# oresat-backplane.net
KiCad netlist of a schematic drawn in EAGLE
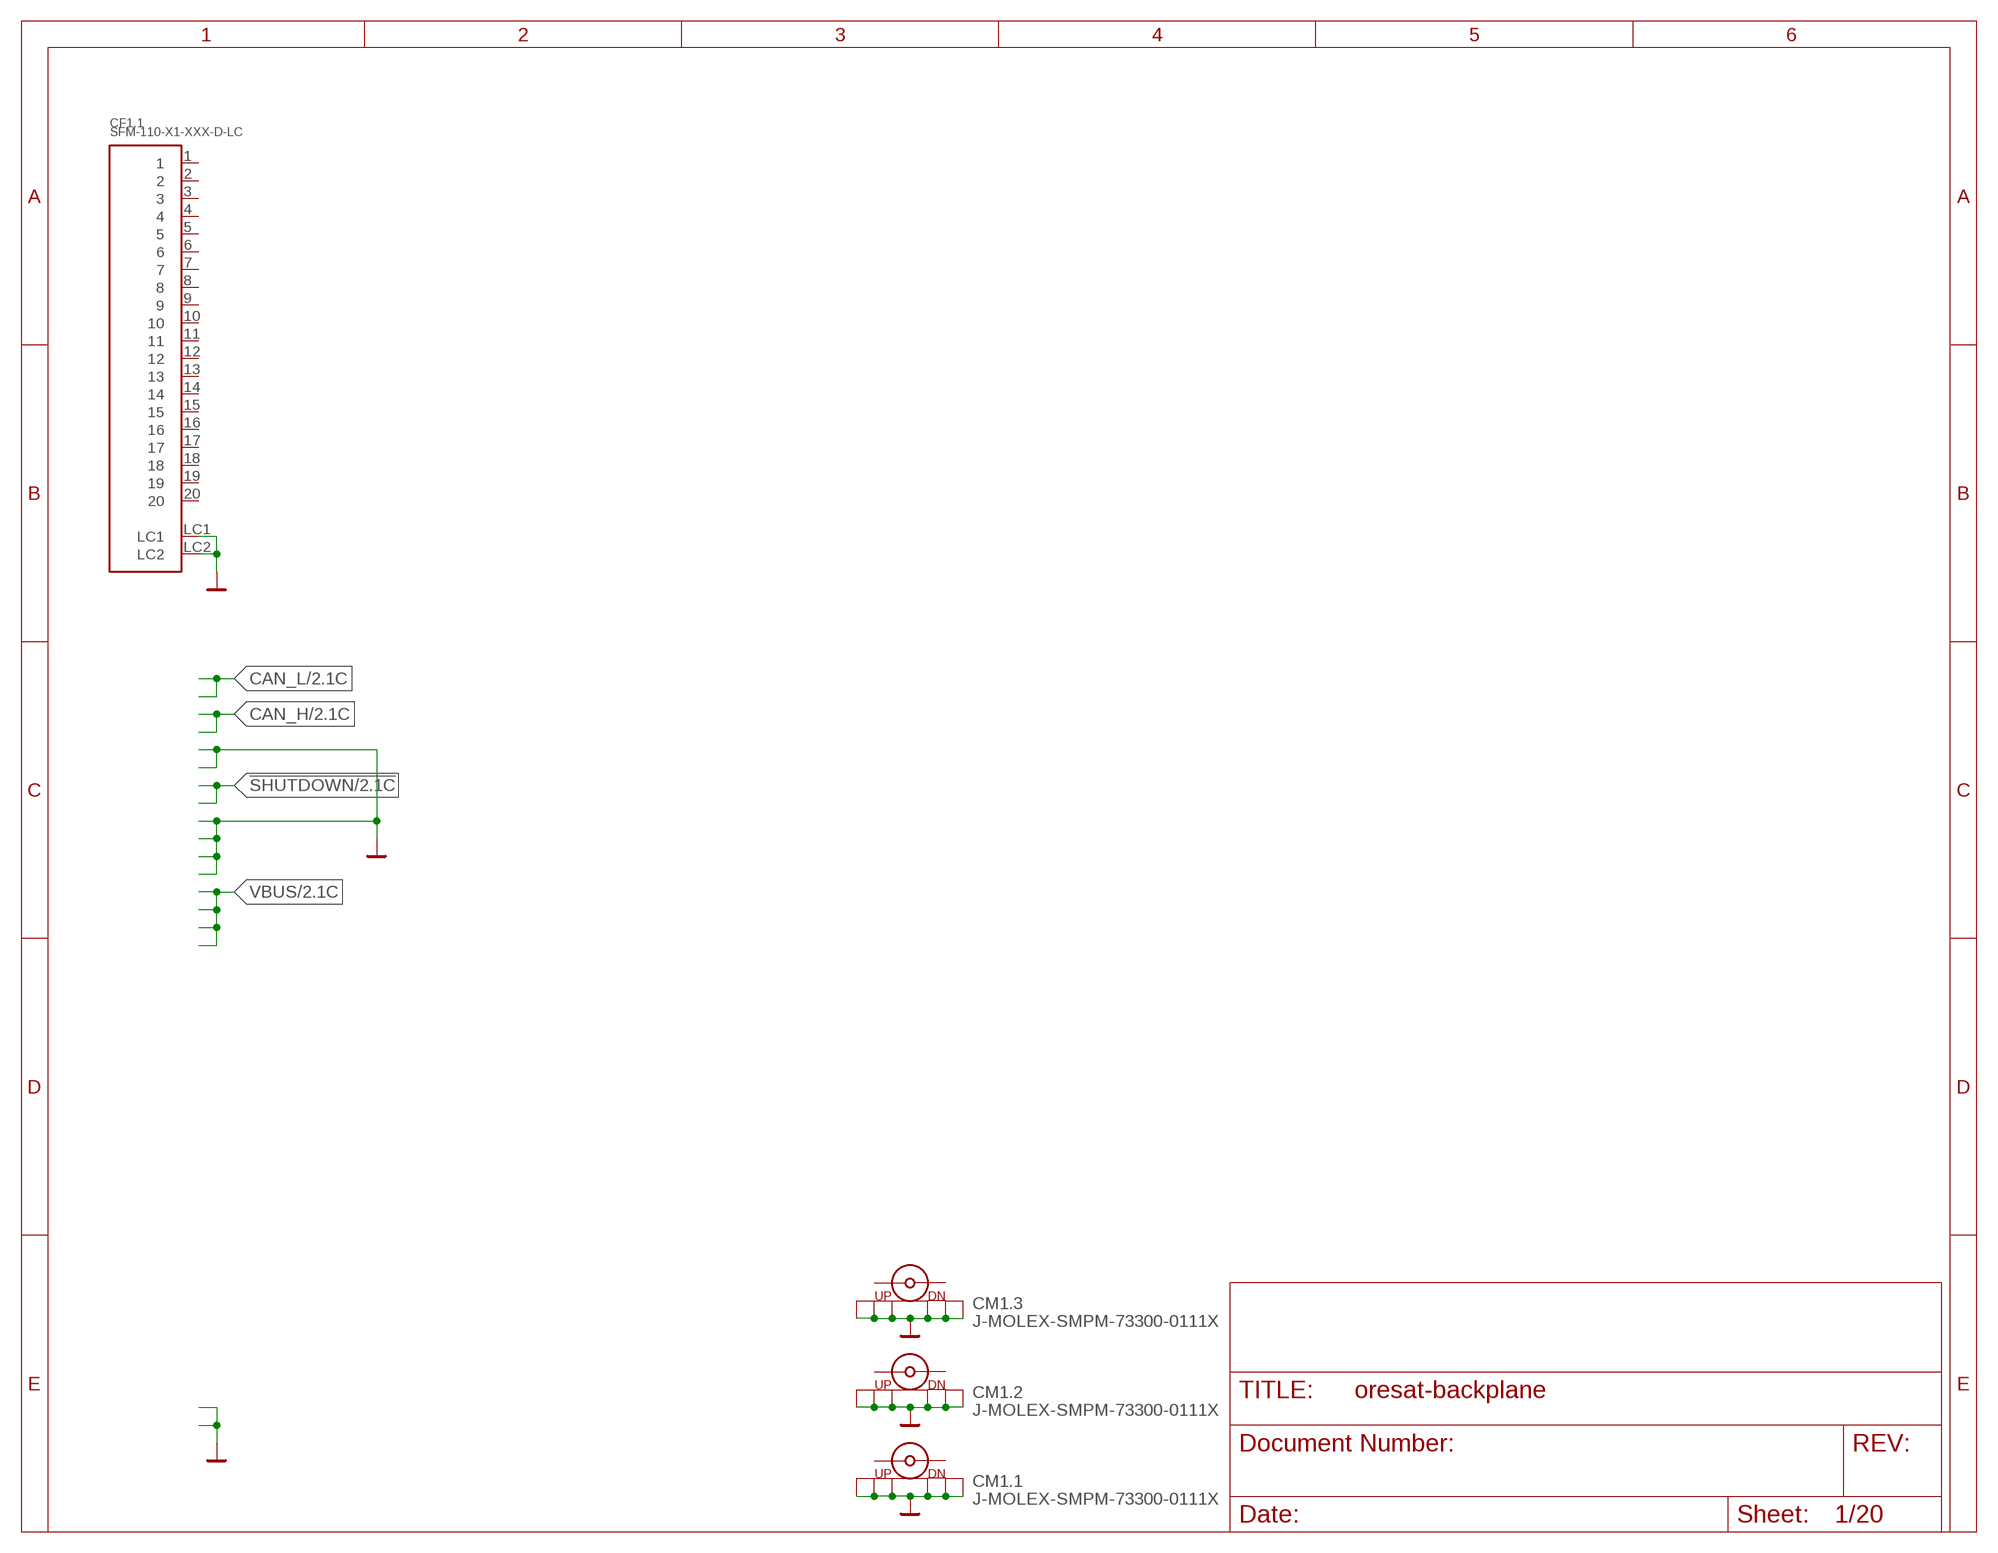
[diagram p0: schematic, sheet 1]
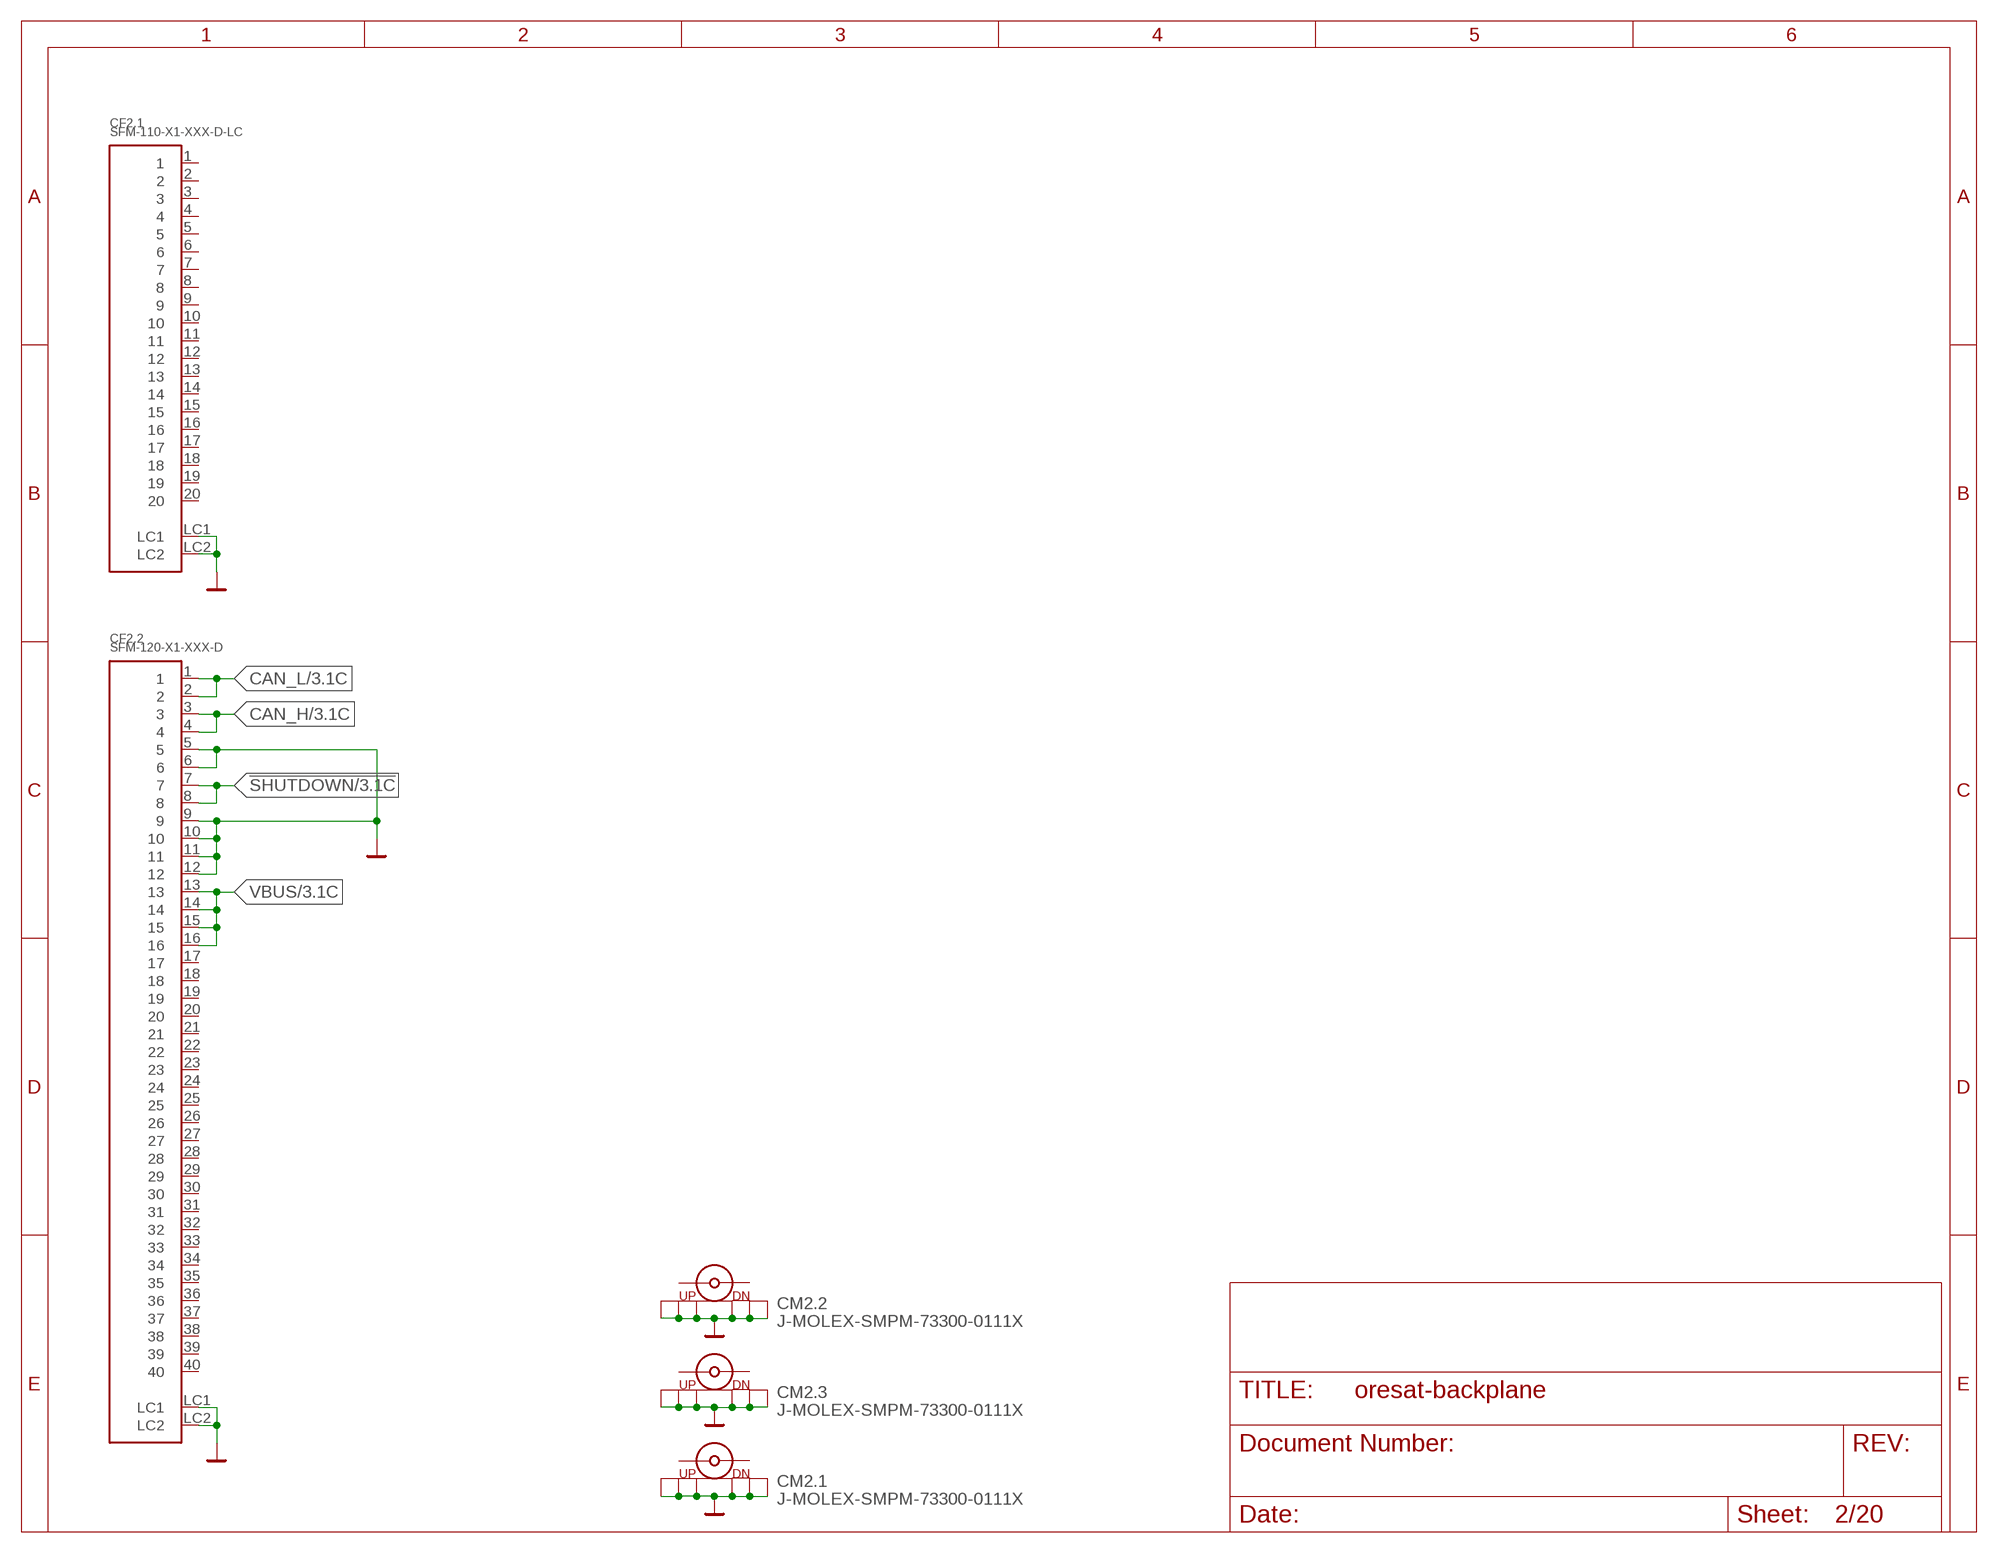
[diagram p1: schematic, sheet 2]
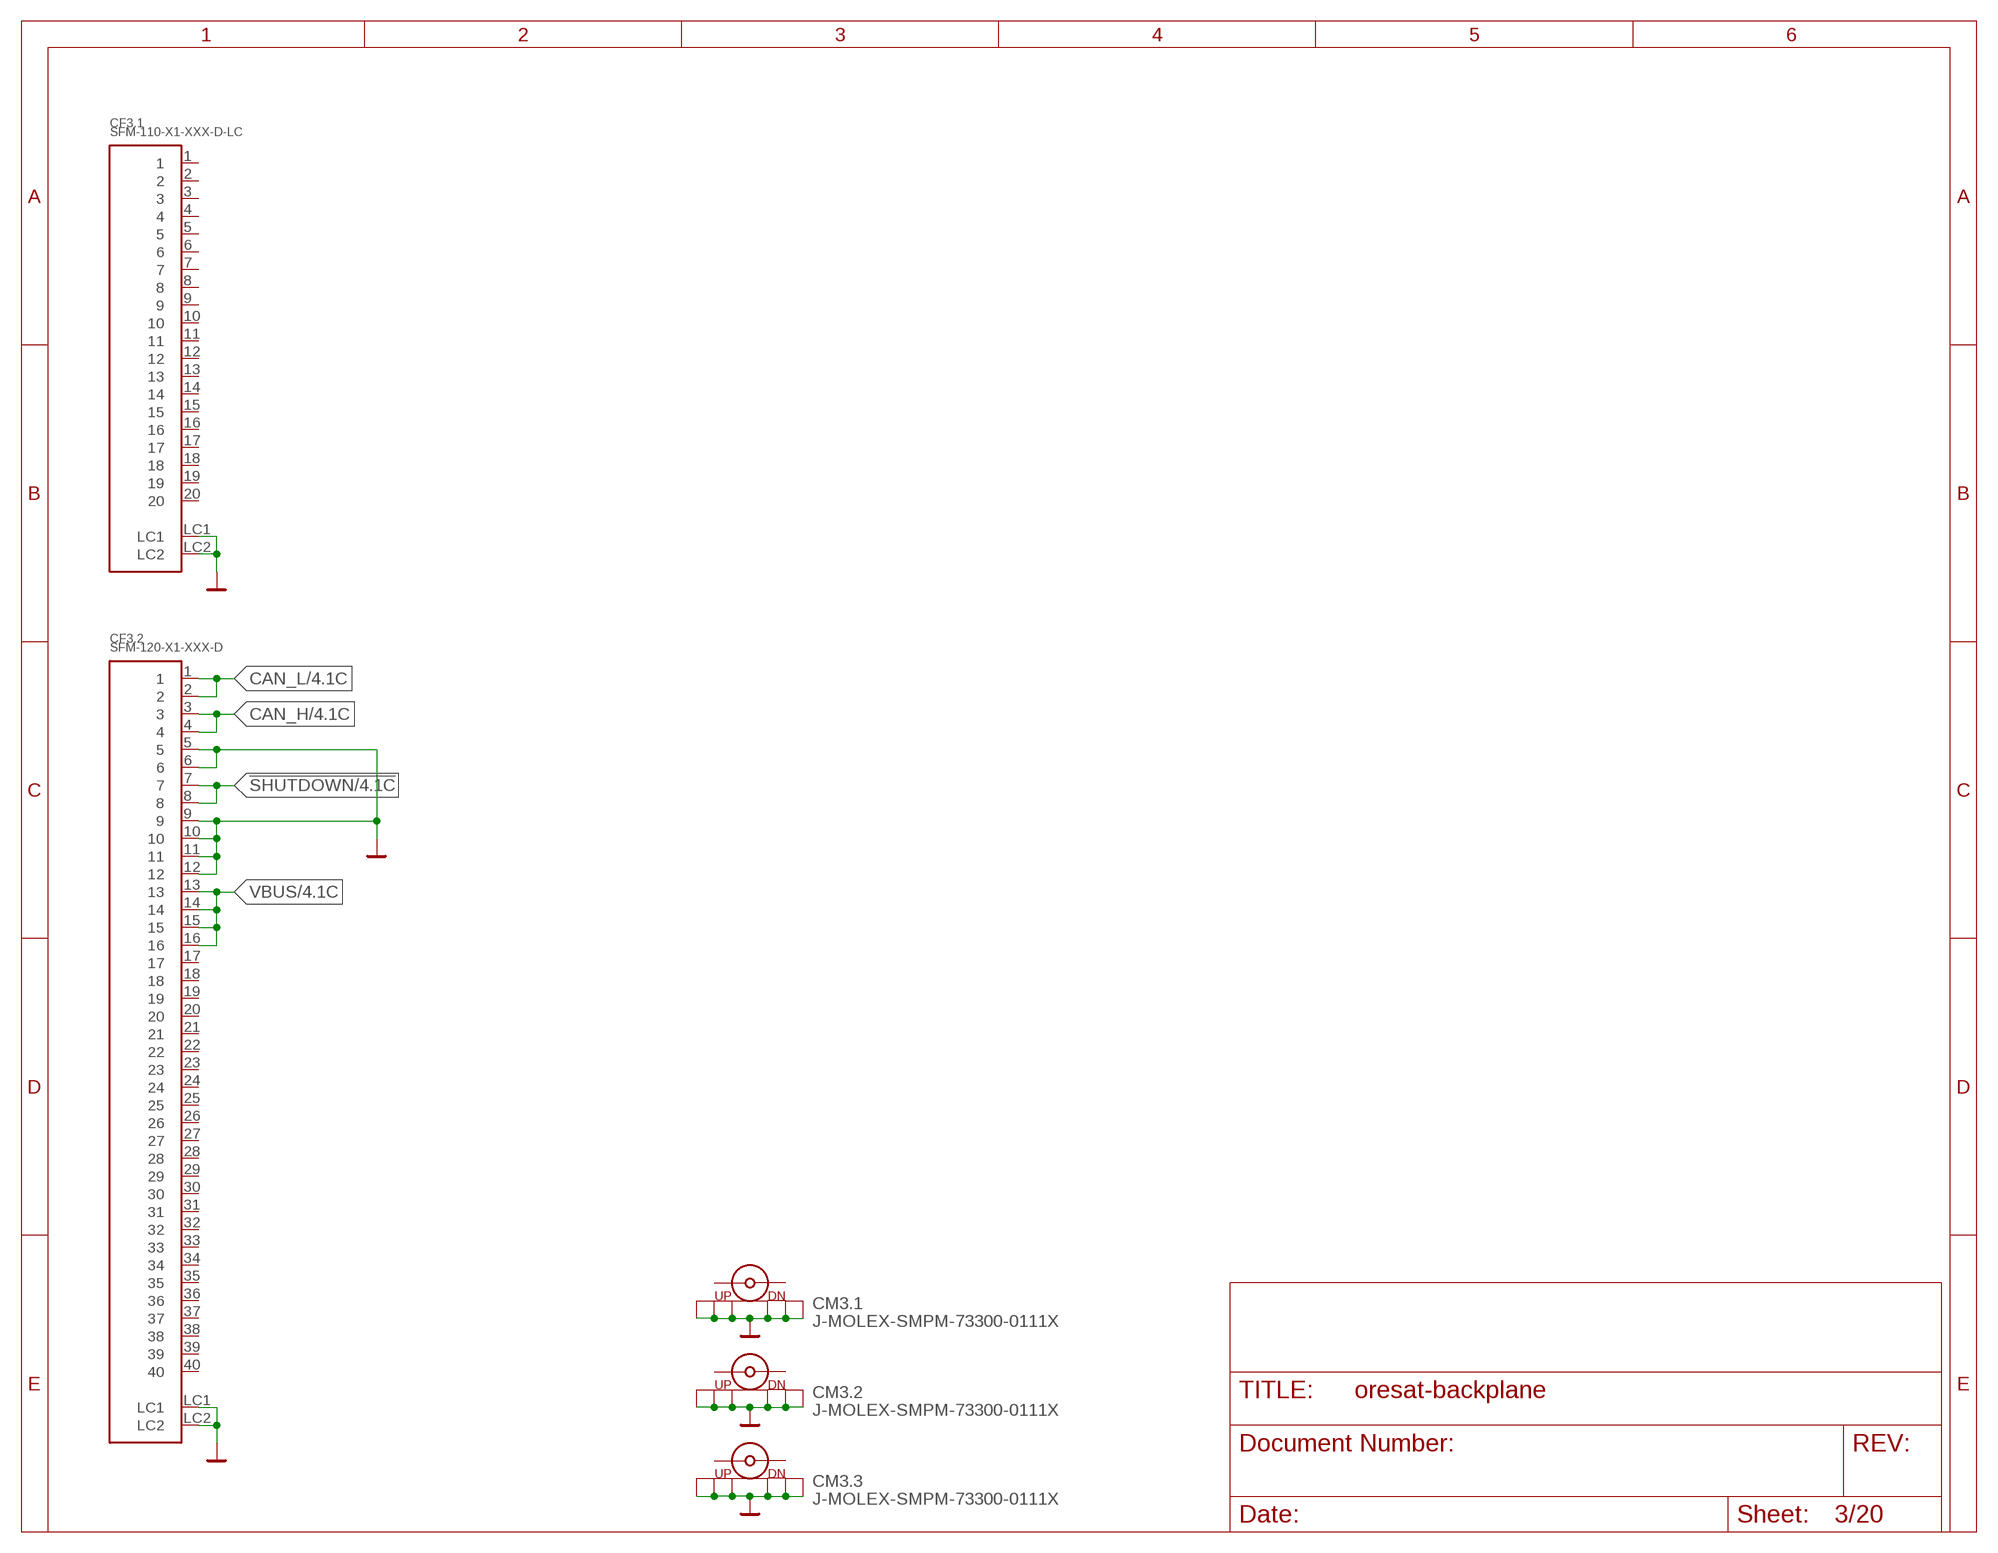
[diagram p2: schematic, sheet 3]
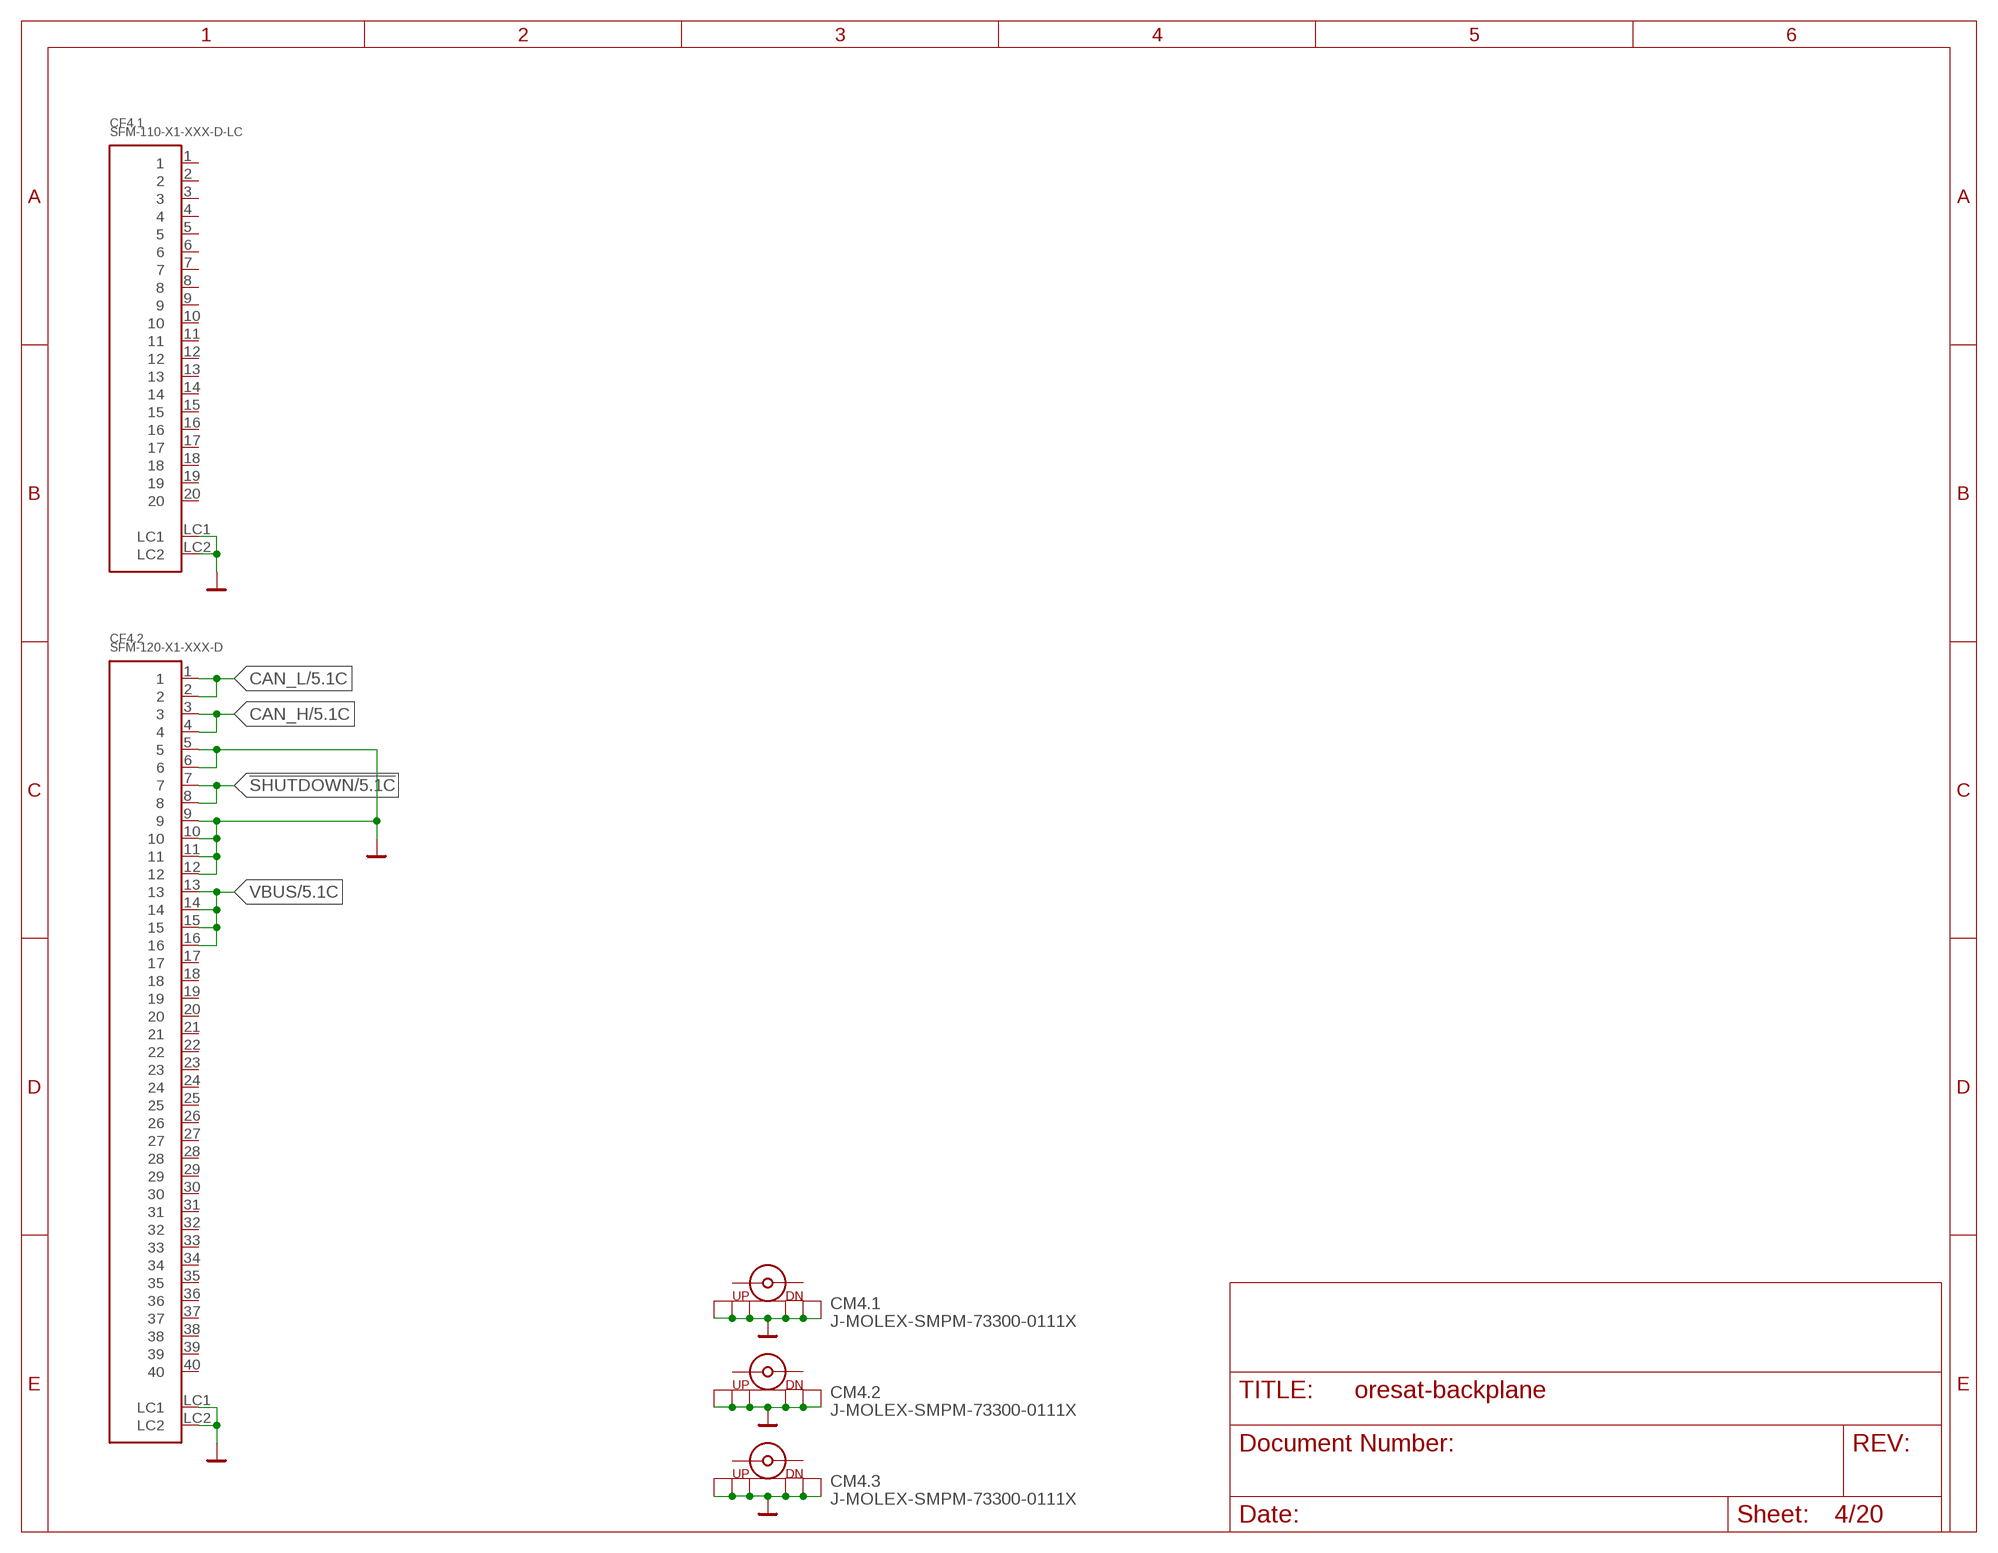
[diagram p3: schematic, sheet 4]
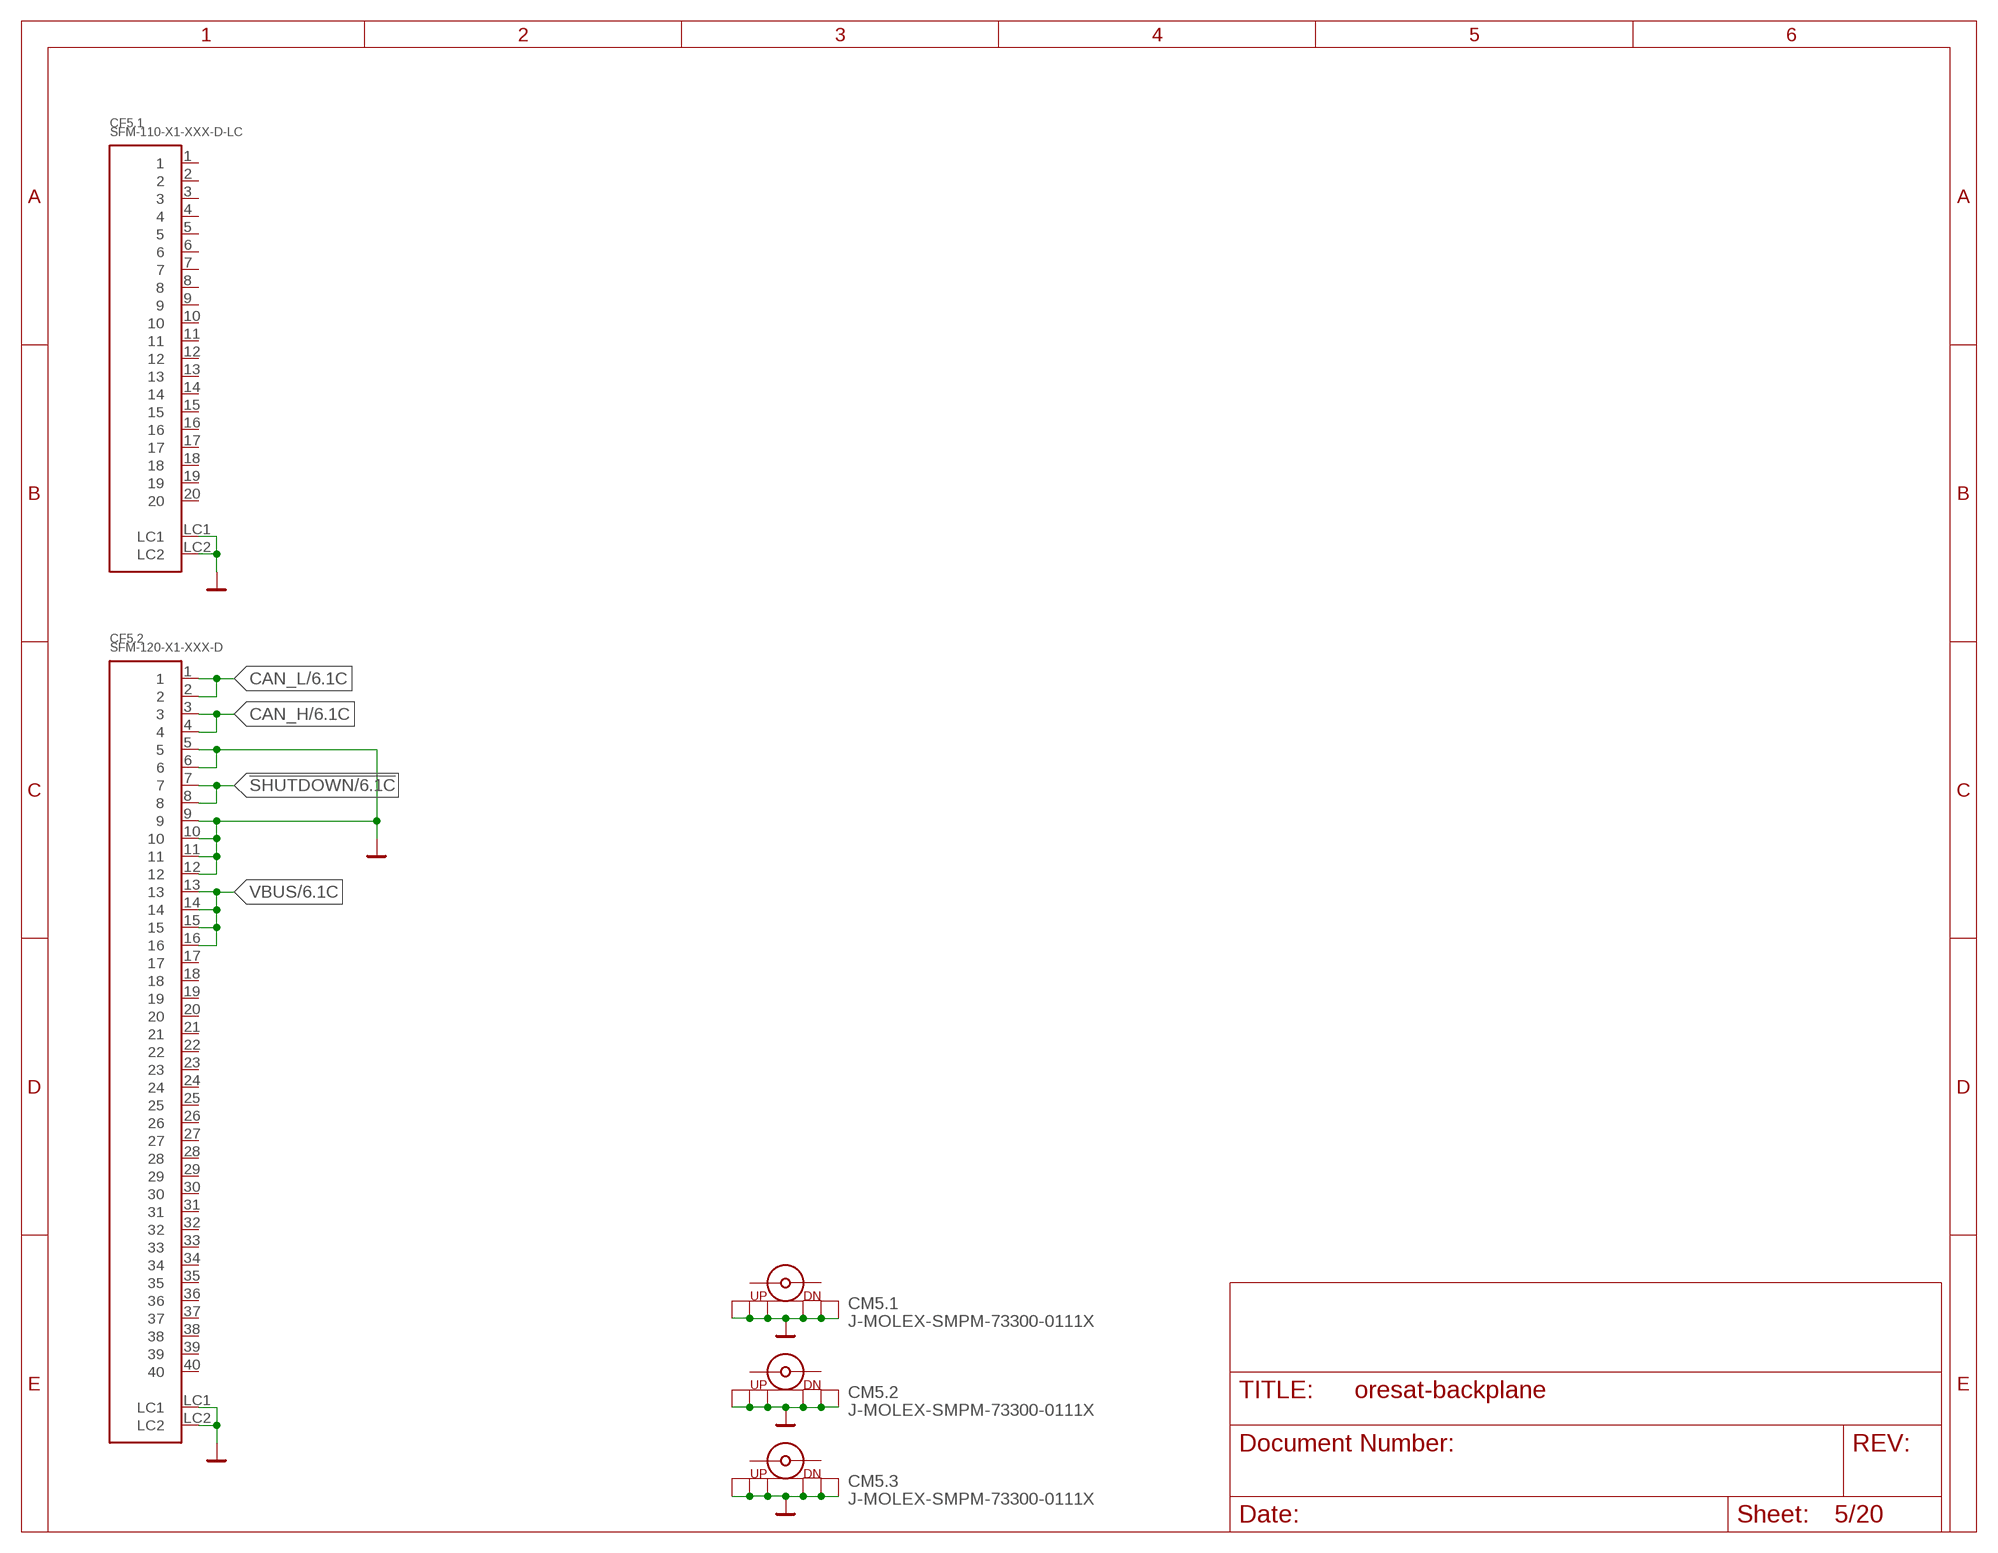
[diagram p4: schematic, sheet 5]
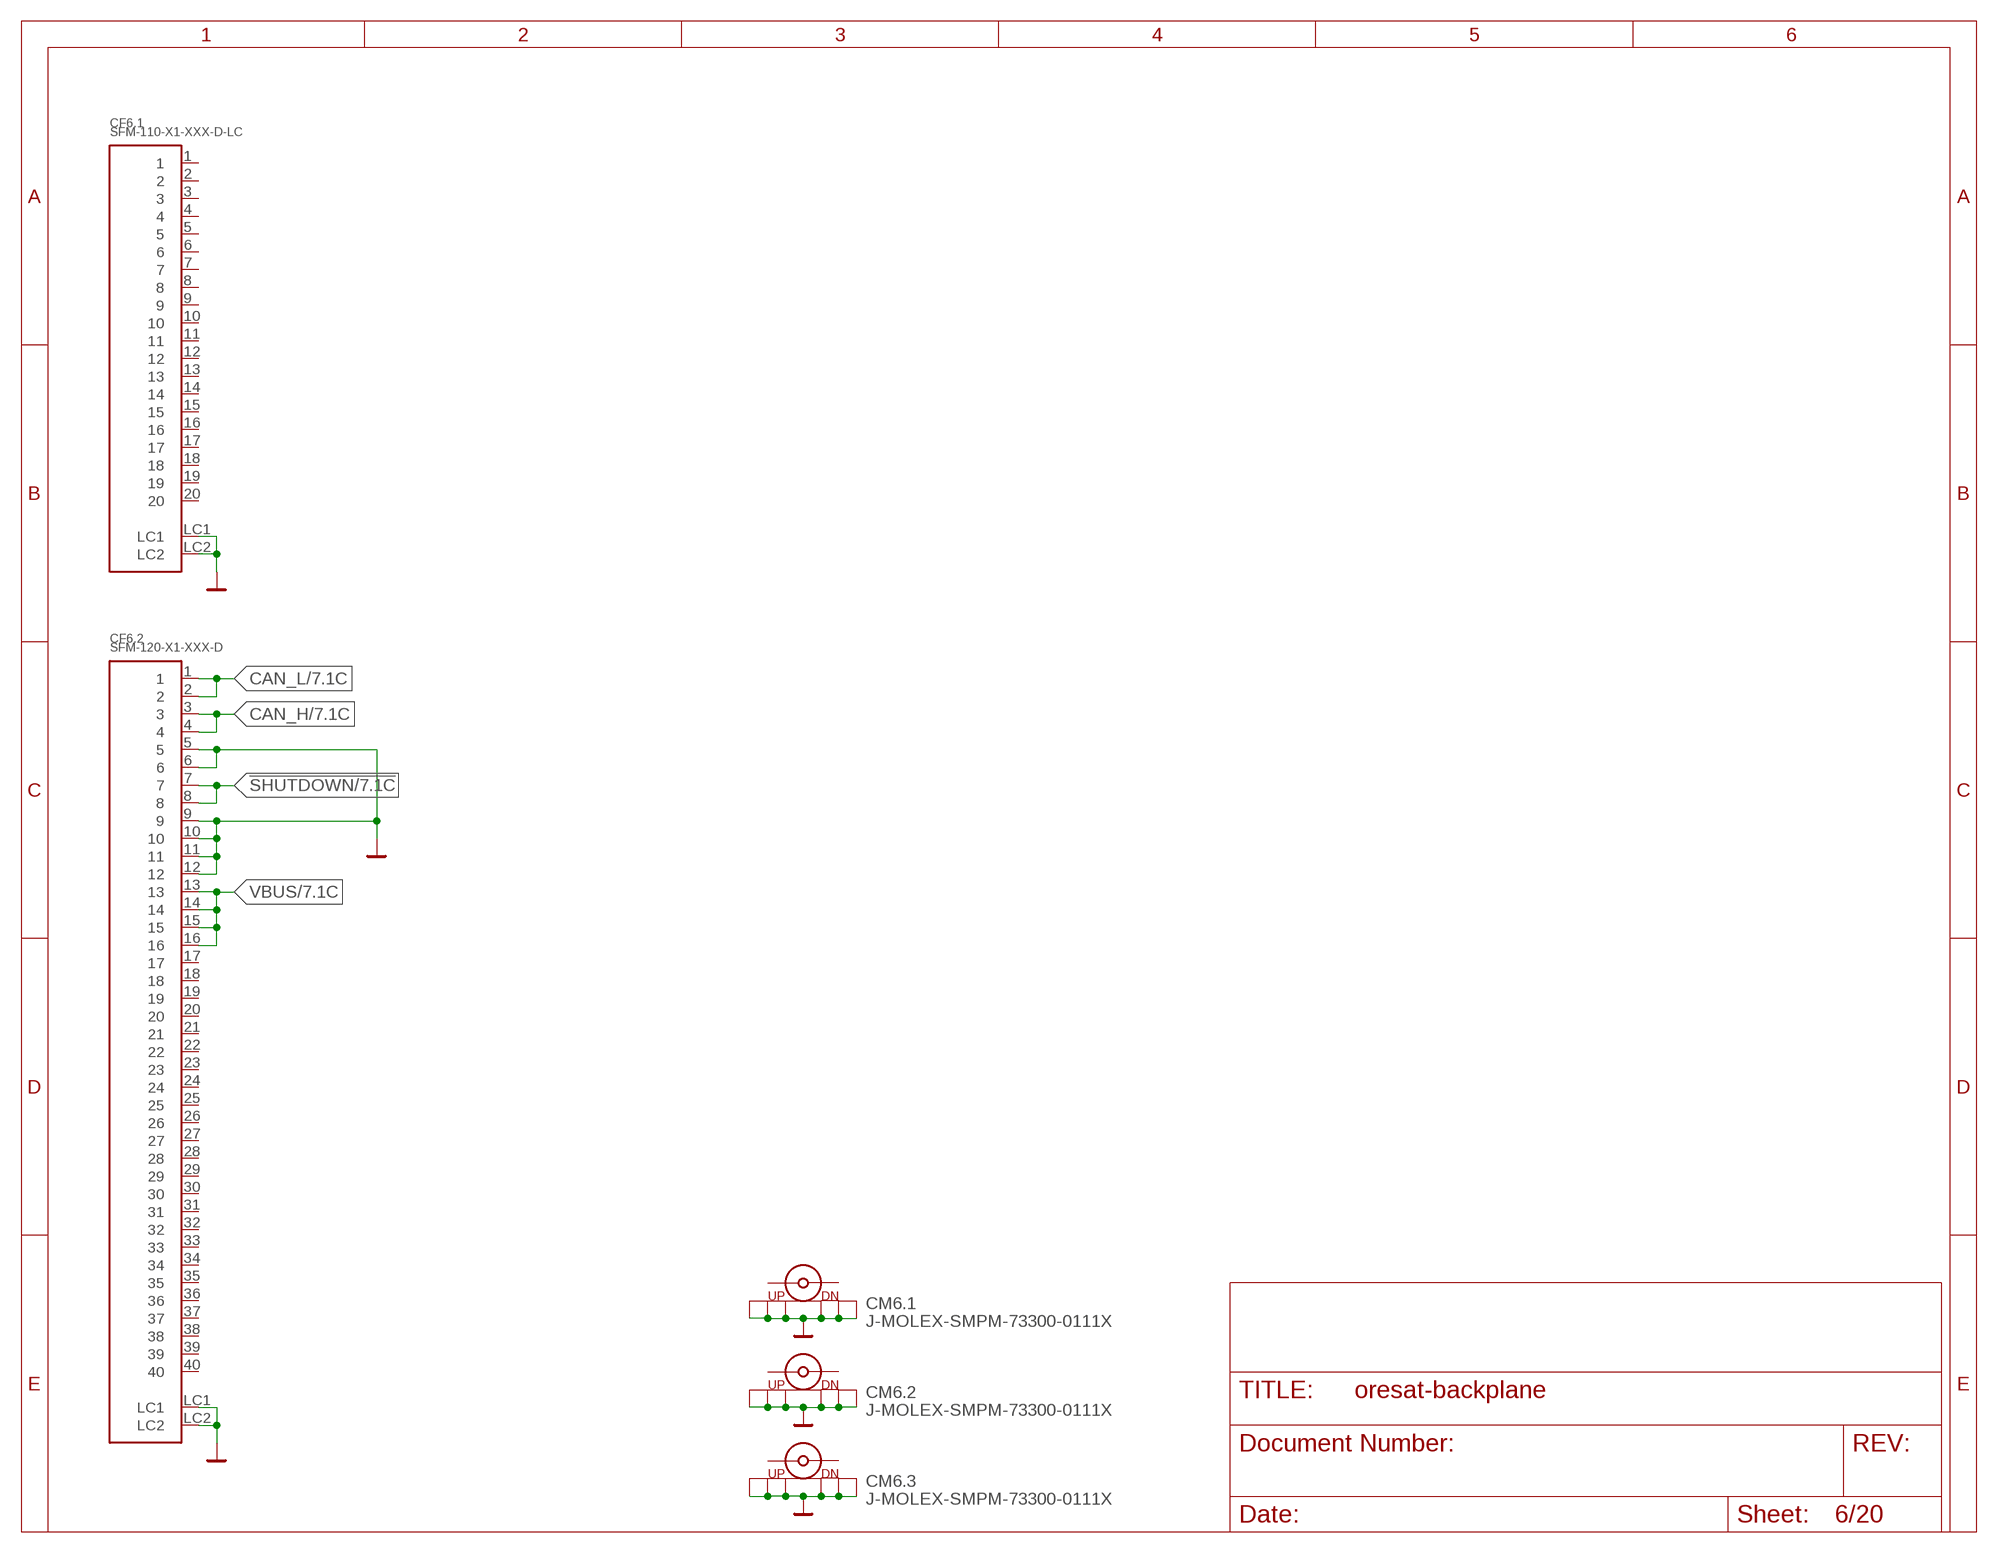
[diagram p5: schematic, sheet 6]
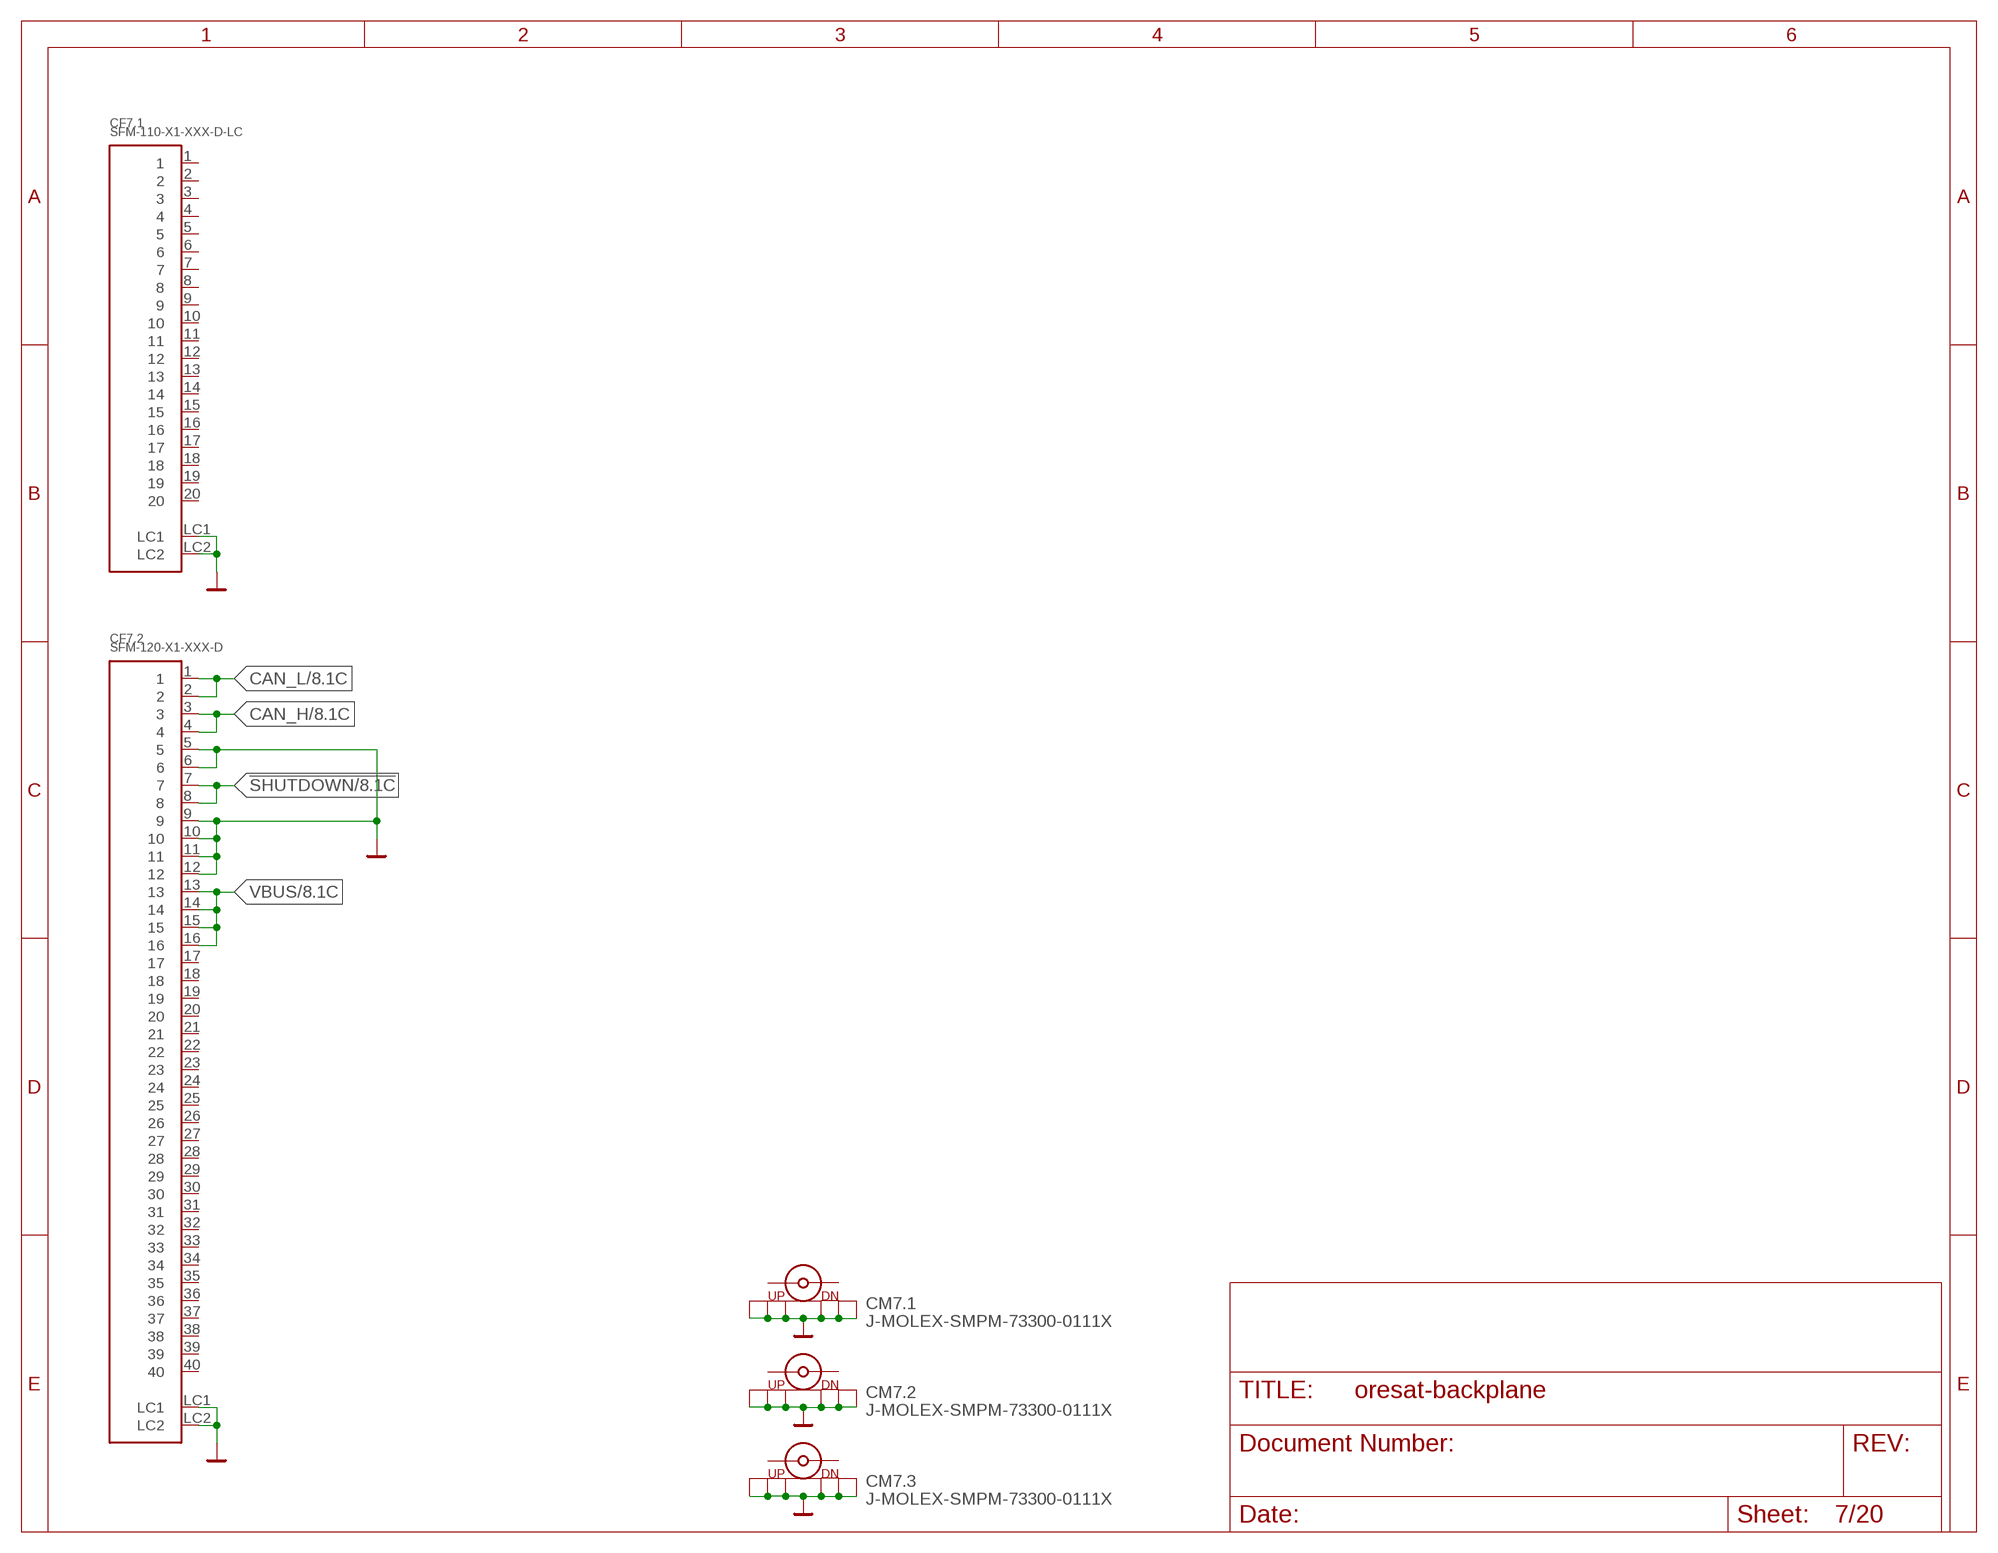
[diagram p6: schematic, sheet 7]
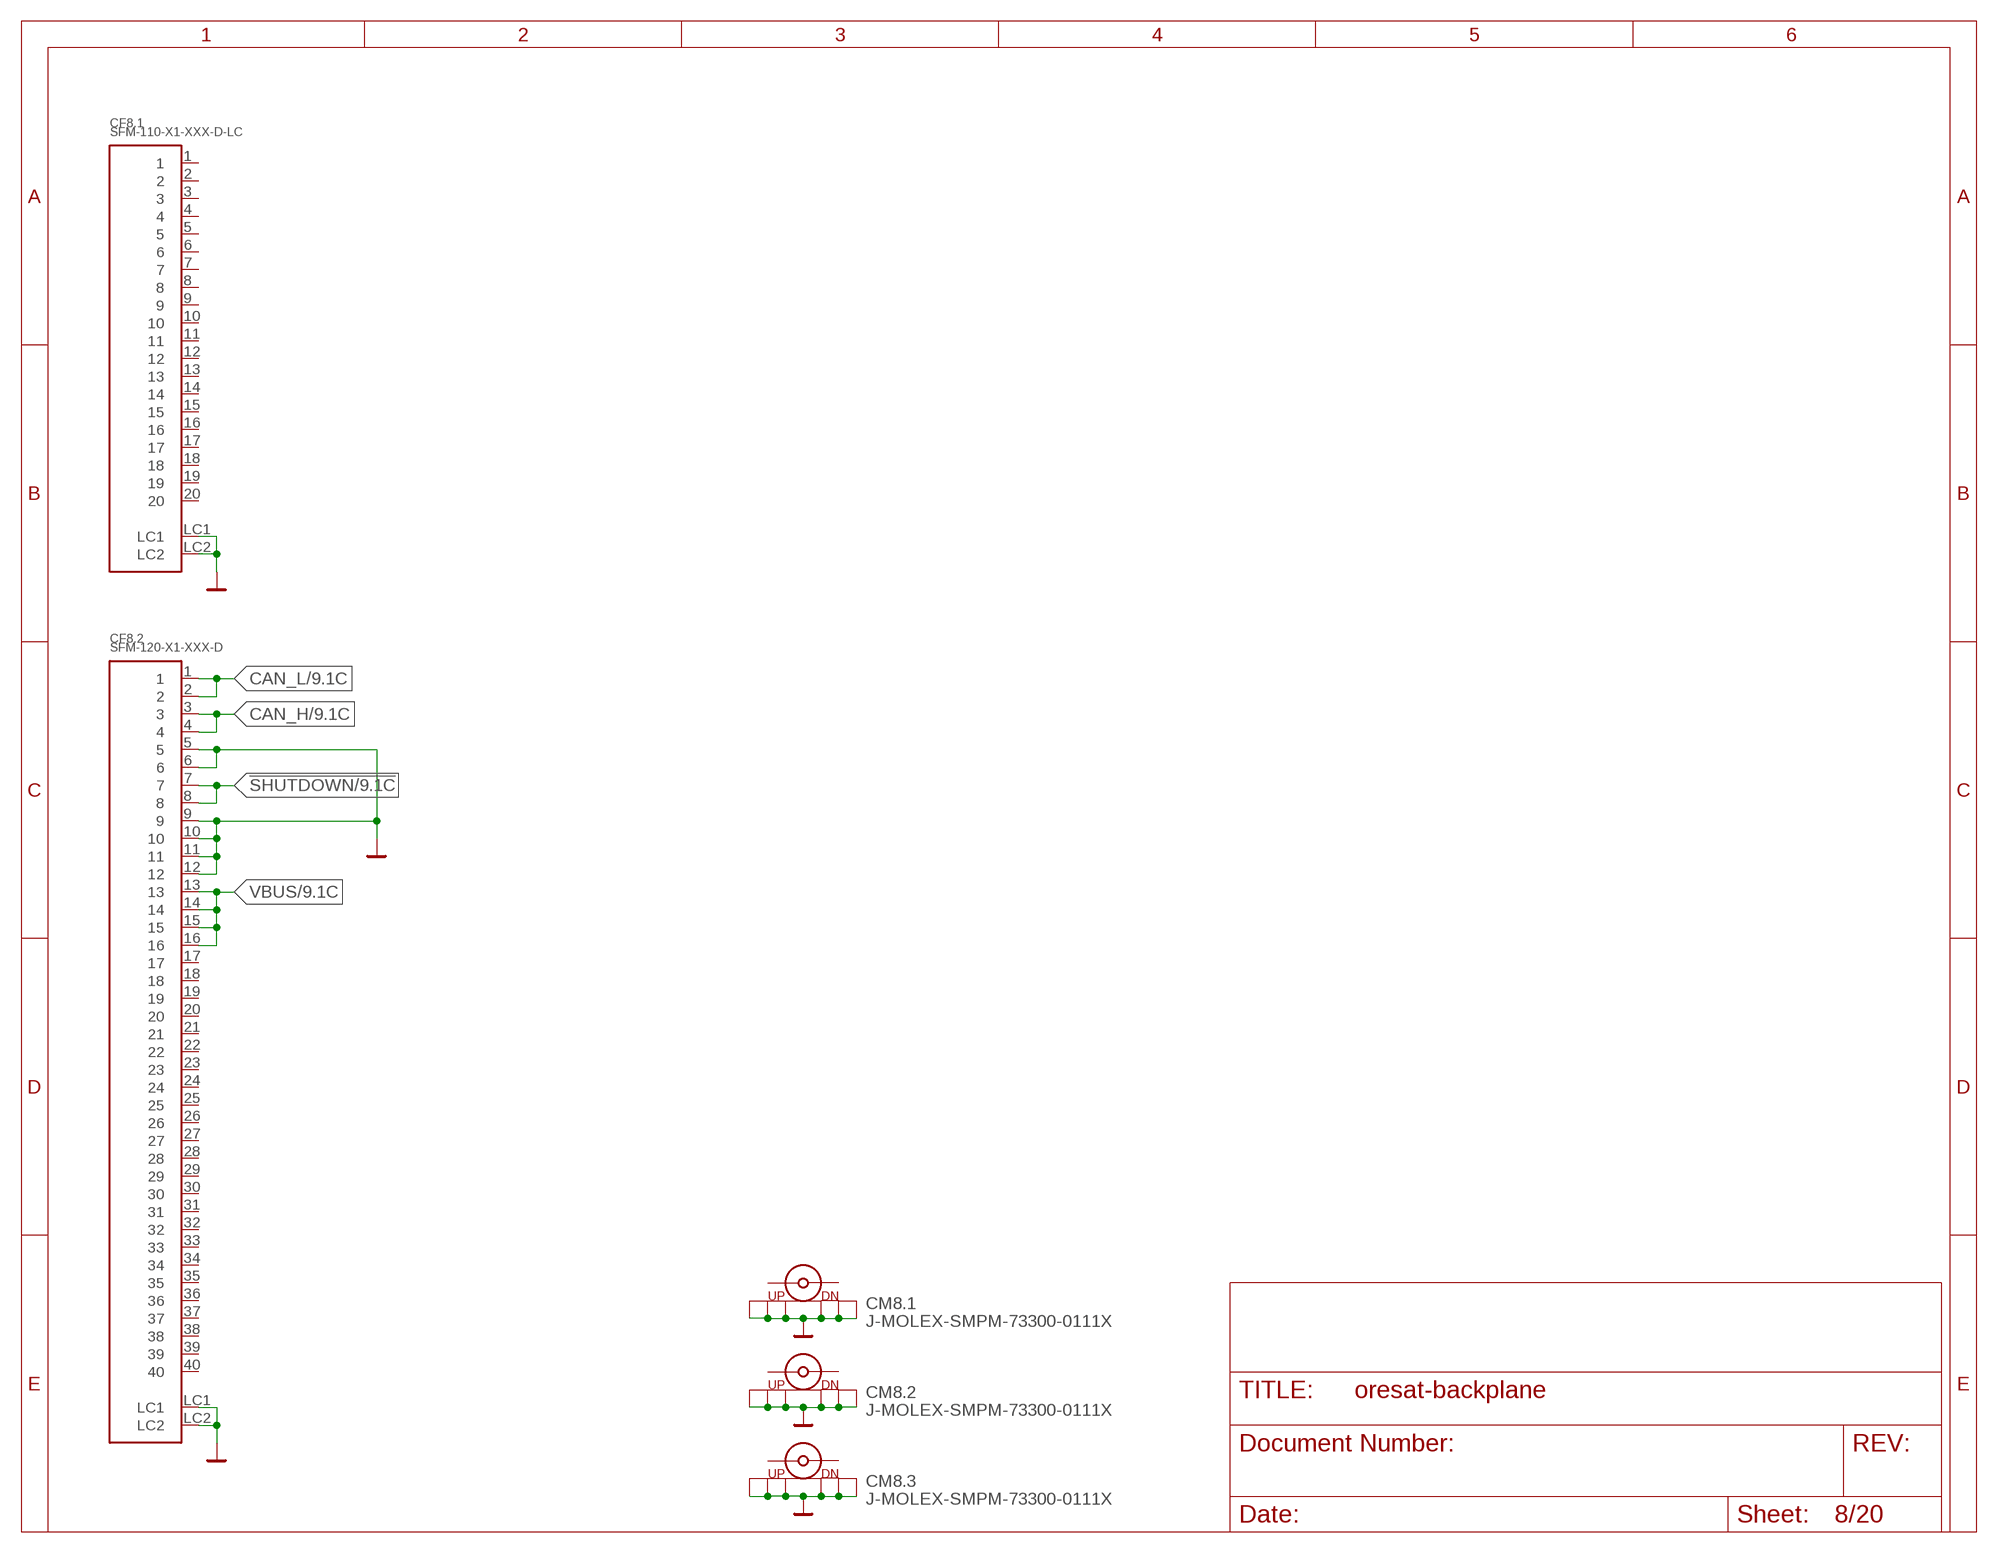
[diagram p7: schematic, sheet 8]
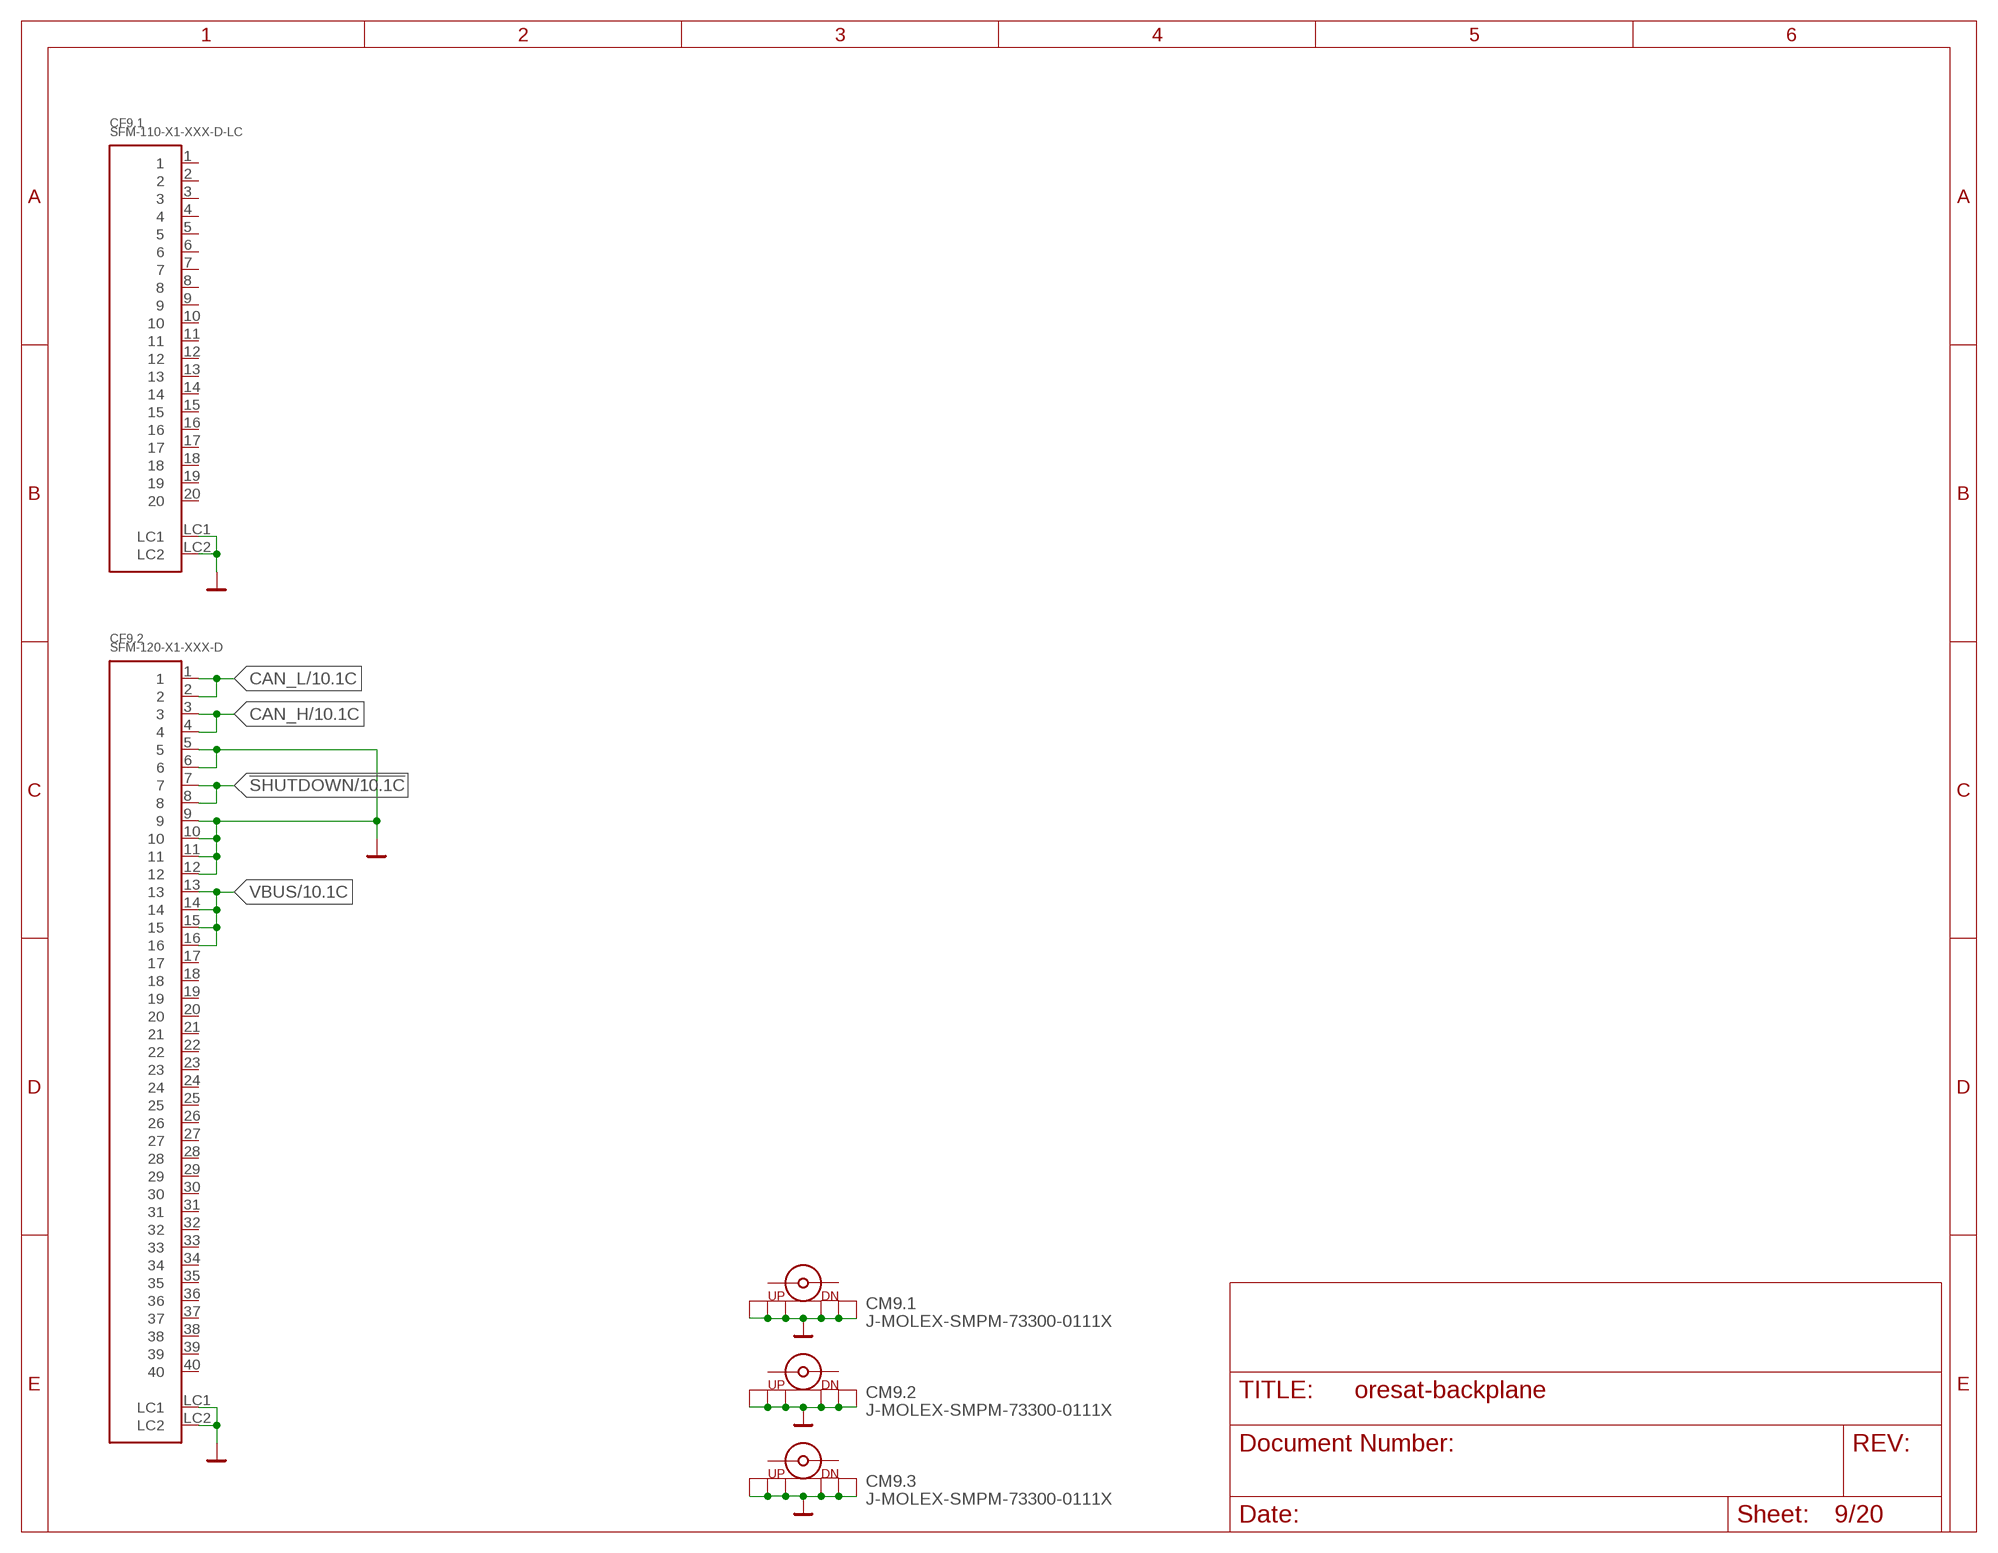
[diagram p8: schematic, sheet 9]
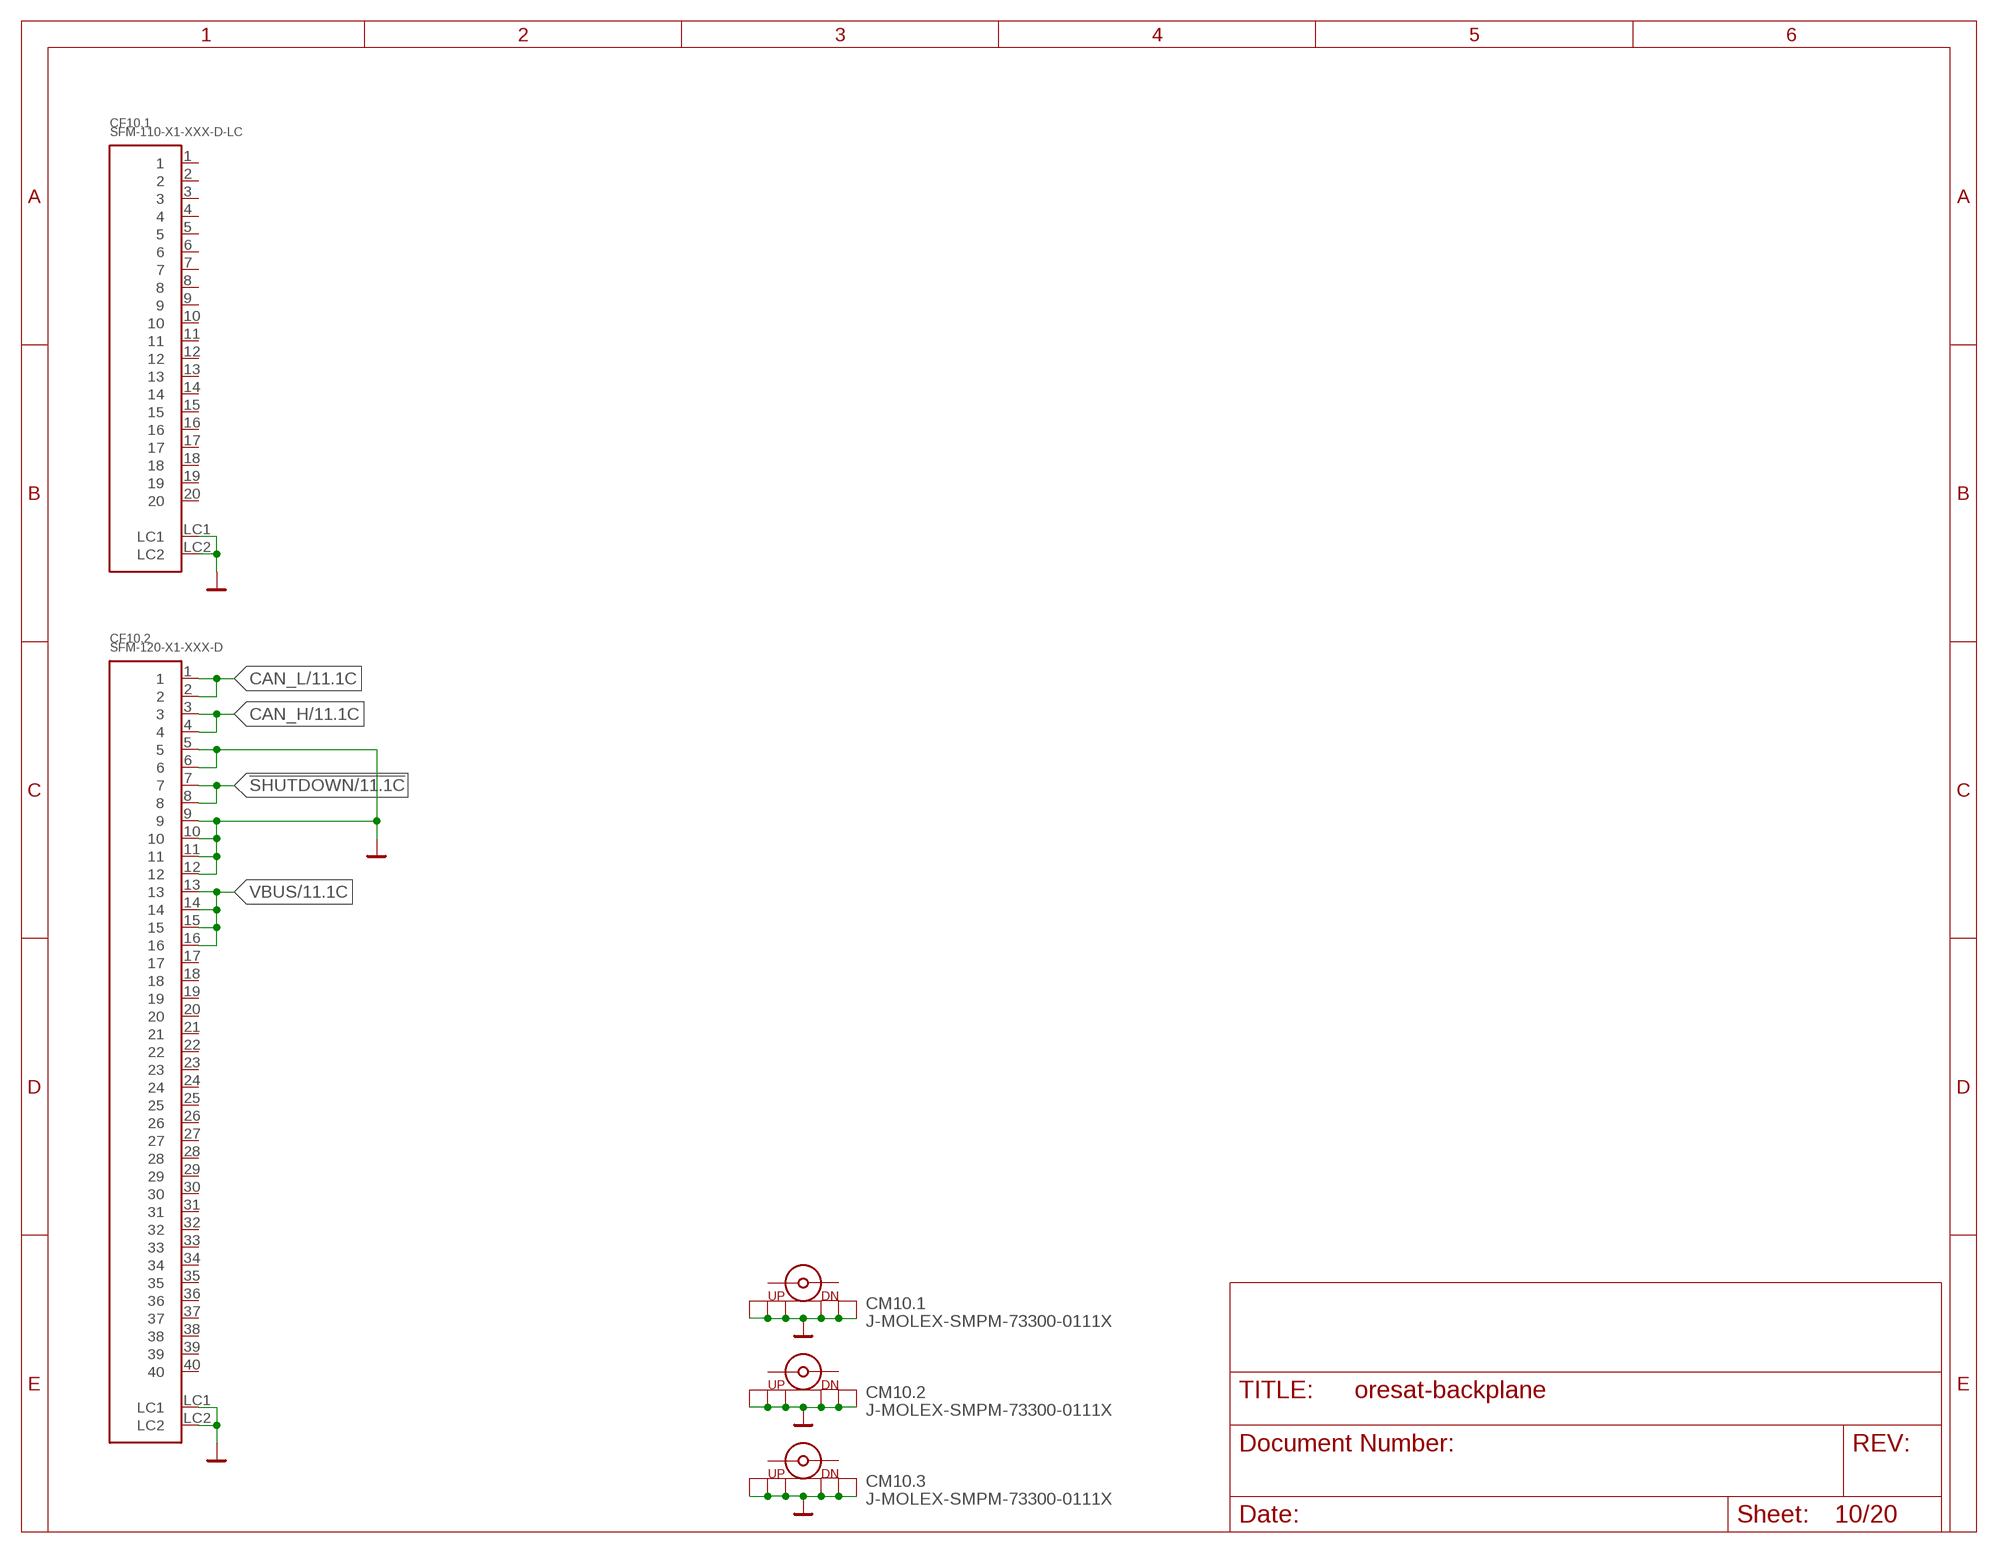
[diagram p9: schematic, sheet 10]
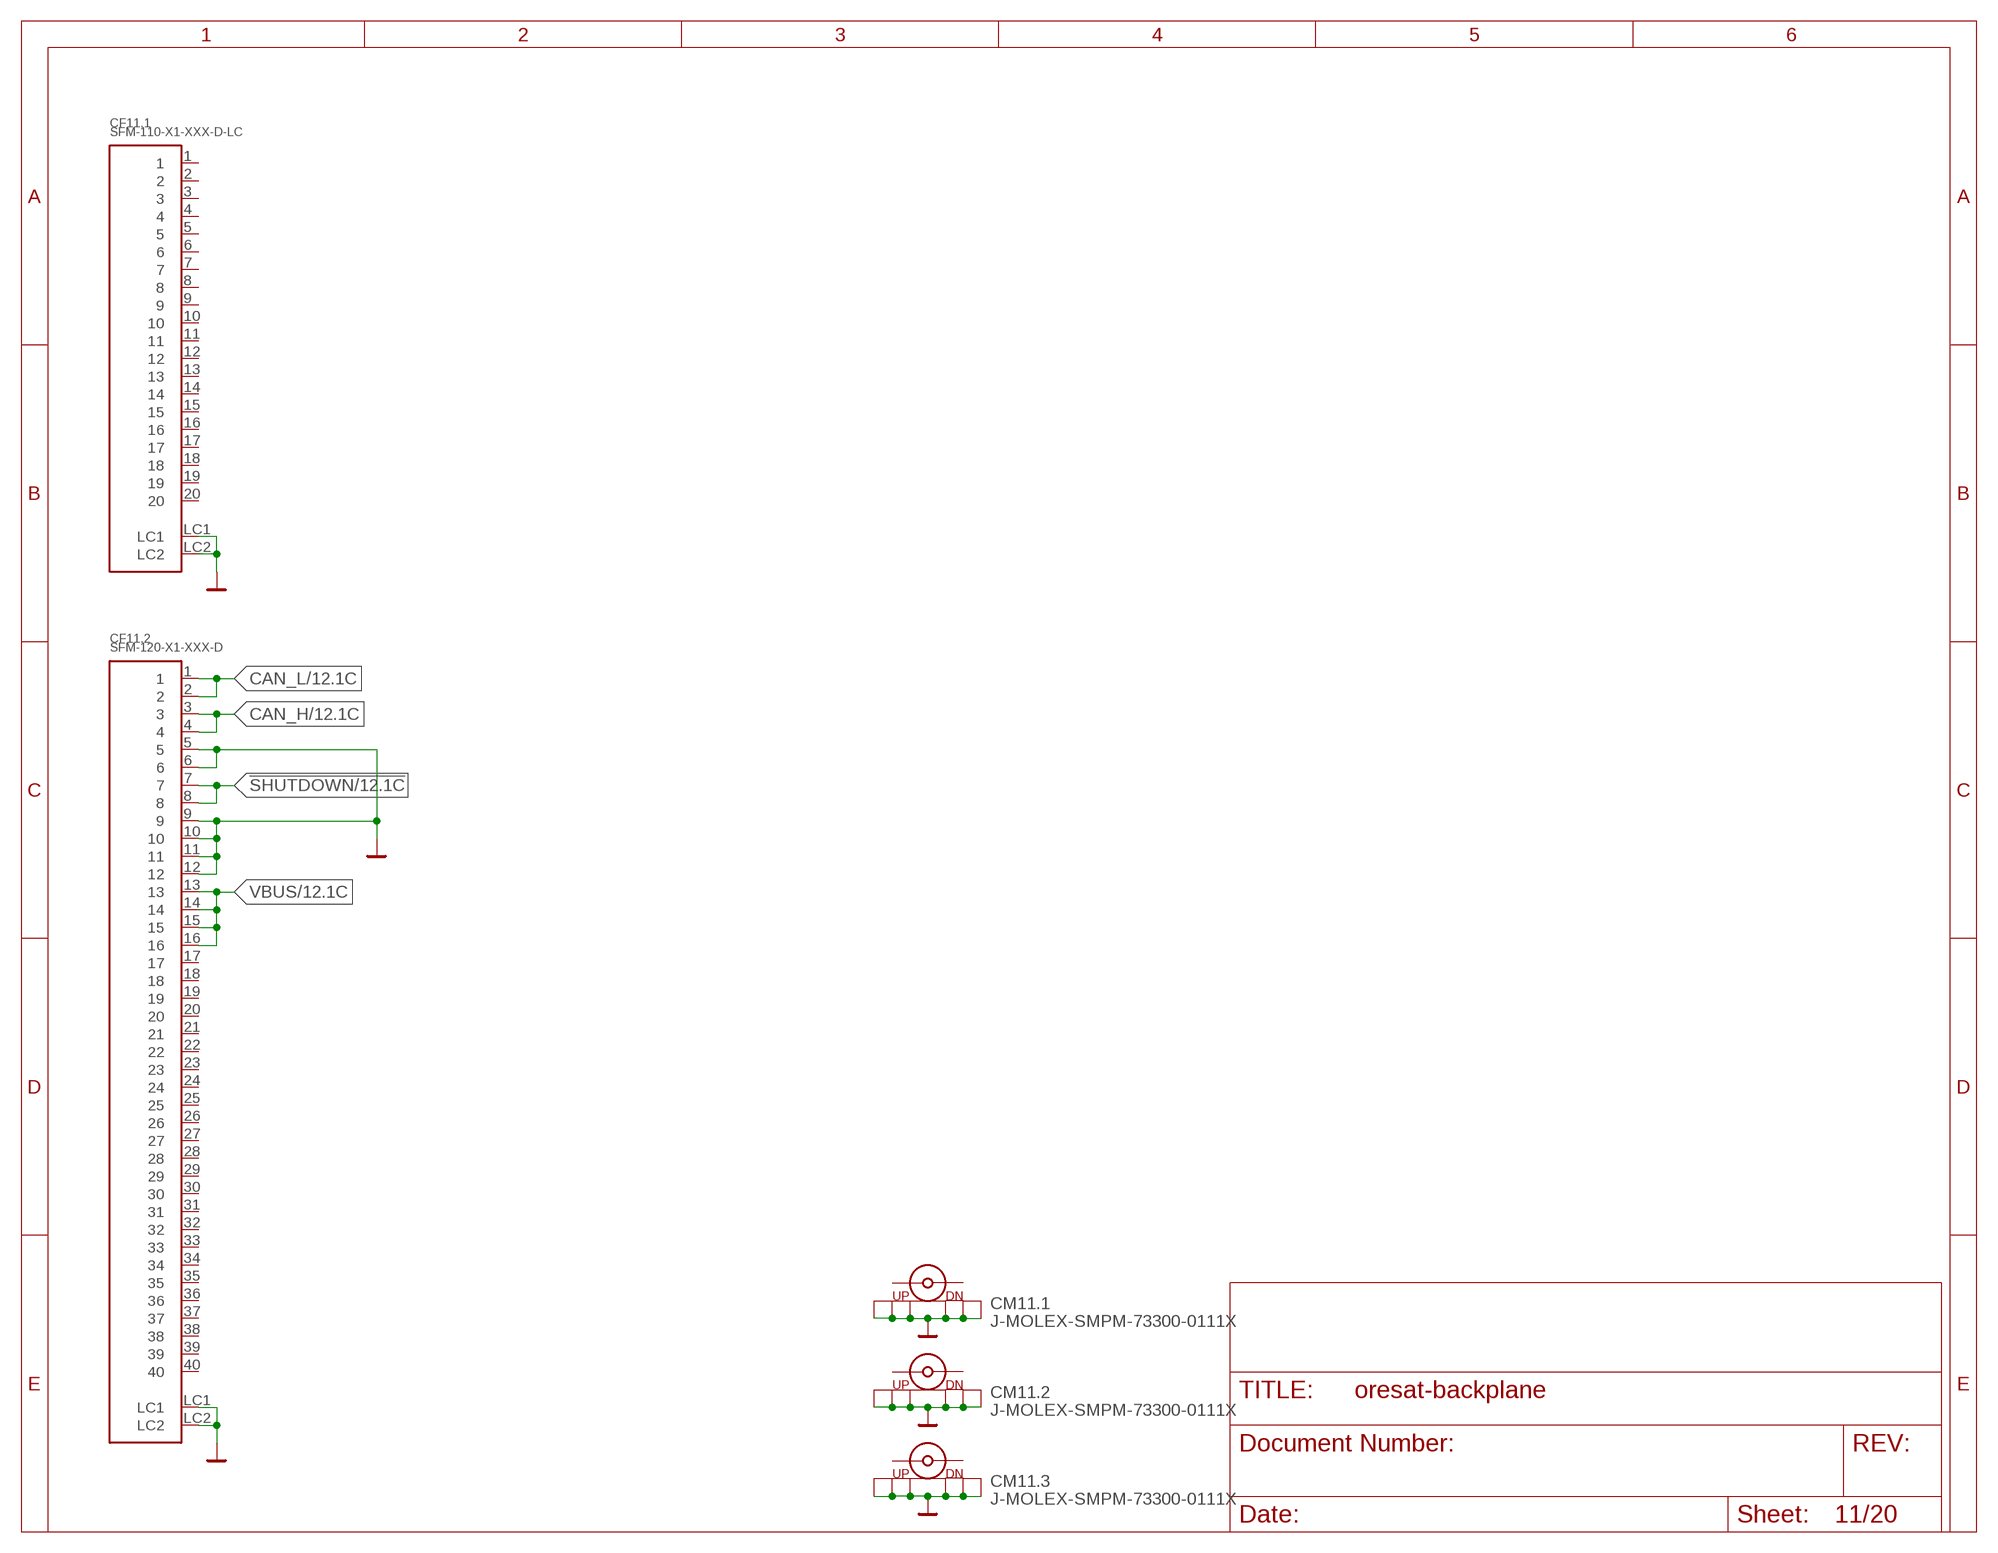
[diagram p10: schematic, sheet 11]
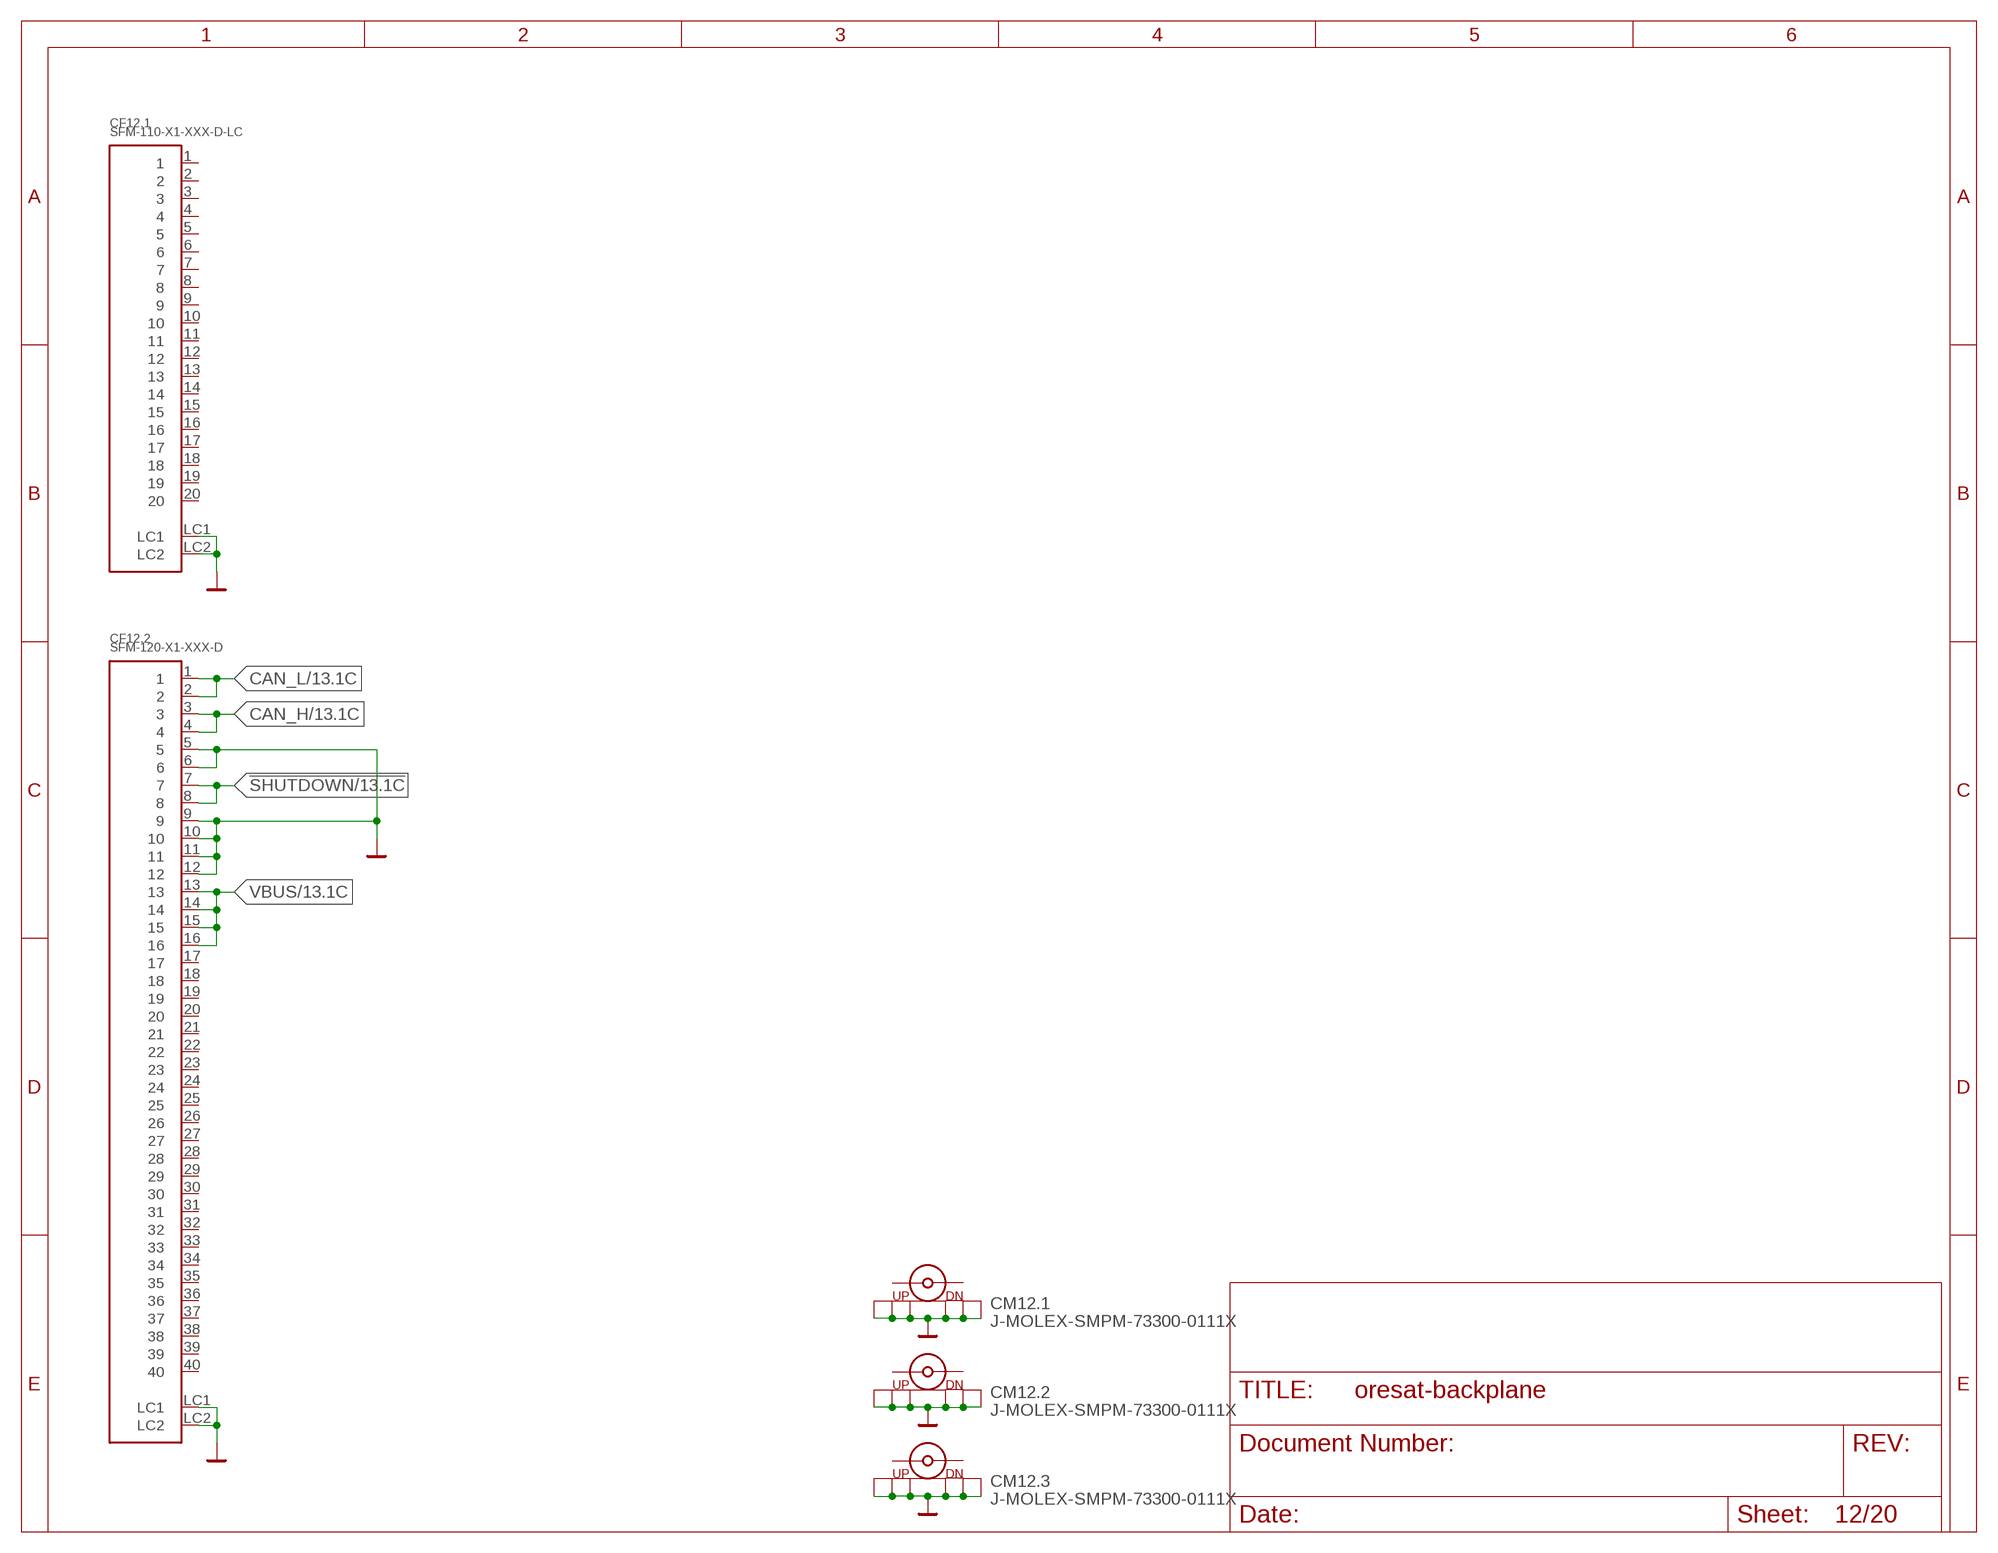
[diagram p11: schematic, sheet 12]
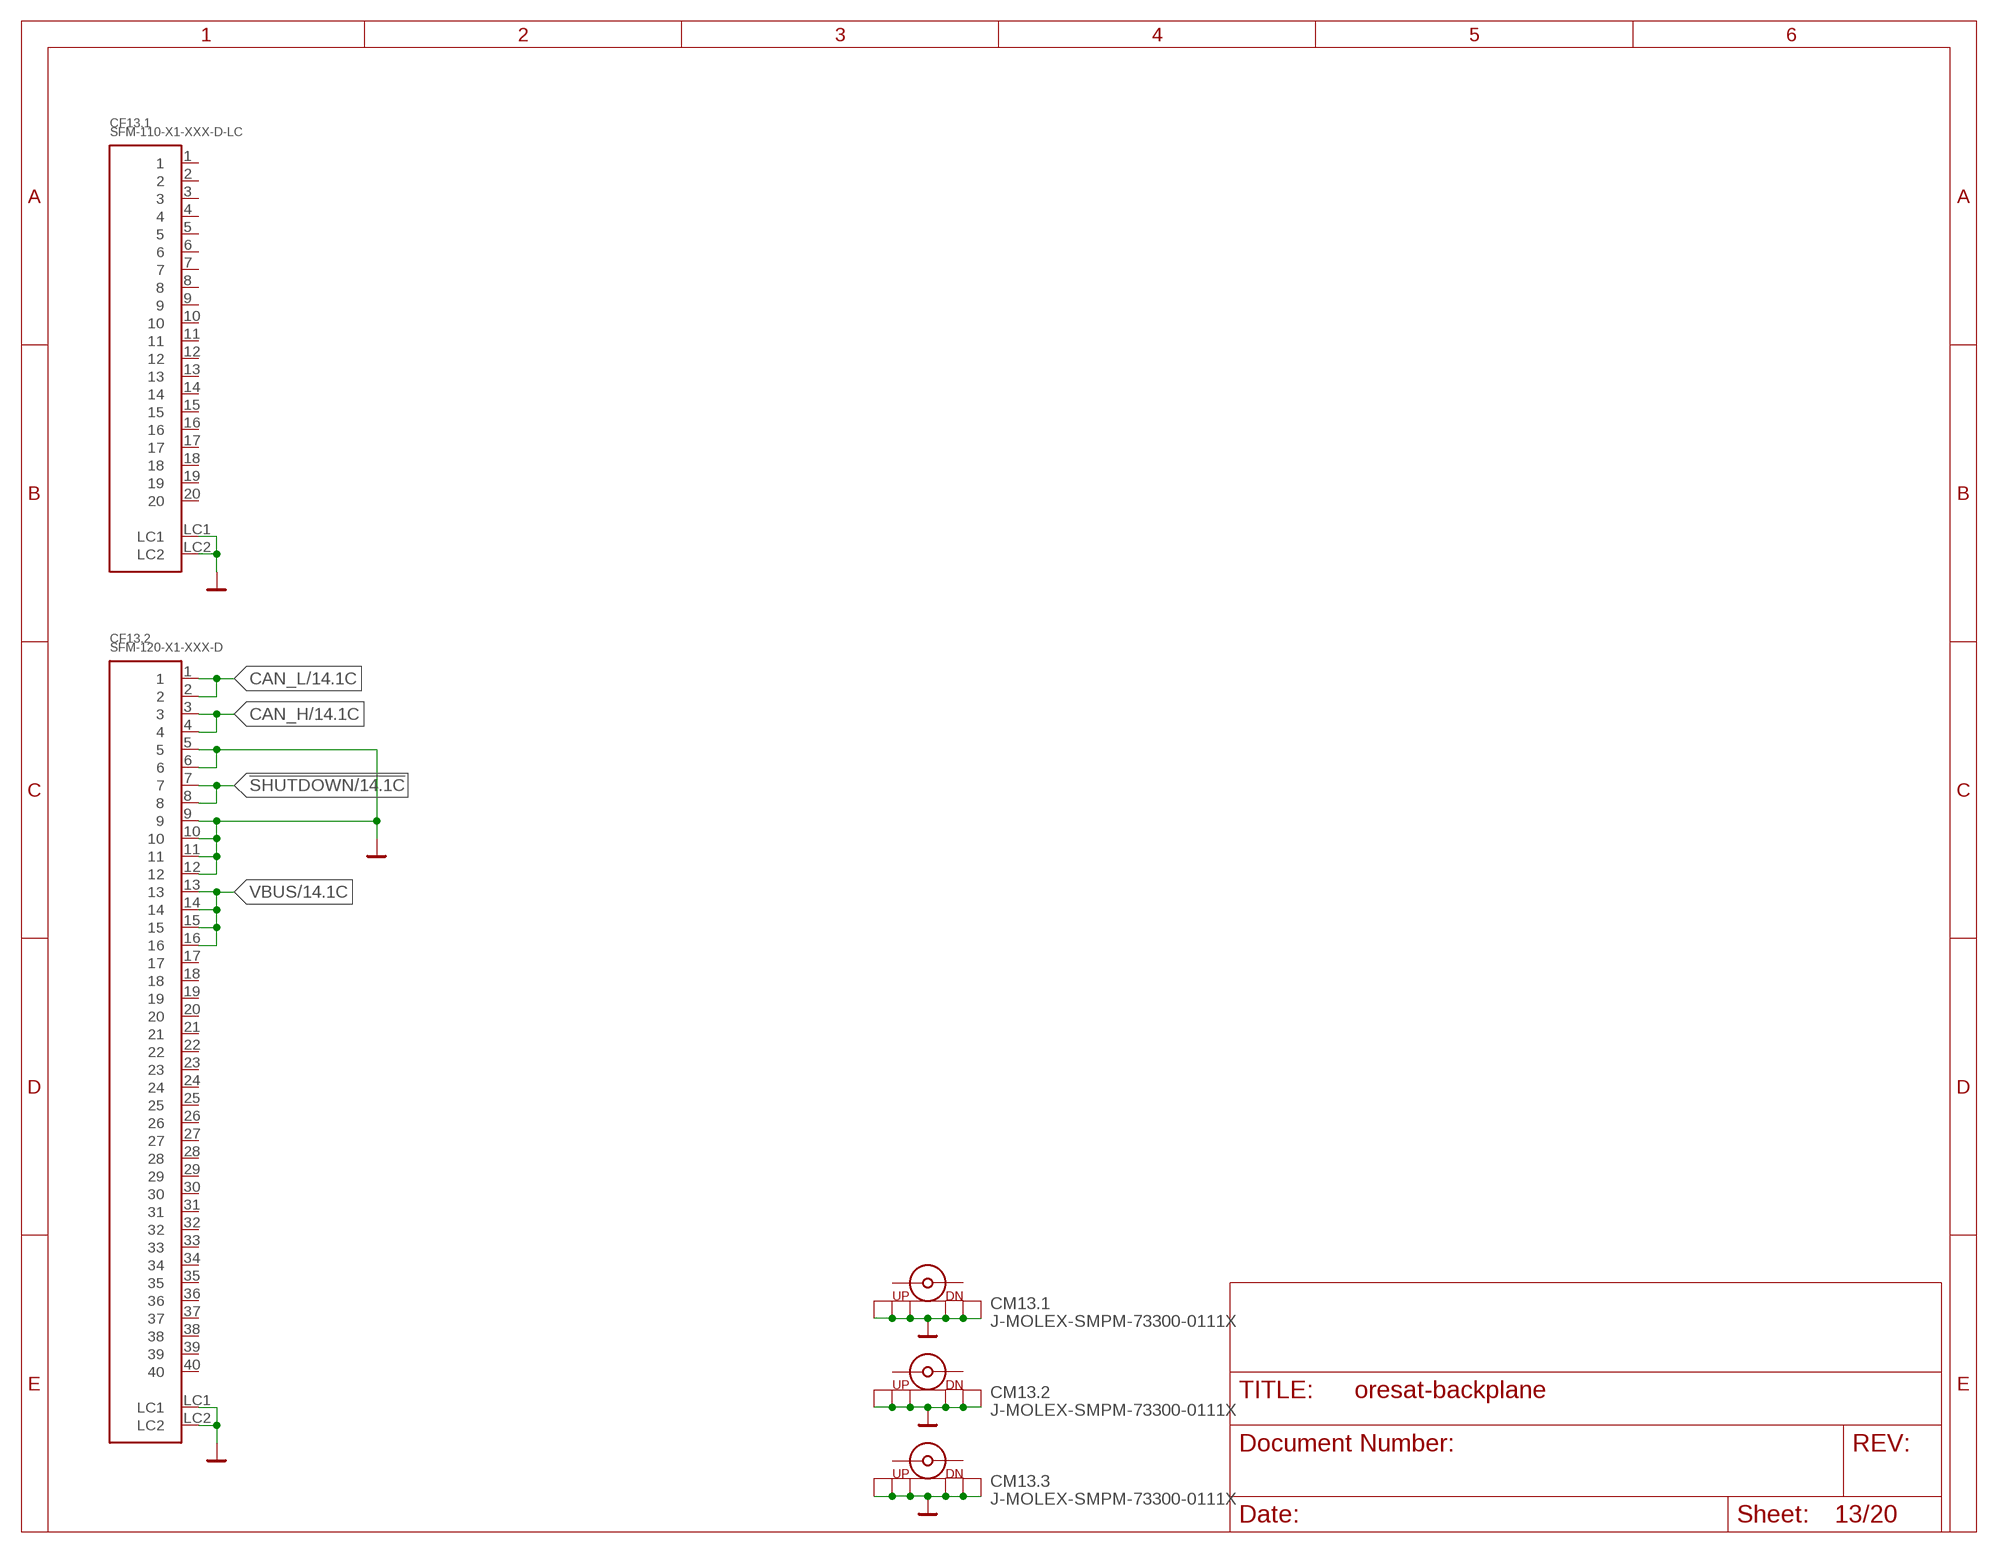
[diagram p12: schematic, sheet 13]
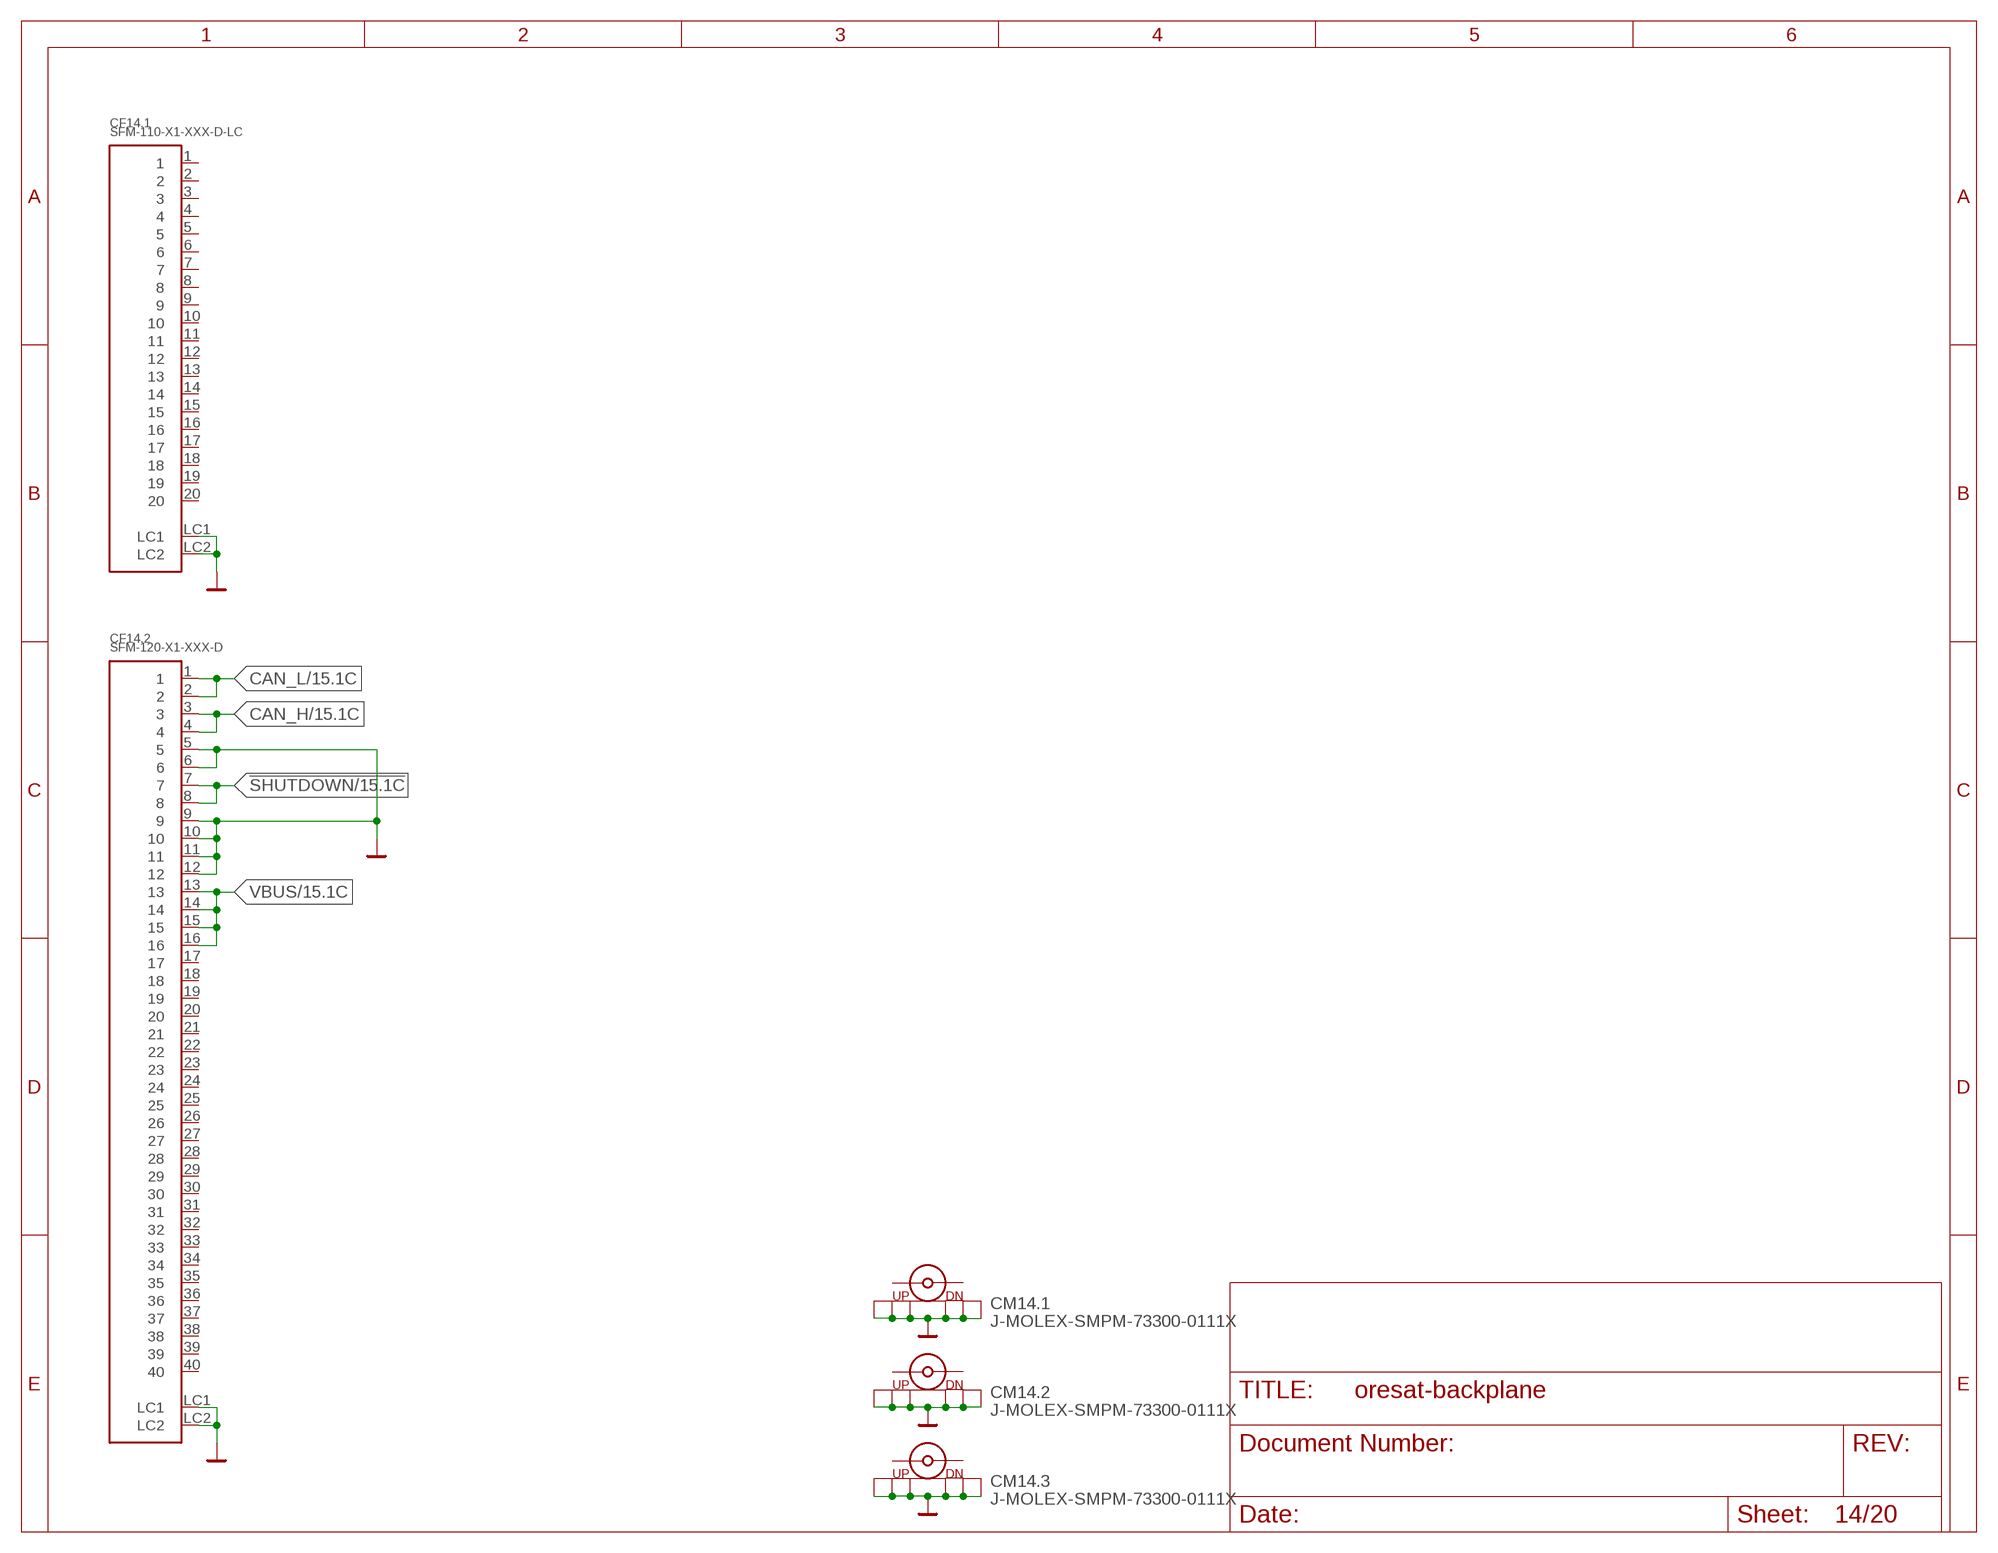
[diagram p13: schematic, sheet 14]
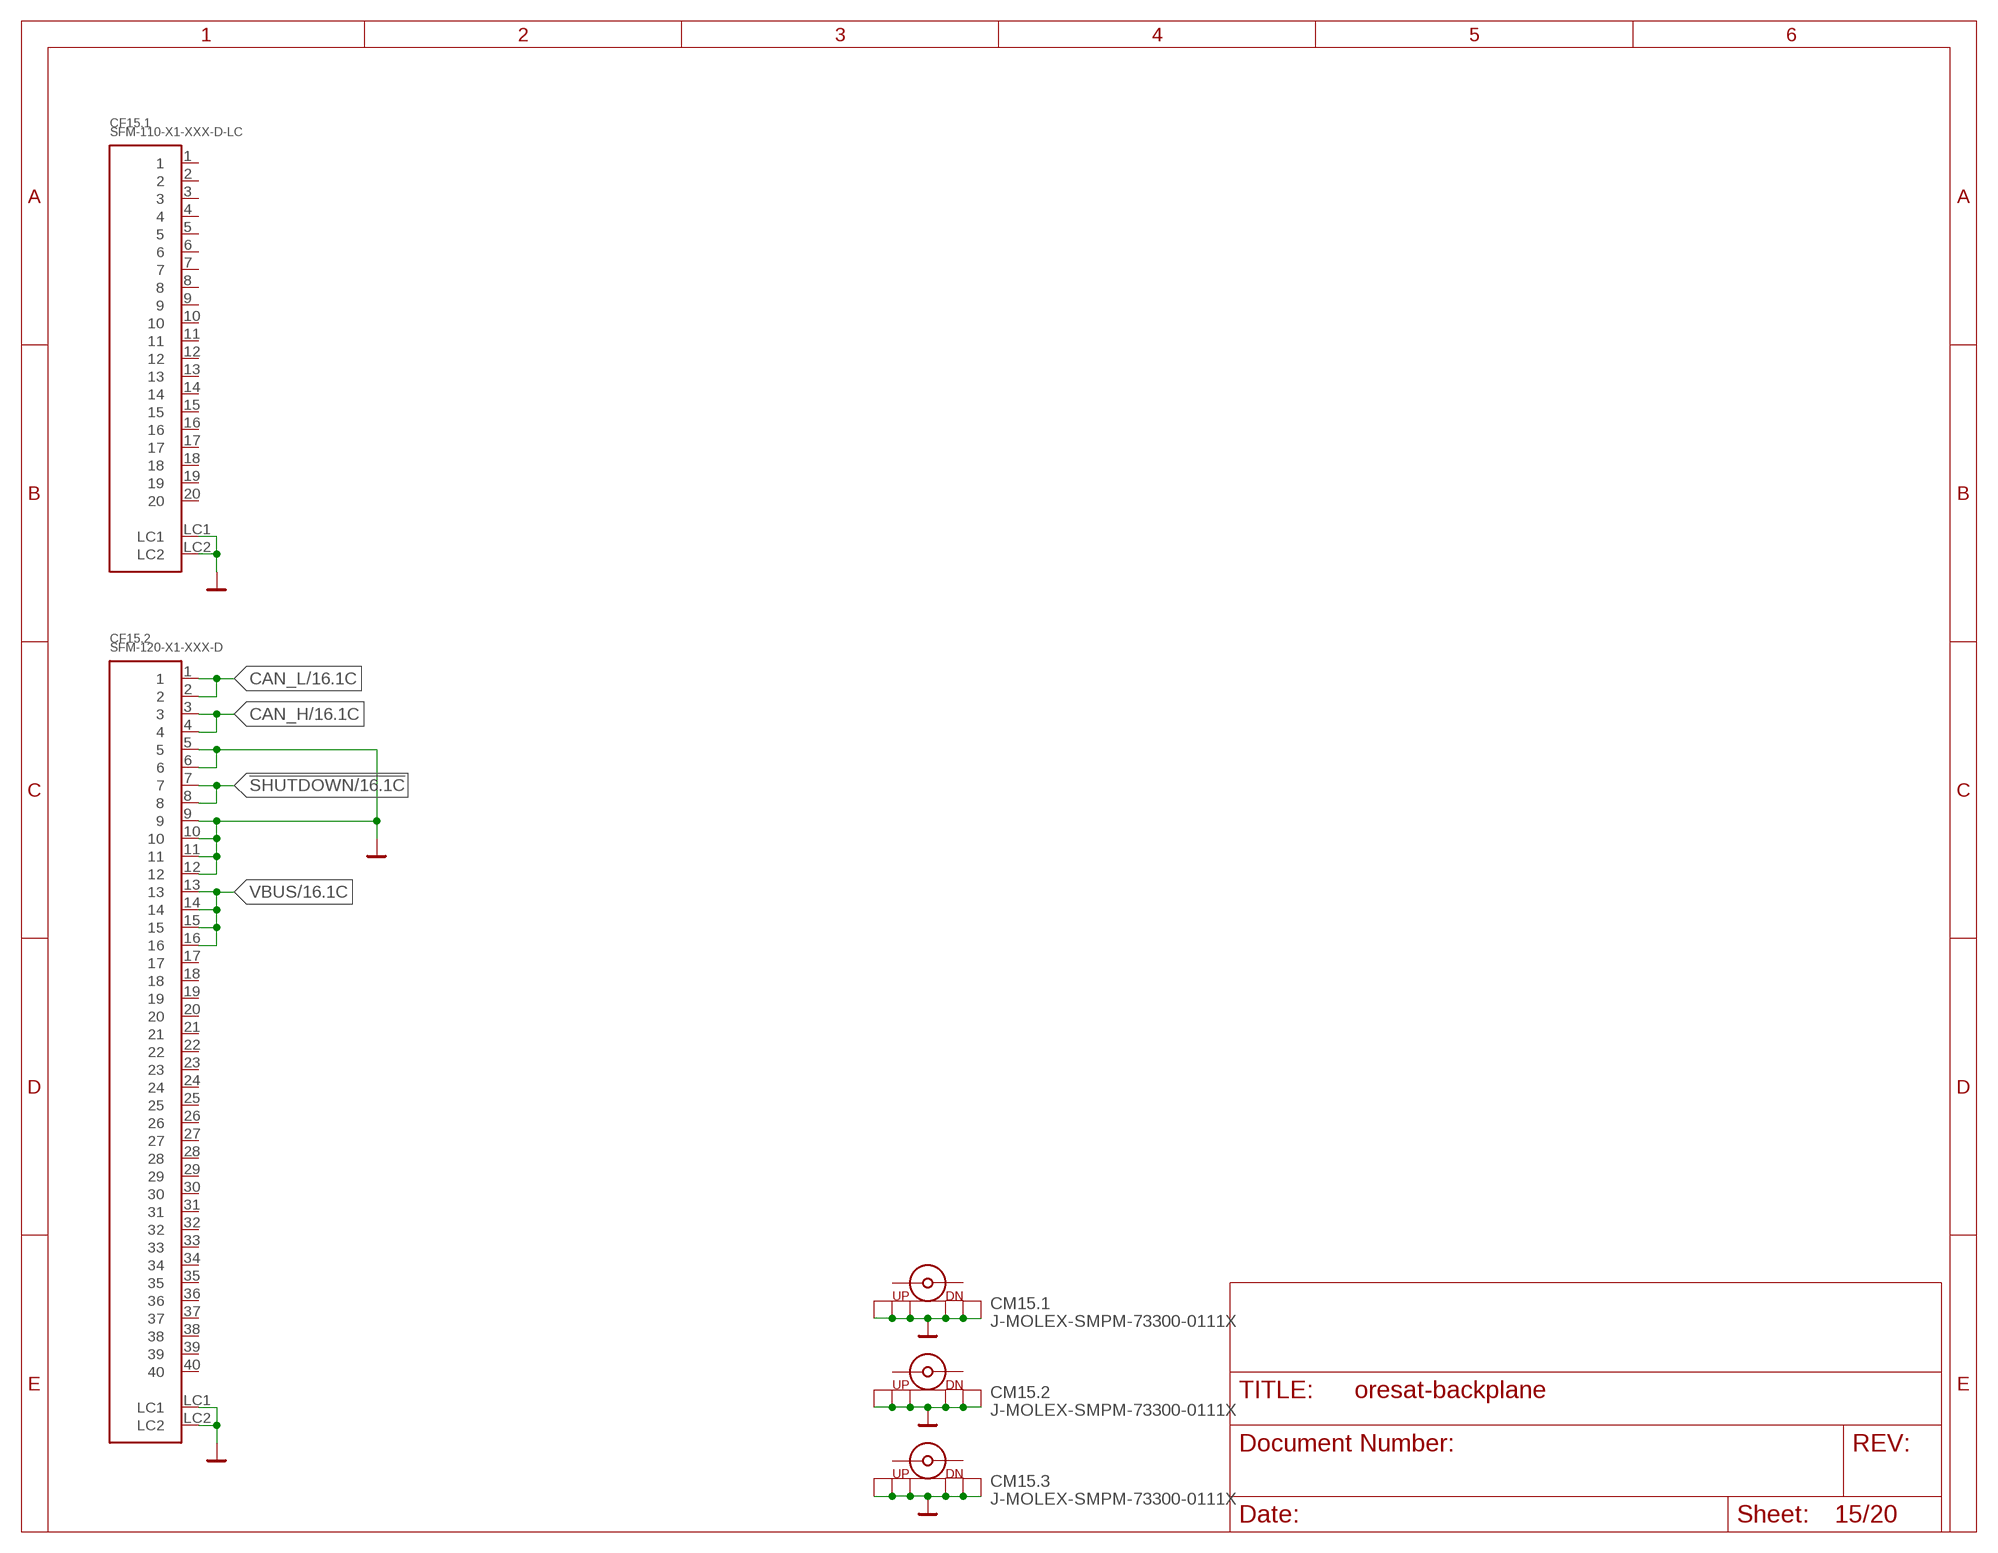
[diagram p14: schematic, sheet 15]
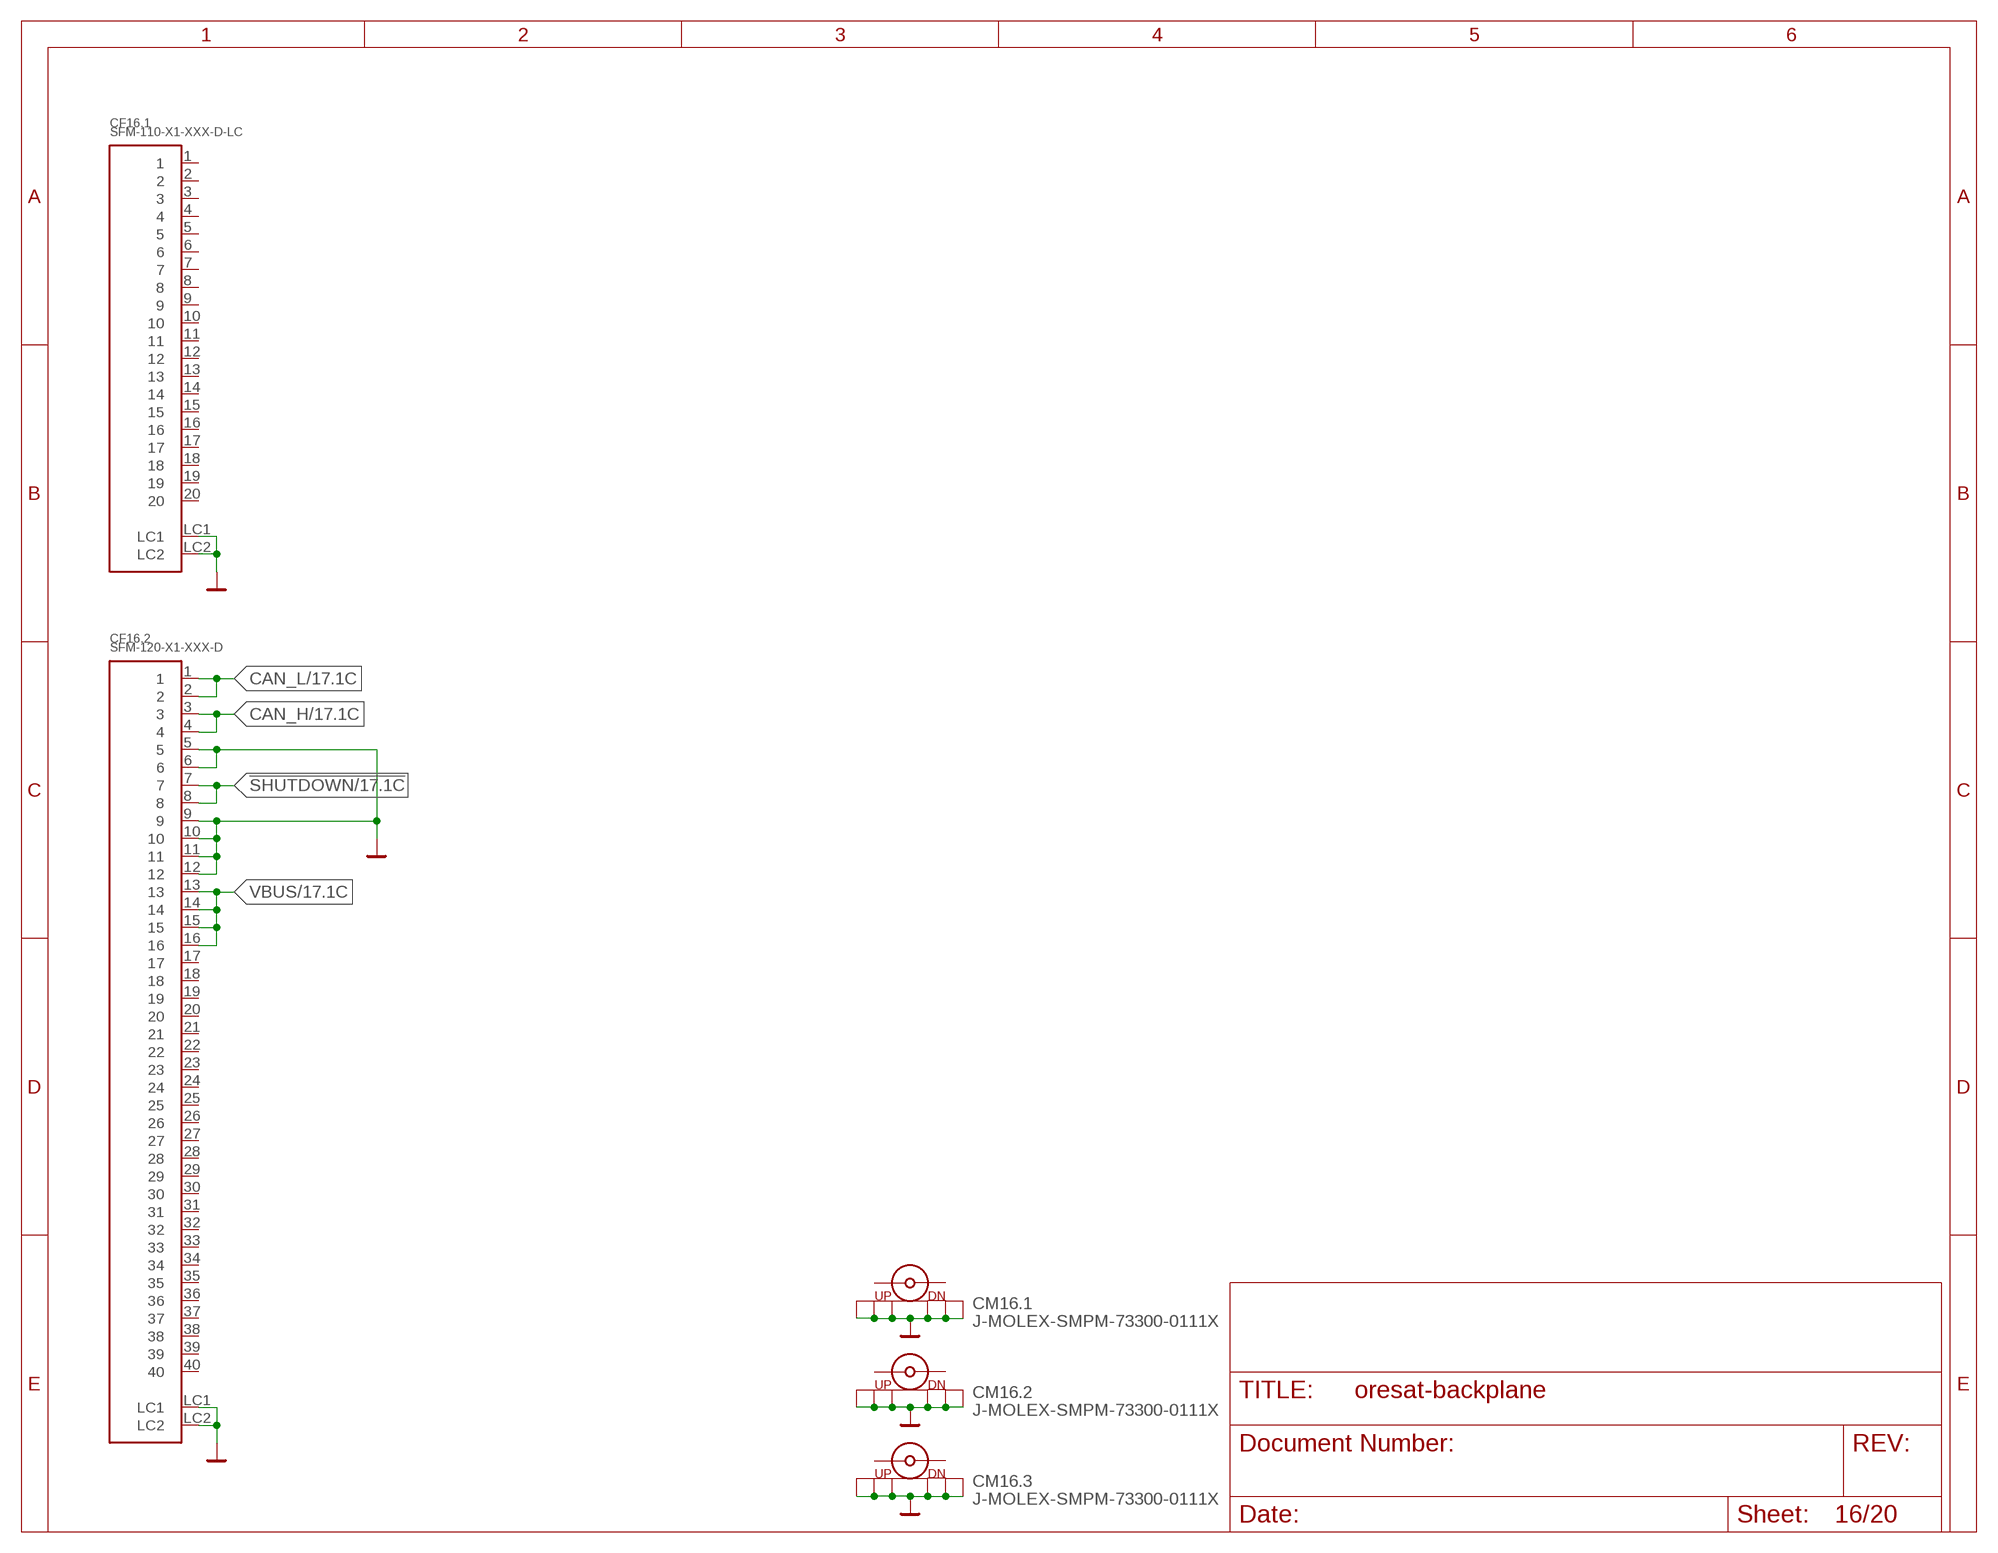
[diagram p15: schematic, sheet 16]
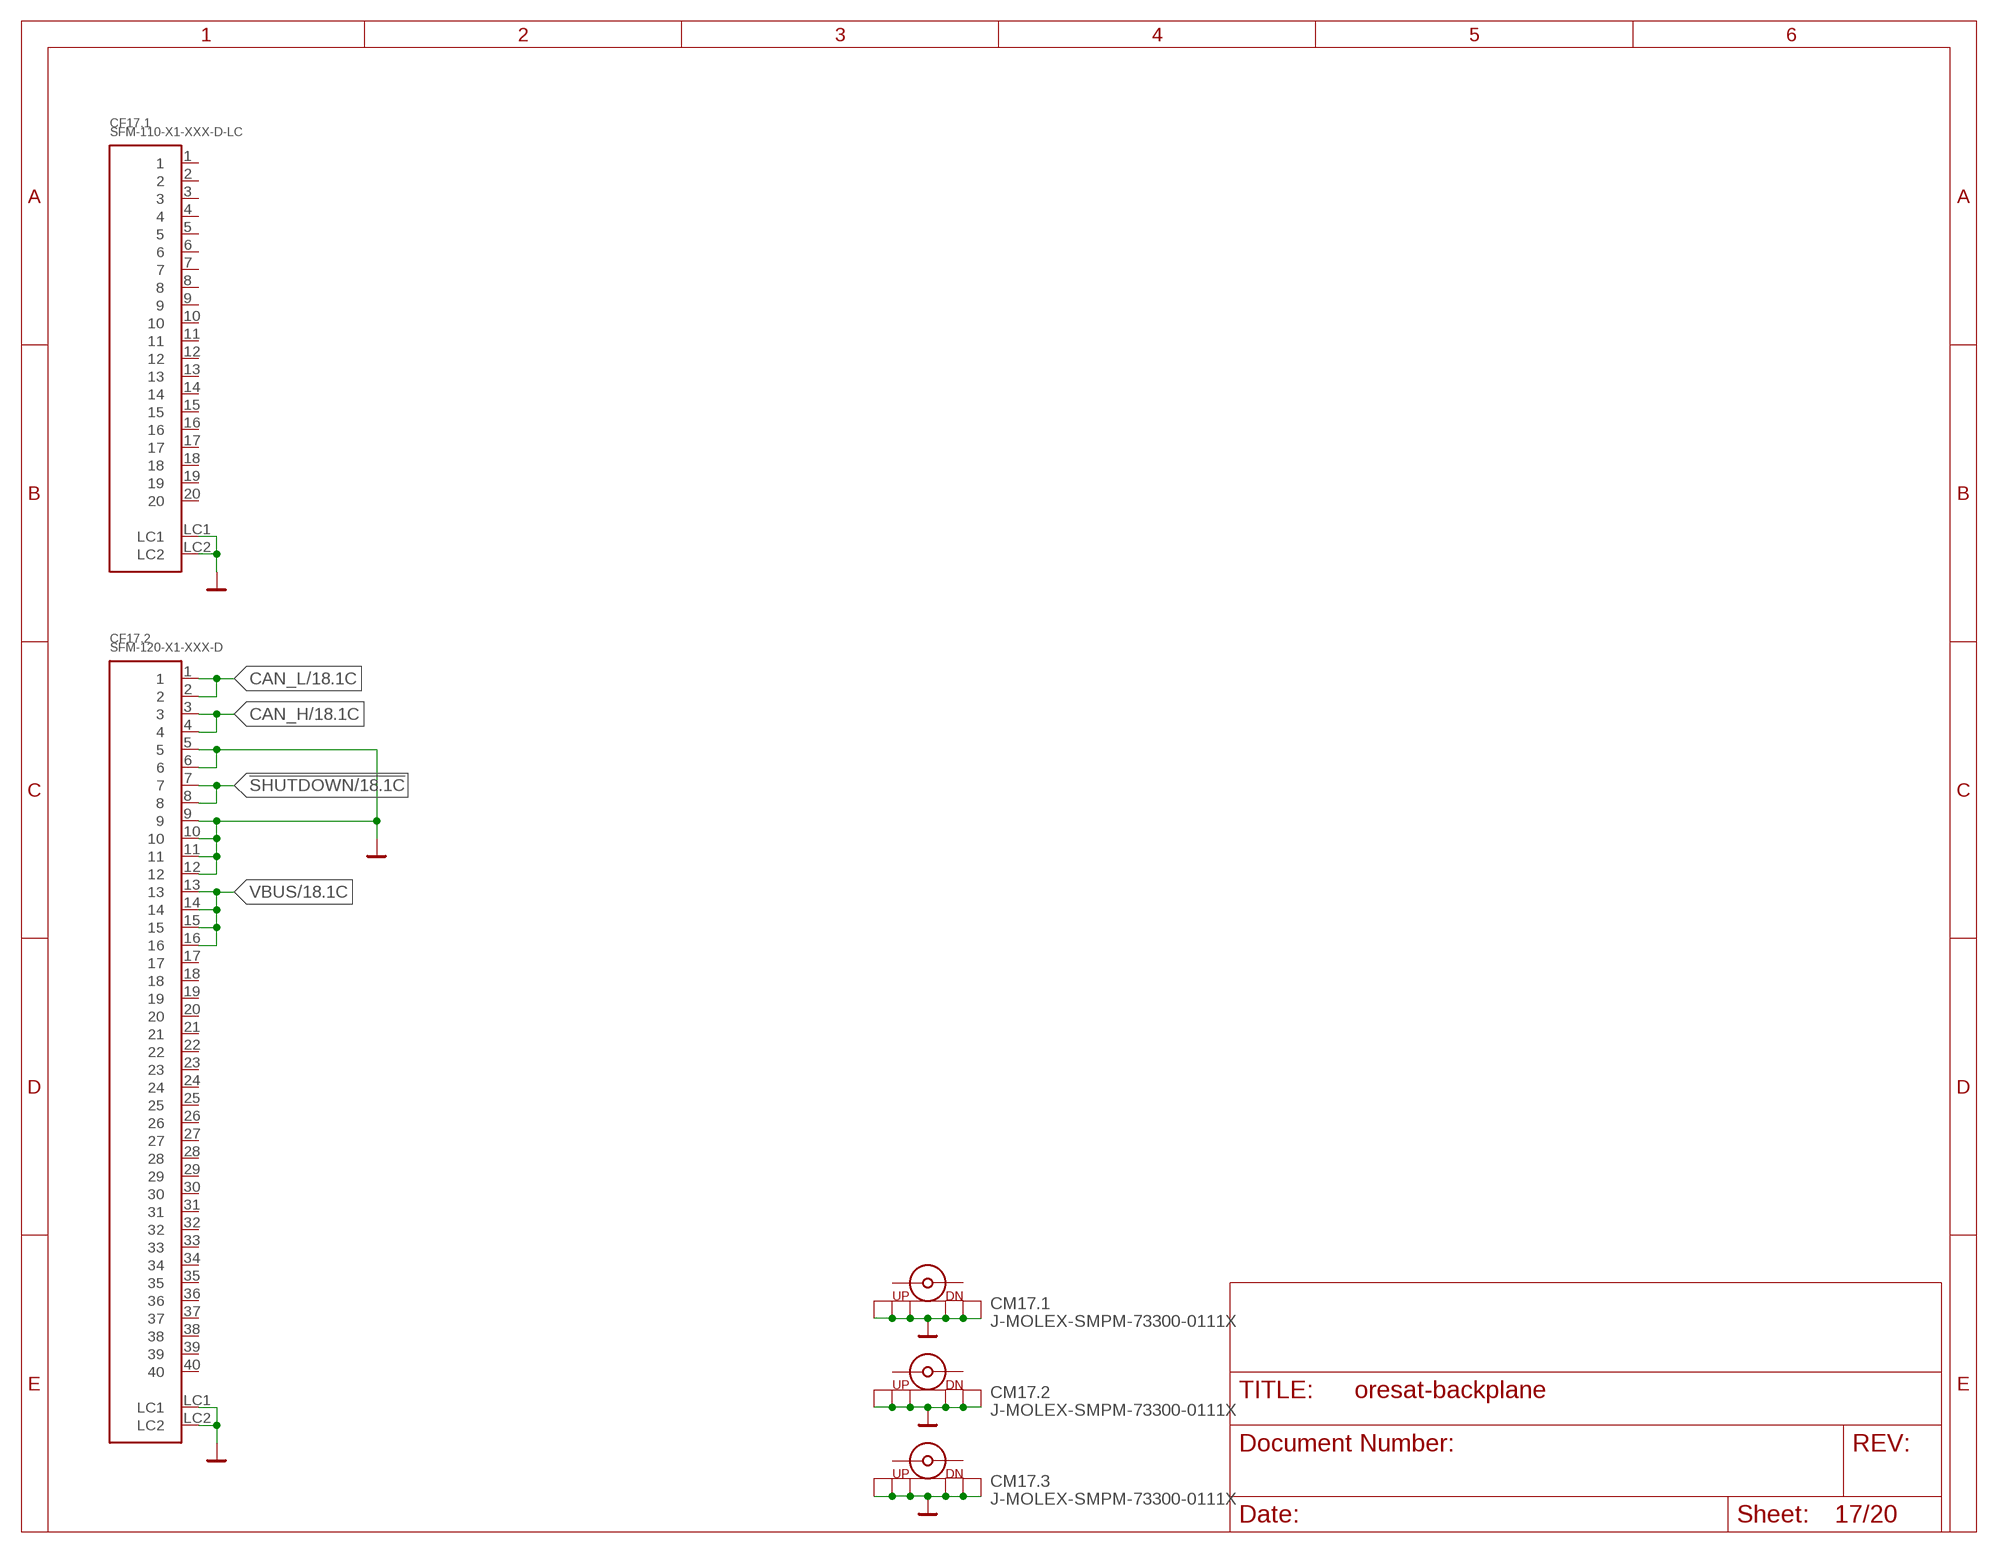
[diagram p16: schematic, sheet 17]
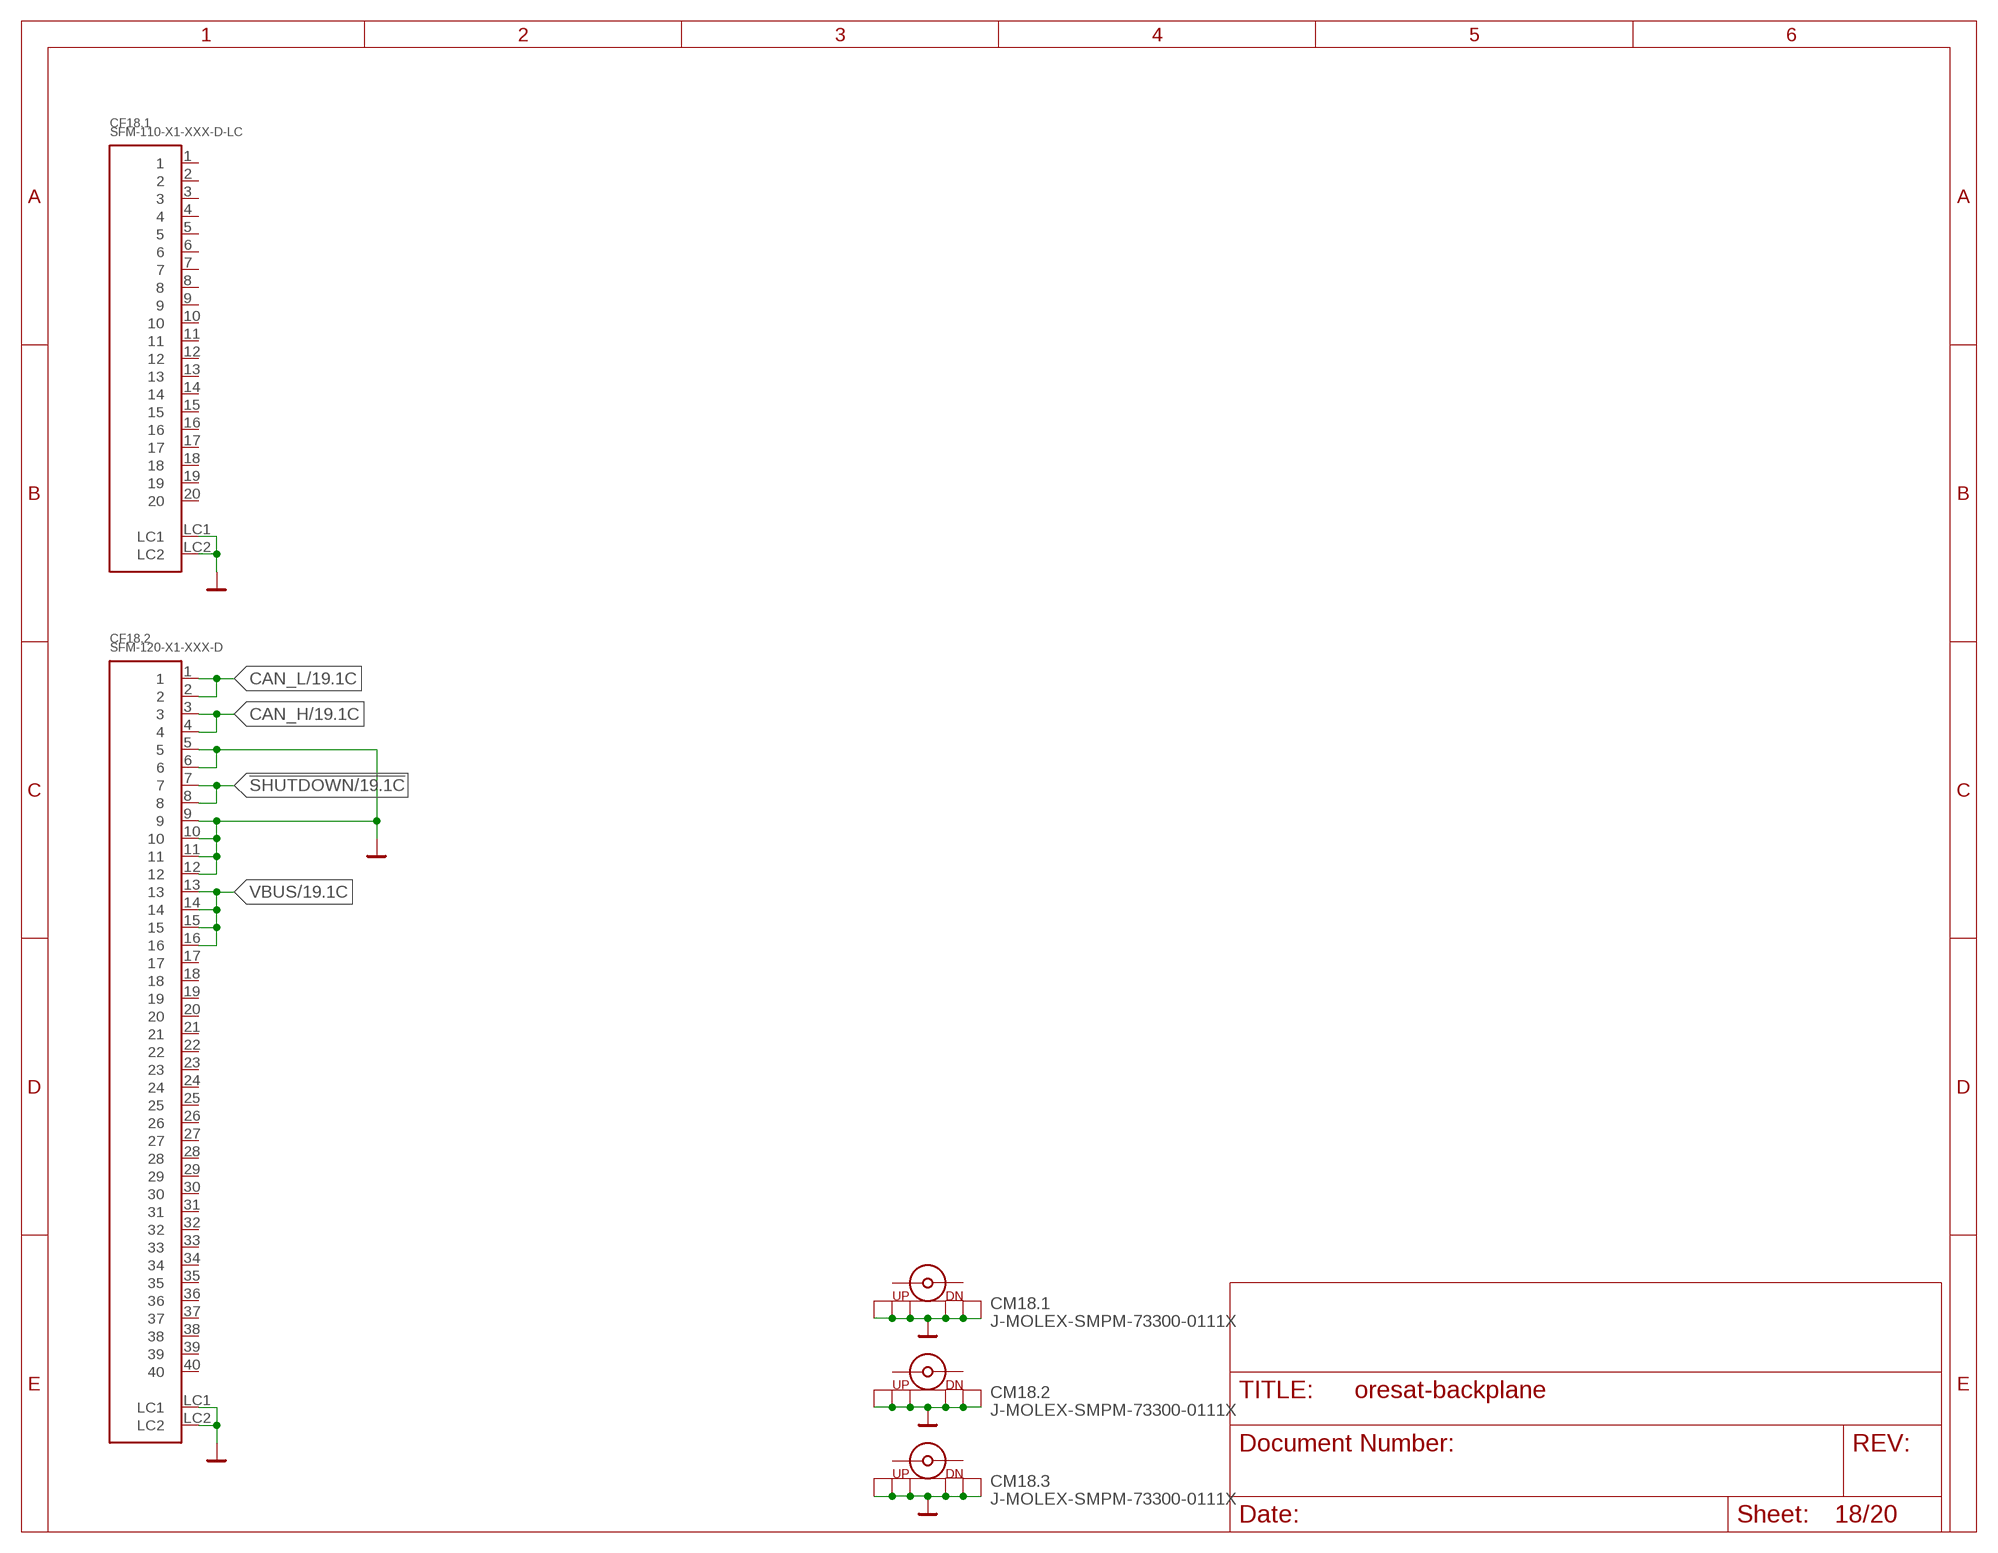
[diagram p17: schematic, sheet 18]
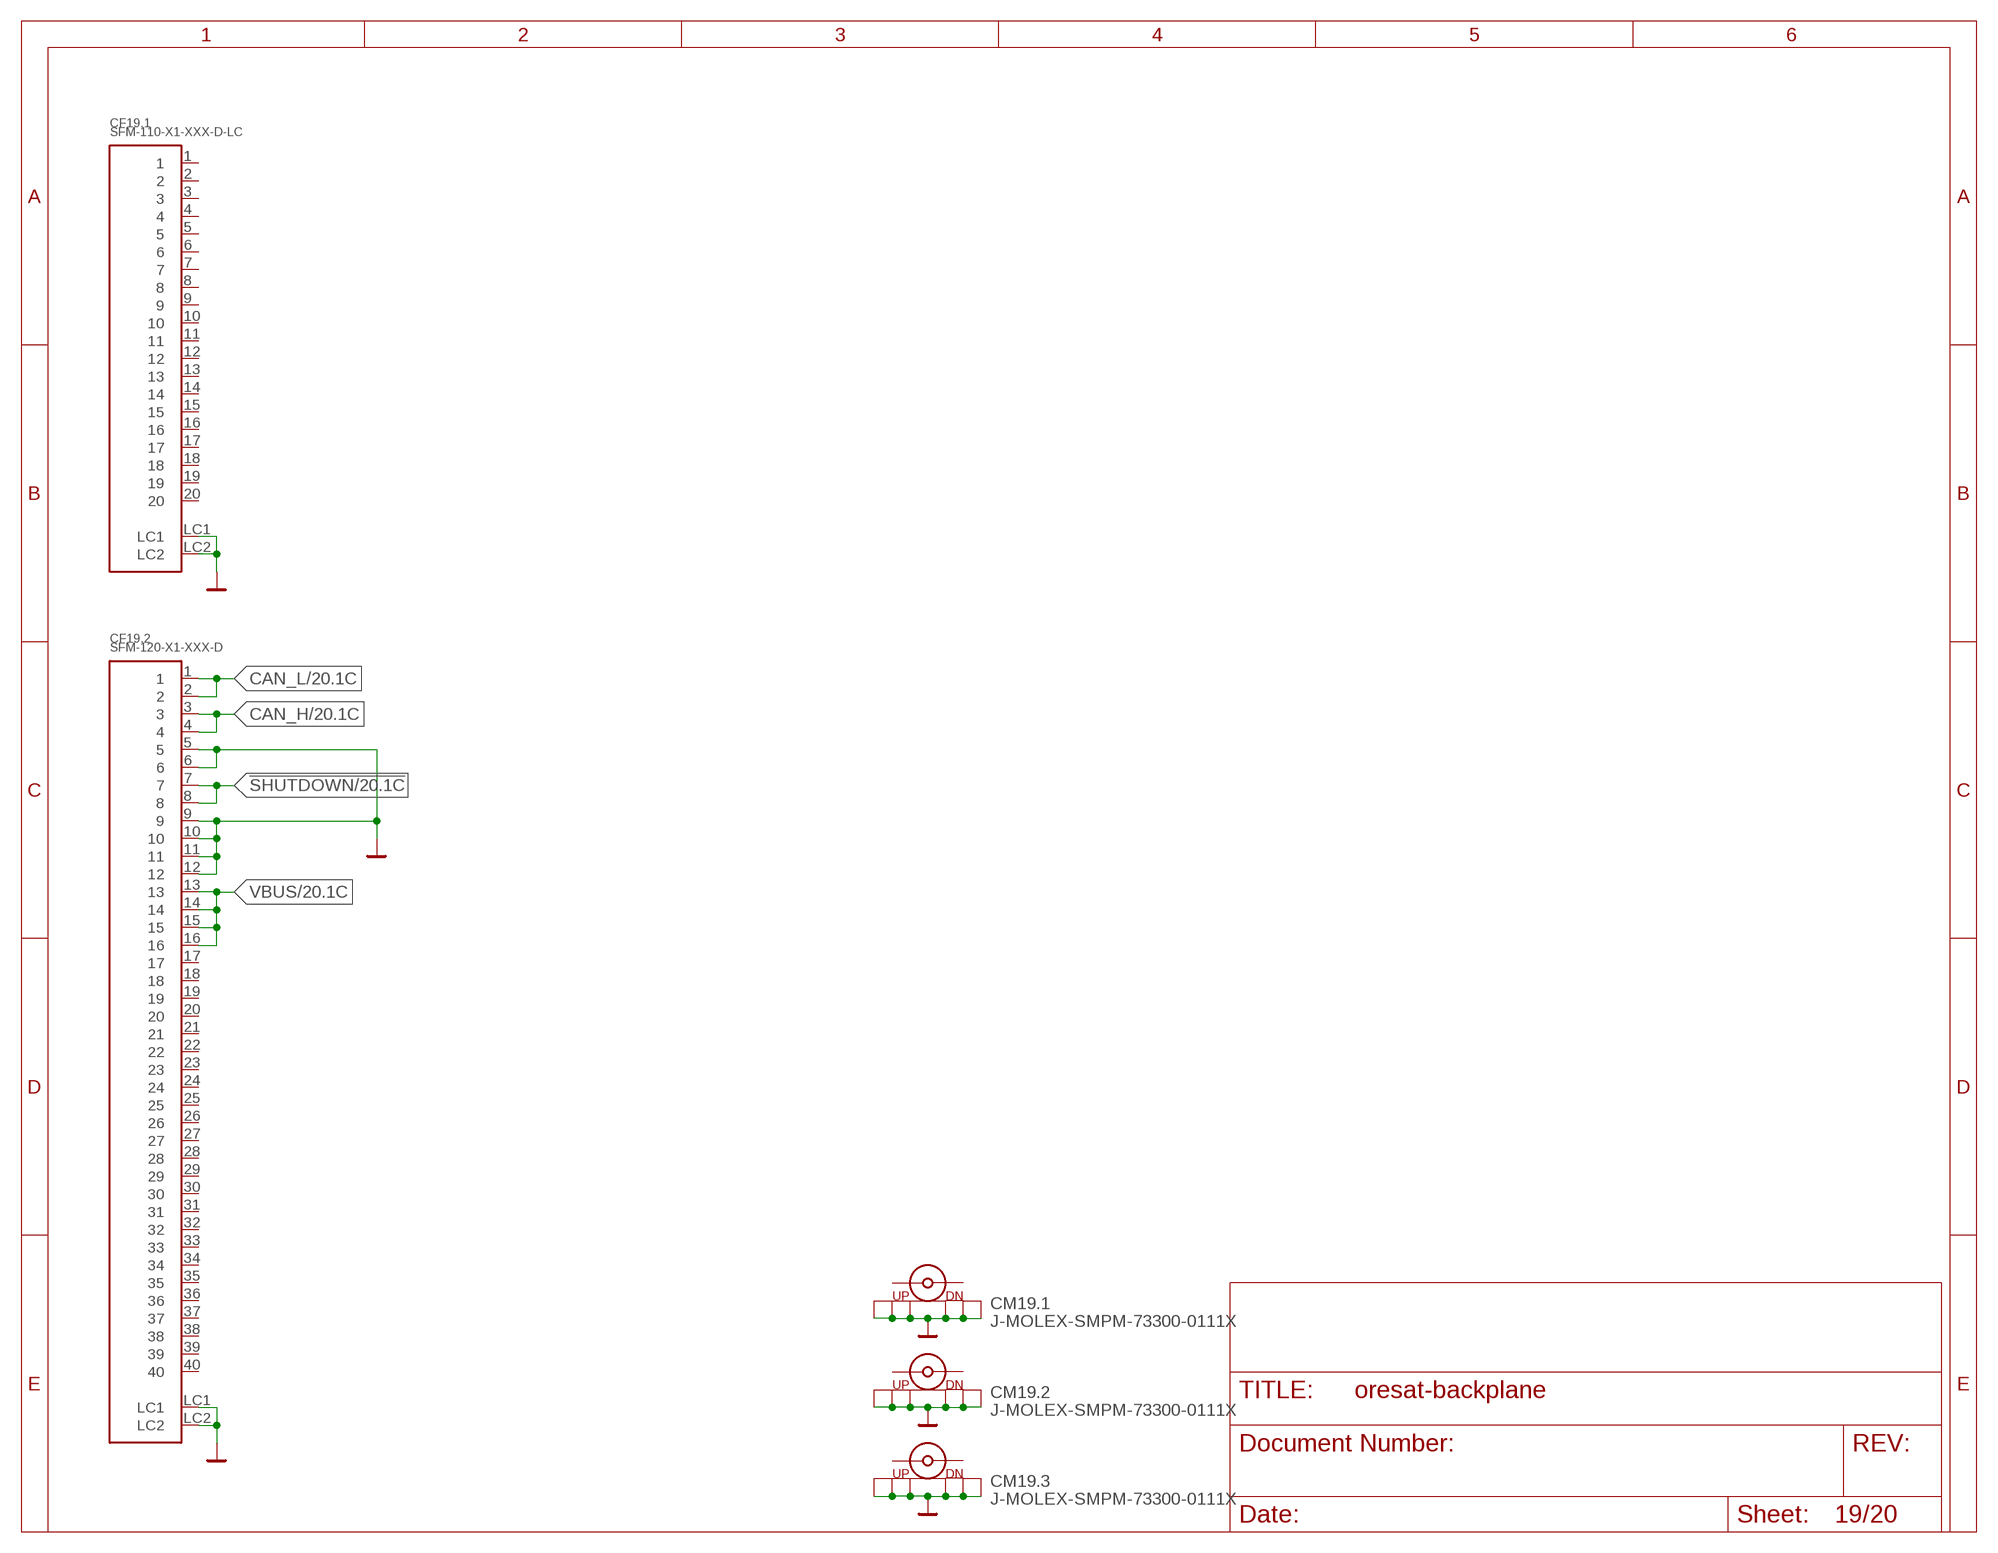
[diagram p18: schematic, sheet 19]
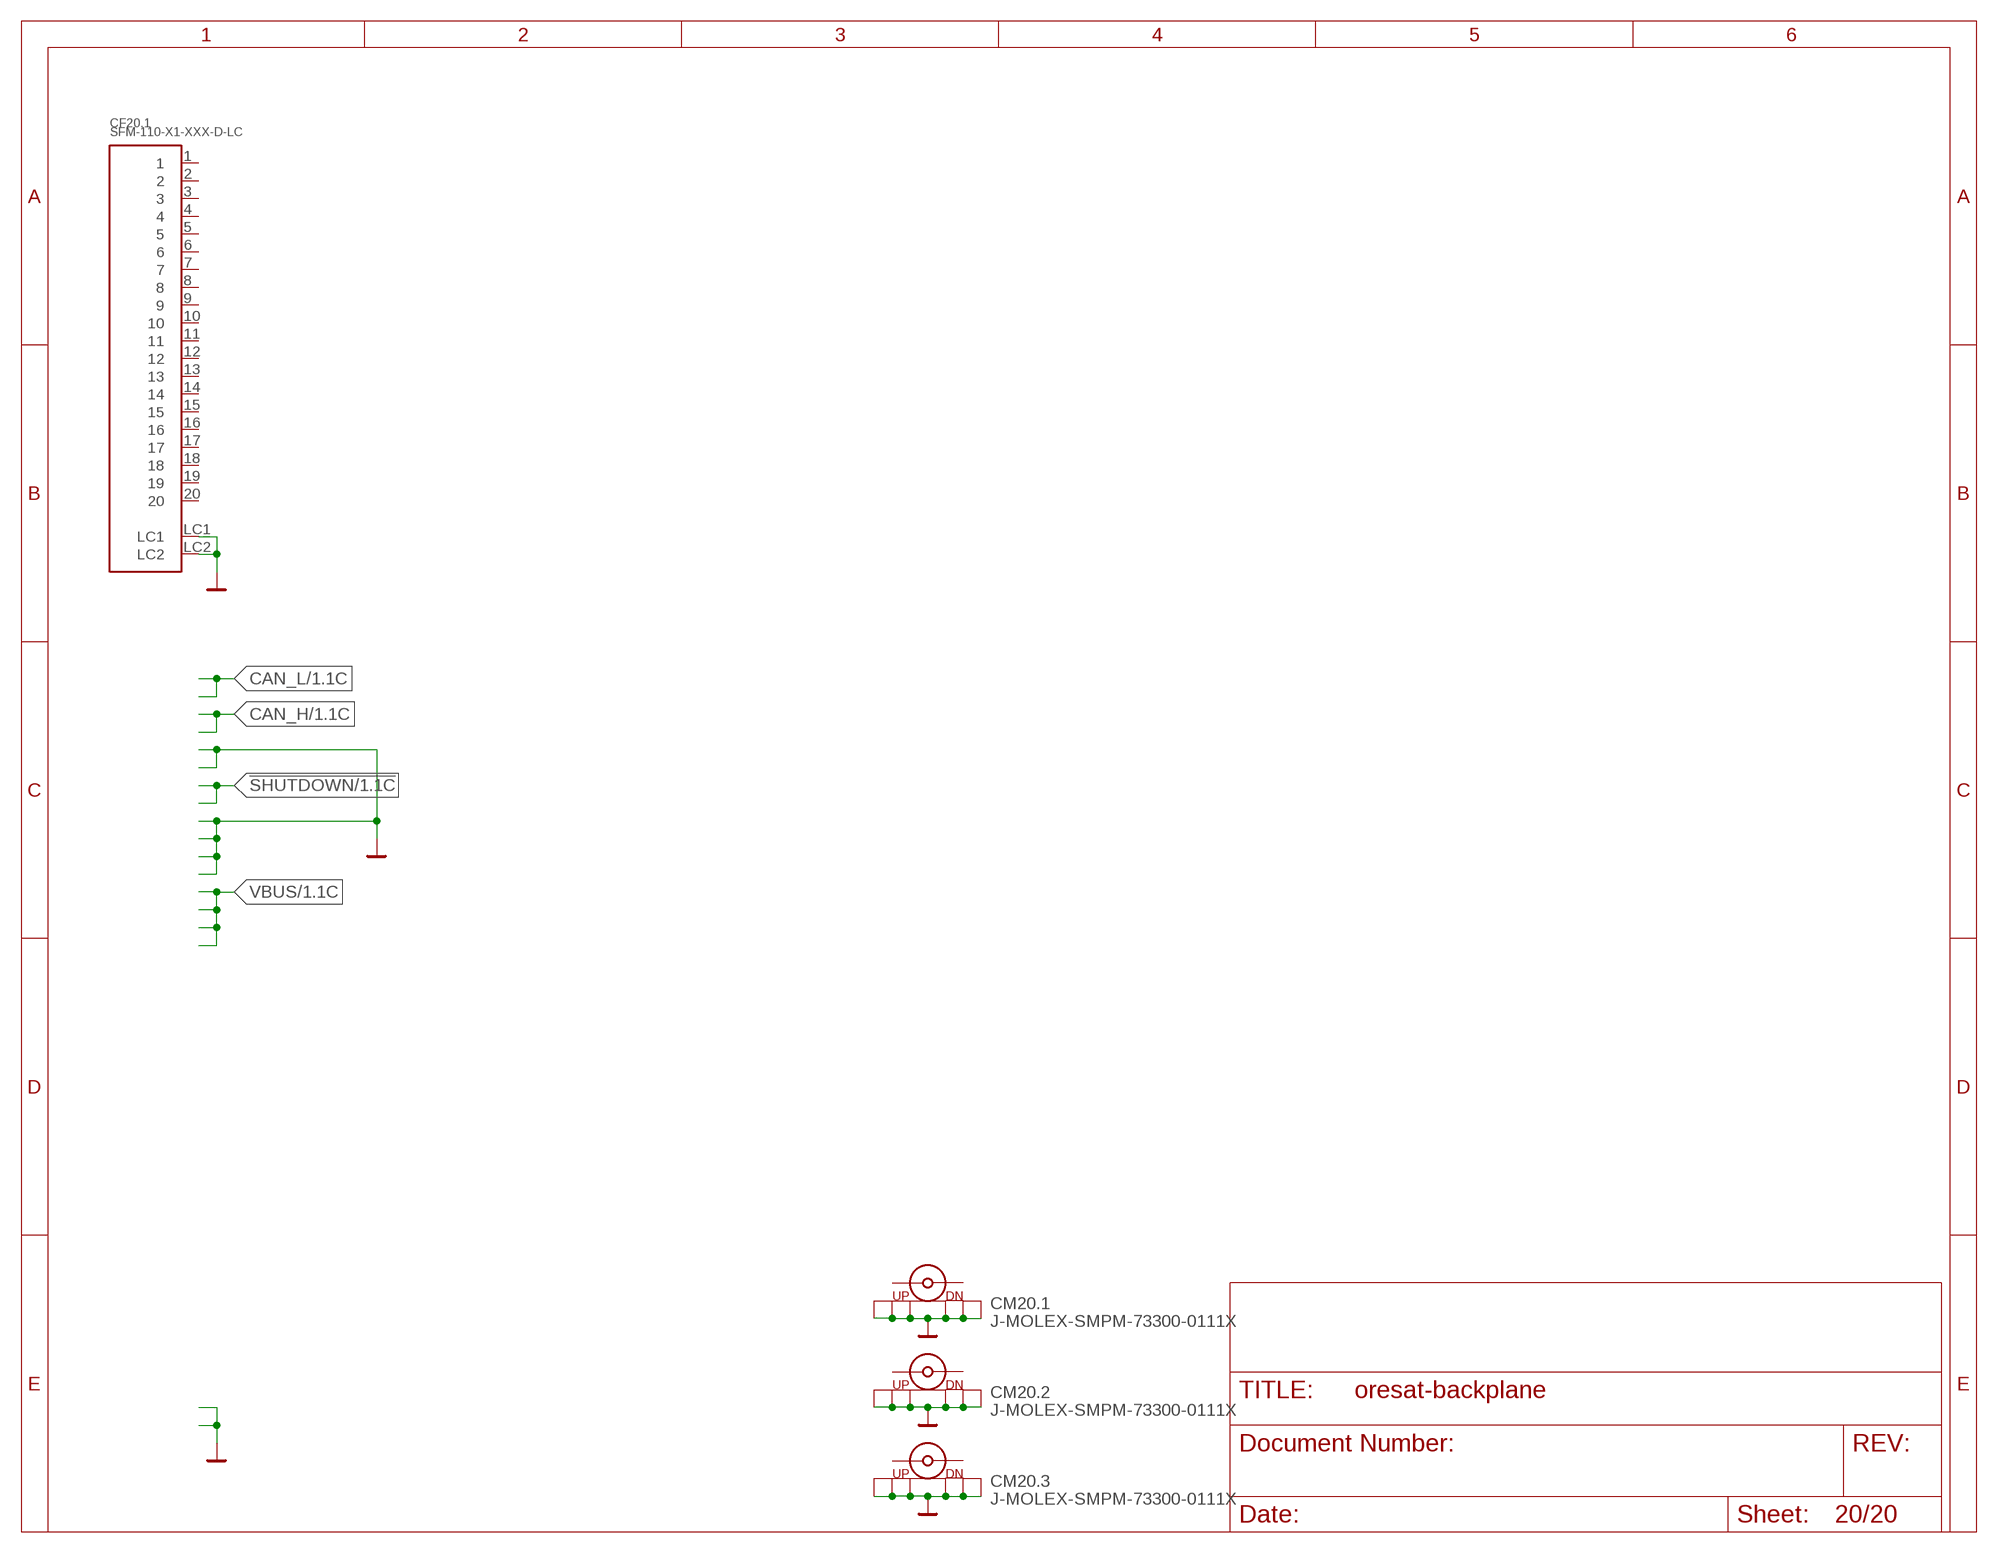
[diagram p19: schematic, sheet 20]

(export (version "E")
  (design (tool "Eeschema 10.0.6"))
  (components
    (comp (ref "CF14.1")
      (value "SFM-110-X1-XXX-D-LC")
      (footprint "eagle-import:SFM-110-X1-XXX-D-LC")
      (libsource (lib "eagle-import") (part "SFM-110-X1-XXX-D-LC"))
    )
    (comp (ref "CF14.2")
      (value "SFM-120-X1-XXX-D")
      (footprint "eagle-import:SFM-120-X1-XXX-D")
      (libsource (lib "eagle-import") (part "SFM-120-X1-XXX-D"))
    )
    (comp (ref "CM14.1")
      (value "J-MOLEX-SMPM-73300-0111X")
      (footprint "eagle-import:J-MOLEX-SMPM-73300-0111X")
      (libsource (lib "eagle-import") (part "J-MOLEX-SMPM-73300-0111X"))
    )
    (comp (ref "CM14.2")
      (value "J-MOLEX-SMPM-73300-0111X")
      (footprint "eagle-import:J-MOLEX-SMPM-73300-0111X")
      (libsource (lib "eagle-import") (part "J-MOLEX-SMPM-73300-0111X"))
    )
    (comp (ref "CM14.3")
      (value "J-MOLEX-SMPM-73300-0111X")
      (footprint "eagle-import:J-MOLEX-SMPM-73300-0111X")
      (libsource (lib "eagle-import") (part "J-MOLEX-SMPM-73300-0111X"))
    )
    (comp (ref "CF10.1")
      (value "SFM-110-X1-XXX-D-LC")
      (footprint "eagle-import:SFM-110-X1-XXX-D-LC")
      (libsource (lib "eagle-import") (part "SFM-110-X1-XXX-D-LC"))
    )
    (comp (ref "CF10.2")
      (value "SFM-120-X1-XXX-D")
      (footprint "eagle-import:SFM-120-X1-XXX-D")
      (libsource (lib "eagle-import") (part "SFM-120-X1-XXX-D"))
    )
    (comp (ref "CM10.1")
      (value "J-MOLEX-SMPM-73300-0111X")
      (footprint "eagle-import:J-MOLEX-SMPM-73300-0111X")
      (libsource (lib "eagle-import") (part "J-MOLEX-SMPM-73300-0111X"))
    )
    (comp (ref "CM10.2")
      (value "J-MOLEX-SMPM-73300-0111X")
      (footprint "eagle-import:J-MOLEX-SMPM-73300-0111X")
      (libsource (lib "eagle-import") (part "J-MOLEX-SMPM-73300-0111X"))
    )
    (comp (ref "CM10.3")
      (value "J-MOLEX-SMPM-73300-0111X")
      (footprint "eagle-import:J-MOLEX-SMPM-73300-0111X")
      (libsource (lib "eagle-import") (part "J-MOLEX-SMPM-73300-0111X"))
    )
    (comp (ref "CF16.1")
      (value "SFM-110-X1-XXX-D-LC")
      (footprint "eagle-import:SFM-110-X1-XXX-D-LC")
      (libsource (lib "eagle-import") (part "SFM-110-X1-XXX-D-LC"))
    )
    (comp (ref "CF16.2")
      (value "SFM-120-X1-XXX-D")
      (footprint "eagle-import:SFM-120-X1-XXX-D")
      (libsource (lib "eagle-import") (part "SFM-120-X1-XXX-D"))
    )
    (comp (ref "CM16.1")
      (value "J-MOLEX-SMPM-73300-0111X")
      (footprint "eagle-import:J-MOLEX-SMPM-73300-0111X")
      (libsource (lib "eagle-import") (part "J-MOLEX-SMPM-73300-0111X"))
    )
    (comp (ref "CM16.2")
      (value "J-MOLEX-SMPM-73300-0111X")
      (footprint "eagle-import:J-MOLEX-SMPM-73300-0111X")
      (libsource (lib "eagle-import") (part "J-MOLEX-SMPM-73300-0111X"))
    )
    (comp (ref "CM16.3")
      (value "J-MOLEX-SMPM-73300-0111X")
      (footprint "eagle-import:J-MOLEX-SMPM-73300-0111X")
      (libsource (lib "eagle-import") (part "J-MOLEX-SMPM-73300-0111X"))
    )
    (comp (ref "CF17.1")
      (value "SFM-110-X1-XXX-D-LC")
      (footprint "eagle-import:SFM-110-X1-XXX-D-LC")
      (libsource (lib "eagle-import") (part "SFM-110-X1-XXX-D-LC"))
    )
    (comp (ref "CF17.2")
      (value "SFM-120-X1-XXX-D")
      (footprint "eagle-import:SFM-120-X1-XXX-D")
      (libsource (lib "eagle-import") (part "SFM-120-X1-XXX-D"))
    )
    (comp (ref "CM17.1")
      (value "J-MOLEX-SMPM-73300-0111X")
      (footprint "eagle-import:J-MOLEX-SMPM-73300-0111X")
      (libsource (lib "eagle-import") (part "J-MOLEX-SMPM-73300-0111X"))
    )
    (comp (ref "CM17.2")
      (value "J-MOLEX-SMPM-73300-0111X")
      (footprint "eagle-import:J-MOLEX-SMPM-73300-0111X")
      (libsource (lib "eagle-import") (part "J-MOLEX-SMPM-73300-0111X"))
    )
    (comp (ref "CM17.3")
      (value "J-MOLEX-SMPM-73300-0111X")
      (footprint "eagle-import:J-MOLEX-SMPM-73300-0111X")
      (libsource (lib "eagle-import") (part "J-MOLEX-SMPM-73300-0111X"))
    )
    (comp (ref "CF15.1")
      (value "SFM-110-X1-XXX-D-LC")
      (footprint "eagle-import:SFM-110-X1-XXX-D-LC")
      (libsource (lib "eagle-import") (part "SFM-110-X1-XXX-D-LC"))
    )
    (comp (ref "CF15.2")
      (value "SFM-120-X1-XXX-D")
      (footprint "eagle-import:SFM-120-X1-XXX-D")
      (libsource (lib "eagle-import") (part "SFM-120-X1-XXX-D"))
    )
    (comp (ref "CM15.1")
      (value "J-MOLEX-SMPM-73300-0111X")
      (footprint "eagle-import:J-MOLEX-SMPM-73300-0111X")
      (libsource (lib "eagle-import") (part "J-MOLEX-SMPM-73300-0111X"))
    )
    (comp (ref "CM15.2")
      (value "J-MOLEX-SMPM-73300-0111X")
      (footprint "eagle-import:J-MOLEX-SMPM-73300-0111X")
      (libsource (lib "eagle-import") (part "J-MOLEX-SMPM-73300-0111X"))
    )
    (comp (ref "CM15.3")
      (value "J-MOLEX-SMPM-73300-0111X")
      (footprint "eagle-import:J-MOLEX-SMPM-73300-0111X")
      (libsource (lib "eagle-import") (part "J-MOLEX-SMPM-73300-0111X"))
    )
    (comp (ref "CF4.1")
      (value "SFM-110-X1-XXX-D-LC")
      (footprint "eagle-import:SFM-110-X1-XXX-D-LC")
      (libsource (lib "eagle-import") (part "SFM-110-X1-XXX-D-LC"))
    )
    (comp (ref "CF4.2")
      (value "SFM-120-X1-XXX-D")
      (footprint "eagle-import:SFM-120-X1-XXX-D")
      (libsource (lib "eagle-import") (part "SFM-120-X1-XXX-D"))
    )
    (comp (ref "CM4.1")
      (value "J-MOLEX-SMPM-73300-0111X")
      (footprint "eagle-import:J-MOLEX-SMPM-73300-0111X")
      (libsource (lib "eagle-import") (part "J-MOLEX-SMPM-73300-0111X"))
    )
    (comp (ref "CM4.2")
      (value "J-MOLEX-SMPM-73300-0111X")
      (footprint "eagle-import:J-MOLEX-SMPM-73300-0111X")
      (libsource (lib "eagle-import") (part "J-MOLEX-SMPM-73300-0111X"))
    )
    (comp (ref "CM4.3")
      (value "J-MOLEX-SMPM-73300-0111X")
      (footprint "eagle-import:J-MOLEX-SMPM-73300-0111X")
      (libsource (lib "eagle-import") (part "J-MOLEX-SMPM-73300-0111X"))
    )
    (comp (ref "CF6.1")
      (value "SFM-110-X1-XXX-D-LC")
      (footprint "eagle-import:SFM-110-X1-XXX-D-LC")
      (libsource (lib "eagle-import") (part "SFM-110-X1-XXX-D-LC"))
    )
    (comp (ref "CF6.2")
      (value "SFM-120-X1-XXX-D")
      (footprint "eagle-import:SFM-120-X1-XXX-D")
      (libsource (lib "eagle-import") (part "SFM-120-X1-XXX-D"))
    )
    (comp (ref "CM6.1")
      (value "J-MOLEX-SMPM-73300-0111X")
      (footprint "eagle-import:J-MOLEX-SMPM-73300-0111X")
      (libsource (lib "eagle-import") (part "J-MOLEX-SMPM-73300-0111X"))
    )
    (comp (ref "CM6.2")
      (value "J-MOLEX-SMPM-73300-0111X")
      (footprint "eagle-import:J-MOLEX-SMPM-73300-0111X")
      (libsource (lib "eagle-import") (part "J-MOLEX-SMPM-73300-0111X"))
    )
    (comp (ref "CM6.3")
      (value "J-MOLEX-SMPM-73300-0111X")
      (footprint "eagle-import:J-MOLEX-SMPM-73300-0111X")
      (libsource (lib "eagle-import") (part "J-MOLEX-SMPM-73300-0111X"))
    )
    (comp (ref "CF12.1")
      (value "SFM-110-X1-XXX-D-LC")
      (footprint "eagle-import:SFM-110-X1-XXX-D-LC")
      (libsource (lib "eagle-import") (part "SFM-110-X1-XXX-D-LC"))
    )
    (comp (ref "CF12.2")
      (value "SFM-120-X1-XXX-D")
      (footprint "eagle-import:SFM-120-X1-XXX-D")
      (libsource (lib "eagle-import") (part "SFM-120-X1-XXX-D"))
    )
    (comp (ref "CM12.1")
      (value "J-MOLEX-SMPM-73300-0111X")
      (footprint "eagle-import:J-MOLEX-SMPM-73300-0111X")
      (libsource (lib "eagle-import") (part "J-MOLEX-SMPM-73300-0111X"))
    )
    (comp (ref "CM12.2")
      (value "J-MOLEX-SMPM-73300-0111X")
      (footprint "eagle-import:J-MOLEX-SMPM-73300-0111X")
      (libsource (lib "eagle-import") (part "J-MOLEX-SMPM-73300-0111X"))
    )
    (comp (ref "CM12.3")
      (value "J-MOLEX-SMPM-73300-0111X")
      (footprint "eagle-import:J-MOLEX-SMPM-73300-0111X")
      (libsource (lib "eagle-import") (part "J-MOLEX-SMPM-73300-0111X"))
    )
    (comp (ref "CF2.1")
      (value "SFM-110-X1-XXX-D-LC")
      (footprint "eagle-import:SFM-110-X1-XXX-D-LC")
      (libsource (lib "eagle-import") (part "SFM-110-X1-XXX-D-LC"))
    )
    (comp (ref "CF2.2")
      (value "SFM-120-X1-XXX-D")
      (footprint "eagle-import:SFM-120-X1-XXX-D")
      (libsource (lib "eagle-import") (part "SFM-120-X1-XXX-D"))
    )
    (comp (ref "CM2.1")
      (value "J-MOLEX-SMPM-73300-0111X")
      (footprint "eagle-import:J-MOLEX-SMPM-73300-0111X")
      (libsource (lib "eagle-import") (part "J-MOLEX-SMPM-73300-0111X"))
    )
    (comp (ref "CM2.2")
      (value "J-MOLEX-SMPM-73300-0111X")
      (footprint "eagle-import:J-MOLEX-SMPM-73300-0111X")
      (libsource (lib "eagle-import") (part "J-MOLEX-SMPM-73300-0111X"))
    )
    (comp (ref "CM2.3")
      (value "J-MOLEX-SMPM-73300-0111X")
      (footprint "eagle-import:J-MOLEX-SMPM-73300-0111X")
      (libsource (lib "eagle-import") (part "J-MOLEX-SMPM-73300-0111X"))
    )
    (comp (ref "CF20.1")
      (value "SFM-110-X1-XXX-D-LC")
      (footprint "eagle-import:SFM-110-X1-XXX-D-LC")
      (libsource (lib "eagle-import") (part "SFM-110-X1-XXX-D-LC"))
    )
    (comp (ref "CM20.1")
      (value "J-MOLEX-SMPM-73300-0111X")
      (footprint "eagle-import:J-MOLEX-SMPM-73300-0111X")
      (libsource (lib "eagle-import") (part "J-MOLEX-SMPM-73300-0111X"))
    )
    (comp (ref "CM20.2")
      (value "J-MOLEX-SMPM-73300-0111X")
      (footprint "eagle-import:J-MOLEX-SMPM-73300-0111X")
      (libsource (lib "eagle-import") (part "J-MOLEX-SMPM-73300-0111X"))
    )
    (comp (ref "CM20.3")
      (value "J-MOLEX-SMPM-73300-0111X")
      (footprint "eagle-import:J-MOLEX-SMPM-73300-0111X")
      (libsource (lib "eagle-import") (part "J-MOLEX-SMPM-73300-0111X"))
    )
    (comp (ref "CF13.1")
      (value "SFM-110-X1-XXX-D-LC")
      (footprint "eagle-import:SFM-110-X1-XXX-D-LC")
      (libsource (lib "eagle-import") (part "SFM-110-X1-XXX-D-LC"))
    )
    (comp (ref "CF13.2")
      (value "SFM-120-X1-XXX-D")
      (footprint "eagle-import:SFM-120-X1-XXX-D")
      (libsource (lib "eagle-import") (part "SFM-120-X1-XXX-D"))
    )
    (comp (ref "CM13.1")
      (value "J-MOLEX-SMPM-73300-0111X")
      (footprint "eagle-import:J-MOLEX-SMPM-73300-0111X")
      (libsource (lib "eagle-import") (part "J-MOLEX-SMPM-73300-0111X"))
    )
    (comp (ref "CM13.2")
      (value "J-MOLEX-SMPM-73300-0111X")
      (footprint "eagle-import:J-MOLEX-SMPM-73300-0111X")
      (libsource (lib "eagle-import") (part "J-MOLEX-SMPM-73300-0111X"))
    )
    (comp (ref "CM13.3")
      (value "J-MOLEX-SMPM-73300-0111X")
      (footprint "eagle-import:J-MOLEX-SMPM-73300-0111X")
      (libsource (lib "eagle-import") (part "J-MOLEX-SMPM-73300-0111X"))
    )
    (comp (ref "CF11.1")
      (value "SFM-110-X1-XXX-D-LC")
      (footprint "eagle-import:SFM-110-X1-XXX-D-LC")
      (libsource (lib "eagle-import") (part "SFM-110-X1-XXX-D-LC"))
    )
    (comp (ref "CF11.2")
      (value "SFM-120-X1-XXX-D")
      (footprint "eagle-import:SFM-120-X1-XXX-D")
      (libsource (lib "eagle-import") (part "SFM-120-X1-XXX-D"))
    )
    (comp (ref "CM11.1")
      (value "J-MOLEX-SMPM-73300-0111X")
      (footprint "eagle-import:J-MOLEX-SMPM-73300-0111X")
      (libsource (lib "eagle-import") (part "J-MOLEX-SMPM-73300-0111X"))
    )
    (comp (ref "CM11.2")
      (value "J-MOLEX-SMPM-73300-0111X")
      (footprint "eagle-import:J-MOLEX-SMPM-73300-0111X")
      (libsource (lib "eagle-import") (part "J-MOLEX-SMPM-73300-0111X"))
    )
    (comp (ref "CM11.3")
      (value "J-MOLEX-SMPM-73300-0111X")
      (footprint "eagle-import:J-MOLEX-SMPM-73300-0111X")
      (libsource (lib "eagle-import") (part "J-MOLEX-SMPM-73300-0111X"))
    )
    (comp (ref "CF19.1")
      (value "SFM-110-X1-XXX-D-LC")
      (footprint "eagle-import:SFM-110-X1-XXX-D-LC")
      (libsource (lib "eagle-import") (part "SFM-110-X1-XXX-D-LC"))
    )
    (comp (ref "CF19.2")
      (value "SFM-120-X1-XXX-D")
      (footprint "eagle-import:SFM-120-X1-XXX-D")
      (libsource (lib "eagle-import") (part "SFM-120-X1-XXX-D"))
    )
    (comp (ref "CM19.1")
      (value "J-MOLEX-SMPM-73300-0111X")
      (footprint "eagle-import:J-MOLEX-SMPM-73300-0111X")
      (libsource (lib "eagle-import") (part "J-MOLEX-SMPM-73300-0111X"))
    )
    (comp (ref "CM19.2")
      (value "J-MOLEX-SMPM-73300-0111X")
      (footprint "eagle-import:J-MOLEX-SMPM-73300-0111X")
      (libsource (lib "eagle-import") (part "J-MOLEX-SMPM-73300-0111X"))
    )
    (comp (ref "CM19.3")
      (value "J-MOLEX-SMPM-73300-0111X")
      (footprint "eagle-import:J-MOLEX-SMPM-73300-0111X")
      (libsource (lib "eagle-import") (part "J-MOLEX-SMPM-73300-0111X"))
    )
    (comp (ref "CF5.1")
      (value "SFM-110-X1-XXX-D-LC")
      (footprint "eagle-import:SFM-110-X1-XXX-D-LC")
      (libsource (lib "eagle-import") (part "SFM-110-X1-XXX-D-LC"))
    )
    (comp (ref "CF5.2")
      (value "SFM-120-X1-XXX-D")
      (footprint "eagle-import:SFM-120-X1-XXX-D")
      (libsource (lib "eagle-import") (part "SFM-120-X1-XXX-D"))
    )
    (comp (ref "CM5.1")
      (value "J-MOLEX-SMPM-73300-0111X")
      (footprint "eagle-import:J-MOLEX-SMPM-73300-0111X")
      (libsource (lib "eagle-import") (part "J-MOLEX-SMPM-73300-0111X"))
    )
    (comp (ref "CM5.2")
      (value "J-MOLEX-SMPM-73300-0111X")
      (footprint "eagle-import:J-MOLEX-SMPM-73300-0111X")
      (libsource (lib "eagle-import") (part "J-MOLEX-SMPM-73300-0111X"))
    )
    (comp (ref "CM5.3")
      (value "J-MOLEX-SMPM-73300-0111X")
      (footprint "eagle-import:J-MOLEX-SMPM-73300-0111X")
      (libsource (lib "eagle-import") (part "J-MOLEX-SMPM-73300-0111X"))
    )
    (comp (ref "CF1.1")
      (value "SFM-110-X1-XXX-D-LC")
      (footprint "eagle-import:SFM-110-X1-XXX-D-LC")
      (libsource (lib "eagle-import") (part "SFM-110-X1-XXX-D-LC"))
    )
    (comp (ref "CM1.1")
      (value "J-MOLEX-SMPM-73300-0111X")
      (footprint "eagle-import:J-MOLEX-SMPM-73300-0111X")
      (libsource (lib "eagle-import") (part "J-MOLEX-SMPM-73300-0111X"))
    )
    (comp (ref "CM1.2")
      (value "J-MOLEX-SMPM-73300-0111X")
      (footprint "eagle-import:J-MOLEX-SMPM-73300-0111X")
      (libsource (lib "eagle-import") (part "J-MOLEX-SMPM-73300-0111X"))
    )
    (comp (ref "CM1.3")
      (value "J-MOLEX-SMPM-73300-0111X")
      (footprint "eagle-import:J-MOLEX-SMPM-73300-0111X")
      (libsource (lib "eagle-import") (part "J-MOLEX-SMPM-73300-0111X"))
    )
    (comp (ref "CF18.1")
      (value "SFM-110-X1-XXX-D-LC")
      (footprint "eagle-import:SFM-110-X1-XXX-D-LC")
      (libsource (lib "eagle-import") (part "SFM-110-X1-XXX-D-LC"))
    )
    (comp (ref "CF18.2")
      (value "SFM-120-X1-XXX-D")
      (footprint "eagle-import:SFM-120-X1-XXX-D")
      (libsource (lib "eagle-import") (part "SFM-120-X1-XXX-D"))
    )
    (comp (ref "CM18.1")
      (value "J-MOLEX-SMPM-73300-0111X")
      (footprint "eagle-import:J-MOLEX-SMPM-73300-0111X")
      (libsource (lib "eagle-import") (part "J-MOLEX-SMPM-73300-0111X"))
    )
    (comp (ref "CM18.2")
      (value "J-MOLEX-SMPM-73300-0111X")
      (footprint "eagle-import:J-MOLEX-SMPM-73300-0111X")
      (libsource (lib "eagle-import") (part "J-MOLEX-SMPM-73300-0111X"))
    )
    (comp (ref "CM18.3")
      (value "J-MOLEX-SMPM-73300-0111X")
      (footprint "eagle-import:J-MOLEX-SMPM-73300-0111X")
      (libsource (lib "eagle-import") (part "J-MOLEX-SMPM-73300-0111X"))
    )
    (comp (ref "CF9.1")
      (value "SFM-110-X1-XXX-D-LC")
      (footprint "eagle-import:SFM-110-X1-XXX-D-LC")
      (libsource (lib "eagle-import") (part "SFM-110-X1-XXX-D-LC"))
    )
    (comp (ref "CF9.2")
      (value "SFM-120-X1-XXX-D")
      (footprint "eagle-import:SFM-120-X1-XXX-D")
      (libsource (lib "eagle-import") (part "SFM-120-X1-XXX-D"))
    )
    (comp (ref "CM9.1")
      (value "J-MOLEX-SMPM-73300-0111X")
      (footprint "eagle-import:J-MOLEX-SMPM-73300-0111X")
      (libsource (lib "eagle-import") (part "J-MOLEX-SMPM-73300-0111X"))
    )
    (comp (ref "CM9.2")
      (value "J-MOLEX-SMPM-73300-0111X")
      (footprint "eagle-import:J-MOLEX-SMPM-73300-0111X")
      (libsource (lib "eagle-import") (part "J-MOLEX-SMPM-73300-0111X"))
    )
    (comp (ref "CM9.3")
      (value "J-MOLEX-SMPM-73300-0111X")
      (footprint "eagle-import:J-MOLEX-SMPM-73300-0111X")
      (libsource (lib "eagle-import") (part "J-MOLEX-SMPM-73300-0111X"))
    )
    (comp (ref "CF3.1")
      (value "SFM-110-X1-XXX-D-LC")
      (footprint "eagle-import:SFM-110-X1-XXX-D-LC")
      (libsource (lib "eagle-import") (part "SFM-110-X1-XXX-D-LC"))
    )
    (comp (ref "CF3.2")
      (value "SFM-120-X1-XXX-D")
      (footprint "eagle-import:SFM-120-X1-XXX-D")
      (libsource (lib "eagle-import") (part "SFM-120-X1-XXX-D"))
    )
    (comp (ref "CM3.1")
      (value "J-MOLEX-SMPM-73300-0111X")
      (footprint "eagle-import:J-MOLEX-SMPM-73300-0111X")
      (libsource (lib "eagle-import") (part "J-MOLEX-SMPM-73300-0111X"))
    )
    (comp (ref "CM3.2")
      (value "J-MOLEX-SMPM-73300-0111X")
      (footprint "eagle-import:J-MOLEX-SMPM-73300-0111X")
      (libsource (lib "eagle-import") (part "J-MOLEX-SMPM-73300-0111X"))
    )
    (comp (ref "CM3.3")
      (value "J-MOLEX-SMPM-73300-0111X")
      (footprint "eagle-import:J-MOLEX-SMPM-73300-0111X")
      (libsource (lib "eagle-import") (part "J-MOLEX-SMPM-73300-0111X"))
    )
    (comp (ref "CF7.1")
      (value "SFM-110-X1-XXX-D-LC")
      (footprint "eagle-import:SFM-110-X1-XXX-D-LC")
      (libsource (lib "eagle-import") (part "SFM-110-X1-XXX-D-LC"))
    )
    (comp (ref "CF7.2")
      (value "SFM-120-X1-XXX-D")
      (footprint "eagle-import:SFM-120-X1-XXX-D")
      (libsource (lib "eagle-import") (part "SFM-120-X1-XXX-D"))
    )
    (comp (ref "CM7.1")
      (value "J-MOLEX-SMPM-73300-0111X")
      (footprint "eagle-import:J-MOLEX-SMPM-73300-0111X")
      (libsource (lib "eagle-import") (part "J-MOLEX-SMPM-73300-0111X"))
    )
    (comp (ref "CM7.2")
      (value "J-MOLEX-SMPM-73300-0111X")
      (footprint "eagle-import:J-MOLEX-SMPM-73300-0111X")
      (libsource (lib "eagle-import") (part "J-MOLEX-SMPM-73300-0111X"))
    )
    (comp (ref "CM7.3")
      (value "J-MOLEX-SMPM-73300-0111X")
      (footprint "eagle-import:J-MOLEX-SMPM-73300-0111X")
      (libsource (lib "eagle-import") (part "J-MOLEX-SMPM-73300-0111X"))
    )
    (comp (ref "CF8.1")
      (value "SFM-110-X1-XXX-D-LC")
      (footprint "eagle-import:SFM-110-X1-XXX-D-LC")
      (libsource (lib "eagle-import") (part "SFM-110-X1-XXX-D-LC"))
    )
    (comp (ref "CF8.2")
      (value "SFM-120-X1-XXX-D")
      (footprint "eagle-import:SFM-120-X1-XXX-D")
      (libsource (lib "eagle-import") (part "SFM-120-X1-XXX-D"))
    )
    (comp (ref "CM8.1")
      (value "J-MOLEX-SMPM-73300-0111X")
      (footprint "eagle-import:J-MOLEX-SMPM-73300-0111X")
      (libsource (lib "eagle-import") (part "J-MOLEX-SMPM-73300-0111X"))
    )
    (comp (ref "CM8.2")
      (value "J-MOLEX-SMPM-73300-0111X")
      (footprint "eagle-import:J-MOLEX-SMPM-73300-0111X")
      (libsource (lib "eagle-import") (part "J-MOLEX-SMPM-73300-0111X"))
    )
    (comp (ref "CM8.3")
      (value "J-MOLEX-SMPM-73300-0111X")
      (footprint "eagle-import:J-MOLEX-SMPM-73300-0111X")
      (libsource (lib "eagle-import") (part "J-MOLEX-SMPM-73300-0111X"))
    )
  )
  (nets
    (net (code "1") (name "CAN_H") (class "Default")
      (node (ref "CF10.2") (pin "3") (pinfunction "3_3") (pintype "passive"))
      (node (ref "CF10.2") (pin "4") (pinfunction "4_4") (pintype "passive"))
      (node (ref "CF11.2") (pin "3") (pinfunction "3_3") (pintype "passive"))
      (node (ref "CF11.2") (pin "4") (pinfunction "4_4") (pintype "passive"))
      (node (ref "CF12.2") (pin "3") (pinfunction "3_3") (pintype "passive"))
      (node (ref "CF12.2") (pin "4") (pinfunction "4_4") (pintype "passive"))
      (node (ref "CF13.2") (pin "3") (pinfunction "3_3") (pintype "passive"))
      (node (ref "CF13.2") (pin "4") (pinfunction "4_4") (pintype "passive"))
      (node (ref "CF14.2") (pin "3") (pinfunction "3_3") (pintype "passive"))
      (node (ref "CF14.2") (pin "4") (pinfunction "4_4") (pintype "passive"))
      (node (ref "CF15.2") (pin "3") (pinfunction "3_3") (pintype "passive"))
      (node (ref "CF15.2") (pin "4") (pinfunction "4_4") (pintype "passive"))
      (node (ref "CF16.2") (pin "3") (pinfunction "3_3") (pintype "passive"))
      (node (ref "CF16.2") (pin "4") (pinfunction "4_4") (pintype "passive"))
      (node (ref "CF17.2") (pin "3") (pinfunction "3_3") (pintype "passive"))
      (node (ref "CF17.2") (pin "4") (pinfunction "4_4") (pintype "passive"))
      (node (ref "CF18.2") (pin "3") (pinfunction "3_3") (pintype "passive"))
      (node (ref "CF18.2") (pin "4") (pinfunction "4_4") (pintype "passive"))
      (node (ref "CF19.2") (pin "3") (pinfunction "3_3") (pintype "passive"))
      (node (ref "CF19.2") (pin "4") (pinfunction "4_4") (pintype "passive"))
      (node (ref "CF2.2") (pin "3") (pinfunction "3_3") (pintype "passive"))
      (node (ref "CF2.2") (pin "4") (pinfunction "4_4") (pintype "passive"))
      (node (ref "CF3.2") (pin "3") (pinfunction "3_3") (pintype "passive"))
      (node (ref "CF3.2") (pin "4") (pinfunction "4_4") (pintype "passive"))
      (node (ref "CF4.2") (pin "3") (pinfunction "3_3") (pintype "passive"))
      (node (ref "CF4.2") (pin "4") (pinfunction "4_4") (pintype "passive"))
      (node (ref "CF5.2") (pin "3") (pinfunction "3_3") (pintype "passive"))
      (node (ref "CF5.2") (pin "4") (pinfunction "4_4") (pintype "passive"))
      (node (ref "CF6.2") (pin "3") (pinfunction "3_3") (pintype "passive"))
      (node (ref "CF6.2") (pin "4") (pinfunction "4_4") (pintype "passive"))
      (node (ref "CF7.2") (pin "3") (pinfunction "3_3") (pintype "passive"))
      (node (ref "CF7.2") (pin "4") (pinfunction "4_4") (pintype "passive"))
      (node (ref "CF8.2") (pin "3") (pinfunction "3_3") (pintype "passive"))
      (node (ref "CF8.2") (pin "4") (pinfunction "4_4") (pintype "passive"))
      (node (ref "CF9.2") (pin "3") (pinfunction "3_3") (pintype "passive"))
      (node (ref "CF9.2") (pin "4") (pinfunction "4_4") (pintype "passive"))
    )
    (net (code "2") (name "CAN_L") (class "Default")
      (node (ref "CF10.2") (pin "1") (pinfunction "1_1") (pintype "passive"))
      (node (ref "CF10.2") (pin "2") (pinfunction "2_2") (pintype "passive"))
      (node (ref "CF11.2") (pin "1") (pinfunction "1_1") (pintype "passive"))
      (node (ref "CF11.2") (pin "2") (pinfunction "2_2") (pintype "passive"))
      (node (ref "CF12.2") (pin "1") (pinfunction "1_1") (pintype "passive"))
      (node (ref "CF12.2") (pin "2") (pinfunction "2_2") (pintype "passive"))
      (node (ref "CF13.2") (pin "1") (pinfunction "1_1") (pintype "passive"))
      (node (ref "CF13.2") (pin "2") (pinfunction "2_2") (pintype "passive"))
      (node (ref "CF14.2") (pin "1") (pinfunction "1_1") (pintype "passive"))
      (node (ref "CF14.2") (pin "2") (pinfunction "2_2") (pintype "passive"))
      (node (ref "CF15.2") (pin "1") (pinfunction "1_1") (pintype "passive"))
      (node (ref "CF15.2") (pin "2") (pinfunction "2_2") (pintype "passive"))
      (node (ref "CF16.2") (pin "1") (pinfunction "1_1") (pintype "passive"))
      (node (ref "CF16.2") (pin "2") (pinfunction "2_2") (pintype "passive"))
      (node (ref "CF17.2") (pin "1") (pinfunction "1_1") (pintype "passive"))
      (node (ref "CF17.2") (pin "2") (pinfunction "2_2") (pintype "passive"))
      (node (ref "CF18.2") (pin "1") (pinfunction "1_1") (pintype "passive"))
      (node (ref "CF18.2") (pin "2") (pinfunction "2_2") (pintype "passive"))
      (node (ref "CF19.2") (pin "1") (pinfunction "1_1") (pintype "passive"))
      (node (ref "CF19.2") (pin "2") (pinfunction "2_2") (pintype "passive"))
      (node (ref "CF2.2") (pin "1") (pinfunction "1_1") (pintype "passive"))
      (node (ref "CF2.2") (pin "2") (pinfunction "2_2") (pintype "passive"))
      (node (ref "CF3.2") (pin "1") (pinfunction "1_1") (pintype "passive"))
      (node (ref "CF3.2") (pin "2") (pinfunction "2_2") (pintype "passive"))
      (node (ref "CF4.2") (pin "1") (pinfunction "1_1") (pintype "passive"))
      (node (ref "CF4.2") (pin "2") (pinfunction "2_2") (pintype "passive"))
      (node (ref "CF5.2") (pin "1") (pinfunction "1_1") (pintype "passive"))
      (node (ref "CF5.2") (pin "2") (pinfunction "2_2") (pintype "passive"))
      (node (ref "CF6.2") (pin "1") (pinfunction "1_1") (pintype "passive"))
      (node (ref "CF6.2") (pin "2") (pinfunction "2_2") (pintype "passive"))
      (node (ref "CF7.2") (pin "1") (pinfunction "1_1") (pintype "passive"))
      (node (ref "CF7.2") (pin "2") (pinfunction "2_2") (pintype "passive"))
      (node (ref "CF8.2") (pin "1") (pinfunction "1_1") (pintype "passive"))
      (node (ref "CF8.2") (pin "2") (pinfunction "2_2") (pintype "passive"))
      (node (ref "CF9.2") (pin "1") (pinfunction "1_1") (pintype "passive"))
      (node (ref "CF9.2") (pin "2") (pinfunction "2_2") (pintype "passive"))
    )
    (net (code "3") (name "GND") (class "Default")
      (node (ref "CF1.1") (pin "LC1") (pinfunction "LC1_LC1") (pintype "passive"))
      (node (ref "CF1.1") (pin "LC2") (pinfunction "LC2_LC2") (pintype "passive"))
      (node (ref "CF10.1") (pin "LC1") (pinfunction "LC1_LC1") (pintype "passive"))
      (node (ref "CF10.1") (pin "LC2") (pinfunction "LC2_LC2") (pintype "passive"))
      (node (ref "CF10.2") (pin "10") (pinfunction "10_10") (pintype "passive"))
      (node (ref "CF10.2") (pin "11") (pinfunction "11_11") (pintype "passive"))
      (node (ref "CF10.2") (pin "12") (pinfunction "12_12") (pintype "passive"))
      (node (ref "CF10.2") (pin "5") (pinfunction "5_5") (pintype "passive"))
      (node (ref "CF10.2") (pin "6") (pinfunction "6_6") (pintype "passive"))
      (node (ref "CF10.2") (pin "9") (pinfunction "9_9") (pintype "passive"))
      (node (ref "CF10.2") (pin "LC1") (pinfunction "LC1_LC1") (pintype "passive"))
      (node (ref "CF10.2") (pin "LC2") (pinfunction "LC2_LC2") (pintype "passive"))
      (node (ref "CF11.1") (pin "LC1") (pinfunction "LC1_LC1") (pintype "passive"))
      (node (ref "CF11.1") (pin "LC2") (pinfunction "LC2_LC2") (pintype "passive"))
      (node (ref "CF11.2") (pin "10") (pinfunction "10_10") (pintype "passive"))
      (node (ref "CF11.2") (pin "11") (pinfunction "11_11") (pintype "passive"))
      (node (ref "CF11.2") (pin "12") (pinfunction "12_12") (pintype "passive"))
      (node (ref "CF11.2") (pin "5") (pinfunction "5_5") (pintype "passive"))
      (node (ref "CF11.2") (pin "6") (pinfunction "6_6") (pintype "passive"))
      (node (ref "CF11.2") (pin "9") (pinfunction "9_9") (pintype "passive"))
      (node (ref "CF11.2") (pin "LC1") (pinfunction "LC1_LC1") (pintype "passive"))
      (node (ref "CF11.2") (pin "LC2") (pinfunction "LC2_LC2") (pintype "passive"))
      (node (ref "CF12.1") (pin "LC1") (pinfunction "LC1_LC1") (pintype "passive"))
      (node (ref "CF12.1") (pin "LC2") (pinfunction "LC2_LC2") (pintype "passive"))
      (node (ref "CF12.2") (pin "10") (pinfunction "10_10") (pintype "passive"))
      (node (ref "CF12.2") (pin "11") (pinfunction "11_11") (pintype "passive"))
      (node (ref "CF12.2") (pin "12") (pinfunction "12_12") (pintype "passive"))
      (node (ref "CF12.2") (pin "5") (pinfunction "5_5") (pintype "passive"))
      (node (ref "CF12.2") (pin "6") (pinfunction "6_6") (pintype "passive"))
      (node (ref "CF12.2") (pin "9") (pinfunction "9_9") (pintype "passive"))
      (node (ref "CF12.2") (pin "LC1") (pinfunction "LC1_LC1") (pintype "passive"))
      (node (ref "CF12.2") (pin "LC2") (pinfunction "LC2_LC2") (pintype "passive"))
      (node (ref "CF13.1") (pin "LC1") (pinfunction "LC1_LC1") (pintype "passive"))
      (node (ref "CF13.1") (pin "LC2") (pinfunction "LC2_LC2") (pintype "passive"))
      (node (ref "CF13.2") (pin "10") (pinfunction "10_10") (pintype "passive"))
      (node (ref "CF13.2") (pin "11") (pinfunction "11_11") (pintype "passive"))
      (node (ref "CF13.2") (pin "12") (pinfunction "12_12") (pintype "passive"))
      (node (ref "CF13.2") (pin "5") (pinfunction "5_5") (pintype "passive"))
      (node (ref "CF13.2") (pin "6") (pinfunction "6_6") (pintype "passive"))
      (node (ref "CF13.2") (pin "9") (pinfunction "9_9") (pintype "passive"))
      (node (ref "CF13.2") (pin "LC1") (pinfunction "LC1_LC1") (pintype "passive"))
      (node (ref "CF13.2") (pin "LC2") (pinfunction "LC2_LC2") (pintype "passive"))
      (node (ref "CF14.1") (pin "LC1") (pinfunction "LC1_LC1") (pintype "passive"))
      (node (ref "CF14.1") (pin "LC2") (pinfunction "LC2_LC2") (pintype "passive"))
      (node (ref "CF14.2") (pin "10") (pinfunction "10_10") (pintype "passive"))
      (node (ref "CF14.2") (pin "11") (pinfunction "11_11") (pintype "passive"))
      (node (ref "CF14.2") (pin "12") (pinfunction "12_12") (pintype "passive"))
      (node (ref "CF14.2") (pin "5") (pinfunction "5_5") (pintype "passive"))
      (node (ref "CF14.2") (pin "6") (pinfunction "6_6") (pintype "passive"))
      (node (ref "CF14.2") (pin "9") (pinfunction "9_9") (pintype "passive"))
      (node (ref "CF14.2") (pin "LC1") (pinfunction "LC1_LC1") (pintype "passive"))
      (node (ref "CF14.2") (pin "LC2") (pinfunction "LC2_LC2") (pintype "passive"))
      (node (ref "CF15.1") (pin "LC1") (pinfunction "LC1_LC1") (pintype "passive"))
      (node (ref "CF15.1") (pin "LC2") (pinfunction "LC2_LC2") (pintype "passive"))
      (node (ref "CF15.2") (pin "10") (pinfunction "10_10") (pintype "passive"))
      (node (ref "CF15.2") (pin "11") (pinfunction "11_11") (pintype "passive"))
      (node (ref "CF15.2") (pin "12") (pinfunction "12_12") (pintype "passive"))
      (node (ref "CF15.2") (pin "5") (pinfunction "5_5") (pintype "passive"))
      (node (ref "CF15.2") (pin "6") (pinfunction "6_6") (pintype "passive"))
      (node (ref "CF15.2") (pin "9") (pinfunction "9_9") (pintype "passive"))
      (node (ref "CF15.2") (pin "LC1") (pinfunction "LC1_LC1") (pintype "passive"))
      (node (ref "CF15.2") (pin "LC2") (pinfunction "LC2_LC2") (pintype "passive"))
      (node (ref "CF16.1") (pin "LC1") (pinfunction "LC1_LC1") (pintype "passive"))
      (node (ref "CF16.1") (pin "LC2") (pinfunction "LC2_LC2") (pintype "passive"))
      (node (ref "CF16.2") (pin "10") (pinfunction "10_10") (pintype "passive"))
      (node (ref "CF16.2") (pin "11") (pinfunction "11_11") (pintype "passive"))
      (node (ref "CF16.2") (pin "12") (pinfunction "12_12") (pintype "passive"))
      (node (ref "CF16.2") (pin "5") (pinfunction "5_5") (pintype "passive"))
      (node (ref "CF16.2") (pin "6") (pinfunction "6_6") (pintype "passive"))
      (node (ref "CF16.2") (pin "9") (pinfunction "9_9") (pintype "passive"))
      (node (ref "CF16.2") (pin "LC1") (pinfunction "LC1_LC1") (pintype "passive"))
      (node (ref "CF16.2") (pin "LC2") (pinfunction "LC2_LC2") (pintype "passive"))
      (node (ref "CF17.1") (pin "LC1") (pinfunction "LC1_LC1") (pintype "passive"))
      (node (ref "CF17.1") (pin "LC2") (pinfunction "LC2_LC2") (pintype "passive"))
      (node (ref "CF17.2") (pin "10") (pinfunction "10_10") (pintype "passive"))
      (node (ref "CF17.2") (pin "11") (pinfunction "11_11") (pintype "passive"))
      (node (ref "CF17.2") (pin "12") (pinfunction "12_12") (pintype "passive"))
      (node (ref "CF17.2") (pin "5") (pinfunction "5_5") (pintype "passive"))
      (node (ref "CF17.2") (pin "6") (pinfunction "6_6") (pintype "passive"))
      (node (ref "CF17.2") (pin "9") (pinfunction "9_9") (pintype "passive"))
      (node (ref "CF17.2") (pin "LC1") (pinfunction "LC1_LC1") (pintype "passive"))
      (node (ref "CF17.2") (pin "LC2") (pinfunction "LC2_LC2") (pintype "passive"))
      (node (ref "CF18.1") (pin "LC1") (pinfunction "LC1_LC1") (pintype "passive"))
      (node (ref "CF18.1") (pin "LC2") (pinfunction "LC2_LC2") (pintype "passive"))
      (node (ref "CF18.2") (pin "10") (pinfunction "10_10") (pintype "passive"))
      (node (ref "CF18.2") (pin "11") (pinfunction "11_11") (pintype "passive"))
      (node (ref "CF18.2") (pin "12") (pinfunction "12_12") (pintype "passive"))
      (node (ref "CF18.2") (pin "5") (pinfunction "5_5") (pintype "passive"))
      (node (ref "CF18.2") (pin "6") (pinfunction "6_6") (pintype "passive"))
      (node (ref "CF18.2") (pin "9") (pinfunction "9_9") (pintype "passive"))
      (node (ref "CF18.2") (pin "LC1") (pinfunction "LC1_LC1") (pintype "passive"))
      (node (ref "CF18.2") (pin "LC2") (pinfunction "LC2_LC2") (pintype "passive"))
      (node (ref "CF19.1") (pin "LC1") (pinfunction "LC1_LC1") (pintype "passive"))
      (node (ref "CF19.1") (pin "LC2") (pinfunction "LC2_LC2") (pintype "passive"))
      (node (ref "CF19.2") (pin "10") (pinfunction "10_10") (pintype "passive"))
      (node (ref "CF19.2") (pin "11") (pinfunction "11_11") (pintype "passive"))
      (node (ref "CF19.2") (pin "12") (pinfunction "12_12") (pintype "passive"))
      (node (ref "CF19.2") (pin "5") (pinfunction "5_5") (pintype "passive"))
      (node (ref "CF19.2") (pin "6") (pinfunction "6_6") (pintype "passive"))
      (node (ref "CF19.2") (pin "9") (pinfunction "9_9") (pintype "passive"))
      (node (ref "CF19.2") (pin "LC1") (pinfunction "LC1_LC1") (pintype "passive"))
      (node (ref "CF19.2") (pin "LC2") (pinfunction "LC2_LC2") (pintype "passive"))
      (node (ref "CF2.1") (pin "LC1") (pinfunction "LC1_LC1") (pintype "passive"))
      (node (ref "CF2.1") (pin "LC2") (pinfunction "LC2_LC2") (pintype "passive"))
      (node (ref "CF2.2") (pin "10") (pinfunction "10_10") (pintype "passive"))
      (node (ref "CF2.2") (pin "11") (pinfunction "11_11") (pintype "passive"))
      (node (ref "CF2.2") (pin "12") (pinfunction "12_12") (pintype "passive"))
      (node (ref "CF2.2") (pin "5") (pinfunction "5_5") (pintype "passive"))
      (node (ref "CF2.2") (pin "6") (pinfunction "6_6") (pintype "passive"))
      (node (ref "CF2.2") (pin "9") (pinfunction "9_9") (pintype "passive"))
      (node (ref "CF2.2") (pin "LC1") (pinfunction "LC1_LC1") (pintype "passive"))
      (node (ref "CF2.2") (pin "LC2") (pinfunction "LC2_LC2") (pintype "passive"))
      (node (ref "CF20.1") (pin "LC1") (pinfunction "LC1_LC1") (pintype "passive"))
      (node (ref "CF20.1") (pin "LC2") (pinfunction "LC2_LC2") (pintype "passive"))
      (node (ref "CF3.1") (pin "LC1") (pinfunction "LC1_LC1") (pintype "passive"))
      (node (ref "CF3.1") (pin "LC2") (pinfunction "LC2_LC2") (pintype "passive"))
      (node (ref "CF3.2") (pin "10") (pinfunction "10_10") (pintype "passive"))
      (node (ref "CF3.2") (pin "11") (pinfunction "11_11") (pintype "passive"))
      (node (ref "CF3.2") (pin "12") (pinfunction "12_12") (pintype "passive"))
      (node (ref "CF3.2") (pin "5") (pinfunction "5_5") (pintype "passive"))
      (node (ref "CF3.2") (pin "6") (pinfunction "6_6") (pintype "passive"))
      (node (ref "CF3.2") (pin "9") (pinfunction "9_9") (pintype "passive"))
      (node (ref "CF3.2") (pin "LC1") (pinfunction "LC1_LC1") (pintype "passive"))
      (node (ref "CF3.2") (pin "LC2") (pinfunction "LC2_LC2") (pintype "passive"))
      (node (ref "CF4.1") (pin "LC1") (pinfunction "LC1_LC1") (pintype "passive"))
      (node (ref "CF4.1") (pin "LC2") (pinfunction "LC2_LC2") (pintype "passive"))
      (node (ref "CF4.2") (pin "10") (pinfunction "10_10") (pintype "passive"))
      (node (ref "CF4.2") (pin "11") (pinfunction "11_11") (pintype "passive"))
      (node (ref "CF4.2") (pin "12") (pinfunction "12_12") (pintype "passive"))
      (node (ref "CF4.2") (pin "5") (pinfunction "5_5") (pintype "passive"))
      (node (ref "CF4.2") (pin "6") (pinfunction "6_6") (pintype "passive"))
      (node (ref "CF4.2") (pin "9") (pinfunction "9_9") (pintype "passive"))
      (node (ref "CF4.2") (pin "LC1") (pinfunction "LC1_LC1") (pintype "passive"))
      (node (ref "CF4.2") (pin "LC2") (pinfunction "LC2_LC2") (pintype "passive"))
      (node (ref "CF5.1") (pin "LC1") (pinfunction "LC1_LC1") (pintype "passive"))
      (node (ref "CF5.1") (pin "LC2") (pinfunction "LC2_LC2") (pintype "passive"))
      (node (ref "CF5.2") (pin "10") (pinfunction "10_10") (pintype "passive"))
      (node (ref "CF5.2") (pin "11") (pinfunction "11_11") (pintype "passive"))
      (node (ref "CF5.2") (pin "12") (pinfunction "12_12") (pintype "passive"))
      (node (ref "CF5.2") (pin "5") (pinfunction "5_5") (pintype "passive"))
      (node (ref "CF5.2") (pin "6") (pinfunction "6_6") (pintype "passive"))
      (node (ref "CF5.2") (pin "9") (pinfunction "9_9") (pintype "passive"))
      (node (ref "CF5.2") (pin "LC1") (pinfunction "LC1_LC1") (pintype "passive"))
      (node (ref "CF5.2") (pin "LC2") (pinfunction "LC2_LC2") (pintype "passive"))
      (node (ref "CF6.1") (pin "LC1") (pinfunction "LC1_LC1") (pintype "passive"))
      (node (ref "CF6.1") (pin "LC2") (pinfunction "LC2_LC2") (pintype "passive"))
      (node (ref "CF6.2") (pin "10") (pinfunction "10_10") (pintype "passive"))
      (node (ref "CF6.2") (pin "11") (pinfunction "11_11") (pintype "passive"))
      (node (ref "CF6.2") (pin "12") (pinfunction "12_12") (pintype "passive"))
      (node (ref "CF6.2") (pin "5") (pinfunction "5_5") (pintype "passive"))
      (node (ref "CF6.2") (pin "6") (pinfunction "6_6") (pintype "passive"))
      (node (ref "CF6.2") (pin "9") (pinfunction "9_9") (pintype "passive"))
      (node (ref "CF6.2") (pin "LC1") (pinfunction "LC1_LC1") (pintype "passive"))
      (node (ref "CF6.2") (pin "LC2") (pinfunction "LC2_LC2") (pintype "passive"))
      (node (ref "CF7.1") (pin "LC1") (pinfunction "LC1_LC1") (pintype "passive"))
      (node (ref "CF7.1") (pin "LC2") (pinfunction "LC2_LC2") (pintype "passive"))
      (node (ref "CF7.2") (pin "10") (pinfunction "10_10") (pintype "passive"))
      (node (ref "CF7.2") (pin "11") (pinfunction "11_11") (pintype "passive"))
      (node (ref "CF7.2") (pin "12") (pinfunction "12_12") (pintype "passive"))
      (node (ref "CF7.2") (pin "5") (pinfunction "5_5") (pintype "passive"))
      (node (ref "CF7.2") (pin "6") (pinfunction "6_6") (pintype "passive"))
      (node (ref "CF7.2") (pin "9") (pinfunction "9_9") (pintype "passive"))
      (node (ref "CF7.2") (pin "LC1") (pinfunction "LC1_LC1") (pintype "passive"))
      (node (ref "CF7.2") (pin "LC2") (pinfunction "LC2_LC2") (pintype "passive"))
      (node (ref "CF8.1") (pin "LC1") (pinfunction "LC1_LC1") (pintype "passive"))
      (node (ref "CF8.1") (pin "LC2") (pinfunction "LC2_LC2") (pintype "passive"))
      (node (ref "CF8.2") (pin "10") (pinfunction "10_10") (pintype "passive"))
      (node (ref "CF8.2") (pin "11") (pinfunction "11_11") (pintype "passive"))
      (node (ref "CF8.2") (pin "12") (pinfunction "12_12") (pintype "passive"))
      (node (ref "CF8.2") (pin "5") (pinfunction "5_5") (pintype "passive"))
      (node (ref "CF8.2") (pin "6") (pinfunction "6_6") (pintype "passive"))
      (node (ref "CF8.2") (pin "9") (pinfunction "9_9") (pintype "passive"))
      (node (ref "CF8.2") (pin "LC1") (pinfunction "LC1_LC1") (pintype "passive"))
      (node (ref "CF8.2") (pin "LC2") (pinfunction "LC2_LC2") (pintype "passive"))
      (node (ref "CF9.1") (pin "LC1") (pinfunction "LC1_LC1") (pintype "passive"))
      (node (ref "CF9.1") (pin "LC2") (pinfunction "LC2_LC2") (pintype "passive"))
      (node (ref "CF9.2") (pin "10") (pinfunction "10_10") (pintype "passive"))
      (node (ref "CF9.2") (pin "11") (pinfunction "11_11") (pintype "passive"))
      (node (ref "CF9.2") (pin "12") (pinfunction "12_12") (pintype "passive"))
      (node (ref "CF9.2") (pin "5") (pinfunction "5_5") (pintype "passive"))
      (node (ref "CF9.2") (pin "6") (pinfunction "6_6") (pintype "passive"))
      (node (ref "CF9.2") (pin "9") (pinfunction "9_9") (pintype "passive"))
      (node (ref "CF9.2") (pin "LC1") (pinfunction "LC1_LC1") (pintype "passive"))
      (node (ref "CF9.2") (pin "LC2") (pinfunction "LC2_LC2") (pintype "passive"))
      (node (ref "CM1.1") (pin "P$1") (pinfunction "SHIELD_P$1") (pintype "passive"))
      (node (ref "CM1.1") (pin "P$2") (pinfunction "SHIELD1_P$2") (pintype "passive"))
      (node (ref "CM1.1") (pin "P$3") (pinfunction "SHIELD2_P$3") (pintype "passive"))
      (node (ref "CM1.1") (pin "P$4") (pinfunction "SHIELD3_P$4") (pintype "passive"))
      (node (ref "CM1.1") (pin "P$5") (pinfunction "SHIELD5_P$5") (pintype "passive"))
      (node (ref "CM1.1") (pin "P$6") (pinfunction "SHIELD4_P$6") (pintype "passive"))
      (node (ref "CM1.2") (pin "P$1") (pinfunction "SHIELD_P$1") (pintype "passive"))
      (node (ref "CM1.2") (pin "P$2") (pinfunction "SHIELD1_P$2") (pintype "passive"))
      (node (ref "CM1.2") (pin "P$3") (pinfunction "SHIELD2_P$3") (pintype "passive"))
      (node (ref "CM1.2") (pin "P$4") (pinfunction "SHIELD3_P$4") (pintype "passive"))
      (node (ref "CM1.2") (pin "P$5") (pinfunction "SHIELD5_P$5") (pintype "passive"))
      (node (ref "CM1.2") (pin "P$6") (pinfunction "SHIELD4_P$6") (pintype "passive"))
      (node (ref "CM1.3") (pin "P$1") (pinfunction "SHIELD_P$1") (pintype "passive"))
      (node (ref "CM1.3") (pin "P$2") (pinfunction "SHIELD1_P$2") (pintype "passive"))
      (node (ref "CM1.3") (pin "P$3") (pinfunction "SHIELD2_P$3") (pintype "passive"))
      (node (ref "CM1.3") (pin "P$4") (pinfunction "SHIELD3_P$4") (pintype "passive"))
      (node (ref "CM1.3") (pin "P$5") (pinfunction "SHIELD5_P$5") (pintype "passive"))
      (node (ref "CM1.3") (pin "P$6") (pinfunction "SHIELD4_P$6") (pintype "passive"))
      (node (ref "CM10.1") (pin "P$1") (pinfunction "SHIELD_P$1") (pintype "passive"))
      (node (ref "CM10.1") (pin "P$2") (pinfunction "SHIELD1_P$2") (pintype "passive"))
      (node (ref "CM10.1") (pin "P$3") (pinfunction "SHIELD2_P$3") (pintype "passive"))
      (node (ref "CM10.1") (pin "P$4") (pinfunction "SHIELD3_P$4") (pintype "passive"))
      (node (ref "CM10.1") (pin "P$5") (pinfunction "SHIELD5_P$5") (pintype "passive"))
      (node (ref "CM10.1") (pin "P$6") (pinfunction "SHIELD4_P$6") (pintype "passive"))
      (node (ref "CM10.2") (pin "P$1") (pinfunction "SHIELD_P$1") (pintype "passive"))
      (node (ref "CM10.2") (pin "P$2") (pinfunction "SHIELD1_P$2") (pintype "passive"))
      (node (ref "CM10.2") (pin "P$3") (pinfunction "SHIELD2_P$3") (pintype "passive"))
      (node (ref "CM10.2") (pin "P$4") (pinfunction "SHIELD3_P$4") (pintype "passive"))
      (node (ref "CM10.2") (pin "P$5") (pinfunction "SHIELD5_P$5") (pintype "passive"))
      (node (ref "CM10.2") (pin "P$6") (pinfunction "SHIELD4_P$6") (pintype "passive"))
      (node (ref "CM10.3") (pin "P$1") (pinfunction "SHIELD_P$1") (pintype "passive"))
      (node (ref "CM10.3") (pin "P$2") (pinfunction "SHIELD1_P$2") (pintype "passive"))
      (node (ref "CM10.3") (pin "P$3") (pinfunction "SHIELD2_P$3") (pintype "passive"))
      (node (ref "CM10.3") (pin "P$4") (pinfunction "SHIELD3_P$4") (pintype "passive"))
      (node (ref "CM10.3") (pin "P$5") (pinfunction "SHIELD5_P$5") (pintype "passive"))
      (node (ref "CM10.3") (pin "P$6") (pinfunction "SHIELD4_P$6") (pintype "passive"))
      (node (ref "CM11.1") (pin "P$1") (pinfunction "SHIELD_P$1") (pintype "passive"))
      (node (ref "CM11.1") (pin "P$2") (pinfunction "SHIELD1_P$2") (pintype "passive"))
      (node (ref "CM11.1") (pin "P$3") (pinfunction "SHIELD2_P$3") (pintype "passive"))
      (node (ref "CM11.1") (pin "P$4") (pinfunction "SHIELD3_P$4") (pintype "passive"))
      (node (ref "CM11.1") (pin "P$5") (pinfunction "SHIELD5_P$5") (pintype "passive"))
      (node (ref "CM11.1") (pin "P$6") (pinfunction "SHIELD4_P$6") (pintype "passive"))
      (node (ref "CM11.2") (pin "P$1") (pinfunction "SHIELD_P$1") (pintype "passive"))
      (node (ref "CM11.2") (pin "P$2") (pinfunction "SHIELD1_P$2") (pintype "passive"))
      (node (ref "CM11.2") (pin "P$3") (pinfunction "SHIELD2_P$3") (pintype "passive"))
      (node (ref "CM11.2") (pin "P$4") (pinfunction "SHIELD3_P$4") (pintype "passive"))
      (node (ref "CM11.2") (pin "P$5") (pinfunction "SHIELD5_P$5") (pintype "passive"))
      (node (ref "CM11.2") (pin "P$6") (pinfunction "SHIELD4_P$6") (pintype "passive"))
      (node (ref "CM11.3") (pin "P$1") (pinfunction "SHIELD_P$1") (pintype "passive"))
      (node (ref "CM11.3") (pin "P$2") (pinfunction "SHIELD1_P$2") (pintype "passive"))
      (node (ref "CM11.3") (pin "P$3") (pinfunction "SHIELD2_P$3") (pintype "passive"))
      (node (ref "CM11.3") (pin "P$4") (pinfunction "SHIELD3_P$4") (pintype "passive"))
      (node (ref "CM11.3") (pin "P$5") (pinfunction "SHIELD5_P$5") (pintype "passive"))
      (node (ref "CM11.3") (pin "P$6") (pinfunction "SHIELD4_P$6") (pintype "passive"))
      (node (ref "CM12.1") (pin "P$1") (pinfunction "SHIELD_P$1") (pintype "passive"))
      (node (ref "CM12.1") (pin "P$2") (pinfunction "SHIELD1_P$2") (pintype "passive"))
      (node (ref "CM12.1") (pin "P$3") (pinfunction "SHIELD2_P$3") (pintype "passive"))
      (node (ref "CM12.1") (pin "P$4") (pinfunction "SHIELD3_P$4") (pintype "passive"))
      (node (ref "CM12.1") (pin "P$5") (pinfunction "SHIELD5_P$5") (pintype "passive"))
      (node (ref "CM12.1") (pin "P$6") (pinfunction "SHIELD4_P$6") (pintype "passive"))
      (node (ref "CM12.2") (pin "P$1") (pinfunction "SHIELD_P$1") (pintype "passive"))
      (node (ref "CM12.2") (pin "P$2") (pinfunction "SHIELD1_P$2") (pintype "passive"))
      (node (ref "CM12.2") (pin "P$3") (pinfunction "SHIELD2_P$3") (pintype "passive"))
      (node (ref "CM12.2") (pin "P$4") (pinfunction "SHIELD3_P$4") (pintype "passive"))
      (node (ref "CM12.2") (pin "P$5") (pinfunction "SHIELD5_P$5") (pintype "passive"))
      (node (ref "CM12.2") (pin "P$6") (pinfunction "SHIELD4_P$6") (pintype "passive"))
      (node (ref "CM12.3") (pin "P$1") (pinfunction "SHIELD_P$1") (pintype "passive"))
      (node (ref "CM12.3") (pin "P$2") (pinfunction "SHIELD1_P$2") (pintype "passive"))
      (node (ref "CM12.3") (pin "P$3") (pinfunction "SHIELD2_P$3") (pintype "passive"))
      (node (ref "CM12.3") (pin "P$4") (pinfunction "SHIELD3_P$4") (pintype "passive"))
      (node (ref "CM12.3") (pin "P$5") (pinfunction "SHIELD5_P$5") (pintype "passive"))
      (node (ref "CM12.3") (pin "P$6") (pinfunction "SHIELD4_P$6") (pintype "passive"))
      (node (ref "CM13.1") (pin "P$1") (pinfunction "SHIELD_P$1") (pintype "passive"))
      (node (ref "CM13.1") (pin "P$2") (pinfunction "SHIELD1_P$2") (pintype "passive"))
      (node (ref "CM13.1") (pin "P$3") (pinfunction "SHIELD2_P$3") (pintype "passive"))
      (node (ref "CM13.1") (pin "P$4") (pinfunction "SHIELD3_P$4") (pintype "passive"))
      (node (ref "CM13.1") (pin "P$5") (pinfunction "SHIELD5_P$5") (pintype "passive"))
      (node (ref "CM13.1") (pin "P$6") (pinfunction "SHIELD4_P$6") (pintype "passive"))
      (node (ref "CM13.2") (pin "P$1") (pinfunction "SHIELD_P$1") (pintype "passive"))
      (node (ref "CM13.2") (pin "P$2") (pinfunction "SHIELD1_P$2") (pintype "passive"))
      (node (ref "CM13.2") (pin "P$3") (pinfunction "SHIELD2_P$3") (pintype "passive"))
      (node (ref "CM13.2") (pin "P$4") (pinfunction "SHIELD3_P$4") (pintype "passive"))
      (node (ref "CM13.2") (pin "P$5") (pinfunction "SHIELD5_P$5") (pintype "passive"))
      (node (ref "CM13.2") (pin "P$6") (pinfunction "SHIELD4_P$6") (pintype "passive"))
      (node (ref "CM13.3") (pin "P$1") (pinfunction "SHIELD_P$1") (pintype "passive"))
      (node (ref "CM13.3") (pin "P$2") (pinfunction "SHIELD1_P$2") (pintype "passive"))
      (node (ref "CM13.3") (pin "P$3") (pinfunction "SHIELD2_P$3") (pintype "passive"))
      (node (ref "CM13.3") (pin "P$4") (pinfunction "SHIELD3_P$4") (pintype "passive"))
      (node (ref "CM13.3") (pin "P$5") (pinfunction "SHIELD5_P$5") (pintype "passive"))
      (node (ref "CM13.3") (pin "P$6") (pinfunction "SHIELD4_P$6") (pintype "passive"))
      (node (ref "CM14.1") (pin "P$1") (pinfunction "SHIELD_P$1") (pintype "passive"))
      (node (ref "CM14.1") (pin "P$2") (pinfunction "SHIELD1_P$2") (pintype "passive"))
      (node (ref "CM14.1") (pin "P$3") (pinfunction "SHIELD2_P$3") (pintype "passive"))
      (node (ref "CM14.1") (pin "P$4") (pinfunction "SHIELD3_P$4") (pintype "passive"))
      (node (ref "CM14.1") (pin "P$5") (pinfunction "SHIELD5_P$5") (pintype "passive"))
      (node (ref "CM14.1") (pin "P$6") (pinfunction "SHIELD4_P$6") (pintype "passive"))
      (node (ref "CM14.2") (pin "P$1") (pinfunction "SHIELD_P$1") (pintype "passive"))
      (node (ref "CM14.2") (pin "P$2") (pinfunction "SHIELD1_P$2") (pintype "passive"))
      (node (ref "CM14.2") (pin "P$3") (pinfunction "SHIELD2_P$3") (pintype "passive"))
      (node (ref "CM14.2") (pin "P$4") (pinfunction "SHIELD3_P$4") (pintype "passive"))
      (node (ref "CM14.2") (pin "P$5") (pinfunction "SHIELD5_P$5") (pintype "passive"))
      (node (ref "CM14.2") (pin "P$6") (pinfunction "SHIELD4_P$6") (pintype "passive"))
      (node (ref "CM14.3") (pin "P$1") (pinfunction "SHIELD_P$1") (pintype "passive"))
      (node (ref "CM14.3") (pin "P$2") (pinfunction "SHIELD1_P$2") (pintype "passive"))
      (node (ref "CM14.3") (pin "P$3") (pinfunction "SHIELD2_P$3") (pintype "passive"))
      (node (ref "CM14.3") (pin "P$4") (pinfunction "SHIELD3_P$4") (pintype "passive"))
      (node (ref "CM14.3") (pin "P$5") (pinfunction "SHIELD5_P$5") (pintype "passive"))
      (node (ref "CM14.3") (pin "P$6") (pinfunction "SHIELD4_P$6") (pintype "passive"))
      (node (ref "CM15.1") (pin "P$1") (pinfunction "SHIELD_P$1") (pintype "passive"))
      (node (ref "CM15.1") (pin "P$2") (pinfunction "SHIELD1_P$2") (pintype "passive"))
      (node (ref "CM15.1") (pin "P$3") (pinfunction "SHIELD2_P$3") (pintype "passive"))
      (node (ref "CM15.1") (pin "P$4") (pinfunction "SHIELD3_P$4") (pintype "passive"))
      (node (ref "CM15.1") (pin "P$5") (pinfunction "SHIELD5_P$5") (pintype "passive"))
      (node (ref "CM15.1") (pin "P$6") (pinfunction "SHIELD4_P$6") (pintype "passive"))
      (node (ref "CM15.2") (pin "P$1") (pinfunction "SHIELD_P$1") (pintype "passive"))
      (node (ref "CM15.2") (pin "P$2") (pinfunction "SHIELD1_P$2") (pintype "passive"))
      (node (ref "CM15.2") (pin "P$3") (pinfunction "SHIELD2_P$3") (pintype "passive"))
      (node (ref "CM15.2") (pin "P$4") (pinfunction "SHIELD3_P$4") (pintype "passive"))
      (node (ref "CM15.2") (pin "P$5") (pinfunction "SHIELD5_P$5") (pintype "passive"))
      (node (ref "CM15.2") (pin "P$6") (pinfunction "SHIELD4_P$6") (pintype "passive"))
      (node (ref "CM15.3") (pin "P$1") (pinfunction "SHIELD_P$1") (pintype "passive"))
      (node (ref "CM15.3") (pin "P$2") (pinfunction "SHIELD1_P$2") (pintype "passive"))
      (node (ref "CM15.3") (pin "P$3") (pinfunction "SHIELD2_P$3") (pintype "passive"))
      (node (ref "CM15.3") (pin "P$4") (pinfunction "SHIELD3_P$4") (pintype "passive"))
      (node (ref "CM15.3") (pin "P$5") (pinfunction "SHIELD5_P$5") (pintype "passive"))
      (node (ref "CM15.3") (pin "P$6") (pinfunction "SHIELD4_P$6") (pintype "passive"))
      (node (ref "CM16.1") (pin "P$1") (pinfunction "SHIELD_P$1") (pintype "passive"))
      (node (ref "CM16.1") (pin "P$2") (pinfunction "SHIELD1_P$2") (pintype "passive"))
      (node (ref "CM16.1") (pin "P$3") (pinfunction "SHIELD2_P$3") (pintype "passive"))
      (node (ref "CM16.1") (pin "P$4") (pinfunction "SHIELD3_P$4") (pintype "passive"))
      (node (ref "CM16.1") (pin "P$5") (pinfunction "SHIELD5_P$5") (pintype "passive"))
      (node (ref "CM16.1") (pin "P$6") (pinfunction "SHIELD4_P$6") (pintype "passive"))
      (node (ref "CM16.2") (pin "P$1") (pinfunction "SHIELD_P$1") (pintype "passive"))
      (node (ref "CM16.2") (pin "P$2") (pinfunction "SHIELD1_P$2") (pintype "passive"))
      (node (ref "CM16.2") (pin "P$3") (pinfunction "SHIELD2_P$3") (pintype "passive"))
      (node (ref "CM16.2") (pin "P$4") (pinfunction "SHIELD3_P$4") (pintype "passive"))
      (node (ref "CM16.2") (pin "P$5") (pinfunction "SHIELD5_P$5") (pintype "passive"))
      (node (ref "CM16.2") (pin "P$6") (pinfunction "SHIELD4_P$6") (pintype "passive"))
      (node (ref "CM16.3") (pin "P$1") (pinfunction "SHIELD_P$1") (pintype "passive"))
      (node (ref "CM16.3") (pin "P$2") (pinfunction "SHIELD1_P$2") (pintype "passive"))
      (node (ref "CM16.3") (pin "P$3") (pinfunction "SHIELD2_P$3") (pintype "passive"))
      (node (ref "CM16.3") (pin "P$4") (pinfunction "SHIELD3_P$4") (pintype "passive"))
      (node (ref "CM16.3") (pin "P$5") (pinfunction "SHIELD5_P$5") (pintype "passive"))
      (node (ref "CM16.3") (pin "P$6") (pinfunction "SHIELD4_P$6") (pintype "passive"))
      (node (ref "CM17.1") (pin "P$1") (pinfunction "SHIELD_P$1") (pintype "passive"))
      (node (ref "CM17.1") (pin "P$2") (pinfunction "SHIELD1_P$2") (pintype "passive"))
      (node (ref "CM17.1") (pin "P$3") (pinfunction "SHIELD2_P$3") (pintype "passive"))
      (node (ref "CM17.1") (pin "P$4") (pinfunction "SHIELD3_P$4") (pintype "passive"))
      (node (ref "CM17.1") (pin "P$5") (pinfunction "SHIELD5_P$5") (pintype "passive"))
      (node (ref "CM17.1") (pin "P$6") (pinfunction "SHIELD4_P$6") (pintype "passive"))
      (node (ref "CM17.2") (pin "P$1") (pinfunction "SHIELD_P$1") (pintype "passive"))
      (node (ref "CM17.2") (pin "P$2") (pinfunction "SHIELD1_P$2") (pintype "passive"))
      (node (ref "CM17.2") (pin "P$3") (pinfunction "SHIELD2_P$3") (pintype "passive"))
      (node (ref "CM17.2") (pin "P$4") (pinfunction "SHIELD3_P$4") (pintype "passive"))
      (node (ref "CM17.2") (pin "P$5") (pinfunction "SHIELD5_P$5") (pintype "passive"))
      (node (ref "CM17.2") (pin "P$6") (pinfunction "SHIELD4_P$6") (pintype "passive"))
      (node (ref "CM17.3") (pin "P$1") (pinfunction "SHIELD_P$1") (pintype "passive"))
      (node (ref "CM17.3") (pin "P$2") (pinfunction "SHIELD1_P$2") (pintype "passive"))
      (node (ref "CM17.3") (pin "P$3") (pinfunction "SHIELD2_P$3") (pintype "passive"))
      (node (ref "CM17.3") (pin "P$4") (pinfunction "SHIELD3_P$4") (pintype "passive"))
      (node (ref "CM17.3") (pin "P$5") (pinfunction "SHIELD5_P$5") (pintype "passive"))
      (node (ref "CM17.3") (pin "P$6") (pinfunction "SHIELD4_P$6") (pintype "passive"))
      (node (ref "CM18.1") (pin "P$1") (pinfunction "SHIELD_P$1") (pintype "passive"))
      (node (ref "CM18.1") (pin "P$2") (pinfunction "SHIELD1_P$2") (pintype "passive"))
      (node (ref "CM18.1") (pin "P$3") (pinfunction "SHIELD2_P$3") (pintype "passive"))
      (node (ref "CM18.1") (pin "P$4") (pinfunction "SHIELD3_P$4") (pintype "passive"))
      (node (ref "CM18.1") (pin "P$5") (pinfunction "SHIELD5_P$5") (pintype "passive"))
      (node (ref "CM18.1") (pin "P$6") (pinfunction "SHIELD4_P$6") (pintype "passive"))
      (node (ref "CM18.2") (pin "P$1") (pinfunction "SHIELD_P$1") (pintype "passive"))
      (node (ref "CM18.2") (pin "P$2") (pinfunction "SHIELD1_P$2") (pintype "passive"))
      (node (ref "CM18.2") (pin "P$3") (pinfunction "SHIELD2_P$3") (pintype "passive"))
      (node (ref "CM18.2") (pin "P$4") (pinfunction "SHIELD3_P$4") (pintype "passive"))
      (node (ref "CM18.2") (pin "P$5") (pinfunction "SHIELD5_P$5") (pintype "passive"))
      (node (ref "CM18.2") (pin "P$6") (pinfunction "SHIELD4_P$6") (pintype "passive"))
      (node (ref "CM18.3") (pin "P$1") (pinfunction "SHIELD_P$1") (pintype "passive"))
      (node (ref "CM18.3") (pin "P$2") (pinfunction "SHIELD1_P$2") (pintype "passive"))
      (node (ref "CM18.3") (pin "P$3") (pinfunction "SHIELD2_P$3") (pintype "passive"))
      (node (ref "CM18.3") (pin "P$4") (pinfunction "SHIELD3_P$4") (pintype "passive"))
      (node (ref "CM18.3") (pin "P$5") (pinfunction "SHIELD5_P$5") (pintype "passive"))
      (node (ref "CM18.3") (pin "P$6") (pinfunction "SHIELD4_P$6") (pintype "passive"))
      (node (ref "CM19.1") (pin "P$1") (pinfunction "SHIELD_P$1") (pintype "passive"))
      (node (ref "CM19.1") (pin "P$2") (pinfunction "SHIELD1_P$2") (pintype "passive"))
      (node (ref "CM19.1") (pin "P$3") (pinfunction "SHIELD2_P$3") (pintype "passive"))
      (node (ref "CM19.1") (pin "P$4") (pinfunction "SHIELD3_P$4") (pintype "passive"))
      (node (ref "CM19.1") (pin "P$5") (pinfunction "SHIELD5_P$5") (pintype "passive"))
      (node (ref "CM19.1") (pin "P$6") (pinfunction "SHIELD4_P$6") (pintype "passive"))
      (node (ref "CM19.2") (pin "P$1") (pinfunction "SHIELD_P$1") (pintype "passive"))
      (node (ref "CM19.2") (pin "P$2") (pinfunction "SHIELD1_P$2") (pintype "passive"))
      (node (ref "CM19.2") (pin "P$3") (pinfunction "SHIELD2_P$3") (pintype "passive"))
      (node (ref "CM19.2") (pin "P$4") (pinfunction "SHIELD3_P$4") (pintype "passive"))
      (node (ref "CM19.2") (pin "P$5") (pinfunction "SHIELD5_P$5") (pintype "passive"))
      (node (ref "CM19.2") (pin "P$6") (pinfunction "SHIELD4_P$6") (pintype "passive"))
      (node (ref "CM19.3") (pin "P$1") (pinfunction "SHIELD_P$1") (pintype "passive"))
      (node (ref "CM19.3") (pin "P$2") (pinfunction "SHIELD1_P$2") (pintype "passive"))
      (node (ref "CM19.3") (pin "P$3") (pinfunction "SHIELD2_P$3") (pintype "passive"))
      (node (ref "CM19.3") (pin "P$4") (pinfunction "SHIELD3_P$4") (pintype "passive"))
      (node (ref "CM19.3") (pin "P$5") (pinfunction "SHIELD5_P$5") (pintype "passive"))
      (node (ref "CM19.3") (pin "P$6") (pinfunction "SHIELD4_P$6") (pintype "passive"))
      (node (ref "CM2.1") (pin "P$1") (pinfunction "SHIELD_P$1") (pintype "passive"))
      (node (ref "CM2.1") (pin "P$2") (pinfunction "SHIELD1_P$2") (pintype "passive"))
      (node (ref "CM2.1") (pin "P$3") (pinfunction "SHIELD2_P$3") (pintype "passive"))
      (node (ref "CM2.1") (pin "P$4") (pinfunction "SHIELD3_P$4") (pintype "passive"))
      (node (ref "CM2.1") (pin "P$5") (pinfunction "SHIELD5_P$5") (pintype "passive"))
      (node (ref "CM2.1") (pin "P$6") (pinfunction "SHIELD4_P$6") (pintype "passive"))
      (node (ref "CM2.2") (pin "P$1") (pinfunction "SHIELD_P$1") (pintype "passive"))
      (node (ref "CM2.2") (pin "P$2") (pinfunction "SHIELD1_P$2") (pintype "passive"))
      (node (ref "CM2.2") (pin "P$3") (pinfunction "SHIELD2_P$3") (pintype "passive"))
      (node (ref "CM2.2") (pin "P$4") (pinfunction "SHIELD3_P$4") (pintype "passive"))
      (node (ref "CM2.2") (pin "P$5") (pinfunction "SHIELD5_P$5") (pintype "passive"))
      (node (ref "CM2.2") (pin "P$6") (pinfunction "SHIELD4_P$6") (pintype "passive"))
      (node (ref "CM2.3") (pin "P$1") (pinfunction "SHIELD_P$1") (pintype "passive"))
      (node (ref "CM2.3") (pin "P$2") (pinfunction "SHIELD1_P$2") (pintype "passive"))
      (node (ref "CM2.3") (pin "P$3") (pinfunction "SHIELD2_P$3") (pintype "passive"))
      (node (ref "CM2.3") (pin "P$4") (pinfunction "SHIELD3_P$4") (pintype "passive"))
      (node (ref "CM2.3") (pin "P$5") (pinfunction "SHIELD5_P$5") (pintype "passive"))
      (node (ref "CM2.3") (pin "P$6") (pinfunction "SHIELD4_P$6") (pintype "passive"))
      (node (ref "CM20.1") (pin "P$1") (pinfunction "SHIELD_P$1") (pintype "passive"))
      (node (ref "CM20.1") (pin "P$2") (pinfunction "SHIELD1_P$2") (pintype "passive"))
      (node (ref "CM20.1") (pin "P$3") (pinfunction "SHIELD2_P$3") (pintype "passive"))
      (node (ref "CM20.1") (pin "P$4") (pinfunction "SHIELD3_P$4") (pintype "passive"))
      (node (ref "CM20.1") (pin "P$5") (pinfunction "SHIELD5_P$5") (pintype "passive"))
      (node (ref "CM20.1") (pin "P$6") (pinfunction "SHIELD4_P$6") (pintype "passive"))
      (node (ref "CM20.2") (pin "P$1") (pinfunction "SHIELD_P$1") (pintype "passive"))
      (node (ref "CM20.2") (pin "P$2") (pinfunction "SHIELD1_P$2") (pintype "passive"))
      (node (ref "CM20.2") (pin "P$3") (pinfunction "SHIELD2_P$3") (pintype "passive"))
      (node (ref "CM20.2") (pin "P$4") (pinfunction "SHIELD3_P$4") (pintype "passive"))
      (node (ref "CM20.2") (pin "P$5") (pinfunction "SHIELD5_P$5") (pintype "passive"))
      (node (ref "CM20.2") (pin "P$6") (pinfunction "SHIELD4_P$6") (pintype "passive"))
      (node (ref "CM20.3") (pin "P$1") (pinfunction "SHIELD_P$1") (pintype "passive"))
      (node (ref "CM20.3") (pin "P$2") (pinfunction "SHIELD1_P$2") (pintype "passive"))
      (node (ref "CM20.3") (pin "P$3") (pinfunction "SHIELD2_P$3") (pintype "passive"))
      (node (ref "CM20.3") (pin "P$4") (pinfunction "SHIELD3_P$4") (pintype "passive"))
      (node (ref "CM20.3") (pin "P$5") (pinfunction "SHIELD5_P$5") (pintype "passive"))
      (node (ref "CM20.3") (pin "P$6") (pinfunction "SHIELD4_P$6") (pintype "passive"))
      (node (ref "CM3.1") (pin "P$1") (pinfunction "SHIELD_P$1") (pintype "passive"))
      (node (ref "CM3.1") (pin "P$2") (pinfunction "SHIELD1_P$2") (pintype "passive"))
      (node (ref "CM3.1") (pin "P$3") (pinfunction "SHIELD2_P$3") (pintype "passive"))
      (node (ref "CM3.1") (pin "P$4") (pinfunction "SHIELD3_P$4") (pintype "passive"))
      (node (ref "CM3.1") (pin "P$5") (pinfunction "SHIELD5_P$5") (pintype "passive"))
      (node (ref "CM3.1") (pin "P$6") (pinfunction "SHIELD4_P$6") (pintype "passive"))
      (node (ref "CM3.2") (pin "P$1") (pinfunction "SHIELD_P$1") (pintype "passive"))
      (node (ref "CM3.2") (pin "P$2") (pinfunction "SHIELD1_P$2") (pintype "passive"))
      (node (ref "CM3.2") (pin "P$3") (pinfunction "SHIELD2_P$3") (pintype "passive"))
      (node (ref "CM3.2") (pin "P$4") (pinfunction "SHIELD3_P$4") (pintype "passive"))
      (node (ref "CM3.2") (pin "P$5") (pinfunction "SHIELD5_P$5") (pintype "passive"))
      (node (ref "CM3.2") (pin "P$6") (pinfunction "SHIELD4_P$6") (pintype "passive"))
      (node (ref "CM3.3") (pin "P$1") (pinfunction "SHIELD_P$1") (pintype "passive"))
      (node (ref "CM3.3") (pin "P$2") (pinfunction "SHIELD1_P$2") (pintype "passive"))
      (node (ref "CM3.3") (pin "P$3") (pinfunction "SHIELD2_P$3") (pintype "passive"))
      (node (ref "CM3.3") (pin "P$4") (pinfunction "SHIELD3_P$4") (pintype "passive"))
      (node (ref "CM3.3") (pin "P$5") (pinfunction "SHIELD5_P$5") (pintype "passive"))
      (node (ref "CM3.3") (pin "P$6") (pinfunction "SHIELD4_P$6") (pintype "passive"))
      (node (ref "CM4.1") (pin "P$1") (pinfunction "SHIELD_P$1") (pintype "passive"))
      (node (ref "CM4.1") (pin "P$2") (pinfunction "SHIELD1_P$2") (pintype "passive"))
      (node (ref "CM4.1") (pin "P$3") (pinfunction "SHIELD2_P$3") (pintype "passive"))
      (node (ref "CM4.1") (pin "P$4") (pinfunction "SHIELD3_P$4") (pintype "passive"))
      (node (ref "CM4.1") (pin "P$5") (pinfunction "SHIELD5_P$5") (pintype "passive"))
      (node (ref "CM4.1") (pin "P$6") (pinfunction "SHIELD4_P$6") (pintype "passive"))
      (node (ref "CM4.2") (pin "P$1") (pinfunction "SHIELD_P$1") (pintype "passive"))
      (node (ref "CM4.2") (pin "P$2") (pinfunction "SHIELD1_P$2") (pintype "passive"))
      (node (ref "CM4.2") (pin "P$3") (pinfunction "SHIELD2_P$3") (pintype "passive"))
      (node (ref "CM4.2") (pin "P$4") (pinfunction "SHIELD3_P$4") (pintype "passive"))
      (node (ref "CM4.2") (pin "P$5") (pinfunction "SHIELD5_P$5") (pintype "passive"))
      (node (ref "CM4.2") (pin "P$6") (pinfunction "SHIELD4_P$6") (pintype "passive"))
      (node (ref "CM4.3") (pin "P$1") (pinfunction "SHIELD_P$1") (pintype "passive"))
      (node (ref "CM4.3") (pin "P$2") (pinfunction "SHIELD1_P$2") (pintype "passive"))
      (node (ref "CM4.3") (pin "P$3") (pinfunction "SHIELD2_P$3") (pintype "passive"))
      (node (ref "CM4.3") (pin "P$4") (pinfunction "SHIELD3_P$4") (pintype "passive"))
      (node (ref "CM4.3") (pin "P$5") (pinfunction "SHIELD5_P$5") (pintype "passive"))
      (node (ref "CM4.3") (pin "P$6") (pinfunction "SHIELD4_P$6") (pintype "passive"))
      (node (ref "CM5.1") (pin "P$1") (pinfunction "SHIELD_P$1") (pintype "passive"))
      (node (ref "CM5.1") (pin "P$2") (pinfunction "SHIELD1_P$2") (pintype "passive"))
      (node (ref "CM5.1") (pin "P$3") (pinfunction "SHIELD2_P$3") (pintype "passive"))
      (node (ref "CM5.1") (pin "P$4") (pinfunction "SHIELD3_P$4") (pintype "passive"))
      (node (ref "CM5.1") (pin "P$5") (pinfunction "SHIELD5_P$5") (pintype "passive"))
      (node (ref "CM5.1") (pin "P$6") (pinfunction "SHIELD4_P$6") (pintype "passive"))
      (node (ref "CM5.2") (pin "P$1") (pinfunction "SHIELD_P$1") (pintype "passive"))
      (node (ref "CM5.2") (pin "P$2") (pinfunction "SHIELD1_P$2") (pintype "passive"))
      (node (ref "CM5.2") (pin "P$3") (pinfunction "SHIELD2_P$3") (pintype "passive"))
      (node (ref "CM5.2") (pin "P$4") (pinfunction "SHIELD3_P$4") (pintype "passive"))
      (node (ref "CM5.2") (pin "P$5") (pinfunction "SHIELD5_P$5") (pintype "passive"))
      (node (ref "CM5.2") (pin "P$6") (pinfunction "SHIELD4_P$6") (pintype "passive"))
      (node (ref "CM5.3") (pin "P$1") (pinfunction "SHIELD_P$1") (pintype "passive"))
      (node (ref "CM5.3") (pin "P$2") (pinfunction "SHIELD1_P$2") (pintype "passive"))
      (node (ref "CM5.3") (pin "P$3") (pinfunction "SHIELD2_P$3") (pintype "passive"))
      (node (ref "CM5.3") (pin "P$4") (pinfunction "SHIELD3_P$4") (pintype "passive"))
      (node (ref "CM5.3") (pin "P$5") (pinfunction "SHIELD5_P$5") (pintype "passive"))
      (node (ref "CM5.3") (pin "P$6") (pinfunction "SHIELD4_P$6") (pintype "passive"))
      (node (ref "CM6.1") (pin "P$1") (pinfunction "SHIELD_P$1") (pintype "passive"))
      (node (ref "CM6.1") (pin "P$2") (pinfunction "SHIELD1_P$2") (pintype "passive"))
      (node (ref "CM6.1") (pin "P$3") (pinfunction "SHIELD2_P$3") (pintype "passive"))
      (node (ref "CM6.1") (pin "P$4") (pinfunction "SHIELD3_P$4") (pintype "passive"))
      (node (ref "CM6.1") (pin "P$5") (pinfunction "SHIELD5_P$5") (pintype "passive"))
      (node (ref "CM6.1") (pin "P$6") (pinfunction "SHIELD4_P$6") (pintype "passive"))
      (node (ref "CM6.2") (pin "P$1") (pinfunction "SHIELD_P$1") (pintype "passive"))
      (node (ref "CM6.2") (pin "P$2") (pinfunction "SHIELD1_P$2") (pintype "passive"))
      (node (ref "CM6.2") (pin "P$3") (pinfunction "SHIELD2_P$3") (pintype "passive"))
      (node (ref "CM6.2") (pin "P$4") (pinfunction "SHIELD3_P$4") (pintype "passive"))
      (node (ref "CM6.2") (pin "P$5") (pinfunction "SHIELD5_P$5") (pintype "passive"))
      (node (ref "CM6.2") (pin "P$6") (pinfunction "SHIELD4_P$6") (pintype "passive"))
      (node (ref "CM6.3") (pin "P$1") (pinfunction "SHIELD_P$1") (pintype "passive"))
      (node (ref "CM6.3") (pin "P$2") (pinfunction "SHIELD1_P$2") (pintype "passive"))
      (node (ref "CM6.3") (pin "P$3") (pinfunction "SHIELD2_P$3") (pintype "passive"))
      (node (ref "CM6.3") (pin "P$4") (pinfunction "SHIELD3_P$4") (pintype "passive"))
      (node (ref "CM6.3") (pin "P$5") (pinfunction "SHIELD5_P$5") (pintype "passive"))
      (node (ref "CM6.3") (pin "P$6") (pinfunction "SHIELD4_P$6") (pintype "passive"))
      (node (ref "CM7.1") (pin "P$1") (pinfunction "SHIELD_P$1") (pintype "passive"))
      (node (ref "CM7.1") (pin "P$2") (pinfunction "SHIELD1_P$2") (pintype "passive"))
      (node (ref "CM7.1") (pin "P$3") (pinfunction "SHIELD2_P$3") (pintype "passive"))
      (node (ref "CM7.1") (pin "P$4") (pinfunction "SHIELD3_P$4") (pintype "passive"))
      (node (ref "CM7.1") (pin "P$5") (pinfunction "SHIELD5_P$5") (pintype "passive"))
      (node (ref "CM7.1") (pin "P$6") (pinfunction "SHIELD4_P$6") (pintype "passive"))
      (node (ref "CM7.2") (pin "P$1") (pinfunction "SHIELD_P$1") (pintype "passive"))
      (node (ref "CM7.2") (pin "P$2") (pinfunction "SHIELD1_P$2") (pintype "passive"))
      (node (ref "CM7.2") (pin "P$3") (pinfunction "SHIELD2_P$3") (pintype "passive"))
      (node (ref "CM7.2") (pin "P$4") (pinfunction "SHIELD3_P$4") (pintype "passive"))
      (node (ref "CM7.2") (pin "P$5") (pinfunction "SHIELD5_P$5") (pintype "passive"))
      (node (ref "CM7.2") (pin "P$6") (pinfunction "SHIELD4_P$6") (pintype "passive"))
      (node (ref "CM7.3") (pin "P$1") (pinfunction "SHIELD_P$1") (pintype "passive"))
      (node (ref "CM7.3") (pin "P$2") (pinfunction "SHIELD1_P$2") (pintype "passive"))
      (node (ref "CM7.3") (pin "P$3") (pinfunction "SHIELD2_P$3") (pintype "passive"))
      (node (ref "CM7.3") (pin "P$4") (pinfunction "SHIELD3_P$4") (pintype "passive"))
      (node (ref "CM7.3") (pin "P$5") (pinfunction "SHIELD5_P$5") (pintype "passive"))
      (node (ref "CM7.3") (pin "P$6") (pinfunction "SHIELD4_P$6") (pintype "passive"))
      (node (ref "CM8.1") (pin "P$1") (pinfunction "SHIELD_P$1") (pintype "passive"))
      (node (ref "CM8.1") (pin "P$2") (pinfunction "SHIELD1_P$2") (pintype "passive"))
      (node (ref "CM8.1") (pin "P$3") (pinfunction "SHIELD2_P$3") (pintype "passive"))
      (node (ref "CM8.1") (pin "P$4") (pinfunction "SHIELD3_P$4") (pintype "passive"))
      (node (ref "CM8.1") (pin "P$5") (pinfunction "SHIELD5_P$5") (pintype "passive"))
      (node (ref "CM8.1") (pin "P$6") (pinfunction "SHIELD4_P$6") (pintype "passive"))
      (node (ref "CM8.2") (pin "P$1") (pinfunction "SHIELD_P$1") (pintype "passive"))
      (node (ref "CM8.2") (pin "P$2") (pinfunction "SHIELD1_P$2") (pintype "passive"))
      (node (ref "CM8.2") (pin "P$3") (pinfunction "SHIELD2_P$3") (pintype "passive"))
      (node (ref "CM8.2") (pin "P$4") (pinfunction "SHIELD3_P$4") (pintype "passive"))
      (node (ref "CM8.2") (pin "P$5") (pinfunction "SHIELD5_P$5") (pintype "passive"))
      (node (ref "CM8.2") (pin "P$6") (pinfunction "SHIELD4_P$6") (pintype "passive"))
      (node (ref "CM8.3") (pin "P$1") (pinfunction "SHIELD_P$1") (pintype "passive"))
      (node (ref "CM8.3") (pin "P$2") (pinfunction "SHIELD1_P$2") (pintype "passive"))
      (node (ref "CM8.3") (pin "P$3") (pinfunction "SHIELD2_P$3") (pintype "passive"))
      (node (ref "CM8.3") (pin "P$4") (pinfunction "SHIELD3_P$4") (pintype "passive"))
      (node (ref "CM8.3") (pin "P$5") (pinfunction "SHIELD5_P$5") (pintype "passive"))
      (node (ref "CM8.3") (pin "P$6") (pinfunction "SHIELD4_P$6") (pintype "passive"))
      (node (ref "CM9.1") (pin "P$1") (pinfunction "SHIELD_P$1") (pintype "passive"))
      (node (ref "CM9.1") (pin "P$2") (pinfunction "SHIELD1_P$2") (pintype "passive"))
      (node (ref "CM9.1") (pin "P$3") (pinfunction "SHIELD2_P$3") (pintype "passive"))
      (node (ref "CM9.1") (pin "P$4") (pinfunction "SHIELD3_P$4") (pintype "passive"))
      (node (ref "CM9.1") (pin "P$5") (pinfunction "SHIELD5_P$5") (pintype "passive"))
      (node (ref "CM9.1") (pin "P$6") (pinfunction "SHIELD4_P$6") (pintype "passive"))
      (node (ref "CM9.2") (pin "P$1") (pinfunction "SHIELD_P$1") (pintype "passive"))
      (node (ref "CM9.2") (pin "P$2") (pinfunction "SHIELD1_P$2") (pintype "passive"))
      (node (ref "CM9.2") (pin "P$3") (pinfunction "SHIELD2_P$3") (pintype "passive"))
      (node (ref "CM9.2") (pin "P$4") (pinfunction "SHIELD3_P$4") (pintype "passive"))
      (node (ref "CM9.2") (pin "P$5") (pinfunction "SHIELD5_P$5") (pintype "passive"))
      (node (ref "CM9.2") (pin "P$6") (pinfunction "SHIELD4_P$6") (pintype "passive"))
      (node (ref "CM9.3") (pin "P$1") (pinfunction "SHIELD_P$1") (pintype "passive"))
      (node (ref "CM9.3") (pin "P$2") (pinfunction "SHIELD1_P$2") (pintype "passive"))
      (node (ref "CM9.3") (pin "P$3") (pinfunction "SHIELD2_P$3") (pintype "passive"))
      (node (ref "CM9.3") (pin "P$4") (pinfunction "SHIELD3_P$4") (pintype "passive"))
      (node (ref "CM9.3") (pin "P$5") (pinfunction "SHIELD5_P$5") (pintype "passive"))
      (node (ref "CM9.3") (pin "P$6") (pinfunction "SHIELD4_P$6") (pintype "passive"))
    )
    (net (code "4") (name "VBUS") (class "Default")
      (node (ref "CF10.2") (pin "13") (pinfunction "13_13") (pintype "passive"))
      (node (ref "CF10.2") (pin "14") (pinfunction "14_14") (pintype "passive"))
      (node (ref "CF10.2") (pin "15") (pinfunction "15_15") (pintype "passive"))
      (node (ref "CF10.2") (pin "16") (pinfunction "16_16") (pintype "passive"))
      (node (ref "CF11.2") (pin "13") (pinfunction "13_13") (pintype "passive"))
      (node (ref "CF11.2") (pin "14") (pinfunction "14_14") (pintype "passive"))
      (node (ref "CF11.2") (pin "15") (pinfunction "15_15") (pintype "passive"))
      (node (ref "CF11.2") (pin "16") (pinfunction "16_16") (pintype "passive"))
      (node (ref "CF12.2") (pin "13") (pinfunction "13_13") (pintype "passive"))
      (node (ref "CF12.2") (pin "14") (pinfunction "14_14") (pintype "passive"))
      (node (ref "CF12.2") (pin "15") (pinfunction "15_15") (pintype "passive"))
      (node (ref "CF12.2") (pin "16") (pinfunction "16_16") (pintype "passive"))
      (node (ref "CF13.2") (pin "13") (pinfunction "13_13") (pintype "passive"))
      (node (ref "CF13.2") (pin "14") (pinfunction "14_14") (pintype "passive"))
      (node (ref "CF13.2") (pin "15") (pinfunction "15_15") (pintype "passive"))
      (node (ref "CF13.2") (pin "16") (pinfunction "16_16") (pintype "passive"))
      (node (ref "CF14.2") (pin "13") (pinfunction "13_13") (pintype "passive"))
      (node (ref "CF14.2") (pin "14") (pinfunction "14_14") (pintype "passive"))
      (node (ref "CF14.2") (pin "15") (pinfunction "15_15") (pintype "passive"))
      (node (ref "CF14.2") (pin "16") (pinfunction "16_16") (pintype "passive"))
      (node (ref "CF15.2") (pin "13") (pinfunction "13_13") (pintype "passive"))
      (node (ref "CF15.2") (pin "14") (pinfunction "14_14") (pintype "passive"))
      (node (ref "CF15.2") (pin "15") (pinfunction "15_15") (pintype "passive"))
      (node (ref "CF15.2") (pin "16") (pinfunction "16_16") (pintype "passive"))
      (node (ref "CF16.2") (pin "13") (pinfunction "13_13") (pintype "passive"))
      (node (ref "CF16.2") (pin "14") (pinfunction "14_14") (pintype "passive"))
      (node (ref "CF16.2") (pin "15") (pinfunction "15_15") (pintype "passive"))
      (node (ref "CF16.2") (pin "16") (pinfunction "16_16") (pintype "passive"))
      (node (ref "CF17.2") (pin "13") (pinfunction "13_13") (pintype "passive"))
      (node (ref "CF17.2") (pin "14") (pinfunction "14_14") (pintype "passive"))
      (node (ref "CF17.2") (pin "15") (pinfunction "15_15") (pintype "passive"))
      (node (ref "CF17.2") (pin "16") (pinfunction "16_16") (pintype "passive"))
      (node (ref "CF18.2") (pin "13") (pinfunction "13_13") (pintype "passive"))
      (node (ref "CF18.2") (pin "14") (pinfunction "14_14") (pintype "passive"))
      (node (ref "CF18.2") (pin "15") (pinfunction "15_15") (pintype "passive"))
      (node (ref "CF18.2") (pin "16") (pinfunction "16_16") (pintype "passive"))
      (node (ref "CF19.2") (pin "13") (pinfunction "13_13") (pintype "passive"))
      (node (ref "CF19.2") (pin "14") (pinfunction "14_14") (pintype "passive"))
      (node (ref "CF19.2") (pin "15") (pinfunction "15_15") (pintype "passive"))
      (node (ref "CF19.2") (pin "16") (pinfunction "16_16") (pintype "passive"))
      (node (ref "CF2.2") (pin "13") (pinfunction "13_13") (pintype "passive"))
      (node (ref "CF2.2") (pin "14") (pinfunction "14_14") (pintype "passive"))
      (node (ref "CF2.2") (pin "15") (pinfunction "15_15") (pintype "passive"))
      (node (ref "CF2.2") (pin "16") (pinfunction "16_16") (pintype "passive"))
      (node (ref "CF3.2") (pin "13") (pinfunction "13_13") (pintype "passive"))
      (node (ref "CF3.2") (pin "14") (pinfunction "14_14") (pintype "passive"))
      (node (ref "CF3.2") (pin "15") (pinfunction "15_15") (pintype "passive"))
      (node (ref "CF3.2") (pin "16") (pinfunction "16_16") (pintype "passive"))
      (node (ref "CF4.2") (pin "13") (pinfunction "13_13") (pintype "passive"))
      (node (ref "CF4.2") (pin "14") (pinfunction "14_14") (pintype "passive"))
      (node (ref "CF4.2") (pin "15") (pinfunction "15_15") (pintype "passive"))
      (node (ref "CF4.2") (pin "16") (pinfunction "16_16") (pintype "passive"))
      (node (ref "CF5.2") (pin "13") (pinfunction "13_13") (pintype "passive"))
      (node (ref "CF5.2") (pin "14") (pinfunction "14_14") (pintype "passive"))
      (node (ref "CF5.2") (pin "15") (pinfunction "15_15") (pintype "passive"))
      (node (ref "CF5.2") (pin "16") (pinfunction "16_16") (pintype "passive"))
      (node (ref "CF6.2") (pin "13") (pinfunction "13_13") (pintype "passive"))
      (node (ref "CF6.2") (pin "14") (pinfunction "14_14") (pintype "passive"))
      (node (ref "CF6.2") (pin "15") (pinfunction "15_15") (pintype "passive"))
      (node (ref "CF6.2") (pin "16") (pinfunction "16_16") (pintype "passive"))
      (node (ref "CF7.2") (pin "13") (pinfunction "13_13") (pintype "passive"))
      (node (ref "CF7.2") (pin "14") (pinfunction "14_14") (pintype "passive"))
      (node (ref "CF7.2") (pin "15") (pinfunction "15_15") (pintype "passive"))
      (node (ref "CF7.2") (pin "16") (pinfunction "16_16") (pintype "passive"))
      (node (ref "CF8.2") (pin "13") (pinfunction "13_13") (pintype "passive"))
      (node (ref "CF8.2") (pin "14") (pinfunction "14_14") (pintype "passive"))
      (node (ref "CF8.2") (pin "15") (pinfunction "15_15") (pintype "passive"))
      (node (ref "CF8.2") (pin "16") (pinfunction "16_16") (pintype "passive"))
      (node (ref "CF9.2") (pin "13") (pinfunction "13_13") (pintype "passive"))
      (node (ref "CF9.2") (pin "14") (pinfunction "14_14") (pintype "passive"))
      (node (ref "CF9.2") (pin "15") (pinfunction "15_15") (pintype "passive"))
      (node (ref "CF9.2") (pin "16") (pinfunction "16_16") (pintype "passive"))
    )
    (net (code "5") (name "unconnected-(CF1.1-Pad1)") (class "Default")
      (node (ref "CF1.1") (pin "1") (pinfunction "1_1") (pintype "passive"))
    )
    (net (code "6") (name "unconnected-(CF1.1-Pad2)") (class "Default")
      (node (ref "CF1.1") (pin "2") (pinfunction "2_2") (pintype "passive"))
    )
    (net (code "7") (name "unconnected-(CF1.1-Pad3)") (class "Default")
      (node (ref "CF1.1") (pin "3") (pinfunction "3_3") (pintype "passive"))
    )
    (net (code "8") (name "unconnected-(CF1.1-Pad4)") (class "Default")
      (node (ref "CF1.1") (pin "4") (pinfunction "4_4") (pintype "passive"))
    )
    (net (code "9") (name "unconnected-(CF1.1-Pad5)") (class "Default")
      (node (ref "CF1.1") (pin "5") (pinfunction "5_5") (pintype "passive"))
    )
    (net (code "10") (name "unconnected-(CF1.1-Pad6)") (class "Default")
      (node (ref "CF1.1") (pin "6") (pinfunction "6_6") (pintype "passive"))
    )
    (net (code "11") (name "unconnected-(CF1.1-Pad7)") (class "Default")
      (node (ref "CF1.1") (pin "7") (pinfunction "7_7") (pintype "passive"))
    )
    (net (code "12") (name "unconnected-(CF1.1-Pad8)") (class "Default")
      (node (ref "CF1.1") (pin "8") (pinfunction "8_8") (pintype "passive"))
    )
    (net (code "13") (name "unconnected-(CF1.1-Pad9)") (class "Default")
      (node (ref "CF1.1") (pin "9") (pinfunction "9_9") (pintype "passive"))
    )
    (net (code "14") (name "unconnected-(CF1.1-Pad10)") (class "Default")
      (node (ref "CF1.1") (pin "10") (pinfunction "10_10") (pintype "passive"))
    )
    (net (code "15") (name "unconnected-(CF1.1-Pad11)") (class "Default")
      (node (ref "CF1.1") (pin "11") (pinfunction "11_11") (pintype "passive"))
    )
    (net (code "16") (name "unconnected-(CF1.1-Pad12)") (class "Default")
      (node (ref "CF1.1") (pin "12") (pinfunction "12_12") (pintype "passive"))
    )
    (net (code "17") (name "unconnected-(CF1.1-Pad13)") (class "Default")
      (node (ref "CF1.1") (pin "13") (pinfunction "13_13") (pintype "passive"))
    )
    (net (code "18") (name "unconnected-(CF1.1-Pad14)") (class "Default")
      (node (ref "CF1.1") (pin "14") (pinfunction "14_14") (pintype "passive"))
    )
    (net (code "19") (name "unconnected-(CF1.1-Pad15)") (class "Default")
      (node (ref "CF1.1") (pin "15") (pinfunction "15_15") (pintype "passive"))
    )
    (net (code "20") (name "unconnected-(CF1.1-Pad16)") (class "Default")
      (node (ref "CF1.1") (pin "16") (pinfunction "16_16") (pintype "passive"))
    )
    (net (code "21") (name "unconnected-(CF1.1-Pad17)") (class "Default")
      (node (ref "CF1.1") (pin "17") (pinfunction "17_17") (pintype "passive"))
    )
    (net (code "22") (name "unconnected-(CF1.1-Pad18)") (class "Default")
      (node (ref "CF1.1") (pin "18") (pinfunction "18_18") (pintype "passive"))
    )
    (net (code "23") (name "unconnected-(CF1.1-Pad19)") (class "Default")
      (node (ref "CF1.1") (pin "19") (pinfunction "19_19") (pintype "passive"))
    )
    (net (code "24") (name "unconnected-(CF1.1-Pad20)") (class "Default")
      (node (ref "CF1.1") (pin "20") (pinfunction "20_20") (pintype "passive"))
    )
    (net (code "25") (name "unconnected-(CF2.1-Pad1)") (class "Default")
      (node (ref "CF2.1") (pin "1") (pinfunction "1_1") (pintype "passive"))
    )
    (net (code "26") (name "unconnected-(CF2.1-Pad2)") (class "Default")
      (node (ref "CF2.1") (pin "2") (pinfunction "2_2") (pintype "passive"))
    )
    (net (code "27") (name "unconnected-(CF2.1-Pad3)") (class "Default")
      (node (ref "CF2.1") (pin "3") (pinfunction "3_3") (pintype "passive"))
    )
    (net (code "28") (name "unconnected-(CF2.1-Pad4)") (class "Default")
      (node (ref "CF2.1") (pin "4") (pinfunction "4_4") (pintype "passive"))
    )
    (net (code "29") (name "unconnected-(CF2.1-Pad5)") (class "Default")
      (node (ref "CF2.1") (pin "5") (pinfunction "5_5") (pintype "passive"))
    )
    (net (code "30") (name "unconnected-(CF2.1-Pad6)") (class "Default")
      (node (ref "CF2.1") (pin "6") (pinfunction "6_6") (pintype "passive"))
    )
    (net (code "31") (name "unconnected-(CF2.1-Pad7)") (class "Default")
      (node (ref "CF2.1") (pin "7") (pinfunction "7_7") (pintype "passive"))
    )
    (net (code "32") (name "unconnected-(CF2.1-Pad8)") (class "Default")
      (node (ref "CF2.1") (pin "8") (pinfunction "8_8") (pintype "passive"))
    )
    (net (code "33") (name "unconnected-(CF2.1-Pad9)") (class "Default")
      (node (ref "CF2.1") (pin "9") (pinfunction "9_9") (pintype "passive"))
    )
    (net (code "34") (name "unconnected-(CF2.1-Pad10)") (class "Default")
      (node (ref "CF2.1") (pin "10") (pinfunction "10_10") (pintype "passive"))
    )
    (net (code "35") (name "unconnected-(CF2.1-Pad11)") (class "Default")
      (node (ref "CF2.1") (pin "11") (pinfunction "11_11") (pintype "passive"))
    )
    (net (code "36") (name "unconnected-(CF2.1-Pad12)") (class "Default")
      (node (ref "CF2.1") (pin "12") (pinfunction "12_12") (pintype "passive"))
    )
    (net (code "37") (name "unconnected-(CF2.1-Pad13)") (class "Default")
      (node (ref "CF2.1") (pin "13") (pinfunction "13_13") (pintype "passive"))
    )
    (net (code "38") (name "unconnected-(CF2.1-Pad14)") (class "Default")
      (node (ref "CF2.1") (pin "14") (pinfunction "14_14") (pintype "passive"))
    )
    (net (code "39") (name "unconnected-(CF2.1-Pad15)") (class "Default")
      (node (ref "CF2.1") (pin "15") (pinfunction "15_15") (pintype "passive"))
    )
    (net (code "40") (name "unconnected-(CF2.1-Pad16)") (class "Default")
      (node (ref "CF2.1") (pin "16") (pinfunction "16_16") (pintype "passive"))
    )
    (net (code "41") (name "unconnected-(CF2.1-Pad17)") (class "Default")
      (node (ref "CF2.1") (pin "17") (pinfunction "17_17") (pintype "passive"))
    )
    (net (code "42") (name "unconnected-(CF2.1-Pad18)") (class "Default")
      (node (ref "CF2.1") (pin "18") (pinfunction "18_18") (pintype "passive"))
    )
    (net (code "43") (name "unconnected-(CF2.1-Pad19)") (class "Default")
      (node (ref "CF2.1") (pin "19") (pinfunction "19_19") (pintype "passive"))
    )
    (net (code "44") (name "unconnected-(CF2.1-Pad20)") (class "Default")
      (node (ref "CF2.1") (pin "20") (pinfunction "20_20") (pintype "passive"))
    )
    (net (code "45") (name "unconnected-(CF2.2-Pad17)") (class "Default")
      (node (ref "CF2.2") (pin "17") (pinfunction "17_17") (pintype "passive"))
    )
    (net (code "46") (name "unconnected-(CF2.2-Pad18)") (class "Default")
      (node (ref "CF2.2") (pin "18") (pinfunction "18_18") (pintype "passive"))
    )
    (net (code "47") (name "unconnected-(CF2.2-Pad19)") (class "Default")
      (node (ref "CF2.2") (pin "19") (pinfunction "19_19") (pintype "passive"))
    )
    (net (code "48") (name "unconnected-(CF2.2-Pad20)") (class "Default")
      (node (ref "CF2.2") (pin "20") (pinfunction "20_20") (pintype "passive"))
    )
    (net (code "49") (name "unconnected-(CF2.2-Pad21)") (class "Default")
      (node (ref "CF2.2") (pin "21") (pinfunction "21_21") (pintype "passive"))
    )
    (net (code "50") (name "unconnected-(CF2.2-Pad22)") (class "Default")
      (node (ref "CF2.2") (pin "22") (pinfunction "22_22") (pintype "passive"))
    )
    (net (code "51") (name "unconnected-(CF2.2-Pad23)") (class "Default")
      (node (ref "CF2.2") (pin "23") (pinfunction "23_23") (pintype "passive"))
    )
    (net (code "52") (name "unconnected-(CF2.2-Pad24)") (class "Default")
      (node (ref "CF2.2") (pin "24") (pinfunction "24_24") (pintype "passive"))
    )
    (net (code "53") (name "unconnected-(CF2.2-Pad25)") (class "Default")
      (node (ref "CF2.2") (pin "25") (pinfunction "25_25") (pintype "passive"))
    )
    (net (code "54") (name "unconnected-(CF2.2-Pad26)") (class "Default")
      (node (ref "CF2.2") (pin "26") (pinfunction "26_26") (pintype "passive"))
    )
    (net (code "55") (name "unconnected-(CF2.2-Pad27)") (class "Default")
      (node (ref "CF2.2") (pin "27") (pinfunction "27_27") (pintype "passive"))
    )
    (net (code "56") (name "unconnected-(CF2.2-Pad28)") (class "Default")
      (node (ref "CF2.2") (pin "28") (pinfunction "28_28") (pintype "passive"))
    )
    (net (code "57") (name "unconnected-(CF2.2-Pad29)") (class "Default")
      (node (ref "CF2.2") (pin "29") (pinfunction "29_29") (pintype "passive"))
    )
    (net (code "58") (name "unconnected-(CF2.2-Pad30)") (class "Default")
      (node (ref "CF2.2") (pin "30") (pinfunction "30_30") (pintype "passive"))
    )
    (net (code "59") (name "unconnected-(CF2.2-Pad31)") (class "Default")
      (node (ref "CF2.2") (pin "31") (pinfunction "31_31") (pintype "passive"))
    )
    (net (code "60") (name "unconnected-(CF2.2-Pad32)") (class "Default")
      (node (ref "CF2.2") (pin "32") (pinfunction "32_32") (pintype "passive"))
    )
    (net (code "61") (name "unconnected-(CF2.2-Pad33)") (class "Default")
      (node (ref "CF2.2") (pin "33") (pinfunction "33_33") (pintype "passive"))
    )
    (net (code "62") (name "unconnected-(CF2.2-Pad34)") (class "Default")
      (node (ref "CF2.2") (pin "34") (pinfunction "34_34") (pintype "passive"))
    )
    (net (code "63") (name "unconnected-(CF2.2-Pad35)") (class "Default")
      (node (ref "CF2.2") (pin "35") (pinfunction "35_35") (pintype "passive"))
    )
    (net (code "64") (name "unconnected-(CF2.2-Pad36)") (class "Default")
      (node (ref "CF2.2") (pin "36") (pinfunction "36_36") (pintype "passive"))
    )
    (net (code "65") (name "unconnected-(CF2.2-Pad37)") (class "Default")
      (node (ref "CF2.2") (pin "37") (pinfunction "37_37") (pintype "passive"))
    )
    (net (code "66") (name "unconnected-(CF2.2-Pad38)") (class "Default")
      (node (ref "CF2.2") (pin "38") (pinfunction "38_38") (pintype "passive"))
    )
    (net (code "67") (name "unconnected-(CF2.2-Pad39)") (class "Default")
      (node (ref "CF2.2") (pin "39") (pinfunction "39_39") (pintype "passive"))
    )
    (net (code "68") (name "unconnected-(CF2.2-Pad40)") (class "Default")
      (node (ref "CF2.2") (pin "40") (pinfunction "40_40") (pintype "passive"))
    )
    (net (code "69") (name "unconnected-(CF3.1-Pad1)") (class "Default")
      (node (ref "CF3.1") (pin "1") (pinfunction "1_1") (pintype "passive"))
    )
    (net (code "70") (name "unconnected-(CF3.1-Pad2)") (class "Default")
      (node (ref "CF3.1") (pin "2") (pinfunction "2_2") (pintype "passive"))
    )
    (net (code "71") (name "unconnected-(CF3.1-Pad3)") (class "Default")
      (node (ref "CF3.1") (pin "3") (pinfunction "3_3") (pintype "passive"))
    )
    (net (code "72") (name "unconnected-(CF3.1-Pad4)") (class "Default")
      (node (ref "CF3.1") (pin "4") (pinfunction "4_4") (pintype "passive"))
    )
    (net (code "73") (name "unconnected-(CF3.1-Pad5)") (class "Default")
      (node (ref "CF3.1") (pin "5") (pinfunction "5_5") (pintype "passive"))
    )
    (net (code "74") (name "unconnected-(CF3.1-Pad6)") (class "Default")
      (node (ref "CF3.1") (pin "6") (pinfunction "6_6") (pintype "passive"))
    )
    (net (code "75") (name "unconnected-(CF3.1-Pad7)") (class "Default")
      (node (ref "CF3.1") (pin "7") (pinfunction "7_7") (pintype "passive"))
    )
    (net (code "76") (name "unconnected-(CF3.1-Pad8)") (class "Default")
      (node (ref "CF3.1") (pin "8") (pinfunction "8_8") (pintype "passive"))
    )
    (net (code "77") (name "unconnected-(CF3.1-Pad9)") (class "Default")
      (node (ref "CF3.1") (pin "9") (pinfunction "9_9") (pintype "passive"))
    )
    (net (code "78") (name "unconnected-(CF3.1-Pad10)") (class "Default")
      (node (ref "CF3.1") (pin "10") (pinfunction "10_10") (pintype "passive"))
    )
    (net (code "79") (name "unconnected-(CF3.1-Pad11)") (class "Default")
      (node (ref "CF3.1") (pin "11") (pinfunction "11_11") (pintype "passive"))
    )
    (net (code "80") (name "unconnected-(CF3.1-Pad12)") (class "Default")
      (node (ref "CF3.1") (pin "12") (pinfunction "12_12") (pintype "passive"))
    )
    (net (code "81") (name "unconnected-(CF3.1-Pad13)") (class "Default")
      (node (ref "CF3.1") (pin "13") (pinfunction "13_13") (pintype "passive"))
    )
    (net (code "82") (name "unconnected-(CF3.1-Pad14)") (class "Default")
      (node (ref "CF3.1") (pin "14") (pinfunction "14_14") (pintype "passive"))
    )
    (net (code "83") (name "unconnected-(CF3.1-Pad15)") (class "Default")
      (node (ref "CF3.1") (pin "15") (pinfunction "15_15") (pintype "passive"))
    )
    (net (code "84") (name "unconnected-(CF3.1-Pad16)") (class "Default")
      (node (ref "CF3.1") (pin "16") (pinfunction "16_16") (pintype "passive"))
    )
    (net (code "85") (name "unconnected-(CF3.1-Pad17)") (class "Default")
      (node (ref "CF3.1") (pin "17") (pinfunction "17_17") (pintype "passive"))
    )
    (net (code "86") (name "unconnected-(CF3.1-Pad18)") (class "Default")
      (node (ref "CF3.1") (pin "18") (pinfunction "18_18") (pintype "passive"))
    )
    (net (code "87") (name "unconnected-(CF3.1-Pad19)") (class "Default")
      (node (ref "CF3.1") (pin "19") (pinfunction "19_19") (pintype "passive"))
    )
    (net (code "88") (name "unconnected-(CF3.1-Pad20)") (class "Default")
      (node (ref "CF3.1") (pin "20") (pinfunction "20_20") (pintype "passive"))
    )
    (net (code "89") (name "unconnected-(CF3.2-Pad17)") (class "Default")
      (node (ref "CF3.2") (pin "17") (pinfunction "17_17") (pintype "passive"))
    )
    (net (code "90") (name "unconnected-(CF3.2-Pad18)") (class "Default")
      (node (ref "CF3.2") (pin "18") (pinfunction "18_18") (pintype "passive"))
    )
    (net (code "91") (name "unconnected-(CF3.2-Pad19)") (class "Default")
      (node (ref "CF3.2") (pin "19") (pinfunction "19_19") (pintype "passive"))
    )
    (net (code "92") (name "unconnected-(CF3.2-Pad20)") (class "Default")
      (node (ref "CF3.2") (pin "20") (pinfunction "20_20") (pintype "passive"))
    )
    (net (code "93") (name "unconnected-(CF3.2-Pad21)") (class "Default")
      (node (ref "CF3.2") (pin "21") (pinfunction "21_21") (pintype "passive"))
    )
    (net (code "94") (name "unconnected-(CF3.2-Pad22)") (class "Default")
      (node (ref "CF3.2") (pin "22") (pinfunction "22_22") (pintype "passive"))
    )
    (net (code "95") (name "unconnected-(CF3.2-Pad23)") (class "Default")
      (node (ref "CF3.2") (pin "23") (pinfunction "23_23") (pintype "passive"))
    )
    (net (code "96") (name "unconnected-(CF3.2-Pad24)") (class "Default")
      (node (ref "CF3.2") (pin "24") (pinfunction "24_24") (pintype "passive"))
    )
    (net (code "97") (name "unconnected-(CF3.2-Pad25)") (class "Default")
      (node (ref "CF3.2") (pin "25") (pinfunction "25_25") (pintype "passive"))
    )
    (net (code "98") (name "unconnected-(CF3.2-Pad26)") (class "Default")
      (node (ref "CF3.2") (pin "26") (pinfunction "26_26") (pintype "passive"))
    )
    (net (code "99") (name "unconnected-(CF3.2-Pad27)") (class "Default")
      (node (ref "CF3.2") (pin "27") (pinfunction "27_27") (pintype "passive"))
    )
    (net (code "100") (name "unconnected-(CF3.2-Pad28)") (class "Default")
      (node (ref "CF3.2") (pin "28") (pinfunction "28_28") (pintype "passive"))
    )
    (net (code "101") (name "unconnected-(CF3.2-Pad29)") (class "Default")
      (node (ref "CF3.2") (pin "29") (pinfunction "29_29") (pintype "passive"))
    )
    (net (code "102") (name "unconnected-(CF3.2-Pad30)") (class "Default")
      (node (ref "CF3.2") (pin "30") (pinfunction "30_30") (pintype "passive"))
    )
    (net (code "103") (name "unconnected-(CF3.2-Pad31)") (class "Default")
      (node (ref "CF3.2") (pin "31") (pinfunction "31_31") (pintype "passive"))
    )
    (net (code "104") (name "unconnected-(CF3.2-Pad32)") (class "Default")
      (node (ref "CF3.2") (pin "32") (pinfunction "32_32") (pintype "passive"))
    )
    (net (code "105") (name "unconnected-(CF3.2-Pad33)") (class "Default")
      (node (ref "CF3.2") (pin "33") (pinfunction "33_33") (pintype "passive"))
    )
    (net (code "106") (name "unconnected-(CF3.2-Pad34)") (class "Default")
      (node (ref "CF3.2") (pin "34") (pinfunction "34_34") (pintype "passive"))
    )
    (net (code "107") (name "unconnected-(CF3.2-Pad35)") (class "Default")
      (node (ref "CF3.2") (pin "35") (pinfunction "35_35") (pintype "passive"))
    )
    (net (code "108") (name "unconnected-(CF3.2-Pad36)") (class "Default")
      (node (ref "CF3.2") (pin "36") (pinfunction "36_36") (pintype "passive"))
    )
    (net (code "109") (name "unconnected-(CF3.2-Pad37)") (class "Default")
      (node (ref "CF3.2") (pin "37") (pinfunction "37_37") (pintype "passive"))
    )
    (net (code "110") (name "unconnected-(CF3.2-Pad38)") (class "Default")
      (node (ref "CF3.2") (pin "38") (pinfunction "38_38") (pintype "passive"))
    )
    (net (code "111") (name "unconnected-(CF3.2-Pad39)") (class "Default")
      (node (ref "CF3.2") (pin "39") (pinfunction "39_39") (pintype "passive"))
    )
    (net (code "112") (name "unconnected-(CF3.2-Pad40)") (class "Default")
      (node (ref "CF3.2") (pin "40") (pinfunction "40_40") (pintype "passive"))
    )
    (net (code "113") (name "unconnected-(CF4.1-Pad1)") (class "Default")
      (node (ref "CF4.1") (pin "1") (pinfunction "1_1") (pintype "passive"))
    )
    (net (code "114") (name "unconnected-(CF4.1-Pad2)") (class "Default")
      (node (ref "CF4.1") (pin "2") (pinfunction "2_2") (pintype "passive"))
    )
    (net (code "115") (name "unconnected-(CF4.1-Pad3)") (class "Default")
      (node (ref "CF4.1") (pin "3") (pinfunction "3_3") (pintype "passive"))
    )
    (net (code "116") (name "unconnected-(CF4.1-Pad4)") (class "Default")
      (node (ref "CF4.1") (pin "4") (pinfunction "4_4") (pintype "passive"))
    )
    (net (code "117") (name "unconnected-(CF4.1-Pad5)") (class "Default")
      (node (ref "CF4.1") (pin "5") (pinfunction "5_5") (pintype "passive"))
    )
    (net (code "118") (name "unconnected-(CF4.1-Pad6)") (class "Default")
      (node (ref "CF4.1") (pin "6") (pinfunction "6_6") (pintype "passive"))
    )
    (net (code "119") (name "unconnected-(CF4.1-Pad7)") (class "Default")
      (node (ref "CF4.1") (pin "7") (pinfunction "7_7") (pintype "passive"))
    )
    (net (code "120") (name "unconnected-(CF4.1-Pad8)") (class "Default")
      (node (ref "CF4.1") (pin "8") (pinfunction "8_8") (pintype "passive"))
    )
    (net (code "121") (name "unconnected-(CF4.1-Pad9)") (class "Default")
      (node (ref "CF4.1") (pin "9") (pinfunction "9_9") (pintype "passive"))
    )
    (net (code "122") (name "unconnected-(CF4.1-Pad10)") (class "Default")
      (node (ref "CF4.1") (pin "10") (pinfunction "10_10") (pintype "passive"))
    )
    (net (code "123") (name "unconnected-(CF4.1-Pad11)") (class "Default")
      (node (ref "CF4.1") (pin "11") (pinfunction "11_11") (pintype "passive"))
    )
    (net (code "124") (name "unconnected-(CF4.1-Pad12)") (class "Default")
      (node (ref "CF4.1") (pin "12") (pinfunction "12_12") (pintype "passive"))
    )
    (net (code "125") (name "unconnected-(CF4.1-Pad13)") (class "Default")
      (node (ref "CF4.1") (pin "13") (pinfunction "13_13") (pintype "passive"))
    )
    (net (code "126") (name "unconnected-(CF4.1-Pad14)") (class "Default")
      (node (ref "CF4.1") (pin "14") (pinfunction "14_14") (pintype "passive"))
    )
    (net (code "127") (name "unconnected-(CF4.1-Pad15)") (class "Default")
      (node (ref "CF4.1") (pin "15") (pinfunction "15_15") (pintype "passive"))
    )
    (net (code "128") (name "unconnected-(CF4.1-Pad16)") (class "Default")
      (node (ref "CF4.1") (pin "16") (pinfunction "16_16") (pintype "passive"))
    )
    (net (code "129") (name "unconnected-(CF4.1-Pad17)") (class "Default")
      (node (ref "CF4.1") (pin "17") (pinfunction "17_17") (pintype "passive"))
    )
    (net (code "130") (name "unconnected-(CF4.1-Pad18)") (class "Default")
      (node (ref "CF4.1") (pin "18") (pinfunction "18_18") (pintype "passive"))
    )
    (net (code "131") (name "unconnected-(CF4.1-Pad19)") (class "Default")
      (node (ref "CF4.1") (pin "19") (pinfunction "19_19") (pintype "passive"))
    )
    (net (code "132") (name "unconnected-(CF4.1-Pad20)") (class "Default")
      (node (ref "CF4.1") (pin "20") (pinfunction "20_20") (pintype "passive"))
    )
    (net (code "133") (name "unconnected-(CF4.2-Pad17)") (class "Default")
      (node (ref "CF4.2") (pin "17") (pinfunction "17_17") (pintype "passive"))
    )
    (net (code "134") (name "unconnected-(CF4.2-Pad18)") (class "Default")
      (node (ref "CF4.2") (pin "18") (pinfunction "18_18") (pintype "passive"))
    )
    (net (code "135") (name "unconnected-(CF4.2-Pad19)") (class "Default")
      (node (ref "CF4.2") (pin "19") (pinfunction "19_19") (pintype "passive"))
    )
    (net (code "136") (name "unconnected-(CF4.2-Pad20)") (class "Default")
      (node (ref "CF4.2") (pin "20") (pinfunction "20_20") (pintype "passive"))
    )
    (net (code "137") (name "unconnected-(CF4.2-Pad21)") (class "Default")
      (node (ref "CF4.2") (pin "21") (pinfunction "21_21") (pintype "passive"))
    )
    (net (code "138") (name "unconnected-(CF4.2-Pad22)") (class "Default")
      (node (ref "CF4.2") (pin "22") (pinfunction "22_22") (pintype "passive"))
    )
    (net (code "139") (name "unconnected-(CF4.2-Pad23)") (class "Default")
      (node (ref "CF4.2") (pin "23") (pinfunction "23_23") (pintype "passive"))
    )
    (net (code "140") (name "unconnected-(CF4.2-Pad24)") (class "Default")
      (node (ref "CF4.2") (pin "24") (pinfunction "24_24") (pintype "passive"))
    )
    (net (code "141") (name "unconnected-(CF4.2-Pad25)") (class "Default")
      (node (ref "CF4.2") (pin "25") (pinfunction "25_25") (pintype "passive"))
    )
    (net (code "142") (name "unconnected-(CF4.2-Pad26)") (class "Default")
      (node (ref "CF4.2") (pin "26") (pinfunction "26_26") (pintype "passive"))
    )
    (net (code "143") (name "unconnected-(CF4.2-Pad27)") (class "Default")
      (node (ref "CF4.2") (pin "27") (pinfunction "27_27") (pintype "passive"))
    )
    (net (code "144") (name "unconnected-(CF4.2-Pad28)") (class "Default")
      (node (ref "CF4.2") (pin "28") (pinfunction "28_28") (pintype "passive"))
    )
    (net (code "145") (name "unconnected-(CF4.2-Pad29)") (class "Default")
      (node (ref "CF4.2") (pin "29") (pinfunction "29_29") (pintype "passive"))
    )
    (net (code "146") (name "unconnected-(CF4.2-Pad30)") (class "Default")
      (node (ref "CF4.2") (pin "30") (pinfunction "30_30") (pintype "passive"))
    )
    (net (code "147") (name "unconnected-(CF4.2-Pad31)") (class "Default")
      (node (ref "CF4.2") (pin "31") (pinfunction "31_31") (pintype "passive"))
    )
    (net (code "148") (name "unconnected-(CF4.2-Pad32)") (class "Default")
      (node (ref "CF4.2") (pin "32") (pinfunction "32_32") (pintype "passive"))
    )
    (net (code "149") (name "unconnected-(CF4.2-Pad33)") (class "Default")
      (node (ref "CF4.2") (pin "33") (pinfunction "33_33") (pintype "passive"))
    )
    (net (code "150") (name "unconnected-(CF4.2-Pad34)") (class "Default")
      (node (ref "CF4.2") (pin "34") (pinfunction "34_34") (pintype "passive"))
    )
    (net (code "151") (name "unconnected-(CF4.2-Pad35)") (class "Default")
      (node (ref "CF4.2") (pin "35") (pinfunction "35_35") (pintype "passive"))
    )
    (net (code "152") (name "unconnected-(CF4.2-Pad36)") (class "Default")
      (node (ref "CF4.2") (pin "36") (pinfunction "36_36") (pintype "passive"))
    )
    (net (code "153") (name "unconnected-(CF4.2-Pad37)") (class "Default")
      (node (ref "CF4.2") (pin "37") (pinfunction "37_37") (pintype "passive"))
    )
    (net (code "154") (name "unconnected-(CF4.2-Pad38)") (class "Default")
      (node (ref "CF4.2") (pin "38") (pinfunction "38_38") (pintype "passive"))
    )
    (net (code "155") (name "unconnected-(CF4.2-Pad39)") (class "Default")
      (node (ref "CF4.2") (pin "39") (pinfunction "39_39") (pintype "passive"))
    )
    (net (code "156") (name "unconnected-(CF4.2-Pad40)") (class "Default")
      (node (ref "CF4.2") (pin "40") (pinfunction "40_40") (pintype "passive"))
    )
    (net (code "157") (name "unconnected-(CF5.1-Pad1)") (class "Default")
      (node (ref "CF5.1") (pin "1") (pinfunction "1_1") (pintype "passive"))
    )
    (net (code "158") (name "unconnected-(CF5.1-Pad2)") (class "Default")
      (node (ref "CF5.1") (pin "2") (pinfunction "2_2") (pintype "passive"))
    )
    (net (code "159") (name "unconnected-(CF5.1-Pad3)") (class "Default")
      (node (ref "CF5.1") (pin "3") (pinfunction "3_3") (pintype "passive"))
    )
    (net (code "160") (name "unconnected-(CF5.1-Pad4)") (class "Default")
      (node (ref "CF5.1") (pin "4") (pinfunction "4_4") (pintype "passive"))
    )
    (net (code "161") (name "unconnected-(CF5.1-Pad5)") (class "Default")
      (node (ref "CF5.1") (pin "5") (pinfunction "5_5") (pintype "passive"))
    )
    (net (code "162") (name "unconnected-(CF5.1-Pad6)") (class "Default")
      (node (ref "CF5.1") (pin "6") (pinfunction "6_6") (pintype "passive"))
    )
    (net (code "163") (name "unconnected-(CF5.1-Pad7)") (class "Default")
      (node (ref "CF5.1") (pin "7") (pinfunction "7_7") (pintype "passive"))
    )
    (net (code "164") (name "unconnected-(CF5.1-Pad8)") (class "Default")
      (node (ref "CF5.1") (pin "8") (pinfunction "8_8") (pintype "passive"))
    )
    (net (code "165") (name "unconnected-(CF5.1-Pad9)") (class "Default")
      (node (ref "CF5.1") (pin "9") (pinfunction "9_9") (pintype "passive"))
    )
    (net (code "166") (name "unconnected-(CF5.1-Pad10)") (class "Default")
      (node (ref "CF5.1") (pin "10") (pinfunction "10_10") (pintype "passive"))
    )
    (net (code "167") (name "unconnected-(CF5.1-Pad11)") (class "Default")
      (node (ref "CF5.1") (pin "11") (pinfunction "11_11") (pintype "passive"))
    )
    (net (code "168") (name "unconnected-(CF5.1-Pad12)") (class "Default")
      (node (ref "CF5.1") (pin "12") (pinfunction "12_12") (pintype "passive"))
    )
    (net (code "169") (name "unconnected-(CF5.1-Pad13)") (class "Default")
      (node (ref "CF5.1") (pin "13") (pinfunction "13_13") (pintype "passive"))
    )
    (net (code "170") (name "unconnected-(CF5.1-Pad14)") (class "Default")
      (node (ref "CF5.1") (pin "14") (pinfunction "14_14") (pintype "passive"))
    )
    (net (code "171") (name "unconnected-(CF5.1-Pad15)") (class "Default")
      (node (ref "CF5.1") (pin "15") (pinfunction "15_15") (pintype "passive"))
    )
    (net (code "172") (name "unconnected-(CF5.1-Pad16)") (class "Default")
      (node (ref "CF5.1") (pin "16") (pinfunction "16_16") (pintype "passive"))
    )
    (net (code "173") (name "unconnected-(CF5.1-Pad17)") (class "Default")
      (node (ref "CF5.1") (pin "17") (pinfunction "17_17") (pintype "passive"))
    )
    (net (code "174") (name "unconnected-(CF5.1-Pad18)") (class "Default")
      (node (ref "CF5.1") (pin "18") (pinfunction "18_18") (pintype "passive"))
    )
    (net (code "175") (name "unconnected-(CF5.1-Pad19)") (class "Default")
      (node (ref "CF5.1") (pin "19") (pinfunction "19_19") (pintype "passive"))
    )
    (net (code "176") (name "unconnected-(CF5.1-Pad20)") (class "Default")
      (node (ref "CF5.1") (pin "20") (pinfunction "20_20") (pintype "passive"))
    )
    (net (code "177") (name "unconnected-(CF5.2-Pad17)") (class "Default")
      (node (ref "CF5.2") (pin "17") (pinfunction "17_17") (pintype "passive"))
    )
    (net (code "178") (name "unconnected-(CF5.2-Pad18)") (class "Default")
      (node (ref "CF5.2") (pin "18") (pinfunction "18_18") (pintype "passive"))
    )
    (net (code "179") (name "unconnected-(CF5.2-Pad19)") (class "Default")
      (node (ref "CF5.2") (pin "19") (pinfunction "19_19") (pintype "passive"))
    )
    (net (code "180") (name "unconnected-(CF5.2-Pad20)") (class "Default")
      (node (ref "CF5.2") (pin "20") (pinfunction "20_20") (pintype "passive"))
    )
    (net (code "181") (name "unconnected-(CF5.2-Pad21)") (class "Default")
      (node (ref "CF5.2") (pin "21") (pinfunction "21_21") (pintype "passive"))
    )
    (net (code "182") (name "unconnected-(CF5.2-Pad22)") (class "Default")
      (node (ref "CF5.2") (pin "22") (pinfunction "22_22") (pintype "passive"))
    )
    (net (code "183") (name "unconnected-(CF5.2-Pad23)") (class "Default")
      (node (ref "CF5.2") (pin "23") (pinfunction "23_23") (pintype "passive"))
    )
    (net (code "184") (name "unconnected-(CF5.2-Pad24)") (class "Default")
      (node (ref "CF5.2") (pin "24") (pinfunction "24_24") (pintype "passive"))
    )
    (net (code "185") (name "unconnected-(CF5.2-Pad25)") (class "Default")
      (node (ref "CF5.2") (pin "25") (pinfunction "25_25") (pintype "passive"))
    )
    (net (code "186") (name "unconnected-(CF5.2-Pad26)") (class "Default")
      (node (ref "CF5.2") (pin "26") (pinfunction "26_26") (pintype "passive"))
    )
    (net (code "187") (name "unconnected-(CF5.2-Pad27)") (class "Default")
      (node (ref "CF5.2") (pin "27") (pinfunction "27_27") (pintype "passive"))
    )
    (net (code "188") (name "unconnected-(CF5.2-Pad28)") (class "Default")
      (node (ref "CF5.2") (pin "28") (pinfunction "28_28") (pintype "passive"))
    )
    (net (code "189") (name "unconnected-(CF5.2-Pad29)") (class "Default")
      (node (ref "CF5.2") (pin "29") (pinfunction "29_29") (pintype "passive"))
    )
    (net (code "190") (name "unconnected-(CF5.2-Pad30)") (class "Default")
      (node (ref "CF5.2") (pin "30") (pinfunction "30_30") (pintype "passive"))
    )
    (net (code "191") (name "unconnected-(CF5.2-Pad31)") (class "Default")
      (node (ref "CF5.2") (pin "31") (pinfunction "31_31") (pintype "passive"))
    )
    (net (code "192") (name "unconnected-(CF5.2-Pad32)") (class "Default")
      (node (ref "CF5.2") (pin "32") (pinfunction "32_32") (pintype "passive"))
    )
    (net (code "193") (name "unconnected-(CF5.2-Pad33)") (class "Default")
      (node (ref "CF5.2") (pin "33") (pinfunction "33_33") (pintype "passive"))
    )
    (net (code "194") (name "unconnected-(CF5.2-Pad34)") (class "Default")
      (node (ref "CF5.2") (pin "34") (pinfunction "34_34") (pintype "passive"))
    )
    (net (code "195") (name "unconnected-(CF5.2-Pad35)") (class "Default")
      (node (ref "CF5.2") (pin "35") (pinfunction "35_35") (pintype "passive"))
    )
    (net (code "196") (name "unconnected-(CF5.2-Pad36)") (class "Default")
      (node (ref "CF5.2") (pin "36") (pinfunction "36_36") (pintype "passive"))
    )
    (net (code "197") (name "unconnected-(CF5.2-Pad37)") (class "Default")
      (node (ref "CF5.2") (pin "37") (pinfunction "37_37") (pintype "passive"))
    )
    (net (code "198") (name "unconnected-(CF5.2-Pad38)") (class "Default")
      (node (ref "CF5.2") (pin "38") (pinfunction "38_38") (pintype "passive"))
    )
    (net (code "199") (name "unconnected-(CF5.2-Pad39)") (class "Default")
      (node (ref "CF5.2") (pin "39") (pinfunction "39_39") (pintype "passive"))
    )
    (net (code "200") (name "unconnected-(CF5.2-Pad40)") (class "Default")
      (node (ref "CF5.2") (pin "40") (pinfunction "40_40") (pintype "passive"))
    )
    (net (code "201") (name "unconnected-(CF6.1-Pad1)") (class "Default")
      (node (ref "CF6.1") (pin "1") (pinfunction "1_1") (pintype "passive"))
    )
    (net (code "202") (name "unconnected-(CF6.1-Pad2)") (class "Default")
      (node (ref "CF6.1") (pin "2") (pinfunction "2_2") (pintype "passive"))
    )
    (net (code "203") (name "unconnected-(CF6.1-Pad3)") (class "Default")
      (node (ref "CF6.1") (pin "3") (pinfunction "3_3") (pintype "passive"))
    )
    (net (code "204") (name "unconnected-(CF6.1-Pad4)") (class "Default")
      (node (ref "CF6.1") (pin "4") (pinfunction "4_4") (pintype "passive"))
    )
    (net (code "205") (name "unconnected-(CF6.1-Pad5)") (class "Default")
      (node (ref "CF6.1") (pin "5") (pinfunction "5_5") (pintype "passive"))
    )
    (net (code "206") (name "unconnected-(CF6.1-Pad6)") (class "Default")
      (node (ref "CF6.1") (pin "6") (pinfunction "6_6") (pintype "passive"))
    )
    (net (code "207") (name "unconnected-(CF6.1-Pad7)") (class "Default")
      (node (ref "CF6.1") (pin "7") (pinfunction "7_7") (pintype "passive"))
    )
    (net (code "208") (name "unconnected-(CF6.1-Pad8)") (class "Default")
      (node (ref "CF6.1") (pin "8") (pinfunction "8_8") (pintype "passive"))
    )
    (net (code "209") (name "unconnected-(CF6.1-Pad9)") (class "Default")
      (node (ref "CF6.1") (pin "9") (pinfunction "9_9") (pintype "passive"))
    )
    (net (code "210") (name "unconnected-(CF6.1-Pad10)") (class "Default")
      (node (ref "CF6.1") (pin "10") (pinfunction "10_10") (pintype "passive"))
    )
    (net (code "211") (name "unconnected-(CF6.1-Pad11)") (class "Default")
      (node (ref "CF6.1") (pin "11") (pinfunction "11_11") (pintype "passive"))
    )
    (net (code "212") (name "unconnected-(CF6.1-Pad12)") (class "Default")
      (node (ref "CF6.1") (pin "12") (pinfunction "12_12") (pintype "passive"))
    )
    (net (code "213") (name "unconnected-(CF6.1-Pad13)") (class "Default")
      (node (ref "CF6.1") (pin "13") (pinfunction "13_13") (pintype "passive"))
    )
    (net (code "214") (name "unconnected-(CF6.1-Pad14)") (class "Default")
      (node (ref "CF6.1") (pin "14") (pinfunction "14_14") (pintype "passive"))
    )
    (net (code "215") (name "unconnected-(CF6.1-Pad15)") (class "Default")
      (node (ref "CF6.1") (pin "15") (pinfunction "15_15") (pintype "passive"))
    )
    (net (code "216") (name "unconnected-(CF6.1-Pad16)") (class "Default")
      (node (ref "CF6.1") (pin "16") (pinfunction "16_16") (pintype "passive"))
    )
    (net (code "217") (name "unconnected-(CF6.1-Pad17)") (class "Default")
      (node (ref "CF6.1") (pin "17") (pinfunction "17_17") (pintype "passive"))
    )
    (net (code "218") (name "unconnected-(CF6.1-Pad18)") (class "Default")
      (node (ref "CF6.1") (pin "18") (pinfunction "18_18") (pintype "passive"))
    )
    (net (code "219") (name "unconnected-(CF6.1-Pad19)") (class "Default")
      (node (ref "CF6.1") (pin "19") (pinfunction "19_19") (pintype "passive"))
    )
    (net (code "220") (name "unconnected-(CF6.1-Pad20)") (class "Default")
      (node (ref "CF6.1") (pin "20") (pinfunction "20_20") (pintype "passive"))
    )
    (net (code "221") (name "unconnected-(CF6.2-Pad17)") (class "Default")
      (node (ref "CF6.2") (pin "17") (pinfunction "17_17") (pintype "passive"))
    )
    (net (code "222") (name "unconnected-(CF6.2-Pad18)") (class "Default")
      (node (ref "CF6.2") (pin "18") (pinfunction "18_18") (pintype "passive"))
    )
    (net (code "223") (name "unconnected-(CF6.2-Pad19)") (class "Default")
      (node (ref "CF6.2") (pin "19") (pinfunction "19_19") (pintype "passive"))
    )
    (net (code "224") (name "unconnected-(CF6.2-Pad20)") (class "Default")
      (node (ref "CF6.2") (pin "20") (pinfunction "20_20") (pintype "passive"))
    )
    (net (code "225") (name "unconnected-(CF6.2-Pad21)") (class "Default")
      (node (ref "CF6.2") (pin "21") (pinfunction "21_21") (pintype "passive"))
    )
    (net (code "226") (name "unconnected-(CF6.2-Pad22)") (class "Default")
      (node (ref "CF6.2") (pin "22") (pinfunction "22_22") (pintype "passive"))
    )
    (net (code "227") (name "unconnected-(CF6.2-Pad23)") (class "Default")
      (node (ref "CF6.2") (pin "23") (pinfunction "23_23") (pintype "passive"))
    )
    (net (code "228") (name "unconnected-(CF6.2-Pad24)") (class "Default")
      (node (ref "CF6.2") (pin "24") (pinfunction "24_24") (pintype "passive"))
    )
    (net (code "229") (name "unconnected-(CF6.2-Pad25)") (class "Default")
      (node (ref "CF6.2") (pin "25") (pinfunction "25_25") (pintype "passive"))
    )
    (net (code "230") (name "unconnected-(CF6.2-Pad26)") (class "Default")
      (node (ref "CF6.2") (pin "26") (pinfunction "26_26") (pintype "passive"))
    )
    (net (code "231") (name "unconnected-(CF6.2-Pad27)") (class "Default")
      (node (ref "CF6.2") (pin "27") (pinfunction "27_27") (pintype "passive"))
    )
    (net (code "232") (name "unconnected-(CF6.2-Pad28)") (class "Default")
      (node (ref "CF6.2") (pin "28") (pinfunction "28_28") (pintype "passive"))
    )
    (net (code "233") (name "unconnected-(CF6.2-Pad29)") (class "Default")
      (node (ref "CF6.2") (pin "29") (pinfunction "29_29") (pintype "passive"))
    )
    (net (code "234") (name "unconnected-(CF6.2-Pad30)") (class "Default")
      (node (ref "CF6.2") (pin "30") (pinfunction "30_30") (pintype "passive"))
    )
    (net (code "235") (name "unconnected-(CF6.2-Pad31)") (class "Default")
      (node (ref "CF6.2") (pin "31") (pinfunction "31_31") (pintype "passive"))
    )
    (net (code "236") (name "unconnected-(CF6.2-Pad32)") (class "Default")
      (node (ref "CF6.2") (pin "32") (pinfunction "32_32") (pintype "passive"))
    )
    (net (code "237") (name "unconnected-(CF6.2-Pad33)") (class "Default")
      (node (ref "CF6.2") (pin "33") (pinfunction "33_33") (pintype "passive"))
    )
    (net (code "238") (name "unconnected-(CF6.2-Pad34)") (class "Default")
      (node (ref "CF6.2") (pin "34") (pinfunction "34_34") (pintype "passive"))
    )
    (net (code "239") (name "unconnected-(CF6.2-Pad35)") (class "Default")
      (node (ref "CF6.2") (pin "35") (pinfunction "35_35") (pintype "passive"))
    )
    (net (code "240") (name "unconnected-(CF6.2-Pad36)") (class "Default")
      (node (ref "CF6.2") (pin "36") (pinfunction "36_36") (pintype "passive"))
    )
    (net (code "241") (name "unconnected-(CF6.2-Pad37)") (class "Default")
      (node (ref "CF6.2") (pin "37") (pinfunction "37_37") (pintype "passive"))
    )
    (net (code "242") (name "unconnected-(CF6.2-Pad38)") (class "Default")
      (node (ref "CF6.2") (pin "38") (pinfunction "38_38") (pintype "passive"))
    )
    (net (code "243") (name "unconnected-(CF6.2-Pad39)") (class "Default")
      (node (ref "CF6.2") (pin "39") (pinfunction "39_39") (pintype "passive"))
    )
    (net (code "244") (name "unconnected-(CF6.2-Pad40)") (class "Default")
      (node (ref "CF6.2") (pin "40") (pinfunction "40_40") (pintype "passive"))
    )
    (net (code "245") (name "unconnected-(CF7.1-Pad1)") (class "Default")
      (node (ref "CF7.1") (pin "1") (pinfunction "1_1") (pintype "passive"))
    )
    (net (code "246") (name "unconnected-(CF7.1-Pad2)") (class "Default")
      (node (ref "CF7.1") (pin "2") (pinfunction "2_2") (pintype "passive"))
    )
    (net (code "247") (name "unconnected-(CF7.1-Pad3)") (class "Default")
      (node (ref "CF7.1") (pin "3") (pinfunction "3_3") (pintype "passive"))
    )
    (net (code "248") (name "unconnected-(CF7.1-Pad4)") (class "Default")
      (node (ref "CF7.1") (pin "4") (pinfunction "4_4") (pintype "passive"))
    )
    (net (code "249") (name "unconnected-(CF7.1-Pad5)") (class "Default")
      (node (ref "CF7.1") (pin "5") (pinfunction "5_5") (pintype "passive"))
    )
    (net (code "250") (name "unconnected-(CF7.1-Pad6)") (class "Default")
      (node (ref "CF7.1") (pin "6") (pinfunction "6_6") (pintype "passive"))
    )
    (net (code "251") (name "unconnected-(CF7.1-Pad7)") (class "Default")
      (node (ref "CF7.1") (pin "7") (pinfunction "7_7") (pintype "passive"))
    )
    (net (code "252") (name "unconnected-(CF7.1-Pad8)") (class "Default")
      (node (ref "CF7.1") (pin "8") (pinfunction "8_8") (pintype "passive"))
    )
    (net (code "253") (name "unconnected-(CF7.1-Pad9)") (class "Default")
      (node (ref "CF7.1") (pin "9") (pinfunction "9_9") (pintype "passive"))
    )
    (net (code "254") (name "unconnected-(CF7.1-Pad10)") (class "Default")
      (node (ref "CF7.1") (pin "10") (pinfunction "10_10") (pintype "passive"))
    )
    (net (code "255") (name "unconnected-(CF7.1-Pad11)") (class "Default")
      (node (ref "CF7.1") (pin "11") (pinfunction "11_11") (pintype "passive"))
    )
    (net (code "256") (name "unconnected-(CF7.1-Pad12)") (class "Default")
      (node (ref "CF7.1") (pin "12") (pinfunction "12_12") (pintype "passive"))
    )
    (net (code "257") (name "unconnected-(CF7.1-Pad13)") (class "Default")
      (node (ref "CF7.1") (pin "13") (pinfunction "13_13") (pintype "passive"))
    )
    (net (code "258") (name "unconnected-(CF7.1-Pad14)") (class "Default")
      (node (ref "CF7.1") (pin "14") (pinfunction "14_14") (pintype "passive"))
    )
    (net (code "259") (name "unconnected-(CF7.1-Pad15)") (class "Default")
      (node (ref "CF7.1") (pin "15") (pinfunction "15_15") (pintype "passive"))
    )
    (net (code "260") (name "unconnected-(CF7.1-Pad16)") (class "Default")
      (node (ref "CF7.1") (pin "16") (pinfunction "16_16") (pintype "passive"))
    )
    (net (code "261") (name "unconnected-(CF7.1-Pad17)") (class "Default")
      (node (ref "CF7.1") (pin "17") (pinfunction "17_17") (pintype "passive"))
    )
    (net (code "262") (name "unconnected-(CF7.1-Pad18)") (class "Default")
      (node (ref "CF7.1") (pin "18") (pinfunction "18_18") (pintype "passive"))
    )
    (net (code "263") (name "unconnected-(CF7.1-Pad19)") (class "Default")
      (node (ref "CF7.1") (pin "19") (pinfunction "19_19") (pintype "passive"))
    )
    (net (code "264") (name "unconnected-(CF7.1-Pad20)") (class "Default")
      (node (ref "CF7.1") (pin "20") (pinfunction "20_20") (pintype "passive"))
    )
    (net (code "265") (name "unconnected-(CF7.2-Pad17)") (class "Default")
      (node (ref "CF7.2") (pin "17") (pinfunction "17_17") (pintype "passive"))
    )
    (net (code "266") (name "unconnected-(CF7.2-Pad18)") (class "Default")
      (node (ref "CF7.2") (pin "18") (pinfunction "18_18") (pintype "passive"))
    )
    (net (code "267") (name "unconnected-(CF7.2-Pad19)") (class "Default")
      (node (ref "CF7.2") (pin "19") (pinfunction "19_19") (pintype "passive"))
    )
    (net (code "268") (name "unconnected-(CF7.2-Pad20)") (class "Default")
      (node (ref "CF7.2") (pin "20") (pinfunction "20_20") (pintype "passive"))
    )
    (net (code "269") (name "unconnected-(CF7.2-Pad21)") (class "Default")
      (node (ref "CF7.2") (pin "21") (pinfunction "21_21") (pintype "passive"))
    )
    (net (code "270") (name "unconnected-(CF7.2-Pad22)") (class "Default")
      (node (ref "CF7.2") (pin "22") (pinfunction "22_22") (pintype "passive"))
    )
    (net (code "271") (name "unconnected-(CF7.2-Pad23)") (class "Default")
      (node (ref "CF7.2") (pin "23") (pinfunction "23_23") (pintype "passive"))
    )
    (net (code "272") (name "unconnected-(CF7.2-Pad24)") (class "Default")
      (node (ref "CF7.2") (pin "24") (pinfunction "24_24") (pintype "passive"))
    )
    (net (code "273") (name "unconnected-(CF7.2-Pad25)") (class "Default")
      (node (ref "CF7.2") (pin "25") (pinfunction "25_25") (pintype "passive"))
    )
    (net (code "274") (name "unconnected-(CF7.2-Pad26)") (class "Default")
      (node (ref "CF7.2") (pin "26") (pinfunction "26_26") (pintype "passive"))
    )
    (net (code "275") (name "unconnected-(CF7.2-Pad27)") (class "Default")
      (node (ref "CF7.2") (pin "27") (pinfunction "27_27") (pintype "passive"))
    )
    (net (code "276") (name "unconnected-(CF7.2-Pad28)") (class "Default")
      (node (ref "CF7.2") (pin "28") (pinfunction "28_28") (pintype "passive"))
    )
    (net (code "277") (name "unconnected-(CF7.2-Pad29)") (class "Default")
      (node (ref "CF7.2") (pin "29") (pinfunction "29_29") (pintype "passive"))
    )
    (net (code "278") (name "unconnected-(CF7.2-Pad30)") (class "Default")
      (node (ref "CF7.2") (pin "30") (pinfunction "30_30") (pintype "passive"))
    )
    (net (code "279") (name "unconnected-(CF7.2-Pad31)") (class "Default")
      (node (ref "CF7.2") (pin "31") (pinfunction "31_31") (pintype "passive"))
    )
    (net (code "280") (name "unconnected-(CF7.2-Pad32)") (class "Default")
      (node (ref "CF7.2") (pin "32") (pinfunction "32_32") (pintype "passive"))
    )
    (net (code "281") (name "unconnected-(CF7.2-Pad33)") (class "Default")
      (node (ref "CF7.2") (pin "33") (pinfunction "33_33") (pintype "passive"))
    )
    (net (code "282") (name "unconnected-(CF7.2-Pad34)") (class "Default")
      (node (ref "CF7.2") (pin "34") (pinfunction "34_34") (pintype "passive"))
    )
    (net (code "283") (name "unconnected-(CF7.2-Pad35)") (class "Default")
      (node (ref "CF7.2") (pin "35") (pinfunction "35_35") (pintype "passive"))
    )
    (net (code "284") (name "unconnected-(CF7.2-Pad36)") (class "Default")
      (node (ref "CF7.2") (pin "36") (pinfunction "36_36") (pintype "passive"))
    )
    (net (code "285") (name "unconnected-(CF7.2-Pad37)") (class "Default")
      (node (ref "CF7.2") (pin "37") (pinfunction "37_37") (pintype "passive"))
    )
    (net (code "286") (name "unconnected-(CF7.2-Pad38)") (class "Default")
      (node (ref "CF7.2") (pin "38") (pinfunction "38_38") (pintype "passive"))
    )
    (net (code "287") (name "unconnected-(CF7.2-Pad39)") (class "Default")
      (node (ref "CF7.2") (pin "39") (pinfunction "39_39") (pintype "passive"))
    )
    (net (code "288") (name "unconnected-(CF7.2-Pad40)") (class "Default")
      (node (ref "CF7.2") (pin "40") (pinfunction "40_40") (pintype "passive"))
    )
    (net (code "289") (name "unconnected-(CF8.1-Pad1)") (class "Default")
      (node (ref "CF8.1") (pin "1") (pinfunction "1_1") (pintype "passive"))
    )
    (net (code "290") (name "unconnected-(CF8.1-Pad2)") (class "Default")
      (node (ref "CF8.1") (pin "2") (pinfunction "2_2") (pintype "passive"))
    )
    (net (code "291") (name "unconnected-(CF8.1-Pad3)") (class "Default")
      (node (ref "CF8.1") (pin "3") (pinfunction "3_3") (pintype "passive"))
    )
    (net (code "292") (name "unconnected-(CF8.1-Pad4)") (class "Default")
      (node (ref "CF8.1") (pin "4") (pinfunction "4_4") (pintype "passive"))
    )
    (net (code "293") (name "unconnected-(CF8.1-Pad5)") (class "Default")
      (node (ref "CF8.1") (pin "5") (pinfunction "5_5") (pintype "passive"))
    )
    (net (code "294") (name "unconnected-(CF8.1-Pad6)") (class "Default")
      (node (ref "CF8.1") (pin "6") (pinfunction "6_6") (pintype "passive"))
    )
    (net (code "295") (name "unconnected-(CF8.1-Pad7)") (class "Default")
      (node (ref "CF8.1") (pin "7") (pinfunction "7_7") (pintype "passive"))
    )
    (net (code "296") (name "unconnected-(CF8.1-Pad8)") (class "Default")
      (node (ref "CF8.1") (pin "8") (pinfunction "8_8") (pintype "passive"))
    )
    (net (code "297") (name "unconnected-(CF8.1-Pad9)") (class "Default")
      (node (ref "CF8.1") (pin "9") (pinfunction "9_9") (pintype "passive"))
    )
    (net (code "298") (name "unconnected-(CF8.1-Pad10)") (class "Default")
      (node (ref "CF8.1") (pin "10") (pinfunction "10_10") (pintype "passive"))
    )
    (net (code "299") (name "unconnected-(CF8.1-Pad11)") (class "Default")
      (node (ref "CF8.1") (pin "11") (pinfunction "11_11") (pintype "passive"))
    )
    (net (code "300") (name "unconnected-(CF8.1-Pad12)") (class "Default")
      (node (ref "CF8.1") (pin "12") (pinfunction "12_12") (pintype "passive"))
    )
    (net (code "301") (name "unconnected-(CF8.1-Pad13)") (class "Default")
      (node (ref "CF8.1") (pin "13") (pinfunction "13_13") (pintype "passive"))
    )
    (net (code "302") (name "unconnected-(CF8.1-Pad14)") (class "Default")
      (node (ref "CF8.1") (pin "14") (pinfunction "14_14") (pintype "passive"))
    )
    (net (code "303") (name "unconnected-(CF8.1-Pad15)") (class "Default")
      (node (ref "CF8.1") (pin "15") (pinfunction "15_15") (pintype "passive"))
    )
    (net (code "304") (name "unconnected-(CF8.1-Pad16)") (class "Default")
      (node (ref "CF8.1") (pin "16") (pinfunction "16_16") (pintype "passive"))
    )
    (net (code "305") (name "unconnected-(CF8.1-Pad17)") (class "Default")
      (node (ref "CF8.1") (pin "17") (pinfunction "17_17") (pintype "passive"))
    )
    (net (code "306") (name "unconnected-(CF8.1-Pad18)") (class "Default")
      (node (ref "CF8.1") (pin "18") (pinfunction "18_18") (pintype "passive"))
    )
    (net (code "307") (name "unconnected-(CF8.1-Pad19)") (class "Default")
      (node (ref "CF8.1") (pin "19") (pinfunction "19_19") (pintype "passive"))
    )
    (net (code "308") (name "unconnected-(CF8.1-Pad20)") (class "Default")
      (node (ref "CF8.1") (pin "20") (pinfunction "20_20") (pintype "passive"))
    )
    (net (code "309") (name "unconnected-(CF8.2-Pad17)") (class "Default")
      (node (ref "CF8.2") (pin "17") (pinfunction "17_17") (pintype "passive"))
    )
    (net (code "310") (name "unconnected-(CF8.2-Pad18)") (class "Default")
      (node (ref "CF8.2") (pin "18") (pinfunction "18_18") (pintype "passive"))
    )
    (net (code "311") (name "unconnected-(CF8.2-Pad19)") (class "Default")
      (node (ref "CF8.2") (pin "19") (pinfunction "19_19") (pintype "passive"))
    )
    (net (code "312") (name "unconnected-(CF8.2-Pad20)") (class "Default")
      (node (ref "CF8.2") (pin "20") (pinfunction "20_20") (pintype "passive"))
    )
    (net (code "313") (name "unconnected-(CF8.2-Pad21)") (class "Default")
      (node (ref "CF8.2") (pin "21") (pinfunction "21_21") (pintype "passive"))
    )
    (net (code "314") (name "unconnected-(CF8.2-Pad22)") (class "Default")
      (node (ref "CF8.2") (pin "22") (pinfunction "22_22") (pintype "passive"))
    )
    (net (code "315") (name "unconnected-(CF8.2-Pad23)") (class "Default")
      (node (ref "CF8.2") (pin "23") (pinfunction "23_23") (pintype "passive"))
    )
    (net (code "316") (name "unconnected-(CF8.2-Pad24)") (class "Default")
      (node (ref "CF8.2") (pin "24") (pinfunction "24_24") (pintype "passive"))
    )
    (net (code "317") (name "unconnected-(CF8.2-Pad25)") (class "Default")
      (node (ref "CF8.2") (pin "25") (pinfunction "25_25") (pintype "passive"))
    )
    (net (code "318") (name "unconnected-(CF8.2-Pad26)") (class "Default")
      (node (ref "CF8.2") (pin "26") (pinfunction "26_26") (pintype "passive"))
    )
    (net (code "319") (name "unconnected-(CF8.2-Pad27)") (class "Default")
      (node (ref "CF8.2") (pin "27") (pinfunction "27_27") (pintype "passive"))
    )
    (net (code "320") (name "unconnected-(CF8.2-Pad28)") (class "Default")
      (node (ref "CF8.2") (pin "28") (pinfunction "28_28") (pintype "passive"))
    )
    (net (code "321") (name "unconnected-(CF8.2-Pad29)") (class "Default")
      (node (ref "CF8.2") (pin "29") (pinfunction "29_29") (pintype "passive"))
    )
    (net (code "322") (name "unconnected-(CF8.2-Pad30)") (class "Default")
      (node (ref "CF8.2") (pin "30") (pinfunction "30_30") (pintype "passive"))
    )
    (net (code "323") (name "unconnected-(CF8.2-Pad31)") (class "Default")
      (node (ref "CF8.2") (pin "31") (pinfunction "31_31") (pintype "passive"))
    )
    (net (code "324") (name "unconnected-(CF8.2-Pad32)") (class "Default")
      (node (ref "CF8.2") (pin "32") (pinfunction "32_32") (pintype "passive"))
    )
    (net (code "325") (name "unconnected-(CF8.2-Pad33)") (class "Default")
      (node (ref "CF8.2") (pin "33") (pinfunction "33_33") (pintype "passive"))
    )
    (net (code "326") (name "unconnected-(CF8.2-Pad34)") (class "Default")
      (node (ref "CF8.2") (pin "34") (pinfunction "34_34") (pintype "passive"))
    )
    (net (code "327") (name "unconnected-(CF8.2-Pad35)") (class "Default")
      (node (ref "CF8.2") (pin "35") (pinfunction "35_35") (pintype "passive"))
    )
    (net (code "328") (name "unconnected-(CF8.2-Pad36)") (class "Default")
      (node (ref "CF8.2") (pin "36") (pinfunction "36_36") (pintype "passive"))
    )
    (net (code "329") (name "unconnected-(CF8.2-Pad37)") (class "Default")
      (node (ref "CF8.2") (pin "37") (pinfunction "37_37") (pintype "passive"))
    )
    (net (code "330") (name "unconnected-(CF8.2-Pad38)") (class "Default")
      (node (ref "CF8.2") (pin "38") (pinfunction "38_38") (pintype "passive"))
    )
    (net (code "331") (name "unconnected-(CF8.2-Pad39)") (class "Default")
      (node (ref "CF8.2") (pin "39") (pinfunction "39_39") (pintype "passive"))
    )
    (net (code "332") (name "unconnected-(CF8.2-Pad40)") (class "Default")
      (node (ref "CF8.2") (pin "40") (pinfunction "40_40") (pintype "passive"))
    )
    (net (code "333") (name "unconnected-(CF9.1-Pad1)") (class "Default")
      (node (ref "CF9.1") (pin "1") (pinfunction "1_1") (pintype "passive"))
    )
    (net (code "334") (name "unconnected-(CF9.1-Pad2)") (class "Default")
      (node (ref "CF9.1") (pin "2") (pinfunction "2_2") (pintype "passive"))
    )
    (net (code "335") (name "unconnected-(CF9.1-Pad3)") (class "Default")
      (node (ref "CF9.1") (pin "3") (pinfunction "3_3") (pintype "passive"))
    )
    (net (code "336") (name "unconnected-(CF9.1-Pad4)") (class "Default")
      (node (ref "CF9.1") (pin "4") (pinfunction "4_4") (pintype "passive"))
    )
    (net (code "337") (name "unconnected-(CF9.1-Pad5)") (class "Default")
      (node (ref "CF9.1") (pin "5") (pinfunction "5_5") (pintype "passive"))
    )
    (net (code "338") (name "unconnected-(CF9.1-Pad6)") (class "Default")
      (node (ref "CF9.1") (pin "6") (pinfunction "6_6") (pintype "passive"))
    )
    (net (code "339") (name "unconnected-(CF9.1-Pad7)") (class "Default")
      (node (ref "CF9.1") (pin "7") (pinfunction "7_7") (pintype "passive"))
    )
    (net (code "340") (name "unconnected-(CF9.1-Pad8)") (class "Default")
      (node (ref "CF9.1") (pin "8") (pinfunction "8_8") (pintype "passive"))
    )
    (net (code "341") (name "unconnected-(CF9.1-Pad9)") (class "Default")
      (node (ref "CF9.1") (pin "9") (pinfunction "9_9") (pintype "passive"))
    )
    (net (code "342") (name "unconnected-(CF9.1-Pad10)") (class "Default")
      (node (ref "CF9.1") (pin "10") (pinfunction "10_10") (pintype "passive"))
    )
    (net (code "343") (name "unconnected-(CF9.1-Pad11)") (class "Default")
      (node (ref "CF9.1") (pin "11") (pinfunction "11_11") (pintype "passive"))
    )
    (net (code "344") (name "unconnected-(CF9.1-Pad12)") (class "Default")
      (node (ref "CF9.1") (pin "12") (pinfunction "12_12") (pintype "passive"))
    )
    (net (code "345") (name "unconnected-(CF9.1-Pad13)") (class "Default")
      (node (ref "CF9.1") (pin "13") (pinfunction "13_13") (pintype "passive"))
    )
    (net (code "346") (name "unconnected-(CF9.1-Pad14)") (class "Default")
      (node (ref "CF9.1") (pin "14") (pinfunction "14_14") (pintype "passive"))
    )
    (net (code "347") (name "unconnected-(CF9.1-Pad15)") (class "Default")
      (node (ref "CF9.1") (pin "15") (pinfunction "15_15") (pintype "passive"))
    )
    (net (code "348") (name "unconnected-(CF9.1-Pad16)") (class "Default")
      (node (ref "CF9.1") (pin "16") (pinfunction "16_16") (pintype "passive"))
    )
    (net (code "349") (name "unconnected-(CF9.1-Pad17)") (class "Default")
      (node (ref "CF9.1") (pin "17") (pinfunction "17_17") (pintype "passive"))
    )
    (net (code "350") (name "unconnected-(CF9.1-Pad18)") (class "Default")
      (node (ref "CF9.1") (pin "18") (pinfunction "18_18") (pintype "passive"))
    )
    (net (code "351") (name "unconnected-(CF9.1-Pad19)") (class "Default")
      (node (ref "CF9.1") (pin "19") (pinfunction "19_19") (pintype "passive"))
    )
    (net (code "352") (name "unconnected-(CF9.1-Pad20)") (class "Default")
      (node (ref "CF9.1") (pin "20") (pinfunction "20_20") (pintype "passive"))
    )
    (net (code "353") (name "unconnected-(CF9.2-Pad17)") (class "Default")
      (node (ref "CF9.2") (pin "17") (pinfunction "17_17") (pintype "passive"))
    )
    (net (code "354") (name "unconnected-(CF9.2-Pad18)") (class "Default")
      (node (ref "CF9.2") (pin "18") (pinfunction "18_18") (pintype "passive"))
    )
    (net (code "355") (name "unconnected-(CF9.2-Pad19)") (class "Default")
      (node (ref "CF9.2") (pin "19") (pinfunction "19_19") (pintype "passive"))
    )
    (net (code "356") (name "unconnected-(CF9.2-Pad20)") (class "Default")
      (node (ref "CF9.2") (pin "20") (pinfunction "20_20") (pintype "passive"))
    )
    (net (code "357") (name "unconnected-(CF9.2-Pad21)") (class "Default")
      (node (ref "CF9.2") (pin "21") (pinfunction "21_21") (pintype "passive"))
    )
    (net (code "358") (name "unconnected-(CF9.2-Pad22)") (class "Default")
      (node (ref "CF9.2") (pin "22") (pinfunction "22_22") (pintype "passive"))
    )
    (net (code "359") (name "unconnected-(CF9.2-Pad23)") (class "Default")
      (node (ref "CF9.2") (pin "23") (pinfunction "23_23") (pintype "passive"))
    )
    (net (code "360") (name "unconnected-(CF9.2-Pad24)") (class "Default")
      (node (ref "CF9.2") (pin "24") (pinfunction "24_24") (pintype "passive"))
    )
    (net (code "361") (name "unconnected-(CF9.2-Pad25)") (class "Default")
      (node (ref "CF9.2") (pin "25") (pinfunction "25_25") (pintype "passive"))
    )
    (net (code "362") (name "unconnected-(CF9.2-Pad26)") (class "Default")
      (node (ref "CF9.2") (pin "26") (pinfunction "26_26") (pintype "passive"))
    )
    (net (code "363") (name "unconnected-(CF9.2-Pad27)") (class "Default")
      (node (ref "CF9.2") (pin "27") (pinfunction "27_27") (pintype "passive"))
    )
    (net (code "364") (name "unconnected-(CF9.2-Pad28)") (class "Default")
      (node (ref "CF9.2") (pin "28") (pinfunction "28_28") (pintype "passive"))
    )
    (net (code "365") (name "unconnected-(CF9.2-Pad29)") (class "Default")
      (node (ref "CF9.2") (pin "29") (pinfunction "29_29") (pintype "passive"))
    )
    (net (code "366") (name "unconnected-(CF9.2-Pad30)") (class "Default")
      (node (ref "CF9.2") (pin "30") (pinfunction "30_30") (pintype "passive"))
    )
    (net (code "367") (name "unconnected-(CF9.2-Pad31)") (class "Default")
      (node (ref "CF9.2") (pin "31") (pinfunction "31_31") (pintype "passive"))
    )
    (net (code "368") (name "unconnected-(CF9.2-Pad32)") (class "Default")
      (node (ref "CF9.2") (pin "32") (pinfunction "32_32") (pintype "passive"))
    )
    (net (code "369") (name "unconnected-(CF9.2-Pad33)") (class "Default")
      (node (ref "CF9.2") (pin "33") (pinfunction "33_33") (pintype "passive"))
    )
    (net (code "370") (name "unconnected-(CF9.2-Pad34)") (class "Default")
      (node (ref "CF9.2") (pin "34") (pinfunction "34_34") (pintype "passive"))
    )
    (net (code "371") (name "unconnected-(CF9.2-Pad35)") (class "Default")
      (node (ref "CF9.2") (pin "35") (pinfunction "35_35") (pintype "passive"))
    )
    (net (code "372") (name "unconnected-(CF9.2-Pad36)") (class "Default")
      (node (ref "CF9.2") (pin "36") (pinfunction "36_36") (pintype "passive"))
    )
    (net (code "373") (name "unconnected-(CF9.2-Pad37)") (class "Default")
      (node (ref "CF9.2") (pin "37") (pinfunction "37_37") (pintype "passive"))
    )
    (net (code "374") (name "unconnected-(CF9.2-Pad38)") (class "Default")
      (node (ref "CF9.2") (pin "38") (pinfunction "38_38") (pintype "passive"))
    )
    (net (code "375") (name "unconnected-(CF9.2-Pad39)") (class "Default")
      (node (ref "CF9.2") (pin "39") (pinfunction "39_39") (pintype "passive"))
    )
    (net (code "376") (name "unconnected-(CF9.2-Pad40)") (class "Default")
      (node (ref "CF9.2") (pin "40") (pinfunction "40_40") (pintype "passive"))
    )
    (net (code "377") (name "unconnected-(CF10.1-Pad1)") (class "Default")
      (node (ref "CF10.1") (pin "1") (pinfunction "1_1") (pintype "passive"))
    )
    (net (code "378") (name "unconnected-(CF10.1-Pad2)") (class "Default")
      (node (ref "CF10.1") (pin "2") (pinfunction "2_2") (pintype "passive"))
    )
    (net (code "379") (name "unconnected-(CF10.1-Pad3)") (class "Default")
      (node (ref "CF10.1") (pin "3") (pinfunction "3_3") (pintype "passive"))
    )
    (net (code "380") (name "unconnected-(CF10.1-Pad4)") (class "Default")
      (node (ref "CF10.1") (pin "4") (pinfunction "4_4") (pintype "passive"))
    )
    (net (code "381") (name "unconnected-(CF10.1-Pad5)") (class "Default")
      (node (ref "CF10.1") (pin "5") (pinfunction "5_5") (pintype "passive"))
    )
    (net (code "382") (name "unconnected-(CF10.1-Pad6)") (class "Default")
      (node (ref "CF10.1") (pin "6") (pinfunction "6_6") (pintype "passive"))
    )
    (net (code "383") (name "unconnected-(CF10.1-Pad7)") (class "Default")
      (node (ref "CF10.1") (pin "7") (pinfunction "7_7") (pintype "passive"))
    )
    (net (code "384") (name "unconnected-(CF10.1-Pad8)") (class "Default")
      (node (ref "CF10.1") (pin "8") (pinfunction "8_8") (pintype "passive"))
    )
    (net (code "385") (name "unconnected-(CF10.1-Pad9)") (class "Default")
      (node (ref "CF10.1") (pin "9") (pinfunction "9_9") (pintype "passive"))
    )
    (net (code "386") (name "unconnected-(CF10.1-Pad10)") (class "Default")
      (node (ref "CF10.1") (pin "10") (pinfunction "10_10") (pintype "passive"))
    )
    (net (code "387") (name "unconnected-(CF10.1-Pad11)") (class "Default")
      (node (ref "CF10.1") (pin "11") (pinfunction "11_11") (pintype "passive"))
    )
    (net (code "388") (name "unconnected-(CF10.1-Pad12)") (class "Default")
      (node (ref "CF10.1") (pin "12") (pinfunction "12_12") (pintype "passive"))
    )
    (net (code "389") (name "unconnected-(CF10.1-Pad13)") (class "Default")
      (node (ref "CF10.1") (pin "13") (pinfunction "13_13") (pintype "passive"))
    )
    (net (code "390") (name "unconnected-(CF10.1-Pad14)") (class "Default")
      (node (ref "CF10.1") (pin "14") (pinfunction "14_14") (pintype "passive"))
    )
    (net (code "391") (name "unconnected-(CF10.1-Pad15)") (class "Default")
      (node (ref "CF10.1") (pin "15") (pinfunction "15_15") (pintype "passive"))
    )
    (net (code "392") (name "unconnected-(CF10.1-Pad16)") (class "Default")
      (node (ref "CF10.1") (pin "16") (pinfunction "16_16") (pintype "passive"))
    )
    (net (code "393") (name "unconnected-(CF10.1-Pad17)") (class "Default")
      (node (ref "CF10.1") (pin "17") (pinfunction "17_17") (pintype "passive"))
    )
    (net (code "394") (name "unconnected-(CF10.1-Pad18)") (class "Default")
      (node (ref "CF10.1") (pin "18") (pinfunction "18_18") (pintype "passive"))
    )
    (net (code "395") (name "unconnected-(CF10.1-Pad19)") (class "Default")
      (node (ref "CF10.1") (pin "19") (pinfunction "19_19") (pintype "passive"))
    )
    (net (code "396") (name "unconnected-(CF10.1-Pad20)") (class "Default")
      (node (ref "CF10.1") (pin "20") (pinfunction "20_20") (pintype "passive"))
    )
    (net (code "397") (name "unconnected-(CF10.2-Pad17)") (class "Default")
      (node (ref "CF10.2") (pin "17") (pinfunction "17_17") (pintype "passive"))
    )
    (net (code "398") (name "unconnected-(CF10.2-Pad18)") (class "Default")
      (node (ref "CF10.2") (pin "18") (pinfunction "18_18") (pintype "passive"))
    )
    (net (code "399") (name "unconnected-(CF10.2-Pad19)") (class "Default")
      (node (ref "CF10.2") (pin "19") (pinfunction "19_19") (pintype "passive"))
    )
    (net (code "400") (name "unconnected-(CF10.2-Pad20)") (class "Default")
      (node (ref "CF10.2") (pin "20") (pinfunction "20_20") (pintype "passive"))
    )
    (net (code "401") (name "unconnected-(CF10.2-Pad21)") (class "Default")
      (node (ref "CF10.2") (pin "21") (pinfunction "21_21") (pintype "passive"))
    )
    (net (code "402") (name "unconnected-(CF10.2-Pad22)") (class "Default")
      (node (ref "CF10.2") (pin "22") (pinfunction "22_22") (pintype "passive"))
    )
    (net (code "403") (name "unconnected-(CF10.2-Pad23)") (class "Default")
      (node (ref "CF10.2") (pin "23") (pinfunction "23_23") (pintype "passive"))
    )
    (net (code "404") (name "unconnected-(CF10.2-Pad24)") (class "Default")
      (node (ref "CF10.2") (pin "24") (pinfunction "24_24") (pintype "passive"))
    )
    (net (code "405") (name "unconnected-(CF10.2-Pad25)") (class "Default")
      (node (ref "CF10.2") (pin "25") (pinfunction "25_25") (pintype "passive"))
    )
    (net (code "406") (name "unconnected-(CF10.2-Pad26)") (class "Default")
      (node (ref "CF10.2") (pin "26") (pinfunction "26_26") (pintype "passive"))
    )
    (net (code "407") (name "unconnected-(CF10.2-Pad27)") (class "Default")
      (node (ref "CF10.2") (pin "27") (pinfunction "27_27") (pintype "passive"))
    )
    (net (code "408") (name "unconnected-(CF10.2-Pad28)") (class "Default")
      (node (ref "CF10.2") (pin "28") (pinfunction "28_28") (pintype "passive"))
    )
    (net (code "409") (name "unconnected-(CF10.2-Pad29)") (class "Default")
      (node (ref "CF10.2") (pin "29") (pinfunction "29_29") (pintype "passive"))
    )
    (net (code "410") (name "unconnected-(CF10.2-Pad30)") (class "Default")
      (node (ref "CF10.2") (pin "30") (pinfunction "30_30") (pintype "passive"))
    )
    (net (code "411") (name "unconnected-(CF10.2-Pad31)") (class "Default")
      (node (ref "CF10.2") (pin "31") (pinfunction "31_31") (pintype "passive"))
    )
    (net (code "412") (name "unconnected-(CF10.2-Pad32)") (class "Default")
      (node (ref "CF10.2") (pin "32") (pinfunction "32_32") (pintype "passive"))
    )
    (net (code "413") (name "unconnected-(CF10.2-Pad33)") (class "Default")
      (node (ref "CF10.2") (pin "33") (pinfunction "33_33") (pintype "passive"))
    )
    (net (code "414") (name "unconnected-(CF10.2-Pad34)") (class "Default")
      (node (ref "CF10.2") (pin "34") (pinfunction "34_34") (pintype "passive"))
    )
    (net (code "415") (name "unconnected-(CF10.2-Pad35)") (class "Default")
      (node (ref "CF10.2") (pin "35") (pinfunction "35_35") (pintype "passive"))
    )
    (net (code "416") (name "unconnected-(CF10.2-Pad36)") (class "Default")
      (node (ref "CF10.2") (pin "36") (pinfunction "36_36") (pintype "passive"))
    )
    (net (code "417") (name "unconnected-(CF10.2-Pad37)") (class "Default")
      (node (ref "CF10.2") (pin "37") (pinfunction "37_37") (pintype "passive"))
    )
    (net (code "418") (name "unconnected-(CF10.2-Pad38)") (class "Default")
      (node (ref "CF10.2") (pin "38") (pinfunction "38_38") (pintype "passive"))
    )
    (net (code "419") (name "unconnected-(CF10.2-Pad39)") (class "Default")
      (node (ref "CF10.2") (pin "39") (pinfunction "39_39") (pintype "passive"))
    )
    (net (code "420") (name "unconnected-(CF10.2-Pad40)") (class "Default")
      (node (ref "CF10.2") (pin "40") (pinfunction "40_40") (pintype "passive"))
    )
    (net (code "421") (name "unconnected-(CF11.1-Pad1)") (class "Default")
      (node (ref "CF11.1") (pin "1") (pinfunction "1_1") (pintype "passive"))
    )
    (net (code "422") (name "unconnected-(CF11.1-Pad2)") (class "Default")
      (node (ref "CF11.1") (pin "2") (pinfunction "2_2") (pintype "passive"))
    )
    (net (code "423") (name "unconnected-(CF11.1-Pad3)") (class "Default")
      (node (ref "CF11.1") (pin "3") (pinfunction "3_3") (pintype "passive"))
    )
    (net (code "424") (name "unconnected-(CF11.1-Pad4)") (class "Default")
      (node (ref "CF11.1") (pin "4") (pinfunction "4_4") (pintype "passive"))
    )
    (net (code "425") (name "unconnected-(CF11.1-Pad5)") (class "Default")
      (node (ref "CF11.1") (pin "5") (pinfunction "5_5") (pintype "passive"))
    )
    (net (code "426") (name "unconnected-(CF11.1-Pad6)") (class "Default")
      (node (ref "CF11.1") (pin "6") (pinfunction "6_6") (pintype "passive"))
    )
    (net (code "427") (name "unconnected-(CF11.1-Pad7)") (class "Default")
      (node (ref "CF11.1") (pin "7") (pinfunction "7_7") (pintype "passive"))
    )
    (net (code "428") (name "unconnected-(CF11.1-Pad8)") (class "Default")
      (node (ref "CF11.1") (pin "8") (pinfunction "8_8") (pintype "passive"))
    )
    (net (code "429") (name "unconnected-(CF11.1-Pad9)") (class "Default")
      (node (ref "CF11.1") (pin "9") (pinfunction "9_9") (pintype "passive"))
    )
    (net (code "430") (name "unconnected-(CF11.1-Pad10)") (class "Default")
      (node (ref "CF11.1") (pin "10") (pinfunction "10_10") (pintype "passive"))
    )
    (net (code "431") (name "unconnected-(CF11.1-Pad11)") (class "Default")
      (node (ref "CF11.1") (pin "11") (pinfunction "11_11") (pintype "passive"))
    )
    (net (code "432") (name "unconnected-(CF11.1-Pad12)") (class "Default")
      (node (ref "CF11.1") (pin "12") (pinfunction "12_12") (pintype "passive"))
    )
    (net (code "433") (name "unconnected-(CF11.1-Pad13)") (class "Default")
      (node (ref "CF11.1") (pin "13") (pinfunction "13_13") (pintype "passive"))
    )
    (net (code "434") (name "unconnected-(CF11.1-Pad14)") (class "Default")
      (node (ref "CF11.1") (pin "14") (pinfunction "14_14") (pintype "passive"))
    )
    (net (code "435") (name "unconnected-(CF11.1-Pad15)") (class "Default")
      (node (ref "CF11.1") (pin "15") (pinfunction "15_15") (pintype "passive"))
    )
    (net (code "436") (name "unconnected-(CF11.1-Pad16)") (class "Default")
      (node (ref "CF11.1") (pin "16") (pinfunction "16_16") (pintype "passive"))
    )
    (net (code "437") (name "unconnected-(CF11.1-Pad17)") (class "Default")
      (node (ref "CF11.1") (pin "17") (pinfunction "17_17") (pintype "passive"))
    )
    (net (code "438") (name "unconnected-(CF11.1-Pad18)") (class "Default")
      (node (ref "CF11.1") (pin "18") (pinfunction "18_18") (pintype "passive"))
    )
    (net (code "439") (name "unconnected-(CF11.1-Pad19)") (class "Default")
      (node (ref "CF11.1") (pin "19") (pinfunction "19_19") (pintype "passive"))
    )
    (net (code "440") (name "unconnected-(CF11.1-Pad20)") (class "Default")
      (node (ref "CF11.1") (pin "20") (pinfunction "20_20") (pintype "passive"))
    )
    (net (code "441") (name "unconnected-(CF11.2-Pad17)") (class "Default")
      (node (ref "CF11.2") (pin "17") (pinfunction "17_17") (pintype "passive"))
    )
    (net (code "442") (name "unconnected-(CF11.2-Pad18)") (class "Default")
      (node (ref "CF11.2") (pin "18") (pinfunction "18_18") (pintype "passive"))
    )
    (net (code "443") (name "unconnected-(CF11.2-Pad19)") (class "Default")
      (node (ref "CF11.2") (pin "19") (pinfunction "19_19") (pintype "passive"))
    )
    (net (code "444") (name "unconnected-(CF11.2-Pad20)") (class "Default")
      (node (ref "CF11.2") (pin "20") (pinfunction "20_20") (pintype "passive"))
    )
    (net (code "445") (name "unconnected-(CF11.2-Pad21)") (class "Default")
      (node (ref "CF11.2") (pin "21") (pinfunction "21_21") (pintype "passive"))
    )
    (net (code "446") (name "unconnected-(CF11.2-Pad22)") (class "Default")
      (node (ref "CF11.2") (pin "22") (pinfunction "22_22") (pintype "passive"))
    )
    (net (code "447") (name "unconnected-(CF11.2-Pad23)") (class "Default")
      (node (ref "CF11.2") (pin "23") (pinfunction "23_23") (pintype "passive"))
    )
    (net (code "448") (name "unconnected-(CF11.2-Pad24)") (class "Default")
      (node (ref "CF11.2") (pin "24") (pinfunction "24_24") (pintype "passive"))
    )
    (net (code "449") (name "unconnected-(CF11.2-Pad25)") (class "Default")
      (node (ref "CF11.2") (pin "25") (pinfunction "25_25") (pintype "passive"))
    )
    (net (code "450") (name "unconnected-(CF11.2-Pad26)") (class "Default")
      (node (ref "CF11.2") (pin "26") (pinfunction "26_26") (pintype "passive"))
    )
    (net (code "451") (name "unconnected-(CF11.2-Pad27)") (class "Default")
      (node (ref "CF11.2") (pin "27") (pinfunction "27_27") (pintype "passive"))
    )
    (net (code "452") (name "unconnected-(CF11.2-Pad28)") (class "Default")
      (node (ref "CF11.2") (pin "28") (pinfunction "28_28") (pintype "passive"))
    )
    (net (code "453") (name "unconnected-(CF11.2-Pad29)") (class "Default")
      (node (ref "CF11.2") (pin "29") (pinfunction "29_29") (pintype "passive"))
    )
    (net (code "454") (name "unconnected-(CF11.2-Pad30)") (class "Default")
      (node (ref "CF11.2") (pin "30") (pinfunction "30_30") (pintype "passive"))
    )
    (net (code "455") (name "unconnected-(CF11.2-Pad31)") (class "Default")
      (node (ref "CF11.2") (pin "31") (pinfunction "31_31") (pintype "passive"))
    )
    (net (code "456") (name "unconnected-(CF11.2-Pad32)") (class "Default")
      (node (ref "CF11.2") (pin "32") (pinfunction "32_32") (pintype "passive"))
    )
    (net (code "457") (name "unconnected-(CF11.2-Pad33)") (class "Default")
      (node (ref "CF11.2") (pin "33") (pinfunction "33_33") (pintype "passive"))
    )
    (net (code "458") (name "unconnected-(CF11.2-Pad34)") (class "Default")
      (node (ref "CF11.2") (pin "34") (pinfunction "34_34") (pintype "passive"))
    )
    (net (code "459") (name "unconnected-(CF11.2-Pad35)") (class "Default")
      (node (ref "CF11.2") (pin "35") (pinfunction "35_35") (pintype "passive"))
    )
    (net (code "460") (name "unconnected-(CF11.2-Pad36)") (class "Default")
      (node (ref "CF11.2") (pin "36") (pinfunction "36_36") (pintype "passive"))
    )
    (net (code "461") (name "unconnected-(CF11.2-Pad37)") (class "Default")
      (node (ref "CF11.2") (pin "37") (pinfunction "37_37") (pintype "passive"))
    )
    (net (code "462") (name "unconnected-(CF11.2-Pad38)") (class "Default")
      (node (ref "CF11.2") (pin "38") (pinfunction "38_38") (pintype "passive"))
    )
    (net (code "463") (name "unconnected-(CF11.2-Pad39)") (class "Default")
      (node (ref "CF11.2") (pin "39") (pinfunction "39_39") (pintype "passive"))
    )
    (net (code "464") (name "unconnected-(CF11.2-Pad40)") (class "Default")
      (node (ref "CF11.2") (pin "40") (pinfunction "40_40") (pintype "passive"))
    )
    (net (code "465") (name "unconnected-(CF12.1-Pad1)") (class "Default")
      (node (ref "CF12.1") (pin "1") (pinfunction "1_1") (pintype "passive"))
    )
    (net (code "466") (name "unconnected-(CF12.1-Pad2)") (class "Default")
      (node (ref "CF12.1") (pin "2") (pinfunction "2_2") (pintype "passive"))
    )
    (net (code "467") (name "unconnected-(CF12.1-Pad3)") (class "Default")
      (node (ref "CF12.1") (pin "3") (pinfunction "3_3") (pintype "passive"))
    )
    (net (code "468") (name "unconnected-(CF12.1-Pad4)") (class "Default")
      (node (ref "CF12.1") (pin "4") (pinfunction "4_4") (pintype "passive"))
    )
    (net (code "469") (name "unconnected-(CF12.1-Pad5)") (class "Default")
      (node (ref "CF12.1") (pin "5") (pinfunction "5_5") (pintype "passive"))
    )
    (net (code "470") (name "unconnected-(CF12.1-Pad6)") (class "Default")
      (node (ref "CF12.1") (pin "6") (pinfunction "6_6") (pintype "passive"))
    )
    (net (code "471") (name "unconnected-(CF12.1-Pad7)") (class "Default")
      (node (ref "CF12.1") (pin "7") (pinfunction "7_7") (pintype "passive"))
    )
    (net (code "472") (name "unconnected-(CF12.1-Pad8)") (class "Default")
      (node (ref "CF12.1") (pin "8") (pinfunction "8_8") (pintype "passive"))
    )
    (net (code "473") (name "unconnected-(CF12.1-Pad9)") (class "Default")
      (node (ref "CF12.1") (pin "9") (pinfunction "9_9") (pintype "passive"))
    )
    (net (code "474") (name "unconnected-(CF12.1-Pad10)") (class "Default")
      (node (ref "CF12.1") (pin "10") (pinfunction "10_10") (pintype "passive"))
    )
    (net (code "475") (name "unconnected-(CF12.1-Pad11)") (class "Default")
      (node (ref "CF12.1") (pin "11") (pinfunction "11_11") (pintype "passive"))
    )
    (net (code "476") (name "unconnected-(CF12.1-Pad12)") (class "Default")
      (node (ref "CF12.1") (pin "12") (pinfunction "12_12") (pintype "passive"))
    )
    (net (code "477") (name "unconnected-(CF12.1-Pad13)") (class "Default")
      (node (ref "CF12.1") (pin "13") (pinfunction "13_13") (pintype "passive"))
    )
    (net (code "478") (name "unconnected-(CF12.1-Pad14)") (class "Default")
      (node (ref "CF12.1") (pin "14") (pinfunction "14_14") (pintype "passive"))
    )
    (net (code "479") (name "unconnected-(CF12.1-Pad15)") (class "Default")
      (node (ref "CF12.1") (pin "15") (pinfunction "15_15") (pintype "passive"))
    )
    (net (code "480") (name "unconnected-(CF12.1-Pad16)") (class "Default")
      (node (ref "CF12.1") (pin "16") (pinfunction "16_16") (pintype "passive"))
    )
    (net (code "481") (name "unconnected-(CF12.1-Pad17)") (class "Default")
      (node (ref "CF12.1") (pin "17") (pinfunction "17_17") (pintype "passive"))
    )
    (net (code "482") (name "unconnected-(CF12.1-Pad18)") (class "Default")
      (node (ref "CF12.1") (pin "18") (pinfunction "18_18") (pintype "passive"))
    )
    (net (code "483") (name "unconnected-(CF12.1-Pad19)") (class "Default")
      (node (ref "CF12.1") (pin "19") (pinfunction "19_19") (pintype "passive"))
    )
    (net (code "484") (name "unconnected-(CF12.1-Pad20)") (class "Default")
      (node (ref "CF12.1") (pin "20") (pinfunction "20_20") (pintype "passive"))
    )
    (net (code "485") (name "unconnected-(CF12.2-Pad17)") (class "Default")
      (node (ref "CF12.2") (pin "17") (pinfunction "17_17") (pintype "passive"))
    )
    (net (code "486") (name "unconnected-(CF12.2-Pad18)") (class "Default")
      (node (ref "CF12.2") (pin "18") (pinfunction "18_18") (pintype "passive"))
    )
    (net (code "487") (name "unconnected-(CF12.2-Pad19)") (class "Default")
      (node (ref "CF12.2") (pin "19") (pinfunction "19_19") (pintype "passive"))
    )
    (net (code "488") (name "unconnected-(CF12.2-Pad20)") (class "Default")
      (node (ref "CF12.2") (pin "20") (pinfunction "20_20") (pintype "passive"))
    )
    (net (code "489") (name "unconnected-(CF12.2-Pad21)") (class "Default")
      (node (ref "CF12.2") (pin "21") (pinfunction "21_21") (pintype "passive"))
    )
    (net (code "490") (name "unconnected-(CF12.2-Pad22)") (class "Default")
      (node (ref "CF12.2") (pin "22") (pinfunction "22_22") (pintype "passive"))
    )
    (net (code "491") (name "unconnected-(CF12.2-Pad23)") (class "Default")
      (node (ref "CF12.2") (pin "23") (pinfunction "23_23") (pintype "passive"))
    )
    (net (code "492") (name "unconnected-(CF12.2-Pad24)") (class "Default")
      (node (ref "CF12.2") (pin "24") (pinfunction "24_24") (pintype "passive"))
    )
    (net (code "493") (name "unconnected-(CF12.2-Pad25)") (class "Default")
      (node (ref "CF12.2") (pin "25") (pinfunction "25_25") (pintype "passive"))
    )
    (net (code "494") (name "unconnected-(CF12.2-Pad26)") (class "Default")
      (node (ref "CF12.2") (pin "26") (pinfunction "26_26") (pintype "passive"))
    )
    (net (code "495") (name "unconnected-(CF12.2-Pad27)") (class "Default")
      (node (ref "CF12.2") (pin "27") (pinfunction "27_27") (pintype "passive"))
    )
    (net (code "496") (name "unconnected-(CF12.2-Pad28)") (class "Default")
      (node (ref "CF12.2") (pin "28") (pinfunction "28_28") (pintype "passive"))
    )
    (net (code "497") (name "unconnected-(CF12.2-Pad29)") (class "Default")
      (node (ref "CF12.2") (pin "29") (pinfunction "29_29") (pintype "passive"))
    )
    (net (code "498") (name "unconnected-(CF12.2-Pad30)") (class "Default")
      (node (ref "CF12.2") (pin "30") (pinfunction "30_30") (pintype "passive"))
    )
    (net (code "499") (name "unconnected-(CF12.2-Pad31)") (class "Default")
      (node (ref "CF12.2") (pin "31") (pinfunction "31_31") (pintype "passive"))
    )
    (net (code "500") (name "unconnected-(CF12.2-Pad32)") (class "Default")
      (node (ref "CF12.2") (pin "32") (pinfunction "32_32") (pintype "passive"))
    )
    (net (code "501") (name "unconnected-(CF12.2-Pad33)") (class "Default")
      (node (ref "CF12.2") (pin "33") (pinfunction "33_33") (pintype "passive"))
    )
    (net (code "502") (name "unconnected-(CF12.2-Pad34)") (class "Default")
      (node (ref "CF12.2") (pin "34") (pinfunction "34_34") (pintype "passive"))
    )
    (net (code "503") (name "unconnected-(CF12.2-Pad35)") (class "Default")
      (node (ref "CF12.2") (pin "35") (pinfunction "35_35") (pintype "passive"))
    )
    (net (code "504") (name "unconnected-(CF12.2-Pad36)") (class "Default")
      (node (ref "CF12.2") (pin "36") (pinfunction "36_36") (pintype "passive"))
    )
    (net (code "505") (name "unconnected-(CF12.2-Pad37)") (class "Default")
      (node (ref "CF12.2") (pin "37") (pinfunction "37_37") (pintype "passive"))
    )
    (net (code "506") (name "unconnected-(CF12.2-Pad38)") (class "Default")
      (node (ref "CF12.2") (pin "38") (pinfunction "38_38") (pintype "passive"))
    )
    (net (code "507") (name "unconnected-(CF12.2-Pad39)") (class "Default")
      (node (ref "CF12.2") (pin "39") (pinfunction "39_39") (pintype "passive"))
    )
    (net (code "508") (name "unconnected-(CF12.2-Pad40)") (class "Default")
      (node (ref "CF12.2") (pin "40") (pinfunction "40_40") (pintype "passive"))
    )
    (net (code "509") (name "unconnected-(CF13.1-Pad1)") (class "Default")
      (node (ref "CF13.1") (pin "1") (pinfunction "1_1") (pintype "passive"))
    )
    (net (code "510") (name "unconnected-(CF13.1-Pad2)") (class "Default")
      (node (ref "CF13.1") (pin "2") (pinfunction "2_2") (pintype "passive"))
    )
    (net (code "511") (name "unconnected-(CF13.1-Pad3)") (class "Default")
      (node (ref "CF13.1") (pin "3") (pinfunction "3_3") (pintype "passive"))
    )
    (net (code "512") (name "unconnected-(CF13.1-Pad4)") (class "Default")
      (node (ref "CF13.1") (pin "4") (pinfunction "4_4") (pintype "passive"))
    )
    (net (code "513") (name "unconnected-(CF13.1-Pad5)") (class "Default")
      (node (ref "CF13.1") (pin "5") (pinfunction "5_5") (pintype "passive"))
    )
    (net (code "514") (name "unconnected-(CF13.1-Pad6)") (class "Default")
      (node (ref "CF13.1") (pin "6") (pinfunction "6_6") (pintype "passive"))
    )
    (net (code "515") (name "unconnected-(CF13.1-Pad7)") (class "Default")
      (node (ref "CF13.1") (pin "7") (pinfunction "7_7") (pintype "passive"))
    )
    (net (code "516") (name "unconnected-(CF13.1-Pad8)") (class "Default")
      (node (ref "CF13.1") (pin "8") (pinfunction "8_8") (pintype "passive"))
    )
    (net (code "517") (name "unconnected-(CF13.1-Pad9)") (class "Default")
      (node (ref "CF13.1") (pin "9") (pinfunction "9_9") (pintype "passive"))
    )
    (net (code "518") (name "unconnected-(CF13.1-Pad10)") (class "Default")
      (node (ref "CF13.1") (pin "10") (pinfunction "10_10") (pintype "passive"))
    )
    (net (code "519") (name "unconnected-(CF13.1-Pad11)") (class "Default")
      (node (ref "CF13.1") (pin "11") (pinfunction "11_11") (pintype "passive"))
    )
    (net (code "520") (name "unconnected-(CF13.1-Pad12)") (class "Default")
      (node (ref "CF13.1") (pin "12") (pinfunction "12_12") (pintype "passive"))
    )
    (net (code "521") (name "unconnected-(CF13.1-Pad13)") (class "Default")
      (node (ref "CF13.1") (pin "13") (pinfunction "13_13") (pintype "passive"))
    )
    (net (code "522") (name "unconnected-(CF13.1-Pad14)") (class "Default")
      (node (ref "CF13.1") (pin "14") (pinfunction "14_14") (pintype "passive"))
    )
    (net (code "523") (name "unconnected-(CF13.1-Pad15)") (class "Default")
      (node (ref "CF13.1") (pin "15") (pinfunction "15_15") (pintype "passive"))
    )
    (net (code "524") (name "unconnected-(CF13.1-Pad16)") (class "Default")
      (node (ref "CF13.1") (pin "16") (pinfunction "16_16") (pintype "passive"))
    )
    (net (code "525") (name "unconnected-(CF13.1-Pad17)") (class "Default")
      (node (ref "CF13.1") (pin "17") (pinfunction "17_17") (pintype "passive"))
    )
    (net (code "526") (name "unconnected-(CF13.1-Pad18)") (class "Default")
      (node (ref "CF13.1") (pin "18") (pinfunction "18_18") (pintype "passive"))
    )
    (net (code "527") (name "unconnected-(CF13.1-Pad19)") (class "Default")
      (node (ref "CF13.1") (pin "19") (pinfunction "19_19") (pintype "passive"))
    )
    (net (code "528") (name "unconnected-(CF13.1-Pad20)") (class "Default")
      (node (ref "CF13.1") (pin "20") (pinfunction "20_20") (pintype "passive"))
    )
    (net (code "529") (name "unconnected-(CF13.2-Pad17)") (class "Default")
      (node (ref "CF13.2") (pin "17") (pinfunction "17_17") (pintype "passive"))
    )
    (net (code "530") (name "unconnected-(CF13.2-Pad18)") (class "Default")
      (node (ref "CF13.2") (pin "18") (pinfunction "18_18") (pintype "passive"))
    )
    (net (code "531") (name "unconnected-(CF13.2-Pad19)") (class "Default")
      (node (ref "CF13.2") (pin "19") (pinfunction "19_19") (pintype "passive"))
    )
    (net (code "532") (name "unconnected-(CF13.2-Pad20)") (class "Default")
      (node (ref "CF13.2") (pin "20") (pinfunction "20_20") (pintype "passive"))
    )
    (net (code "533") (name "unconnected-(CF13.2-Pad21)") (class "Default")
      (node (ref "CF13.2") (pin "21") (pinfunction "21_21") (pintype "passive"))
    )
    (net (code "534") (name "unconnected-(CF13.2-Pad22)") (class "Default")
      (node (ref "CF13.2") (pin "22") (pinfunction "22_22") (pintype "passive"))
    )
    (net (code "535") (name "unconnected-(CF13.2-Pad23)") (class "Default")
      (node (ref "CF13.2") (pin "23") (pinfunction "23_23") (pintype "passive"))
    )
    (net (code "536") (name "unconnected-(CF13.2-Pad24)") (class "Default")
      (node (ref "CF13.2") (pin "24") (pinfunction "24_24") (pintype "passive"))
    )
    (net (code "537") (name "unconnected-(CF13.2-Pad25)") (class "Default")
      (node (ref "CF13.2") (pin "25") (pinfunction "25_25") (pintype "passive"))
    )
    (net (code "538") (name "unconnected-(CF13.2-Pad26)") (class "Default")
      (node (ref "CF13.2") (pin "26") (pinfunction "26_26") (pintype "passive"))
    )
    (net (code "539") (name "unconnected-(CF13.2-Pad27)") (class "Default")
      (node (ref "CF13.2") (pin "27") (pinfunction "27_27") (pintype "passive"))
    )
    (net (code "540") (name "unconnected-(CF13.2-Pad28)") (class "Default")
      (node (ref "CF13.2") (pin "28") (pinfunction "28_28") (pintype "passive"))
    )
    (net (code "541") (name "unconnected-(CF13.2-Pad29)") (class "Default")
      (node (ref "CF13.2") (pin "29") (pinfunction "29_29") (pintype "passive"))
    )
    (net (code "542") (name "unconnected-(CF13.2-Pad30)") (class "Default")
      (node (ref "CF13.2") (pin "30") (pinfunction "30_30") (pintype "passive"))
    )
    (net (code "543") (name "unconnected-(CF13.2-Pad31)") (class "Default")
      (node (ref "CF13.2") (pin "31") (pinfunction "31_31") (pintype "passive"))
    )
    (net (code "544") (name "unconnected-(CF13.2-Pad32)") (class "Default")
      (node (ref "CF13.2") (pin "32") (pinfunction "32_32") (pintype "passive"))
    )
    (net (code "545") (name "unconnected-(CF13.2-Pad33)") (class "Default")
      (node (ref "CF13.2") (pin "33") (pinfunction "33_33") (pintype "passive"))
    )
    (net (code "546") (name "unconnected-(CF13.2-Pad34)") (class "Default")
      (node (ref "CF13.2") (pin "34") (pinfunction "34_34") (pintype "passive"))
    )
    (net (code "547") (name "unconnected-(CF13.2-Pad35)") (class "Default")
      (node (ref "CF13.2") (pin "35") (pinfunction "35_35") (pintype "passive"))
    )
    (net (code "548") (name "unconnected-(CF13.2-Pad36)") (class "Default")
      (node (ref "CF13.2") (pin "36") (pinfunction "36_36") (pintype "passive"))
    )
    (net (code "549") (name "unconnected-(CF13.2-Pad37)") (class "Default")
      (node (ref "CF13.2") (pin "37") (pinfunction "37_37") (pintype "passive"))
    )
    (net (code "550") (name "unconnected-(CF13.2-Pad38)") (class "Default")
      (node (ref "CF13.2") (pin "38") (pinfunction "38_38") (pintype "passive"))
    )
    (net (code "551") (name "unconnected-(CF13.2-Pad39)") (class "Default")
      (node (ref "CF13.2") (pin "39") (pinfunction "39_39") (pintype "passive"))
    )
    (net (code "552") (name "unconnected-(CF13.2-Pad40)") (class "Default")
      (node (ref "CF13.2") (pin "40") (pinfunction "40_40") (pintype "passive"))
    )
    (net (code "553") (name "unconnected-(CF14.1-Pad1)") (class "Default")
      (node (ref "CF14.1") (pin "1") (pinfunction "1_1") (pintype "passive"))
    )
    (net (code "554") (name "unconnected-(CF14.1-Pad2)") (class "Default")
      (node (ref "CF14.1") (pin "2") (pinfunction "2_2") (pintype "passive"))
    )
    (net (code "555") (name "unconnected-(CF14.1-Pad3)") (class "Default")
      (node (ref "CF14.1") (pin "3") (pinfunction "3_3") (pintype "passive"))
    )
    (net (code "556") (name "unconnected-(CF14.1-Pad4)") (class "Default")
      (node (ref "CF14.1") (pin "4") (pinfunction "4_4") (pintype "passive"))
    )
    (net (code "557") (name "unconnected-(CF14.1-Pad5)") (class "Default")
      (node (ref "CF14.1") (pin "5") (pinfunction "5_5") (pintype "passive"))
    )
    (net (code "558") (name "unconnected-(CF14.1-Pad6)") (class "Default")
      (node (ref "CF14.1") (pin "6") (pinfunction "6_6") (pintype "passive"))
    )
    (net (code "559") (name "unconnected-(CF14.1-Pad7)") (class "Default")
      (node (ref "CF14.1") (pin "7") (pinfunction "7_7") (pintype "passive"))
    )
    (net (code "560") (name "unconnected-(CF14.1-Pad8)") (class "Default")
      (node (ref "CF14.1") (pin "8") (pinfunction "8_8") (pintype "passive"))
    )
    (net (code "561") (name "unconnected-(CF14.1-Pad9)") (class "Default")
      (node (ref "CF14.1") (pin "9") (pinfunction "9_9") (pintype "passive"))
    )
    (net (code "562") (name "unconnected-(CF14.1-Pad10)") (class "Default")
      (node (ref "CF14.1") (pin "10") (pinfunction "10_10") (pintype "passive"))
    )
    (net (code "563") (name "unconnected-(CF14.1-Pad11)") (class "Default")
      (node (ref "CF14.1") (pin "11") (pinfunction "11_11") (pintype "passive"))
    )
    (net (code "564") (name "unconnected-(CF14.1-Pad12)") (class "Default")
      (node (ref "CF14.1") (pin "12") (pinfunction "12_12") (pintype "passive"))
    )
    (net (code "565") (name "unconnected-(CF14.1-Pad13)") (class "Default")
      (node (ref "CF14.1") (pin "13") (pinfunction "13_13") (pintype "passive"))
    )
    (net (code "566") (name "unconnected-(CF14.1-Pad14)") (class "Default")
      (node (ref "CF14.1") (pin "14") (pinfunction "14_14") (pintype "passive"))
    )
    (net (code "567") (name "unconnected-(CF14.1-Pad15)") (class "Default")
      (node (ref "CF14.1") (pin "15") (pinfunction "15_15") (pintype "passive"))
    )
    (net (code "568") (name "unconnected-(CF14.1-Pad16)") (class "Default")
      (node (ref "CF14.1") (pin "16") (pinfunction "16_16") (pintype "passive"))
    )
    (net (code "569") (name "unconnected-(CF14.1-Pad17)") (class "Default")
      (node (ref "CF14.1") (pin "17") (pinfunction "17_17") (pintype "passive"))
    )
    (net (code "570") (name "unconnected-(CF14.1-Pad18)") (class "Default")
      (node (ref "CF14.1") (pin "18") (pinfunction "18_18") (pintype "passive"))
    )
    (net (code "571") (name "unconnected-(CF14.1-Pad19)") (class "Default")
      (node (ref "CF14.1") (pin "19") (pinfunction "19_19") (pintype "passive"))
    )
    (net (code "572") (name "unconnected-(CF14.1-Pad20)") (class "Default")
      (node (ref "CF14.1") (pin "20") (pinfunction "20_20") (pintype "passive"))
    )
    (net (code "573") (name "unconnected-(CF14.2-Pad17)") (class "Default")
      (node (ref "CF14.2") (pin "17") (pinfunction "17_17") (pintype "passive"))
    )
    (net (code "574") (name "unconnected-(CF14.2-Pad18)") (class "Default")
      (node (ref "CF14.2") (pin "18") (pinfunction "18_18") (pintype "passive"))
    )
    (net (code "575") (name "unconnected-(CF14.2-Pad19)") (class "Default")
      (node (ref "CF14.2") (pin "19") (pinfunction "19_19") (pintype "passive"))
    )
    (net (code "576") (name "unconnected-(CF14.2-Pad20)") (class "Default")
      (node (ref "CF14.2") (pin "20") (pinfunction "20_20") (pintype "passive"))
    )
    (net (code "577") (name "unconnected-(CF14.2-Pad21)") (class "Default")
      (node (ref "CF14.2") (pin "21") (pinfunction "21_21") (pintype "passive"))
    )
    (net (code "578") (name "unconnected-(CF14.2-Pad22)") (class "Default")
      (node (ref "CF14.2") (pin "22") (pinfunction "22_22") (pintype "passive"))
    )
    (net (code "579") (name "unconnected-(CF14.2-Pad23)") (class "Default")
      (node (ref "CF14.2") (pin "23") (pinfunction "23_23") (pintype "passive"))
    )
    (net (code "580") (name "unconnected-(CF14.2-Pad24)") (class "Default")
      (node (ref "CF14.2") (pin "24") (pinfunction "24_24") (pintype "passive"))
    )
    (net (code "581") (name "unconnected-(CF14.2-Pad25)") (class "Default")
      (node (ref "CF14.2") (pin "25") (pinfunction "25_25") (pintype "passive"))
    )
    (net (code "582") (name "unconnected-(CF14.2-Pad26)") (class "Default")
      (node (ref "CF14.2") (pin "26") (pinfunction "26_26") (pintype "passive"))
    )
    (net (code "583") (name "unconnected-(CF14.2-Pad27)") (class "Default")
      (node (ref "CF14.2") (pin "27") (pinfunction "27_27") (pintype "passive"))
    )
    (net (code "584") (name "unconnected-(CF14.2-Pad28)") (class "Default")
      (node (ref "CF14.2") (pin "28") (pinfunction "28_28") (pintype "passive"))
    )
    (net (code "585") (name "unconnected-(CF14.2-Pad29)") (class "Default")
      (node (ref "CF14.2") (pin "29") (pinfunction "29_29") (pintype "passive"))
    )
    (net (code "586") (name "unconnected-(CF14.2-Pad30)") (class "Default")
      (node (ref "CF14.2") (pin "30") (pinfunction "30_30") (pintype "passive"))
    )
    (net (code "587") (name "unconnected-(CF14.2-Pad31)") (class "Default")
      (node (ref "CF14.2") (pin "31") (pinfunction "31_31") (pintype "passive"))
    )
    (net (code "588") (name "unconnected-(CF14.2-Pad32)") (class "Default")
      (node (ref "CF14.2") (pin "32") (pinfunction "32_32") (pintype "passive"))
    )
    (net (code "589") (name "unconnected-(CF14.2-Pad33)") (class "Default")
      (node (ref "CF14.2") (pin "33") (pinfunction "33_33") (pintype "passive"))
    )
    (net (code "590") (name "unconnected-(CF14.2-Pad34)") (class "Default")
      (node (ref "CF14.2") (pin "34") (pinfunction "34_34") (pintype "passive"))
    )
    (net (code "591") (name "unconnected-(CF14.2-Pad35)") (class "Default")
      (node (ref "CF14.2") (pin "35") (pinfunction "35_35") (pintype "passive"))
    )
    (net (code "592") (name "unconnected-(CF14.2-Pad36)") (class "Default")
      (node (ref "CF14.2") (pin "36") (pinfunction "36_36") (pintype "passive"))
    )
    (net (code "593") (name "unconnected-(CF14.2-Pad37)") (class "Default")
      (node (ref "CF14.2") (pin "37") (pinfunction "37_37") (pintype "passive"))
    )
    (net (code "594") (name "unconnected-(CF14.2-Pad38)") (class "Default")
      (node (ref "CF14.2") (pin "38") (pinfunction "38_38") (pintype "passive"))
    )
    (net (code "595") (name "unconnected-(CF14.2-Pad39)") (class "Default")
      (node (ref "CF14.2") (pin "39") (pinfunction "39_39") (pintype "passive"))
    )
    (net (code "596") (name "unconnected-(CF14.2-Pad40)") (class "Default")
      (node (ref "CF14.2") (pin "40") (pinfunction "40_40") (pintype "passive"))
    )
    (net (code "597") (name "unconnected-(CF15.1-Pad1)") (class "Default")
      (node (ref "CF15.1") (pin "1") (pinfunction "1_1") (pintype "passive"))
    )
    (net (code "598") (name "unconnected-(CF15.1-Pad2)") (class "Default")
      (node (ref "CF15.1") (pin "2") (pinfunction "2_2") (pintype "passive"))
    )
    (net (code "599") (name "unconnected-(CF15.1-Pad3)") (class "Default")
      (node (ref "CF15.1") (pin "3") (pinfunction "3_3") (pintype "passive"))
    )
    (net (code "600") (name "unconnected-(CF15.1-Pad4)") (class "Default")
      (node (ref "CF15.1") (pin "4") (pinfunction "4_4") (pintype "passive"))
    )
    (net (code "601") (name "unconnected-(CF15.1-Pad5)") (class "Default")
      (node (ref "CF15.1") (pin "5") (pinfunction "5_5") (pintype "passive"))
    )
    (net (code "602") (name "unconnected-(CF15.1-Pad6)") (class "Default")
      (node (ref "CF15.1") (pin "6") (pinfunction "6_6") (pintype "passive"))
    )
    (net (code "603") (name "unconnected-(CF15.1-Pad7)") (class "Default")
      (node (ref "CF15.1") (pin "7") (pinfunction "7_7") (pintype "passive"))
    )
    (net (code "604") (name "unconnected-(CF15.1-Pad8)") (class "Default")
      (node (ref "CF15.1") (pin "8") (pinfunction "8_8") (pintype "passive"))
    )
    (net (code "605") (name "unconnected-(CF15.1-Pad9)") (class "Default")
      (node (ref "CF15.1") (pin "9") (pinfunction "9_9") (pintype "passive"))
    )
    (net (code "606") (name "unconnected-(CF15.1-Pad10)") (class "Default")
      (node (ref "CF15.1") (pin "10") (pinfunction "10_10") (pintype "passive"))
    )
    (net (code "607") (name "unconnected-(CF15.1-Pad11)") (class "Default")
      (node (ref "CF15.1") (pin "11") (pinfunction "11_11") (pintype "passive"))
    )
    (net (code "608") (name "unconnected-(CF15.1-Pad12)") (class "Default")
      (node (ref "CF15.1") (pin "12") (pinfunction "12_12") (pintype "passive"))
    )
    (net (code "609") (name "unconnected-(CF15.1-Pad13)") (class "Default")
      (node (ref "CF15.1") (pin "13") (pinfunction "13_13") (pintype "passive"))
    )
    (net (code "610") (name "unconnected-(CF15.1-Pad14)") (class "Default")
      (node (ref "CF15.1") (pin "14") (pinfunction "14_14") (pintype "passive"))
    )
    (net (code "611") (name "unconnected-(CF15.1-Pad15)") (class "Default")
      (node (ref "CF15.1") (pin "15") (pinfunction "15_15") (pintype "passive"))
    )
    (net (code "612") (name "unconnected-(CF15.1-Pad16)") (class "Default")
      (node (ref "CF15.1") (pin "16") (pinfunction "16_16") (pintype "passive"))
    )
    (net (code "613") (name "unconnected-(CF15.1-Pad17)") (class "Default")
      (node (ref "CF15.1") (pin "17") (pinfunction "17_17") (pintype "passive"))
    )
    (net (code "614") (name "unconnected-(CF15.1-Pad18)") (class "Default")
      (node (ref "CF15.1") (pin "18") (pinfunction "18_18") (pintype "passive"))
    )
    (net (code "615") (name "unconnected-(CF15.1-Pad19)") (class "Default")
      (node (ref "CF15.1") (pin "19") (pinfunction "19_19") (pintype "passive"))
    )
    (net (code "616") (name "unconnected-(CF15.1-Pad20)") (class "Default")
      (node (ref "CF15.1") (pin "20") (pinfunction "20_20") (pintype "passive"))
    )
    (net (code "617") (name "unconnected-(CF15.2-Pad17)") (class "Default")
      (node (ref "CF15.2") (pin "17") (pinfunction "17_17") (pintype "passive"))
    )
    (net (code "618") (name "unconnected-(CF15.2-Pad18)") (class "Default")
      (node (ref "CF15.2") (pin "18") (pinfunction "18_18") (pintype "passive"))
    )
    (net (code "619") (name "unconnected-(CF15.2-Pad19)") (class "Default")
      (node (ref "CF15.2") (pin "19") (pinfunction "19_19") (pintype "passive"))
    )
    (net (code "620") (name "unconnected-(CF15.2-Pad20)") (class "Default")
      (node (ref "CF15.2") (pin "20") (pinfunction "20_20") (pintype "passive"))
    )
    (net (code "621") (name "unconnected-(CF15.2-Pad21)") (class "Default")
      (node (ref "CF15.2") (pin "21") (pinfunction "21_21") (pintype "passive"))
    )
    (net (code "622") (name "unconnected-(CF15.2-Pad22)") (class "Default")
      (node (ref "CF15.2") (pin "22") (pinfunction "22_22") (pintype "passive"))
    )
    (net (code "623") (name "unconnected-(CF15.2-Pad23)") (class "Default")
      (node (ref "CF15.2") (pin "23") (pinfunction "23_23") (pintype "passive"))
    )
    (net (code "624") (name "unconnected-(CF15.2-Pad24)") (class "Default")
      (node (ref "CF15.2") (pin "24") (pinfunction "24_24") (pintype "passive"))
    )
    (net (code "625") (name "unconnected-(CF15.2-Pad25)") (class "Default")
      (node (ref "CF15.2") (pin "25") (pinfunction "25_25") (pintype "passive"))
    )
    (net (code "626") (name "unconnected-(CF15.2-Pad26)") (class "Default")
      (node (ref "CF15.2") (pin "26") (pinfunction "26_26") (pintype "passive"))
    )
    (net (code "627") (name "unconnected-(CF15.2-Pad27)") (class "Default")
      (node (ref "CF15.2") (pin "27") (pinfunction "27_27") (pintype "passive"))
    )
    (net (code "628") (name "unconnected-(CF15.2-Pad28)") (class "Default")
      (node (ref "CF15.2") (pin "28") (pinfunction "28_28") (pintype "passive"))
    )
    (net (code "629") (name "unconnected-(CF15.2-Pad29)") (class "Default")
      (node (ref "CF15.2") (pin "29") (pinfunction "29_29") (pintype "passive"))
    )
    (net (code "630") (name "unconnected-(CF15.2-Pad30)") (class "Default")
      (node (ref "CF15.2") (pin "30") (pinfunction "30_30") (pintype "passive"))
    )
    (net (code "631") (name "unconnected-(CF15.2-Pad31)") (class "Default")
      (node (ref "CF15.2") (pin "31") (pinfunction "31_31") (pintype "passive"))
    )
    (net (code "632") (name "unconnected-(CF15.2-Pad32)") (class "Default")
      (node (ref "CF15.2") (pin "32") (pinfunction "32_32") (pintype "passive"))
    )
    (net (code "633") (name "unconnected-(CF15.2-Pad33)") (class "Default")
      (node (ref "CF15.2") (pin "33") (pinfunction "33_33") (pintype "passive"))
    )
    (net (code "634") (name "unconnected-(CF15.2-Pad34)") (class "Default")
      (node (ref "CF15.2") (pin "34") (pinfunction "34_34") (pintype "passive"))
    )
    (net (code "635") (name "unconnected-(CF15.2-Pad35)") (class "Default")
      (node (ref "CF15.2") (pin "35") (pinfunction "35_35") (pintype "passive"))
    )
    (net (code "636") (name "unconnected-(CF15.2-Pad36)") (class "Default")
      (node (ref "CF15.2") (pin "36") (pinfunction "36_36") (pintype "passive"))
    )
    (net (code "637") (name "unconnected-(CF15.2-Pad37)") (class "Default")
      (node (ref "CF15.2") (pin "37") (pinfunction "37_37") (pintype "passive"))
    )
    (net (code "638") (name "unconnected-(CF15.2-Pad38)") (class "Default")
      (node (ref "CF15.2") (pin "38") (pinfunction "38_38") (pintype "passive"))
    )
    (net (code "639") (name "unconnected-(CF15.2-Pad39)") (class "Default")
      (node (ref "CF15.2") (pin "39") (pinfunction "39_39") (pintype "passive"))
    )
    (net (code "640") (name "unconnected-(CF15.2-Pad40)") (class "Default")
      (node (ref "CF15.2") (pin "40") (pinfunction "40_40") (pintype "passive"))
    )
    (net (code "641") (name "unconnected-(CF16.1-Pad1)") (class "Default")
      (node (ref "CF16.1") (pin "1") (pinfunction "1_1") (pintype "passive"))
    )
    (net (code "642") (name "unconnected-(CF16.1-Pad2)") (class "Default")
      (node (ref "CF16.1") (pin "2") (pinfunction "2_2") (pintype "passive"))
    )
    (net (code "643") (name "unconnected-(CF16.1-Pad3)") (class "Default")
      (node (ref "CF16.1") (pin "3") (pinfunction "3_3") (pintype "passive"))
    )
    (net (code "644") (name "unconnected-(CF16.1-Pad4)") (class "Default")
      (node (ref "CF16.1") (pin "4") (pinfunction "4_4") (pintype "passive"))
    )
    (net (code "645") (name "unconnected-(CF16.1-Pad5)") (class "Default")
      (node (ref "CF16.1") (pin "5") (pinfunction "5_5") (pintype "passive"))
    )
    (net (code "646") (name "unconnected-(CF16.1-Pad6)") (class "Default")
      (node (ref "CF16.1") (pin "6") (pinfunction "6_6") (pintype "passive"))
    )
    (net (code "647") (name "unconnected-(CF16.1-Pad7)") (class "Default")
      (node (ref "CF16.1") (pin "7") (pinfunction "7_7") (pintype "passive"))
    )
    (net (code "648") (name "unconnected-(CF16.1-Pad8)") (class "Default")
      (node (ref "CF16.1") (pin "8") (pinfunction "8_8") (pintype "passive"))
    )
    (net (code "649") (name "unconnected-(CF16.1-Pad9)") (class "Default")
      (node (ref "CF16.1") (pin "9") (pinfunction "9_9") (pintype "passive"))
    )
    (net (code "650") (name "unconnected-(CF16.1-Pad10)") (class "Default")
      (node (ref "CF16.1") (pin "10") (pinfunction "10_10") (pintype "passive"))
    )
    (net (code "651") (name "unconnected-(CF16.1-Pad11)") (class "Default")
      (node (ref "CF16.1") (pin "11") (pinfunction "11_11") (pintype "passive"))
    )
    (net (code "652") (name "unconnected-(CF16.1-Pad12)") (class "Default")
      (node (ref "CF16.1") (pin "12") (pinfunction "12_12") (pintype "passive"))
    )
    (net (code "653") (name "unconnected-(CF16.1-Pad13)") (class "Default")
      (node (ref "CF16.1") (pin "13") (pinfunction "13_13") (pintype "passive"))
    )
    (net (code "654") (name "unconnected-(CF16.1-Pad14)") (class "Default")
      (node (ref "CF16.1") (pin "14") (pinfunction "14_14") (pintype "passive"))
    )
    (net (code "655") (name "unconnected-(CF16.1-Pad15)") (class "Default")
      (node (ref "CF16.1") (pin "15") (pinfunction "15_15") (pintype "passive"))
    )
    (net (code "656") (name "unconnected-(CF16.1-Pad16)") (class "Default")
      (node (ref "CF16.1") (pin "16") (pinfunction "16_16") (pintype "passive"))
    )
    (net (code "657") (name "unconnected-(CF16.1-Pad17)") (class "Default")
      (node (ref "CF16.1") (pin "17") (pinfunction "17_17") (pintype "passive"))
    )
    (net (code "658") (name "unconnected-(CF16.1-Pad18)") (class "Default")
      (node (ref "CF16.1") (pin "18") (pinfunction "18_18") (pintype "passive"))
    )
    (net (code "659") (name "unconnected-(CF16.1-Pad19)") (class "Default")
      (node (ref "CF16.1") (pin "19") (pinfunction "19_19") (pintype "passive"))
    )
    (net (code "660") (name "unconnected-(CF16.1-Pad20)") (class "Default")
      (node (ref "CF16.1") (pin "20") (pinfunction "20_20") (pintype "passive"))
    )
    (net (code "661") (name "unconnected-(CF16.2-Pad17)") (class "Default")
      (node (ref "CF16.2") (pin "17") (pinfunction "17_17") (pintype "passive"))
    )
    (net (code "662") (name "unconnected-(CF16.2-Pad18)") (class "Default")
      (node (ref "CF16.2") (pin "18") (pinfunction "18_18") (pintype "passive"))
    )
    (net (code "663") (name "unconnected-(CF16.2-Pad19)") (class "Default")
      (node (ref "CF16.2") (pin "19") (pinfunction "19_19") (pintype "passive"))
    )
    (net (code "664") (name "unconnected-(CF16.2-Pad20)") (class "Default")
      (node (ref "CF16.2") (pin "20") (pinfunction "20_20") (pintype "passive"))
    )
    (net (code "665") (name "unconnected-(CF16.2-Pad21)") (class "Default")
      (node (ref "CF16.2") (pin "21") (pinfunction "21_21") (pintype "passive"))
    )
    (net (code "666") (name "unconnected-(CF16.2-Pad22)") (class "Default")
      (node (ref "CF16.2") (pin "22") (pinfunction "22_22") (pintype "passive"))
    )
    (net (code "667") (name "unconnected-(CF16.2-Pad23)") (class "Default")
      (node (ref "CF16.2") (pin "23") (pinfunction "23_23") (pintype "passive"))
    )
    (net (code "668") (name "unconnected-(CF16.2-Pad24)") (class "Default")
      (node (ref "CF16.2") (pin "24") (pinfunction "24_24") (pintype "passive"))
    )
    (net (code "669") (name "unconnected-(CF16.2-Pad25)") (class "Default")
      (node (ref "CF16.2") (pin "25") (pinfunction "25_25") (pintype "passive"))
    )
    (net (code "670") (name "unconnected-(CF16.2-Pad26)") (class "Default")
      (node (ref "CF16.2") (pin "26") (pinfunction "26_26") (pintype "passive"))
    )
    (net (code "671") (name "unconnected-(CF16.2-Pad27)") (class "Default")
      (node (ref "CF16.2") (pin "27") (pinfunction "27_27") (pintype "passive"))
    )
    (net (code "672") (name "unconnected-(CF16.2-Pad28)") (class "Default")
      (node (ref "CF16.2") (pin "28") (pinfunction "28_28") (pintype "passive"))
    )
    (net (code "673") (name "unconnected-(CF16.2-Pad29)") (class "Default")
      (node (ref "CF16.2") (pin "29") (pinfunction "29_29") (pintype "passive"))
    )
    (net (code "674") (name "unconnected-(CF16.2-Pad30)") (class "Default")
      (node (ref "CF16.2") (pin "30") (pinfunction "30_30") (pintype "passive"))
    )
    (net (code "675") (name "unconnected-(CF16.2-Pad31)") (class "Default")
      (node (ref "CF16.2") (pin "31") (pinfunction "31_31") (pintype "passive"))
    )
    (net (code "676") (name "unconnected-(CF16.2-Pad32)") (class "Default")
      (node (ref "CF16.2") (pin "32") (pinfunction "32_32") (pintype "passive"))
    )
    (net (code "677") (name "unconnected-(CF16.2-Pad33)") (class "Default")
      (node (ref "CF16.2") (pin "33") (pinfunction "33_33") (pintype "passive"))
    )
    (net (code "678") (name "unconnected-(CF16.2-Pad34)") (class "Default")
      (node (ref "CF16.2") (pin "34") (pinfunction "34_34") (pintype "passive"))
    )
    (net (code "679") (name "unconnected-(CF16.2-Pad35)") (class "Default")
      (node (ref "CF16.2") (pin "35") (pinfunction "35_35") (pintype "passive"))
    )
    (net (code "680") (name "unconnected-(CF16.2-Pad36)") (class "Default")
      (node (ref "CF16.2") (pin "36") (pinfunction "36_36") (pintype "passive"))
    )
    (net (code "681") (name "unconnected-(CF16.2-Pad37)") (class "Default")
      (node (ref "CF16.2") (pin "37") (pinfunction "37_37") (pintype "passive"))
    )
    (net (code "682") (name "unconnected-(CF16.2-Pad38)") (class "Default")
      (node (ref "CF16.2") (pin "38") (pinfunction "38_38") (pintype "passive"))
    )
    (net (code "683") (name "unconnected-(CF16.2-Pad39)") (class "Default")
      (node (ref "CF16.2") (pin "39") (pinfunction "39_39") (pintype "passive"))
    )
    (net (code "684") (name "unconnected-(CF16.2-Pad40)") (class "Default")
      (node (ref "CF16.2") (pin "40") (pinfunction "40_40") (pintype "passive"))
    )
    (net (code "685") (name "unconnected-(CF17.1-Pad1)") (class "Default")
      (node (ref "CF17.1") (pin "1") (pinfunction "1_1") (pintype "passive"))
    )
    (net (code "686") (name "unconnected-(CF17.1-Pad2)") (class "Default")
      (node (ref "CF17.1") (pin "2") (pinfunction "2_2") (pintype "passive"))
    )
    (net (code "687") (name "unconnected-(CF17.1-Pad3)") (class "Default")
      (node (ref "CF17.1") (pin "3") (pinfunction "3_3") (pintype "passive"))
    )
    (net (code "688") (name "unconnected-(CF17.1-Pad4)") (class "Default")
      (node (ref "CF17.1") (pin "4") (pinfunction "4_4") (pintype "passive"))
    )
    (net (code "689") (name "unconnected-(CF17.1-Pad5)") (class "Default")
      (node (ref "CF17.1") (pin "5") (pinfunction "5_5") (pintype "passive"))
    )
    (net (code "690") (name "unconnected-(CF17.1-Pad6)") (class "Default")
      (node (ref "CF17.1") (pin "6") (pinfunction "6_6") (pintype "passive"))
    )
    (net (code "691") (name "unconnected-(CF17.1-Pad7)") (class "Default")
      (node (ref "CF17.1") (pin "7") (pinfunction "7_7") (pintype "passive"))
    )
    (net (code "692") (name "unconnected-(CF17.1-Pad8)") (class "Default")
      (node (ref "CF17.1") (pin "8") (pinfunction "8_8") (pintype "passive"))
    )
    (net (code "693") (name "unconnected-(CF17.1-Pad9)") (class "Default")
      (node (ref "CF17.1") (pin "9") (pinfunction "9_9") (pintype "passive"))
    )
    (net (code "694") (name "unconnected-(CF17.1-Pad10)") (class "Default")
      (node (ref "CF17.1") (pin "10") (pinfunction "10_10") (pintype "passive"))
    )
    (net (code "695") (name "unconnected-(CF17.1-Pad11)") (class "Default")
      (node (ref "CF17.1") (pin "11") (pinfunction "11_11") (pintype "passive"))
    )
    (net (code "696") (name "unconnected-(CF17.1-Pad12)") (class "Default")
      (node (ref "CF17.1") (pin "12") (pinfunction "12_12") (pintype "passive"))
    )
    (net (code "697") (name "unconnected-(CF17.1-Pad13)") (class "Default")
      (node (ref "CF17.1") (pin "13") (pinfunction "13_13") (pintype "passive"))
    )
    (net (code "698") (name "unconnected-(CF17.1-Pad14)") (class "Default")
      (node (ref "CF17.1") (pin "14") (pinfunction "14_14") (pintype "passive"))
    )
    (net (code "699") (name "unconnected-(CF17.1-Pad15)") (class "Default")
      (node (ref "CF17.1") (pin "15") (pinfunction "15_15") (pintype "passive"))
    )
    (net (code "700") (name "unconnected-(CF17.1-Pad16)") (class "Default")
      (node (ref "CF17.1") (pin "16") (pinfunction "16_16") (pintype "passive"))
    )
    (net (code "701") (name "unconnected-(CF17.1-Pad17)") (class "Default")
      (node (ref "CF17.1") (pin "17") (pinfunction "17_17") (pintype "passive"))
    )
    (net (code "702") (name "unconnected-(CF17.1-Pad18)") (class "Default")
      (node (ref "CF17.1") (pin "18") (pinfunction "18_18") (pintype "passive"))
    )
    (net (code "703") (name "unconnected-(CF17.1-Pad19)") (class "Default")
      (node (ref "CF17.1") (pin "19") (pinfunction "19_19") (pintype "passive"))
    )
    (net (code "704") (name "unconnected-(CF17.1-Pad20)") (class "Default")
      (node (ref "CF17.1") (pin "20") (pinfunction "20_20") (pintype "passive"))
    )
    (net (code "705") (name "unconnected-(CF17.2-Pad17)") (class "Default")
      (node (ref "CF17.2") (pin "17") (pinfunction "17_17") (pintype "passive"))
    )
    (net (code "706") (name "unconnected-(CF17.2-Pad18)") (class "Default")
      (node (ref "CF17.2") (pin "18") (pinfunction "18_18") (pintype "passive"))
    )
    (net (code "707") (name "unconnected-(CF17.2-Pad19)") (class "Default")
      (node (ref "CF17.2") (pin "19") (pinfunction "19_19") (pintype "passive"))
    )
    (net (code "708") (name "unconnected-(CF17.2-Pad20)") (class "Default")
      (node (ref "CF17.2") (pin "20") (pinfunction "20_20") (pintype "passive"))
    )
    (net (code "709") (name "unconnected-(CF17.2-Pad21)") (class "Default")
      (node (ref "CF17.2") (pin "21") (pinfunction "21_21") (pintype "passive"))
    )
    (net (code "710") (name "unconnected-(CF17.2-Pad22)") (class "Default")
      (node (ref "CF17.2") (pin "22") (pinfunction "22_22") (pintype "passive"))
    )
    (net (code "711") (name "unconnected-(CF17.2-Pad23)") (class "Default")
      (node (ref "CF17.2") (pin "23") (pinfunction "23_23") (pintype "passive"))
    )
    (net (code "712") (name "unconnected-(CF17.2-Pad24)") (class "Default")
      (node (ref "CF17.2") (pin "24") (pinfunction "24_24") (pintype "passive"))
    )
    (net (code "713") (name "unconnected-(CF17.2-Pad25)") (class "Default")
      (node (ref "CF17.2") (pin "25") (pinfunction "25_25") (pintype "passive"))
    )
    (net (code "714") (name "unconnected-(CF17.2-Pad26)") (class "Default")
      (node (ref "CF17.2") (pin "26") (pinfunction "26_26") (pintype "passive"))
    )
    (net (code "715") (name "unconnected-(CF17.2-Pad27)") (class "Default")
      (node (ref "CF17.2") (pin "27") (pinfunction "27_27") (pintype "passive"))
    )
    (net (code "716") (name "unconnected-(CF17.2-Pad28)") (class "Default")
      (node (ref "CF17.2") (pin "28") (pinfunction "28_28") (pintype "passive"))
    )
    (net (code "717") (name "unconnected-(CF17.2-Pad29)") (class "Default")
      (node (ref "CF17.2") (pin "29") (pinfunction "29_29") (pintype "passive"))
    )
    (net (code "718") (name "unconnected-(CF17.2-Pad30)") (class "Default")
      (node (ref "CF17.2") (pin "30") (pinfunction "30_30") (pintype "passive"))
    )
    (net (code "719") (name "unconnected-(CF17.2-Pad31)") (class "Default")
      (node (ref "CF17.2") (pin "31") (pinfunction "31_31") (pintype "passive"))
    )
    (net (code "720") (name "unconnected-(CF17.2-Pad32)") (class "Default")
      (node (ref "CF17.2") (pin "32") (pinfunction "32_32") (pintype "passive"))
    )
    (net (code "721") (name "unconnected-(CF17.2-Pad33)") (class "Default")
      (node (ref "CF17.2") (pin "33") (pinfunction "33_33") (pintype "passive"))
    )
    (net (code "722") (name "unconnected-(CF17.2-Pad34)") (class "Default")
      (node (ref "CF17.2") (pin "34") (pinfunction "34_34") (pintype "passive"))
    )
    (net (code "723") (name "unconnected-(CF17.2-Pad35)") (class "Default")
      (node (ref "CF17.2") (pin "35") (pinfunction "35_35") (pintype "passive"))
    )
    (net (code "724") (name "unconnected-(CF17.2-Pad36)") (class "Default")
      (node (ref "CF17.2") (pin "36") (pinfunction "36_36") (pintype "passive"))
    )
    (net (code "725") (name "unconnected-(CF17.2-Pad37)") (class "Default")
      (node (ref "CF17.2") (pin "37") (pinfunction "37_37") (pintype "passive"))
    )
    (net (code "726") (name "unconnected-(CF17.2-Pad38)") (class "Default")
      (node (ref "CF17.2") (pin "38") (pinfunction "38_38") (pintype "passive"))
    )
    (net (code "727") (name "unconnected-(CF17.2-Pad39)") (class "Default")
      (node (ref "CF17.2") (pin "39") (pinfunction "39_39") (pintype "passive"))
    )
    (net (code "728") (name "unconnected-(CF17.2-Pad40)") (class "Default")
      (node (ref "CF17.2") (pin "40") (pinfunction "40_40") (pintype "passive"))
    )
    (net (code "729") (name "unconnected-(CF18.1-Pad1)") (class "Default")
      (node (ref "CF18.1") (pin "1") (pinfunction "1_1") (pintype "passive"))
    )
    (net (code "730") (name "unconnected-(CF18.1-Pad2)") (class "Default")
      (node (ref "CF18.1") (pin "2") (pinfunction "2_2") (pintype "passive"))
    )
    (net (code "731") (name "unconnected-(CF18.1-Pad3)") (class "Default")
      (node (ref "CF18.1") (pin "3") (pinfunction "3_3") (pintype "passive"))
    )
    (net (code "732") (name "unconnected-(CF18.1-Pad4)") (class "Default")
      (node (ref "CF18.1") (pin "4") (pinfunction "4_4") (pintype "passive"))
    )
    (net (code "733") (name "unconnected-(CF18.1-Pad5)") (class "Default")
      (node (ref "CF18.1") (pin "5") (pinfunction "5_5") (pintype "passive"))
    )
    (net (code "734") (name "unconnected-(CF18.1-Pad6)") (class "Default")
      (node (ref "CF18.1") (pin "6") (pinfunction "6_6") (pintype "passive"))
    )
    (net (code "735") (name "unconnected-(CF18.1-Pad7)") (class "Default")
      (node (ref "CF18.1") (pin "7") (pinfunction "7_7") (pintype "passive"))
    )
    (net (code "736") (name "unconnected-(CF18.1-Pad8)") (class "Default")
      (node (ref "CF18.1") (pin "8") (pinfunction "8_8") (pintype "passive"))
    )
    (net (code "737") (name "unconnected-(CF18.1-Pad9)") (class "Default")
      (node (ref "CF18.1") (pin "9") (pinfunction "9_9") (pintype "passive"))
    )
    (net (code "738") (name "unconnected-(CF18.1-Pad10)") (class "Default")
      (node (ref "CF18.1") (pin "10") (pinfunction "10_10") (pintype "passive"))
    )
    (net (code "739") (name "unconnected-(CF18.1-Pad11)") (class "Default")
      (node (ref "CF18.1") (pin "11") (pinfunction "11_11") (pintype "passive"))
    )
    (net (code "740") (name "unconnected-(CF18.1-Pad12)") (class "Default")
      (node (ref "CF18.1") (pin "12") (pinfunction "12_12") (pintype "passive"))
    )
    (net (code "741") (name "unconnected-(CF18.1-Pad13)") (class "Default")
      (node (ref "CF18.1") (pin "13") (pinfunction "13_13") (pintype "passive"))
    )
    (net (code "742") (name "unconnected-(CF18.1-Pad14)") (class "Default")
      (node (ref "CF18.1") (pin "14") (pinfunction "14_14") (pintype "passive"))
    )
    (net (code "743") (name "unconnected-(CF18.1-Pad15)") (class "Default")
      (node (ref "CF18.1") (pin "15") (pinfunction "15_15") (pintype "passive"))
    )
    (net (code "744") (name "unconnected-(CF18.1-Pad16)") (class "Default")
      (node (ref "CF18.1") (pin "16") (pinfunction "16_16") (pintype "passive"))
    )
    (net (code "745") (name "unconnected-(CF18.1-Pad17)") (class "Default")
      (node (ref "CF18.1") (pin "17") (pinfunction "17_17") (pintype "passive"))
    )
    (net (code "746") (name "unconnected-(CF18.1-Pad18)") (class "Default")
      (node (ref "CF18.1") (pin "18") (pinfunction "18_18") (pintype "passive"))
    )
    (net (code "747") (name "unconnected-(CF18.1-Pad19)") (class "Default")
      (node (ref "CF18.1") (pin "19") (pinfunction "19_19") (pintype "passive"))
    )
    (net (code "748") (name "unconnected-(CF18.1-Pad20)") (class "Default")
      (node (ref "CF18.1") (pin "20") (pinfunction "20_20") (pintype "passive"))
    )
    (net (code "749") (name "unconnected-(CF18.2-Pad17)") (class "Default")
      (node (ref "CF18.2") (pin "17") (pinfunction "17_17") (pintype "passive"))
    )
    (net (code "750") (name "unconnected-(CF18.2-Pad18)") (class "Default")
      (node (ref "CF18.2") (pin "18") (pinfunction "18_18") (pintype "passive"))
    )
    (net (code "751") (name "unconnected-(CF18.2-Pad19)") (class "Default")
      (node (ref "CF18.2") (pin "19") (pinfunction "19_19") (pintype "passive"))
    )
    (net (code "752") (name "unconnected-(CF18.2-Pad20)") (class "Default")
      (node (ref "CF18.2") (pin "20") (pinfunction "20_20") (pintype "passive"))
    )
    (net (code "753") (name "unconnected-(CF18.2-Pad21)") (class "Default")
      (node (ref "CF18.2") (pin "21") (pinfunction "21_21") (pintype "passive"))
    )
    (net (code "754") (name "unconnected-(CF18.2-Pad22)") (class "Default")
      (node (ref "CF18.2") (pin "22") (pinfunction "22_22") (pintype "passive"))
    )
    (net (code "755") (name "unconnected-(CF18.2-Pad23)") (class "Default")
      (node (ref "CF18.2") (pin "23") (pinfunction "23_23") (pintype "passive"))
    )
    (net (code "756") (name "unconnected-(CF18.2-Pad24)") (class "Default")
      (node (ref "CF18.2") (pin "24") (pinfunction "24_24") (pintype "passive"))
    )
    (net (code "757") (name "unconnected-(CF18.2-Pad25)") (class "Default")
      (node (ref "CF18.2") (pin "25") (pinfunction "25_25") (pintype "passive"))
    )
    (net (code "758") (name "unconnected-(CF18.2-Pad26)") (class "Default")
      (node (ref "CF18.2") (pin "26") (pinfunction "26_26") (pintype "passive"))
    )
    (net (code "759") (name "unconnected-(CF18.2-Pad27)") (class "Default")
      (node (ref "CF18.2") (pin "27") (pinfunction "27_27") (pintype "passive"))
    )
    (net (code "760") (name "unconnected-(CF18.2-Pad28)") (class "Default")
      (node (ref "CF18.2") (pin "28") (pinfunction "28_28") (pintype "passive"))
    )
    (net (code "761") (name "unconnected-(CF18.2-Pad29)") (class "Default")
      (node (ref "CF18.2") (pin "29") (pinfunction "29_29") (pintype "passive"))
    )
    (net (code "762") (name "unconnected-(CF18.2-Pad30)") (class "Default")
      (node (ref "CF18.2") (pin "30") (pinfunction "30_30") (pintype "passive"))
    )
    (net (code "763") (name "unconnected-(CF18.2-Pad31)") (class "Default")
      (node (ref "CF18.2") (pin "31") (pinfunction "31_31") (pintype "passive"))
    )
    (net (code "764") (name "unconnected-(CF18.2-Pad32)") (class "Default")
      (node (ref "CF18.2") (pin "32") (pinfunction "32_32") (pintype "passive"))
    )
    (net (code "765") (name "unconnected-(CF18.2-Pad33)") (class "Default")
      (node (ref "CF18.2") (pin "33") (pinfunction "33_33") (pintype "passive"))
    )
    (net (code "766") (name "unconnected-(CF18.2-Pad34)") (class "Default")
      (node (ref "CF18.2") (pin "34") (pinfunction "34_34") (pintype "passive"))
    )
    (net (code "767") (name "unconnected-(CF18.2-Pad35)") (class "Default")
      (node (ref "CF18.2") (pin "35") (pinfunction "35_35") (pintype "passive"))
    )
    (net (code "768") (name "unconnected-(CF18.2-Pad36)") (class "Default")
      (node (ref "CF18.2") (pin "36") (pinfunction "36_36") (pintype "passive"))
    )
    (net (code "769") (name "unconnected-(CF18.2-Pad37)") (class "Default")
      (node (ref "CF18.2") (pin "37") (pinfunction "37_37") (pintype "passive"))
    )
    (net (code "770") (name "unconnected-(CF18.2-Pad38)") (class "Default")
      (node (ref "CF18.2") (pin "38") (pinfunction "38_38") (pintype "passive"))
    )
    (net (code "771") (name "unconnected-(CF18.2-Pad39)") (class "Default")
      (node (ref "CF18.2") (pin "39") (pinfunction "39_39") (pintype "passive"))
    )
    (net (code "772") (name "unconnected-(CF18.2-Pad40)") (class "Default")
      (node (ref "CF18.2") (pin "40") (pinfunction "40_40") (pintype "passive"))
    )
    (net (code "773") (name "unconnected-(CF19.1-Pad1)") (class "Default")
      (node (ref "CF19.1") (pin "1") (pinfunction "1_1") (pintype "passive"))
    )
    (net (code "774") (name "unconnected-(CF19.1-Pad2)") (class "Default")
      (node (ref "CF19.1") (pin "2") (pinfunction "2_2") (pintype "passive"))
    )
    (net (code "775") (name "unconnected-(CF19.1-Pad3)") (class "Default")
      (node (ref "CF19.1") (pin "3") (pinfunction "3_3") (pintype "passive"))
    )
    (net (code "776") (name "unconnected-(CF19.1-Pad4)") (class "Default")
      (node (ref "CF19.1") (pin "4") (pinfunction "4_4") (pintype "passive"))
    )
    (net (code "777") (name "unconnected-(CF19.1-Pad5)") (class "Default")
      (node (ref "CF19.1") (pin "5") (pinfunction "5_5") (pintype "passive"))
    )
    (net (code "778") (name "unconnected-(CF19.1-Pad6)") (class "Default")
      (node (ref "CF19.1") (pin "6") (pinfunction "6_6") (pintype "passive"))
    )
    (net (code "779") (name "unconnected-(CF19.1-Pad7)") (class "Default")
      (node (ref "CF19.1") (pin "7") (pinfunction "7_7") (pintype "passive"))
    )
    (net (code "780") (name "unconnected-(CF19.1-Pad8)") (class "Default")
      (node (ref "CF19.1") (pin "8") (pinfunction "8_8") (pintype "passive"))
    )
    (net (code "781") (name "unconnected-(CF19.1-Pad9)") (class "Default")
      (node (ref "CF19.1") (pin "9") (pinfunction "9_9") (pintype "passive"))
    )
    (net (code "782") (name "unconnected-(CF19.1-Pad10)") (class "Default")
      (node (ref "CF19.1") (pin "10") (pinfunction "10_10") (pintype "passive"))
    )
    (net (code "783") (name "unconnected-(CF19.1-Pad11)") (class "Default")
      (node (ref "CF19.1") (pin "11") (pinfunction "11_11") (pintype "passive"))
    )
    (net (code "784") (name "unconnected-(CF19.1-Pad12)") (class "Default")
      (node (ref "CF19.1") (pin "12") (pinfunction "12_12") (pintype "passive"))
    )
    (net (code "785") (name "unconnected-(CF19.1-Pad13)") (class "Default")
      (node (ref "CF19.1") (pin "13") (pinfunction "13_13") (pintype "passive"))
    )
    (net (code "786") (name "unconnected-(CF19.1-Pad14)") (class "Default")
      (node (ref "CF19.1") (pin "14") (pinfunction "14_14") (pintype "passive"))
    )
    (net (code "787") (name "unconnected-(CF19.1-Pad15)") (class "Default")
      (node (ref "CF19.1") (pin "15") (pinfunction "15_15") (pintype "passive"))
    )
    (net (code "788") (name "unconnected-(CF19.1-Pad16)") (class "Default")
      (node (ref "CF19.1") (pin "16") (pinfunction "16_16") (pintype "passive"))
    )
    (net (code "789") (name "unconnected-(CF19.1-Pad17)") (class "Default")
      (node (ref "CF19.1") (pin "17") (pinfunction "17_17") (pintype "passive"))
    )
    (net (code "790") (name "unconnected-(CF19.1-Pad18)") (class "Default")
      (node (ref "CF19.1") (pin "18") (pinfunction "18_18") (pintype "passive"))
    )
    (net (code "791") (name "unconnected-(CF19.1-Pad19)") (class "Default")
      (node (ref "CF19.1") (pin "19") (pinfunction "19_19") (pintype "passive"))
    )
    (net (code "792") (name "unconnected-(CF19.1-Pad20)") (class "Default")
      (node (ref "CF19.1") (pin "20") (pinfunction "20_20") (pintype "passive"))
    )
    (net (code "793") (name "unconnected-(CF19.2-Pad17)") (class "Default")
      (node (ref "CF19.2") (pin "17") (pinfunction "17_17") (pintype "passive"))
    )
    (net (code "794") (name "unconnected-(CF19.2-Pad18)") (class "Default")
      (node (ref "CF19.2") (pin "18") (pinfunction "18_18") (pintype "passive"))
    )
    (net (code "795") (name "unconnected-(CF19.2-Pad19)") (class "Default")
      (node (ref "CF19.2") (pin "19") (pinfunction "19_19") (pintype "passive"))
    )
    (net (code "796") (name "unconnected-(CF19.2-Pad20)") (class "Default")
      (node (ref "CF19.2") (pin "20") (pinfunction "20_20") (pintype "passive"))
    )
    (net (code "797") (name "unconnected-(CF19.2-Pad21)") (class "Default")
      (node (ref "CF19.2") (pin "21") (pinfunction "21_21") (pintype "passive"))
    )
    (net (code "798") (name "unconnected-(CF19.2-Pad22)") (class "Default")
      (node (ref "CF19.2") (pin "22") (pinfunction "22_22") (pintype "passive"))
    )
    (net (code "799") (name "unconnected-(CF19.2-Pad23)") (class "Default")
      (node (ref "CF19.2") (pin "23") (pinfunction "23_23") (pintype "passive"))
    )
    (net (code "800") (name "unconnected-(CF19.2-Pad24)") (class "Default")
      (node (ref "CF19.2") (pin "24") (pinfunction "24_24") (pintype "passive"))
    )
    (net (code "801") (name "unconnected-(CF19.2-Pad25)") (class "Default")
      (node (ref "CF19.2") (pin "25") (pinfunction "25_25") (pintype "passive"))
    )
    (net (code "802") (name "unconnected-(CF19.2-Pad26)") (class "Default")
      (node (ref "CF19.2") (pin "26") (pinfunction "26_26") (pintype "passive"))
    )
    (net (code "803") (name "unconnected-(CF19.2-Pad27)") (class "Default")
      (node (ref "CF19.2") (pin "27") (pinfunction "27_27") (pintype "passive"))
    )
    (net (code "804") (name "unconnected-(CF19.2-Pad28)") (class "Default")
      (node (ref "CF19.2") (pin "28") (pinfunction "28_28") (pintype "passive"))
    )
    (net (code "805") (name "unconnected-(CF19.2-Pad29)") (class "Default")
      (node (ref "CF19.2") (pin "29") (pinfunction "29_29") (pintype "passive"))
    )
    (net (code "806") (name "unconnected-(CF19.2-Pad30)") (class "Default")
      (node (ref "CF19.2") (pin "30") (pinfunction "30_30") (pintype "passive"))
    )
    (net (code "807") (name "unconnected-(CF19.2-Pad31)") (class "Default")
      (node (ref "CF19.2") (pin "31") (pinfunction "31_31") (pintype "passive"))
    )
    (net (code "808") (name "unconnected-(CF19.2-Pad32)") (class "Default")
      (node (ref "CF19.2") (pin "32") (pinfunction "32_32") (pintype "passive"))
    )
    (net (code "809") (name "unconnected-(CF19.2-Pad33)") (class "Default")
      (node (ref "CF19.2") (pin "33") (pinfunction "33_33") (pintype "passive"))
    )
    (net (code "810") (name "unconnected-(CF19.2-Pad34)") (class "Default")
      (node (ref "CF19.2") (pin "34") (pinfunction "34_34") (pintype "passive"))
    )
    (net (code "811") (name "unconnected-(CF19.2-Pad35)") (class "Default")
      (node (ref "CF19.2") (pin "35") (pinfunction "35_35") (pintype "passive"))
    )
    (net (code "812") (name "unconnected-(CF19.2-Pad36)") (class "Default")
      (node (ref "CF19.2") (pin "36") (pinfunction "36_36") (pintype "passive"))
    )
    (net (code "813") (name "unconnected-(CF19.2-Pad37)") (class "Default")
      (node (ref "CF19.2") (pin "37") (pinfunction "37_37") (pintype "passive"))
    )
    (net (code "814") (name "unconnected-(CF19.2-Pad38)") (class "Default")
      (node (ref "CF19.2") (pin "38") (pinfunction "38_38") (pintype "passive"))
    )
    (net (code "815") (name "unconnected-(CF19.2-Pad39)") (class "Default")
      (node (ref "CF19.2") (pin "39") (pinfunction "39_39") (pintype "passive"))
    )
    (net (code "816") (name "unconnected-(CF19.2-Pad40)") (class "Default")
      (node (ref "CF19.2") (pin "40") (pinfunction "40_40") (pintype "passive"))
    )
    (net (code "817") (name "unconnected-(CF20.1-Pad1)") (class "Default")
      (node (ref "CF20.1") (pin "1") (pinfunction "1_1") (pintype "passive"))
    )
    (net (code "818") (name "unconnected-(CF20.1-Pad2)") (class "Default")
      (node (ref "CF20.1") (pin "2") (pinfunction "2_2") (pintype "passive"))
    )
    (net (code "819") (name "unconnected-(CF20.1-Pad3)") (class "Default")
      (node (ref "CF20.1") (pin "3") (pinfunction "3_3") (pintype "passive"))
    )
    (net (code "820") (name "unconnected-(CF20.1-Pad4)") (class "Default")
      (node (ref "CF20.1") (pin "4") (pinfunction "4_4") (pintype "passive"))
    )
    (net (code "821") (name "unconnected-(CF20.1-Pad5)") (class "Default")
      (node (ref "CF20.1") (pin "5") (pinfunction "5_5") (pintype "passive"))
    )
    (net (code "822") (name "unconnected-(CF20.1-Pad6)") (class "Default")
      (node (ref "CF20.1") (pin "6") (pinfunction "6_6") (pintype "passive"))
    )
    (net (code "823") (name "unconnected-(CF20.1-Pad7)") (class "Default")
      (node (ref "CF20.1") (pin "7") (pinfunction "7_7") (pintype "passive"))
    )
    (net (code "824") (name "unconnected-(CF20.1-Pad8)") (class "Default")
      (node (ref "CF20.1") (pin "8") (pinfunction "8_8") (pintype "passive"))
    )
    (net (code "825") (name "unconnected-(CF20.1-Pad9)") (class "Default")
      (node (ref "CF20.1") (pin "9") (pinfunction "9_9") (pintype "passive"))
    )
    (net (code "826") (name "unconnected-(CF20.1-Pad10)") (class "Default")
      (node (ref "CF20.1") (pin "10") (pinfunction "10_10") (pintype "passive"))
    )
    (net (code "827") (name "unconnected-(CF20.1-Pad11)") (class "Default")
      (node (ref "CF20.1") (pin "11") (pinfunction "11_11") (pintype "passive"))
    )
    (net (code "828") (name "unconnected-(CF20.1-Pad12)") (class "Default")
      (node (ref "CF20.1") (pin "12") (pinfunction "12_12") (pintype "passive"))
    )
    (net (code "829") (name "unconnected-(CF20.1-Pad13)") (class "Default")
      (node (ref "CF20.1") (pin "13") (pinfunction "13_13") (pintype "passive"))
    )
    (net (code "830") (name "unconnected-(CF20.1-Pad14)") (class "Default")
      (node (ref "CF20.1") (pin "14") (pinfunction "14_14") (pintype "passive"))
    )
    (net (code "831") (name "unconnected-(CF20.1-Pad15)") (class "Default")
      (node (ref "CF20.1") (pin "15") (pinfunction "15_15") (pintype "passive"))
    )
    (net (code "832") (name "unconnected-(CF20.1-Pad16)") (class "Default")
      (node (ref "CF20.1") (pin "16") (pinfunction "16_16") (pintype "passive"))
    )
    (net (code "833") (name "unconnected-(CF20.1-Pad17)") (class "Default")
      (node (ref "CF20.1") (pin "17") (pinfunction "17_17") (pintype "passive"))
    )
    (net (code "834") (name "unconnected-(CF20.1-Pad18)") (class "Default")
      (node (ref "CF20.1") (pin "18") (pinfunction "18_18") (pintype "passive"))
    )
    (net (code "835") (name "unconnected-(CF20.1-Pad19)") (class "Default")
      (node (ref "CF20.1") (pin "19") (pinfunction "19_19") (pintype "passive"))
    )
    (net (code "836") (name "unconnected-(CF20.1-Pad20)") (class "Default")
      (node (ref "CF20.1") (pin "20") (pinfunction "20_20") (pintype "passive"))
    )
    (net (code "837") (name "unconnected-(CM1.1-PadRF-DOWN)") (class "Default")
      (node (ref "CM1.1") (pin "RF-DOWN") (pinfunction "RF-DOWN_RF-DOWN") (pintype "passive"))
    )
    (net (code "838") (name "unconnected-(CM1.1-PadRF-UP)") (class "Default")
      (node (ref "CM1.1") (pin "RF-UP") (pinfunction "RF-UP_RF-UP") (pintype "passive"))
    )
    (net (code "839") (name "unconnected-(CM1.2-PadRF-DOWN)") (class "Default")
      (node (ref "CM1.2") (pin "RF-DOWN") (pinfunction "RF-DOWN_RF-DOWN") (pintype "passive"))
    )
    (net (code "840") (name "unconnected-(CM1.2-PadRF-UP)") (class "Default")
      (node (ref "CM1.2") (pin "RF-UP") (pinfunction "RF-UP_RF-UP") (pintype "passive"))
    )
    (net (code "841") (name "unconnected-(CM1.3-PadRF-DOWN)") (class "Default")
      (node (ref "CM1.3") (pin "RF-DOWN") (pinfunction "RF-DOWN_RF-DOWN") (pintype "passive"))
    )
    (net (code "842") (name "unconnected-(CM1.3-PadRF-UP)") (class "Default")
      (node (ref "CM1.3") (pin "RF-UP") (pinfunction "RF-UP_RF-UP") (pintype "passive"))
    )
    (net (code "843") (name "unconnected-(CM2.1-PadRF-DOWN)") (class "Default")
      (node (ref "CM2.1") (pin "RF-DOWN") (pinfunction "RF-DOWN_RF-DOWN") (pintype "passive"))
    )
    (net (code "844") (name "unconnected-(CM2.1-PadRF-UP)") (class "Default")
      (node (ref "CM2.1") (pin "RF-UP") (pinfunction "RF-UP_RF-UP") (pintype "passive"))
    )
    (net (code "845") (name "unconnected-(CM2.2-PadRF-DOWN)") (class "Default")
      (node (ref "CM2.2") (pin "RF-DOWN") (pinfunction "RF-DOWN_RF-DOWN") (pintype "passive"))
    )
    (net (code "846") (name "unconnected-(CM2.2-PadRF-UP)") (class "Default")
      (node (ref "CM2.2") (pin "RF-UP") (pinfunction "RF-UP_RF-UP") (pintype "passive"))
    )
    (net (code "847") (name "unconnected-(CM2.3-PadRF-DOWN)") (class "Default")
      (node (ref "CM2.3") (pin "RF-DOWN") (pinfunction "RF-DOWN_RF-DOWN") (pintype "passive"))
    )
    (net (code "848") (name "unconnected-(CM2.3-PadRF-UP)") (class "Default")
      (node (ref "CM2.3") (pin "RF-UP") (pinfunction "RF-UP_RF-UP") (pintype "passive"))
    )
    (net (code "849") (name "unconnected-(CM3.1-PadRF-DOWN)") (class "Default")
      (node (ref "CM3.1") (pin "RF-DOWN") (pinfunction "RF-DOWN_RF-DOWN") (pintype "passive"))
    )
    (net (code "850") (name "unconnected-(CM3.1-PadRF-UP)") (class "Default")
      (node (ref "CM3.1") (pin "RF-UP") (pinfunction "RF-UP_RF-UP") (pintype "passive"))
    )
    (net (code "851") (name "unconnected-(CM3.2-PadRF-DOWN)") (class "Default")
      (node (ref "CM3.2") (pin "RF-DOWN") (pinfunction "RF-DOWN_RF-DOWN") (pintype "passive"))
    )
    (net (code "852") (name "unconnected-(CM3.2-PadRF-UP)") (class "Default")
      (node (ref "CM3.2") (pin "RF-UP") (pinfunction "RF-UP_RF-UP") (pintype "passive"))
    )
    (net (code "853") (name "unconnected-(CM3.3-PadRF-DOWN)") (class "Default")
      (node (ref "CM3.3") (pin "RF-DOWN") (pinfunction "RF-DOWN_RF-DOWN") (pintype "passive"))
    )
    (net (code "854") (name "unconnected-(CM3.3-PadRF-UP)") (class "Default")
      (node (ref "CM3.3") (pin "RF-UP") (pinfunction "RF-UP_RF-UP") (pintype "passive"))
    )
    (net (code "855") (name "unconnected-(CM4.1-PadRF-DOWN)") (class "Default")
      (node (ref "CM4.1") (pin "RF-DOWN") (pinfunction "RF-DOWN_RF-DOWN") (pintype "passive"))
    )
    (net (code "856") (name "unconnected-(CM4.1-PadRF-UP)") (class "Default")
      (node (ref "CM4.1") (pin "RF-UP") (pinfunction "RF-UP_RF-UP") (pintype "passive"))
    )
    (net (code "857") (name "unconnected-(CM4.2-PadRF-DOWN)") (class "Default")
      (node (ref "CM4.2") (pin "RF-DOWN") (pinfunction "RF-DOWN_RF-DOWN") (pintype "passive"))
    )
    (net (code "858") (name "unconnected-(CM4.2-PadRF-UP)") (class "Default")
      (node (ref "CM4.2") (pin "RF-UP") (pinfunction "RF-UP_RF-UP") (pintype "passive"))
    )
    (net (code "859") (name "unconnected-(CM4.3-PadRF-DOWN)") (class "Default")
      (node (ref "CM4.3") (pin "RF-DOWN") (pinfunction "RF-DOWN_RF-DOWN") (pintype "passive"))
    )
    (net (code "860") (name "unconnected-(CM4.3-PadRF-UP)") (class "Default")
      (node (ref "CM4.3") (pin "RF-UP") (pinfunction "RF-UP_RF-UP") (pintype "passive"))
    )
    (net (code "861") (name "unconnected-(CM5.1-PadRF-DOWN)") (class "Default")
      (node (ref "CM5.1") (pin "RF-DOWN") (pinfunction "RF-DOWN_RF-DOWN") (pintype "passive"))
    )
    (net (code "862") (name "unconnected-(CM5.1-PadRF-UP)") (class "Default")
      (node (ref "CM5.1") (pin "RF-UP") (pinfunction "RF-UP_RF-UP") (pintype "passive"))
    )
    (net (code "863") (name "unconnected-(CM5.2-PadRF-DOWN)") (class "Default")
      (node (ref "CM5.2") (pin "RF-DOWN") (pinfunction "RF-DOWN_RF-DOWN") (pintype "passive"))
    )
    (net (code "864") (name "unconnected-(CM5.2-PadRF-UP)") (class "Default")
      (node (ref "CM5.2") (pin "RF-UP") (pinfunction "RF-UP_RF-UP") (pintype "passive"))
    )
    (net (code "865") (name "unconnected-(CM5.3-PadRF-DOWN)") (class "Default")
      (node (ref "CM5.3") (pin "RF-DOWN") (pinfunction "RF-DOWN_RF-DOWN") (pintype "passive"))
    )
    (net (code "866") (name "unconnected-(CM5.3-PadRF-UP)") (class "Default")
      (node (ref "CM5.3") (pin "RF-UP") (pinfunction "RF-UP_RF-UP") (pintype "passive"))
    )
    (net (code "867") (name "unconnected-(CM6.1-PadRF-DOWN)") (class "Default")
      (node (ref "CM6.1") (pin "RF-DOWN") (pinfunction "RF-DOWN_RF-DOWN") (pintype "passive"))
    )
    (net (code "868") (name "unconnected-(CM6.1-PadRF-UP)") (class "Default")
      (node (ref "CM6.1") (pin "RF-UP") (pinfunction "RF-UP_RF-UP") (pintype "passive"))
    )
    (net (code "869") (name "unconnected-(CM6.2-PadRF-DOWN)") (class "Default")
      (node (ref "CM6.2") (pin "RF-DOWN") (pinfunction "RF-DOWN_RF-DOWN") (pintype "passive"))
    )
    (net (code "870") (name "unconnected-(CM6.2-PadRF-UP)") (class "Default")
      (node (ref "CM6.2") (pin "RF-UP") (pinfunction "RF-UP_RF-UP") (pintype "passive"))
    )
    (net (code "871") (name "unconnected-(CM6.3-PadRF-DOWN)") (class "Default")
      (node (ref "CM6.3") (pin "RF-DOWN") (pinfunction "RF-DOWN_RF-DOWN") (pintype "passive"))
    )
    (net (code "872") (name "unconnected-(CM6.3-PadRF-UP)") (class "Default")
      (node (ref "CM6.3") (pin "RF-UP") (pinfunction "RF-UP_RF-UP") (pintype "passive"))
    )
    (net (code "873") (name "unconnected-(CM7.1-PadRF-DOWN)") (class "Default")
      (node (ref "CM7.1") (pin "RF-DOWN") (pinfunction "RF-DOWN_RF-DOWN") (pintype "passive"))
    )
    (net (code "874") (name "unconnected-(CM7.1-PadRF-UP)") (class "Default")
      (node (ref "CM7.1") (pin "RF-UP") (pinfunction "RF-UP_RF-UP") (pintype "passive"))
    )
    (net (code "875") (name "unconnected-(CM7.2-PadRF-DOWN)") (class "Default")
      (node (ref "CM7.2") (pin "RF-DOWN") (pinfunction "RF-DOWN_RF-DOWN") (pintype "passive"))
    )
    (net (code "876") (name "unconnected-(CM7.2-PadRF-UP)") (class "Default")
      (node (ref "CM7.2") (pin "RF-UP") (pinfunction "RF-UP_RF-UP") (pintype "passive"))
    )
    (net (code "877") (name "unconnected-(CM7.3-PadRF-DOWN)") (class "Default")
      (node (ref "CM7.3") (pin "RF-DOWN") (pinfunction "RF-DOWN_RF-DOWN") (pintype "passive"))
    )
    (net (code "878") (name "unconnected-(CM7.3-PadRF-UP)") (class "Default")
      (node (ref "CM7.3") (pin "RF-UP") (pinfunction "RF-UP_RF-UP") (pintype "passive"))
    )
    (net (code "879") (name "unconnected-(CM8.1-PadRF-DOWN)") (class "Default")
      (node (ref "CM8.1") (pin "RF-DOWN") (pinfunction "RF-DOWN_RF-DOWN") (pintype "passive"))
    )
    (net (code "880") (name "unconnected-(CM8.1-PadRF-UP)") (class "Default")
      (node (ref "CM8.1") (pin "RF-UP") (pinfunction "RF-UP_RF-UP") (pintype "passive"))
    )
    (net (code "881") (name "unconnected-(CM8.2-PadRF-DOWN)") (class "Default")
      (node (ref "CM8.2") (pin "RF-DOWN") (pinfunction "RF-DOWN_RF-DOWN") (pintype "passive"))
    )
    (net (code "882") (name "unconnected-(CM8.2-PadRF-UP)") (class "Default")
      (node (ref "CM8.2") (pin "RF-UP") (pinfunction "RF-UP_RF-UP") (pintype "passive"))
    )
    (net (code "883") (name "unconnected-(CM8.3-PadRF-DOWN)") (class "Default")
      (node (ref "CM8.3") (pin "RF-DOWN") (pinfunction "RF-DOWN_RF-DOWN") (pintype "passive"))
    )
    (net (code "884") (name "unconnected-(CM8.3-PadRF-UP)") (class "Default")
      (node (ref "CM8.3") (pin "RF-UP") (pinfunction "RF-UP_RF-UP") (pintype "passive"))
    )
    (net (code "885") (name "unconnected-(CM9.1-PadRF-DOWN)") (class "Default")
      (node (ref "CM9.1") (pin "RF-DOWN") (pinfunction "RF-DOWN_RF-DOWN") (pintype "passive"))
    )
    (net (code "886") (name "unconnected-(CM9.1-PadRF-UP)") (class "Default")
      (node (ref "CM9.1") (pin "RF-UP") (pinfunction "RF-UP_RF-UP") (pintype "passive"))
    )
    (net (code "887") (name "unconnected-(CM9.2-PadRF-DOWN)") (class "Default")
      (node (ref "CM9.2") (pin "RF-DOWN") (pinfunction "RF-DOWN_RF-DOWN") (pintype "passive"))
    )
    (net (code "888") (name "unconnected-(CM9.2-PadRF-UP)") (class "Default")
      (node (ref "CM9.2") (pin "RF-UP") (pinfunction "RF-UP_RF-UP") (pintype "passive"))
    )
    (net (code "889") (name "unconnected-(CM9.3-PadRF-DOWN)") (class "Default")
      (node (ref "CM9.3") (pin "RF-DOWN") (pinfunction "RF-DOWN_RF-DOWN") (pintype "passive"))
    )
    (net (code "890") (name "unconnected-(CM9.3-PadRF-UP)") (class "Default")
      (node (ref "CM9.3") (pin "RF-UP") (pinfunction "RF-UP_RF-UP") (pintype "passive"))
    )
    (net (code "891") (name "unconnected-(CM10.1-PadRF-DOWN)") (class "Default")
      (node (ref "CM10.1") (pin "RF-DOWN") (pinfunction "RF-DOWN_RF-DOWN") (pintype "passive"))
    )
    (net (code "892") (name "unconnected-(CM10.1-PadRF-UP)") (class "Default")
      (node (ref "CM10.1") (pin "RF-UP") (pinfunction "RF-UP_RF-UP") (pintype "passive"))
    )
    (net (code "893") (name "unconnected-(CM10.2-PadRF-DOWN)") (class "Default")
      (node (ref "CM10.2") (pin "RF-DOWN") (pinfunction "RF-DOWN_RF-DOWN") (pintype "passive"))
    )
    (net (code "894") (name "unconnected-(CM10.2-PadRF-UP)") (class "Default")
      (node (ref "CM10.2") (pin "RF-UP") (pinfunction "RF-UP_RF-UP") (pintype "passive"))
    )
    (net (code "895") (name "unconnected-(CM10.3-PadRF-DOWN)") (class "Default")
      (node (ref "CM10.3") (pin "RF-DOWN") (pinfunction "RF-DOWN_RF-DOWN") (pintype "passive"))
    )
    (net (code "896") (name "unconnected-(CM10.3-PadRF-UP)") (class "Default")
      (node (ref "CM10.3") (pin "RF-UP") (pinfunction "RF-UP_RF-UP") (pintype "passive"))
    )
    (net (code "897") (name "unconnected-(CM11.1-PadRF-DOWN)") (class "Default")
      (node (ref "CM11.1") (pin "RF-DOWN") (pinfunction "RF-DOWN_RF-DOWN") (pintype "passive"))
    )
    (net (code "898") (name "unconnected-(CM11.1-PadRF-UP)") (class "Default")
      (node (ref "CM11.1") (pin "RF-UP") (pinfunction "RF-UP_RF-UP") (pintype "passive"))
    )
    (net (code "899") (name "unconnected-(CM11.2-PadRF-DOWN)") (class "Default")
      (node (ref "CM11.2") (pin "RF-DOWN") (pinfunction "RF-DOWN_RF-DOWN") (pintype "passive"))
    )
    (net (code "900") (name "unconnected-(CM11.2-PadRF-UP)") (class "Default")
      (node (ref "CM11.2") (pin "RF-UP") (pinfunction "RF-UP_RF-UP") (pintype "passive"))
    )
    (net (code "901") (name "unconnected-(CM11.3-PadRF-DOWN)") (class "Default")
      (node (ref "CM11.3") (pin "RF-DOWN") (pinfunction "RF-DOWN_RF-DOWN") (pintype "passive"))
    )
    (net (code "902") (name "unconnected-(CM11.3-PadRF-UP)") (class "Default")
      (node (ref "CM11.3") (pin "RF-UP") (pinfunction "RF-UP_RF-UP") (pintype "passive"))
    )
    (net (code "903") (name "unconnected-(CM12.1-PadRF-DOWN)") (class "Default")
      (node (ref "CM12.1") (pin "RF-DOWN") (pinfunction "RF-DOWN_RF-DOWN") (pintype "passive"))
    )
    (net (code "904") (name "unconnected-(CM12.1-PadRF-UP)") (class "Default")
      (node (ref "CM12.1") (pin "RF-UP") (pinfunction "RF-UP_RF-UP") (pintype "passive"))
    )
    (net (code "905") (name "unconnected-(CM12.2-PadRF-DOWN)") (class "Default")
      (node (ref "CM12.2") (pin "RF-DOWN") (pinfunction "RF-DOWN_RF-DOWN") (pintype "passive"))
    )
    (net (code "906") (name "unconnected-(CM12.2-PadRF-UP)") (class "Default")
      (node (ref "CM12.2") (pin "RF-UP") (pinfunction "RF-UP_RF-UP") (pintype "passive"))
    )
    (net (code "907") (name "unconnected-(CM12.3-PadRF-DOWN)") (class "Default")
      (node (ref "CM12.3") (pin "RF-DOWN") (pinfunction "RF-DOWN_RF-DOWN") (pintype "passive"))
    )
    (net (code "908") (name "unconnected-(CM12.3-PadRF-UP)") (class "Default")
      (node (ref "CM12.3") (pin "RF-UP") (pinfunction "RF-UP_RF-UP") (pintype "passive"))
    )
    (net (code "909") (name "unconnected-(CM13.1-PadRF-DOWN)") (class "Default")
      (node (ref "CM13.1") (pin "RF-DOWN") (pinfunction "RF-DOWN_RF-DOWN") (pintype "passive"))
    )
    (net (code "910") (name "unconnected-(CM13.1-PadRF-UP)") (class "Default")
      (node (ref "CM13.1") (pin "RF-UP") (pinfunction "RF-UP_RF-UP") (pintype "passive"))
    )
    (net (code "911") (name "unconnected-(CM13.2-PadRF-DOWN)") (class "Default")
      (node (ref "CM13.2") (pin "RF-DOWN") (pinfunction "RF-DOWN_RF-DOWN") (pintype "passive"))
    )
    (net (code "912") (name "unconnected-(CM13.2-PadRF-UP)") (class "Default")
      (node (ref "CM13.2") (pin "RF-UP") (pinfunction "RF-UP_RF-UP") (pintype "passive"))
    )
    (net (code "913") (name "unconnected-(CM13.3-PadRF-DOWN)") (class "Default")
      (node (ref "CM13.3") (pin "RF-DOWN") (pinfunction "RF-DOWN_RF-DOWN") (pintype "passive"))
    )
    (net (code "914") (name "unconnected-(CM13.3-PadRF-UP)") (class "Default")
      (node (ref "CM13.3") (pin "RF-UP") (pinfunction "RF-UP_RF-UP") (pintype "passive"))
    )
    (net (code "915") (name "unconnected-(CM14.1-PadRF-DOWN)") (class "Default")
      (node (ref "CM14.1") (pin "RF-DOWN") (pinfunction "RF-DOWN_RF-DOWN") (pintype "passive"))
    )
    (net (code "916") (name "unconnected-(CM14.1-PadRF-UP)") (class "Default")
      (node (ref "CM14.1") (pin "RF-UP") (pinfunction "RF-UP_RF-UP") (pintype "passive"))
    )
    (net (code "917") (name "unconnected-(CM14.2-PadRF-DOWN)") (class "Default")
      (node (ref "CM14.2") (pin "RF-DOWN") (pinfunction "RF-DOWN_RF-DOWN") (pintype "passive"))
    )
    (net (code "918") (name "unconnected-(CM14.2-PadRF-UP)") (class "Default")
      (node (ref "CM14.2") (pin "RF-UP") (pinfunction "RF-UP_RF-UP") (pintype "passive"))
    )
    (net (code "919") (name "unconnected-(CM14.3-PadRF-DOWN)") (class "Default")
      (node (ref "CM14.3") (pin "RF-DOWN") (pinfunction "RF-DOWN_RF-DOWN") (pintype "passive"))
    )
    (net (code "920") (name "unconnected-(CM14.3-PadRF-UP)") (class "Default")
      (node (ref "CM14.3") (pin "RF-UP") (pinfunction "RF-UP_RF-UP") (pintype "passive"))
    )
    (net (code "921") (name "unconnected-(CM15.1-PadRF-DOWN)") (class "Default")
      (node (ref "CM15.1") (pin "RF-DOWN") (pinfunction "RF-DOWN_RF-DOWN") (pintype "passive"))
    )
    (net (code "922") (name "unconnected-(CM15.1-PadRF-UP)") (class "Default")
      (node (ref "CM15.1") (pin "RF-UP") (pinfunction "RF-UP_RF-UP") (pintype "passive"))
    )
    (net (code "923") (name "unconnected-(CM15.2-PadRF-DOWN)") (class "Default")
      (node (ref "CM15.2") (pin "RF-DOWN") (pinfunction "RF-DOWN_RF-DOWN") (pintype "passive"))
    )
    (net (code "924") (name "unconnected-(CM15.2-PadRF-UP)") (class "Default")
      (node (ref "CM15.2") (pin "RF-UP") (pinfunction "RF-UP_RF-UP") (pintype "passive"))
    )
    (net (code "925") (name "unconnected-(CM15.3-PadRF-DOWN)") (class "Default")
      (node (ref "CM15.3") (pin "RF-DOWN") (pinfunction "RF-DOWN_RF-DOWN") (pintype "passive"))
    )
    (net (code "926") (name "unconnected-(CM15.3-PadRF-UP)") (class "Default")
      (node (ref "CM15.3") (pin "RF-UP") (pinfunction "RF-UP_RF-UP") (pintype "passive"))
    )
    (net (code "927") (name "unconnected-(CM16.1-PadRF-DOWN)") (class "Default")
      (node (ref "CM16.1") (pin "RF-DOWN") (pinfunction "RF-DOWN_RF-DOWN") (pintype "passive"))
    )
    (net (code "928") (name "unconnected-(CM16.1-PadRF-UP)") (class "Default")
      (node (ref "CM16.1") (pin "RF-UP") (pinfunction "RF-UP_RF-UP") (pintype "passive"))
    )
    (net (code "929") (name "unconnected-(CM16.2-PadRF-DOWN)") (class "Default")
      (node (ref "CM16.2") (pin "RF-DOWN") (pinfunction "RF-DOWN_RF-DOWN") (pintype "passive"))
    )
    (net (code "930") (name "unconnected-(CM16.2-PadRF-UP)") (class "Default")
      (node (ref "CM16.2") (pin "RF-UP") (pinfunction "RF-UP_RF-UP") (pintype "passive"))
    )
    (net (code "931") (name "unconnected-(CM16.3-PadRF-DOWN)") (class "Default")
      (node (ref "CM16.3") (pin "RF-DOWN") (pinfunction "RF-DOWN_RF-DOWN") (pintype "passive"))
    )
    (net (code "932") (name "unconnected-(CM16.3-PadRF-UP)") (class "Default")
      (node (ref "CM16.3") (pin "RF-UP") (pinfunction "RF-UP_RF-UP") (pintype "passive"))
    )
    (net (code "933") (name "unconnected-(CM17.1-PadRF-DOWN)") (class "Default")
      (node (ref "CM17.1") (pin "RF-DOWN") (pinfunction "RF-DOWN_RF-DOWN") (pintype "passive"))
    )
    (net (code "934") (name "unconnected-(CM17.1-PadRF-UP)") (class "Default")
      (node (ref "CM17.1") (pin "RF-UP") (pinfunction "RF-UP_RF-UP") (pintype "passive"))
    )
    (net (code "935") (name "unconnected-(CM17.2-PadRF-DOWN)") (class "Default")
      (node (ref "CM17.2") (pin "RF-DOWN") (pinfunction "RF-DOWN_RF-DOWN") (pintype "passive"))
    )
    (net (code "936") (name "unconnected-(CM17.2-PadRF-UP)") (class "Default")
      (node (ref "CM17.2") (pin "RF-UP") (pinfunction "RF-UP_RF-UP") (pintype "passive"))
    )
    (net (code "937") (name "unconnected-(CM17.3-PadRF-DOWN)") (class "Default")
      (node (ref "CM17.3") (pin "RF-DOWN") (pinfunction "RF-DOWN_RF-DOWN") (pintype "passive"))
    )
    (net (code "938") (name "unconnected-(CM17.3-PadRF-UP)") (class "Default")
      (node (ref "CM17.3") (pin "RF-UP") (pinfunction "RF-UP_RF-UP") (pintype "passive"))
    )
    (net (code "939") (name "unconnected-(CM18.1-PadRF-DOWN)") (class "Default")
      (node (ref "CM18.1") (pin "RF-DOWN") (pinfunction "RF-DOWN_RF-DOWN") (pintype "passive"))
    )
    (net (code "940") (name "unconnected-(CM18.1-PadRF-UP)") (class "Default")
      (node (ref "CM18.1") (pin "RF-UP") (pinfunction "RF-UP_RF-UP") (pintype "passive"))
    )
    (net (code "941") (name "unconnected-(CM18.2-PadRF-DOWN)") (class "Default")
      (node (ref "CM18.2") (pin "RF-DOWN") (pinfunction "RF-DOWN_RF-DOWN") (pintype "passive"))
    )
    (net (code "942") (name "unconnected-(CM18.2-PadRF-UP)") (class "Default")
      (node (ref "CM18.2") (pin "RF-UP") (pinfunction "RF-UP_RF-UP") (pintype "passive"))
    )
    (net (code "943") (name "unconnected-(CM18.3-PadRF-DOWN)") (class "Default")
      (node (ref "CM18.3") (pin "RF-DOWN") (pinfunction "RF-DOWN_RF-DOWN") (pintype "passive"))
    )
    (net (code "944") (name "unconnected-(CM18.3-PadRF-UP)") (class "Default")
      (node (ref "CM18.3") (pin "RF-UP") (pinfunction "RF-UP_RF-UP") (pintype "passive"))
    )
    (net (code "945") (name "unconnected-(CM19.1-PadRF-DOWN)") (class "Default")
      (node (ref "CM19.1") (pin "RF-DOWN") (pinfunction "RF-DOWN_RF-DOWN") (pintype "passive"))
    )
    (net (code "946") (name "unconnected-(CM19.1-PadRF-UP)") (class "Default")
      (node (ref "CM19.1") (pin "RF-UP") (pinfunction "RF-UP_RF-UP") (pintype "passive"))
    )
    (net (code "947") (name "unconnected-(CM19.2-PadRF-DOWN)") (class "Default")
      (node (ref "CM19.2") (pin "RF-DOWN") (pinfunction "RF-DOWN_RF-DOWN") (pintype "passive"))
    )
    (net (code "948") (name "unconnected-(CM19.2-PadRF-UP)") (class "Default")
      (node (ref "CM19.2") (pin "RF-UP") (pinfunction "RF-UP_RF-UP") (pintype "passive"))
    )
    (net (code "949") (name "unconnected-(CM19.3-PadRF-DOWN)") (class "Default")
      (node (ref "CM19.3") (pin "RF-DOWN") (pinfunction "RF-DOWN_RF-DOWN") (pintype "passive"))
    )
    (net (code "950") (name "unconnected-(CM19.3-PadRF-UP)") (class "Default")
      (node (ref "CM19.3") (pin "RF-UP") (pinfunction "RF-UP_RF-UP") (pintype "passive"))
    )
    (net (code "951") (name "unconnected-(CM20.1-PadRF-DOWN)") (class "Default")
      (node (ref "CM20.1") (pin "RF-DOWN") (pinfunction "RF-DOWN_RF-DOWN") (pintype "passive"))
    )
    (net (code "952") (name "unconnected-(CM20.1-PadRF-UP)") (class "Default")
      (node (ref "CM20.1") (pin "RF-UP") (pinfunction "RF-UP_RF-UP") (pintype "passive"))
    )
    (net (code "953") (name "unconnected-(CM20.2-PadRF-DOWN)") (class "Default")
      (node (ref "CM20.2") (pin "RF-DOWN") (pinfunction "RF-DOWN_RF-DOWN") (pintype "passive"))
    )
    (net (code "954") (name "unconnected-(CM20.2-PadRF-UP)") (class "Default")
      (node (ref "CM20.2") (pin "RF-UP") (pinfunction "RF-UP_RF-UP") (pintype "passive"))
    )
    (net (code "955") (name "unconnected-(CM20.3-PadRF-DOWN)") (class "Default")
      (node (ref "CM20.3") (pin "RF-DOWN") (pinfunction "RF-DOWN_RF-DOWN") (pintype "passive"))
    )
    (net (code "956") (name "unconnected-(CM20.3-PadRF-UP)") (class "Default")
      (node (ref "CM20.3") (pin "RF-UP") (pinfunction "RF-UP_RF-UP") (pintype "passive"))
    )
    (net (code "957") (name "~{SHUTDOWN}") (class "Default")
      (node (ref "CF10.2") (pin "7") (pinfunction "7_7") (pintype "passive"))
      (node (ref "CF10.2") (pin "8") (pinfunction "8_8") (pintype "passive"))
      (node (ref "CF11.2") (pin "7") (pinfunction "7_7") (pintype "passive"))
      (node (ref "CF11.2") (pin "8") (pinfunction "8_8") (pintype "passive"))
      (node (ref "CF12.2") (pin "7") (pinfunction "7_7") (pintype "passive"))
      (node (ref "CF12.2") (pin "8") (pinfunction "8_8") (pintype "passive"))
      (node (ref "CF13.2") (pin "7") (pinfunction "7_7") (pintype "passive"))
      (node (ref "CF13.2") (pin "8") (pinfunction "8_8") (pintype "passive"))
      (node (ref "CF14.2") (pin "7") (pinfunction "7_7") (pintype "passive"))
      (node (ref "CF14.2") (pin "8") (pinfunction "8_8") (pintype "passive"))
      (node (ref "CF15.2") (pin "7") (pinfunction "7_7") (pintype "passive"))
      (node (ref "CF15.2") (pin "8") (pinfunction "8_8") (pintype "passive"))
      (node (ref "CF16.2") (pin "7") (pinfunction "7_7") (pintype "passive"))
      (node (ref "CF16.2") (pin "8") (pinfunction "8_8") (pintype "passive"))
      (node (ref "CF17.2") (pin "7") (pinfunction "7_7") (pintype "passive"))
      (node (ref "CF17.2") (pin "8") (pinfunction "8_8") (pintype "passive"))
      (node (ref "CF18.2") (pin "7") (pinfunction "7_7") (pintype "passive"))
      (node (ref "CF18.2") (pin "8") (pinfunction "8_8") (pintype "passive"))
      (node (ref "CF19.2") (pin "7") (pinfunction "7_7") (pintype "passive"))
      (node (ref "CF19.2") (pin "8") (pinfunction "8_8") (pintype "passive"))
      (node (ref "CF2.2") (pin "7") (pinfunction "7_7") (pintype "passive"))
      (node (ref "CF2.2") (pin "8") (pinfunction "8_8") (pintype "passive"))
      (node (ref "CF3.2") (pin "7") (pinfunction "7_7") (pintype "passive"))
      (node (ref "CF3.2") (pin "8") (pinfunction "8_8") (pintype "passive"))
      (node (ref "CF4.2") (pin "7") (pinfunction "7_7") (pintype "passive"))
      (node (ref "CF4.2") (pin "8") (pinfunction "8_8") (pintype "passive"))
      (node (ref "CF5.2") (pin "7") (pinfunction "7_7") (pintype "passive"))
      (node (ref "CF5.2") (pin "8") (pinfunction "8_8") (pintype "passive"))
      (node (ref "CF6.2") (pin "7") (pinfunction "7_7") (pintype "passive"))
      (node (ref "CF6.2") (pin "8") (pinfunction "8_8") (pintype "passive"))
      (node (ref "CF7.2") (pin "7") (pinfunction "7_7") (pintype "passive"))
      (node (ref "CF7.2") (pin "8") (pinfunction "8_8") (pintype "passive"))
      (node (ref "CF8.2") (pin "7") (pinfunction "7_7") (pintype "passive"))
      (node (ref "CF8.2") (pin "8") (pinfunction "8_8") (pintype "passive"))
      (node (ref "CF9.2") (pin "7") (pinfunction "7_7") (pintype "passive"))
      (node (ref "CF9.2") (pin "8") (pinfunction "8_8") (pintype "passive"))
    )
  )
)
